# Botball_v7.net
KiCad netlist of a schematic drawn in EAGLE
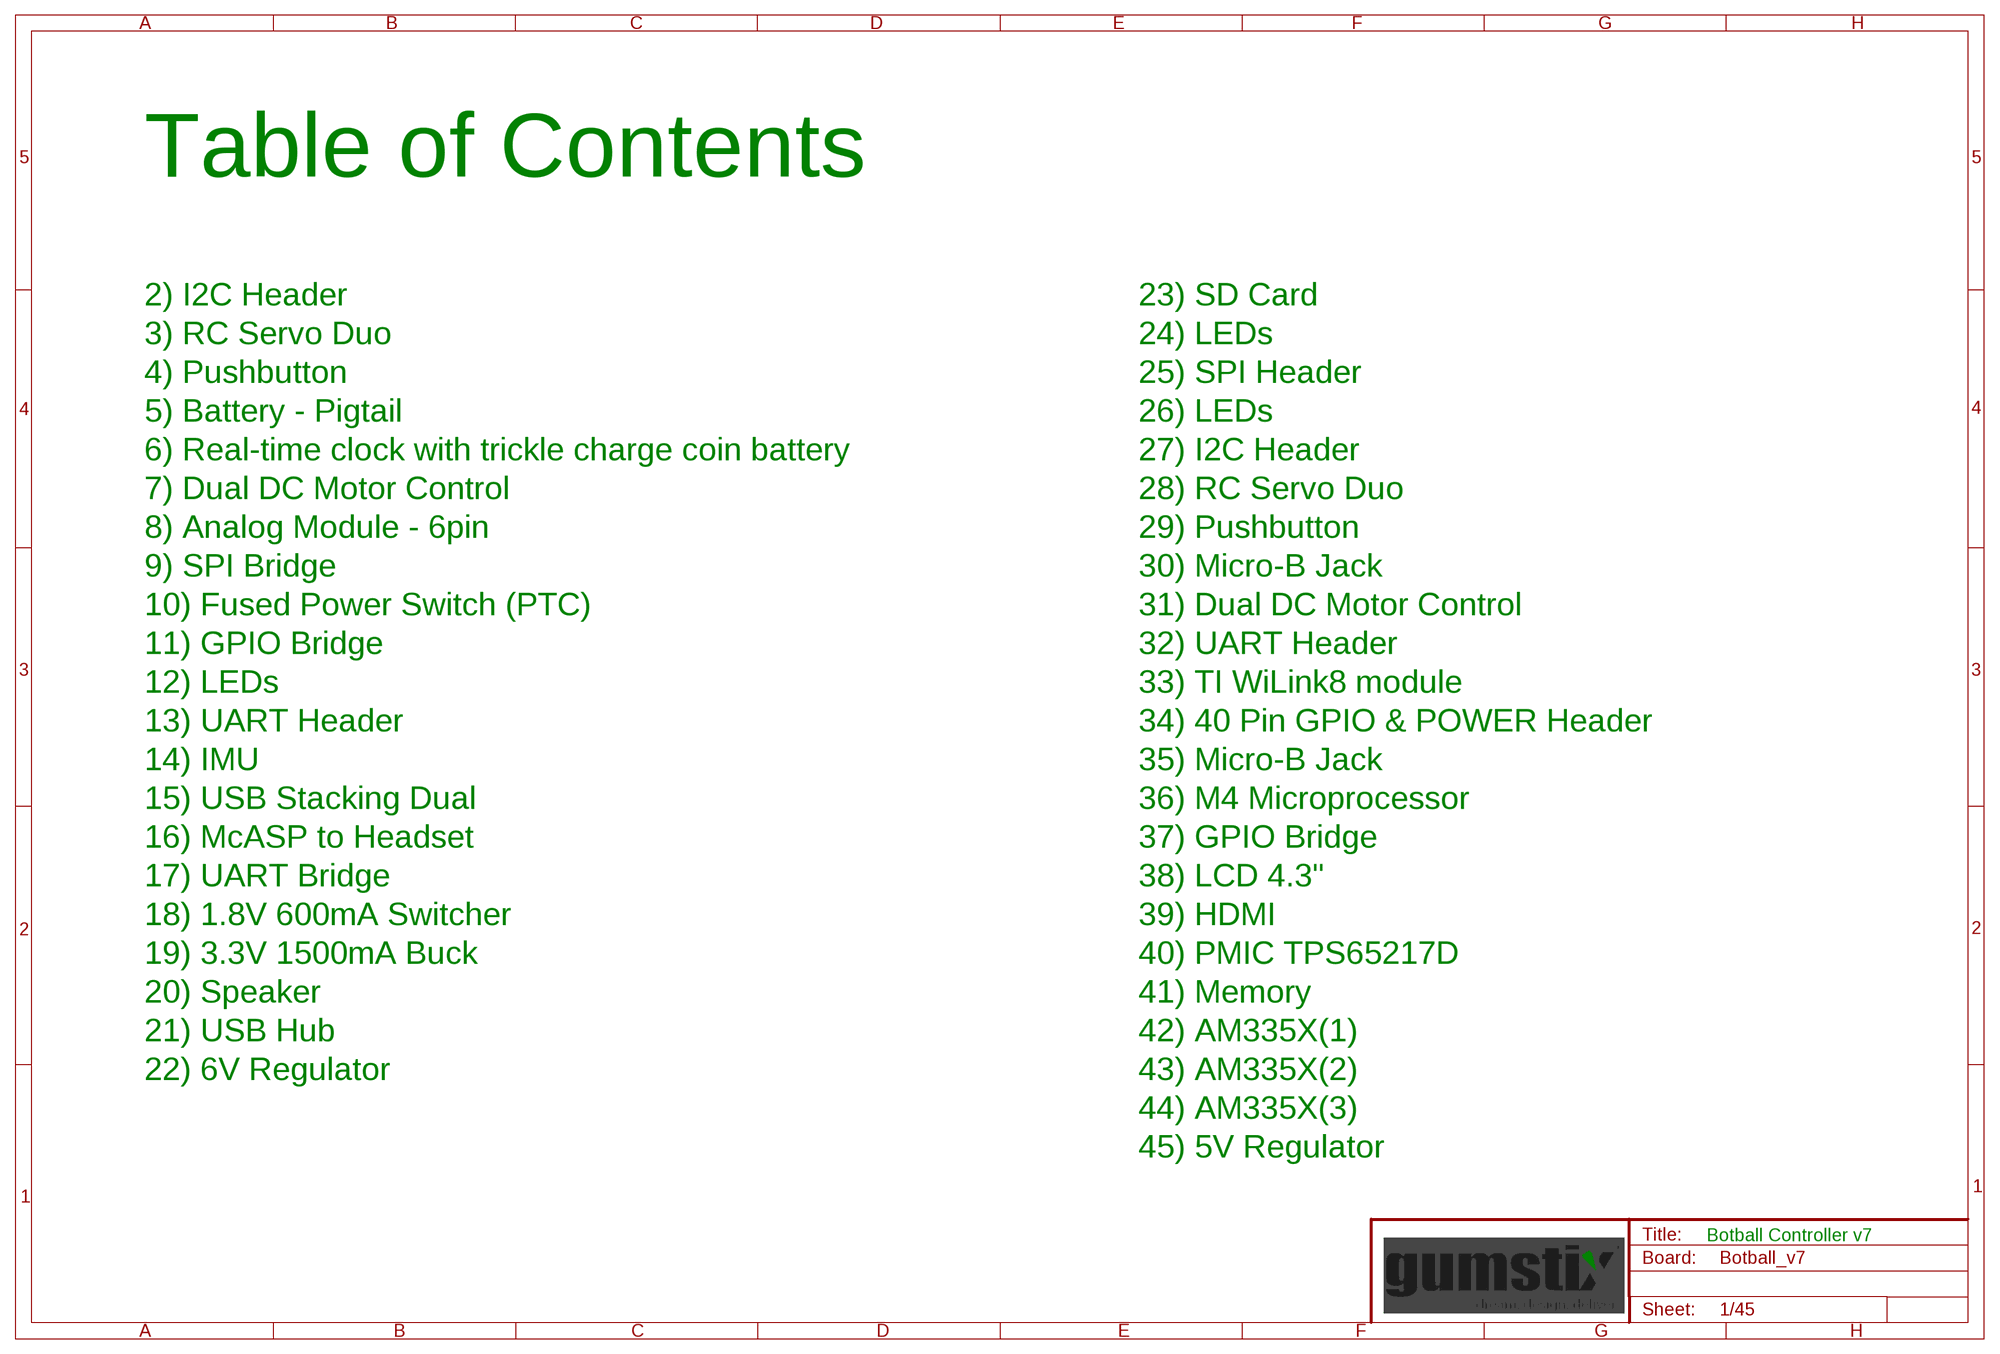
[diagram p0: schematic, sheet 1]
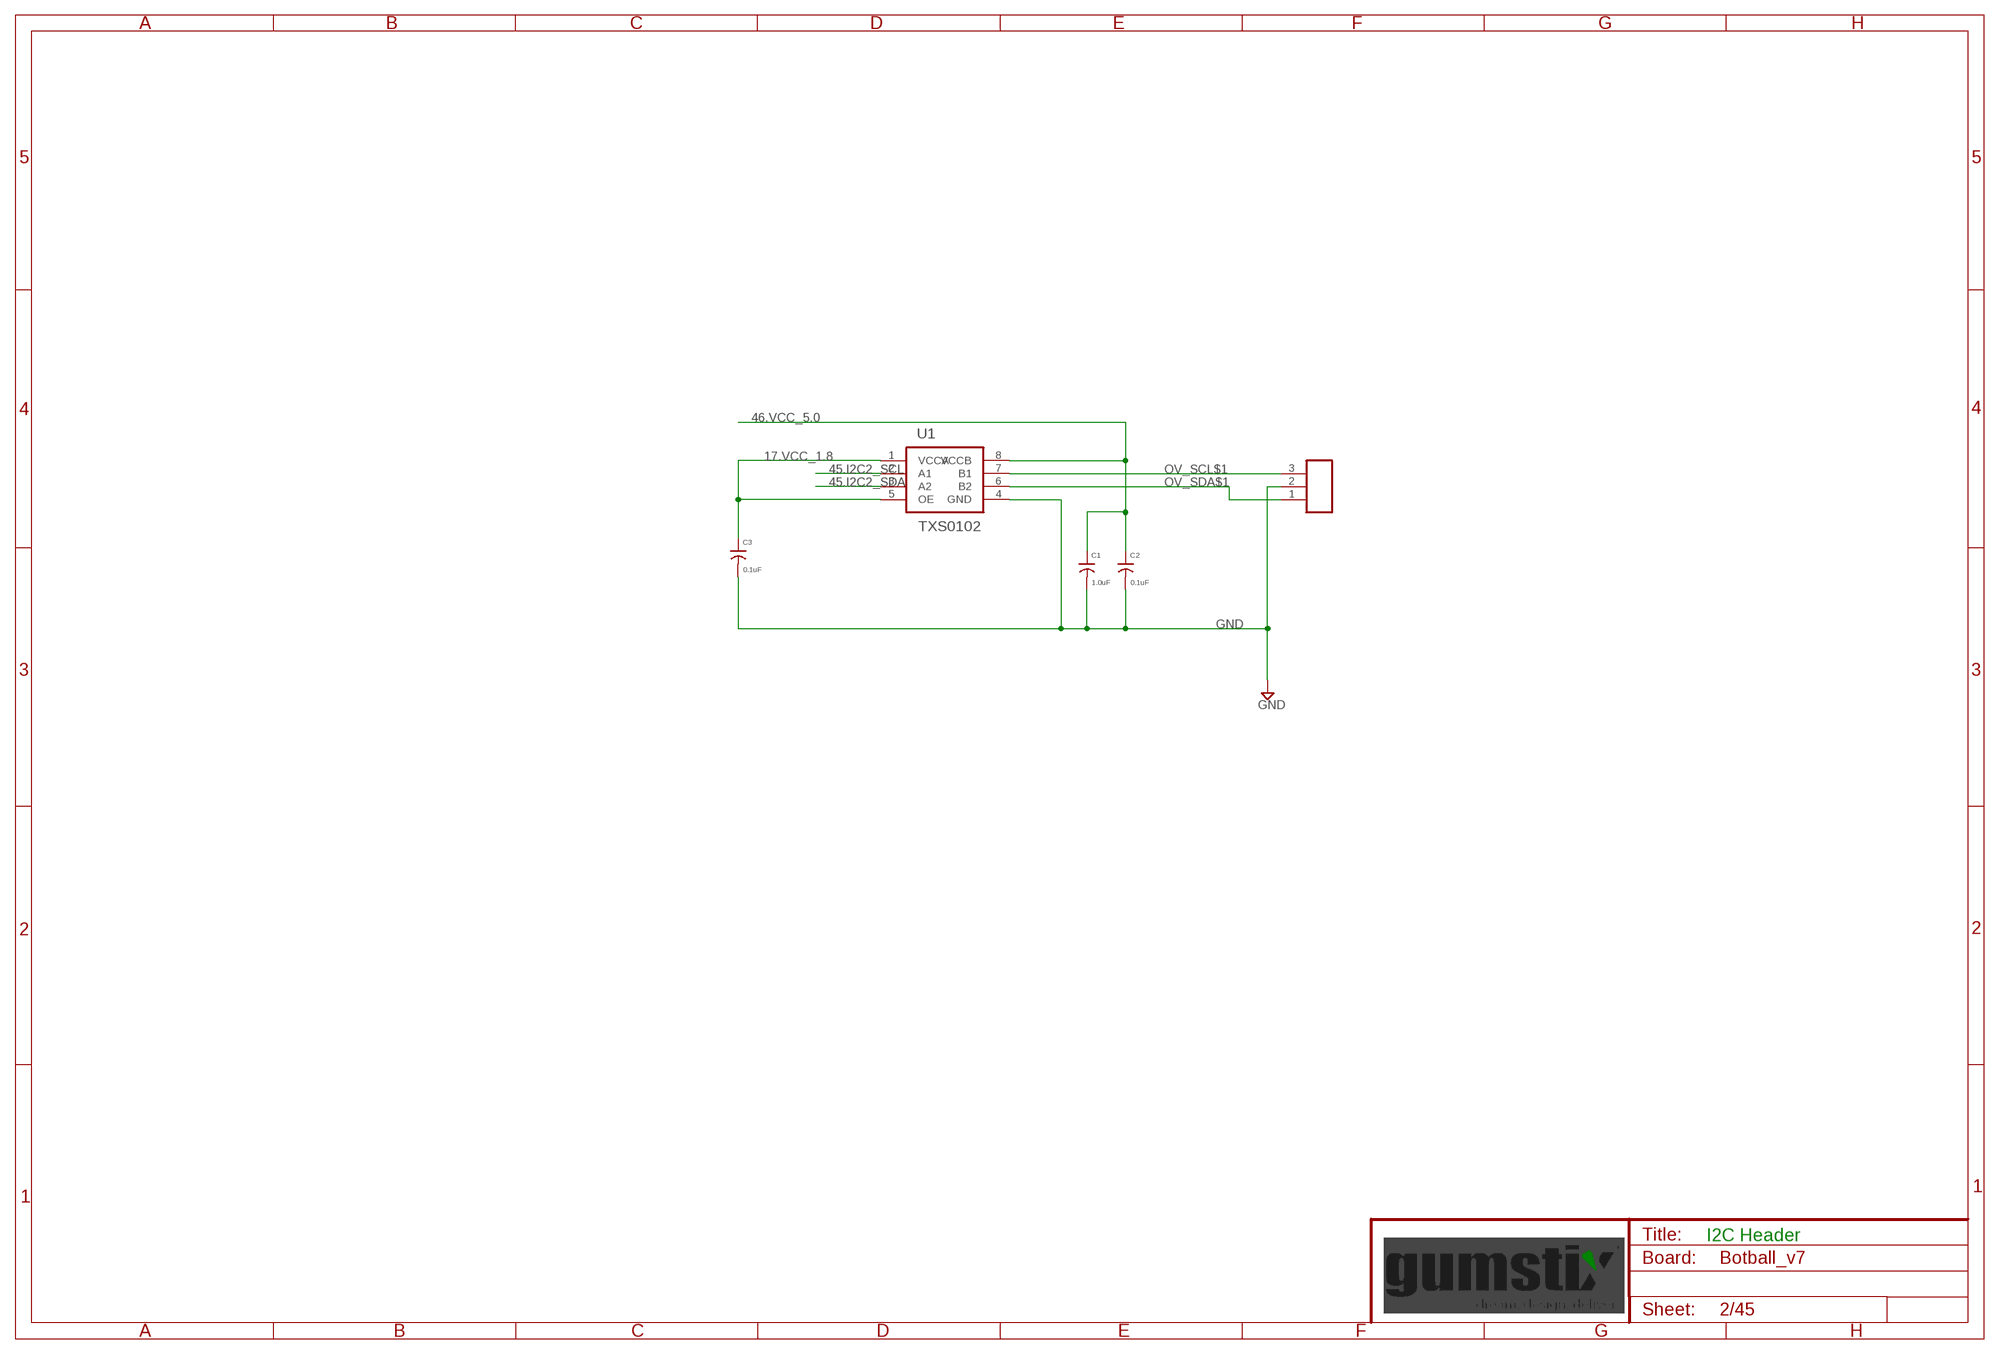
[diagram p1: schematic, sheet 2]
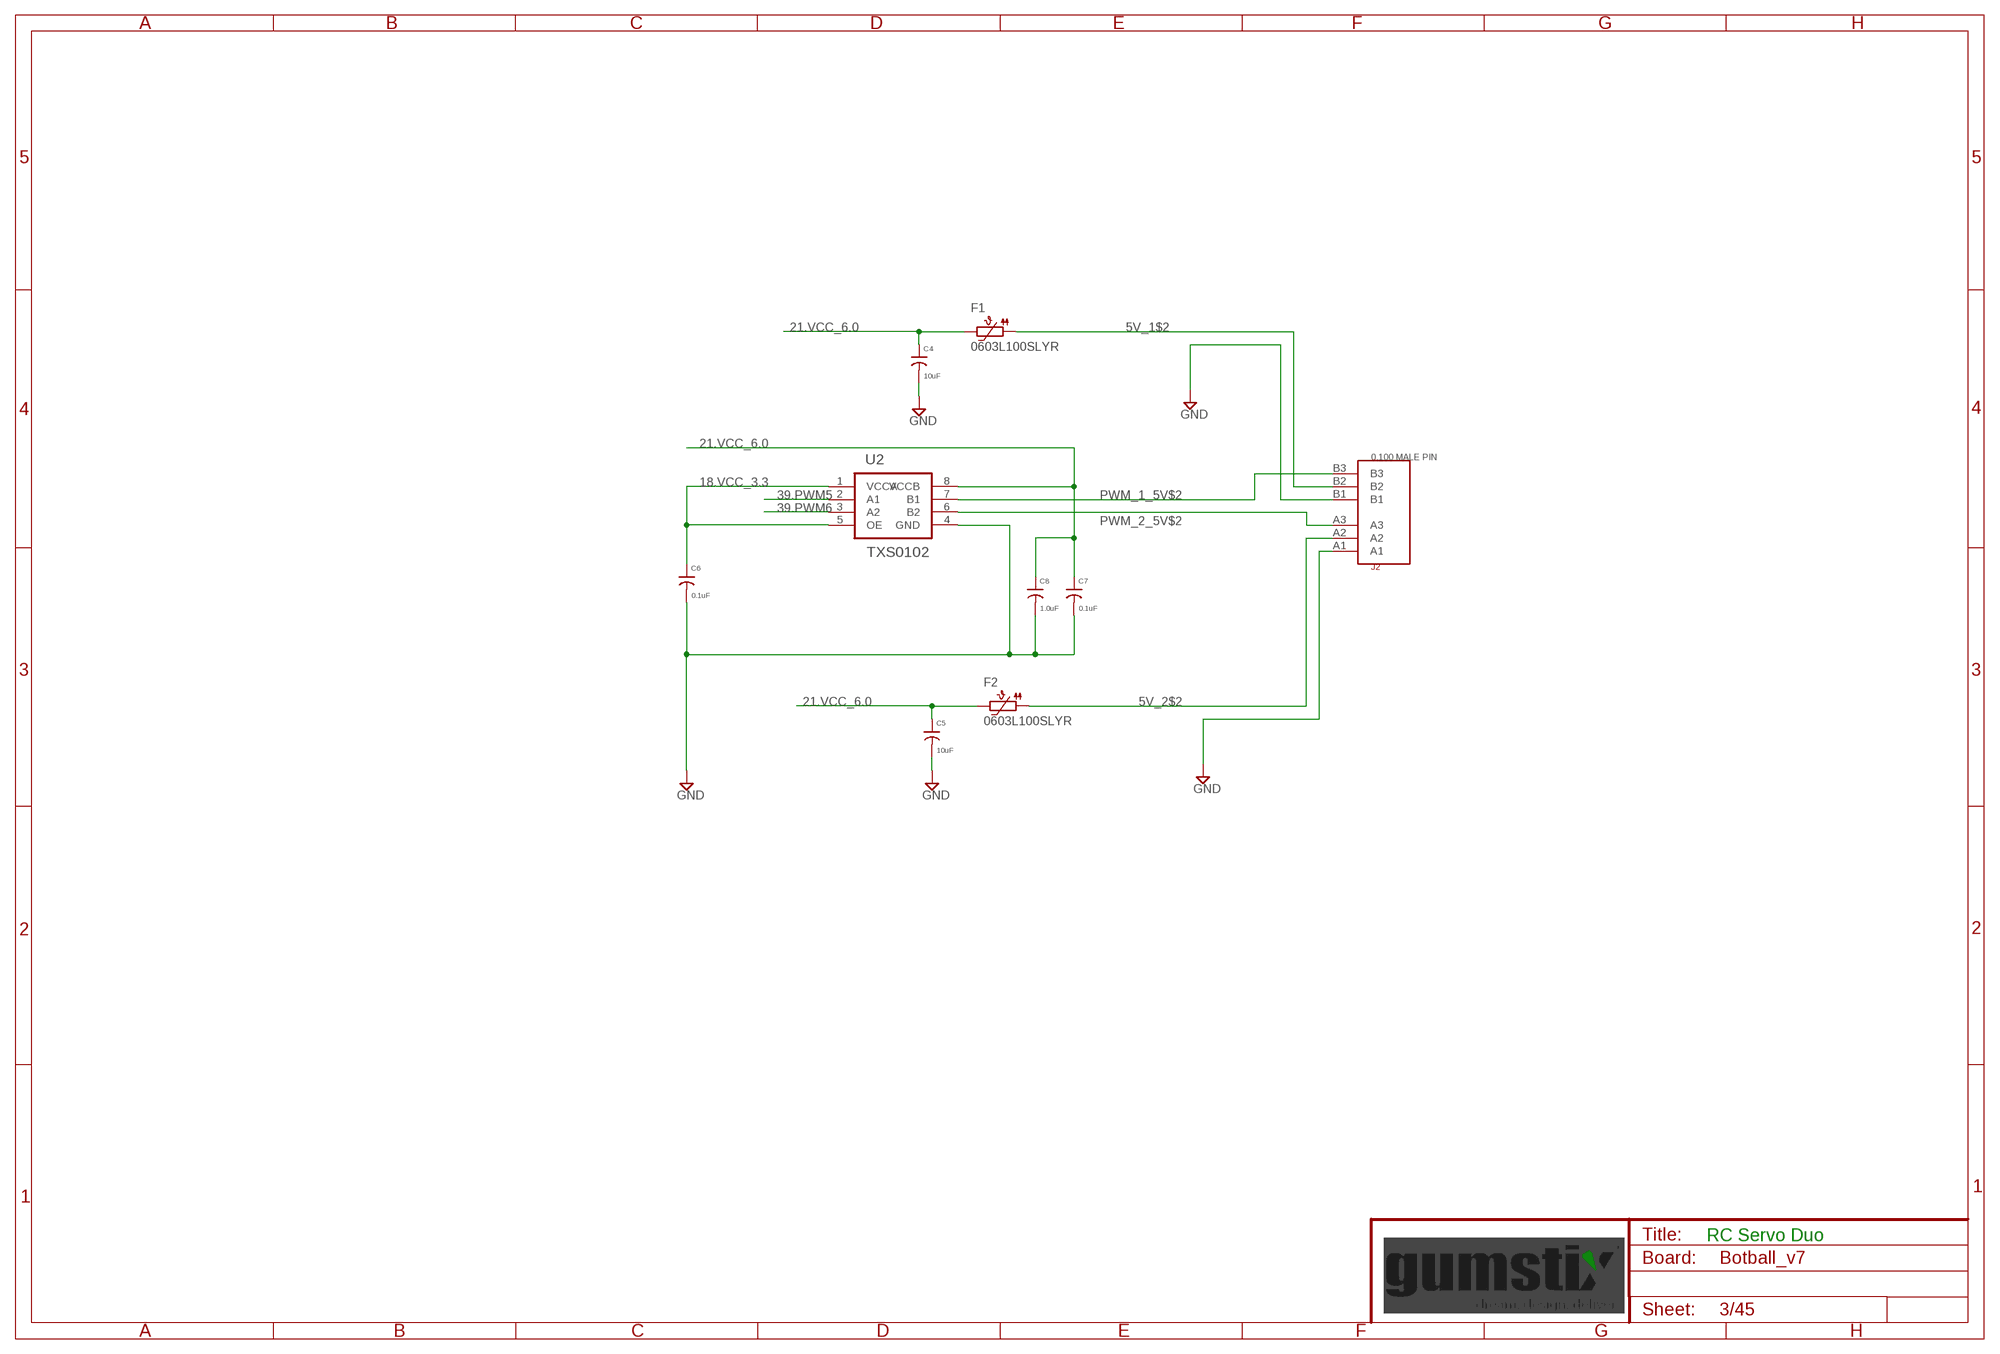
[diagram p2: schematic, sheet 3]
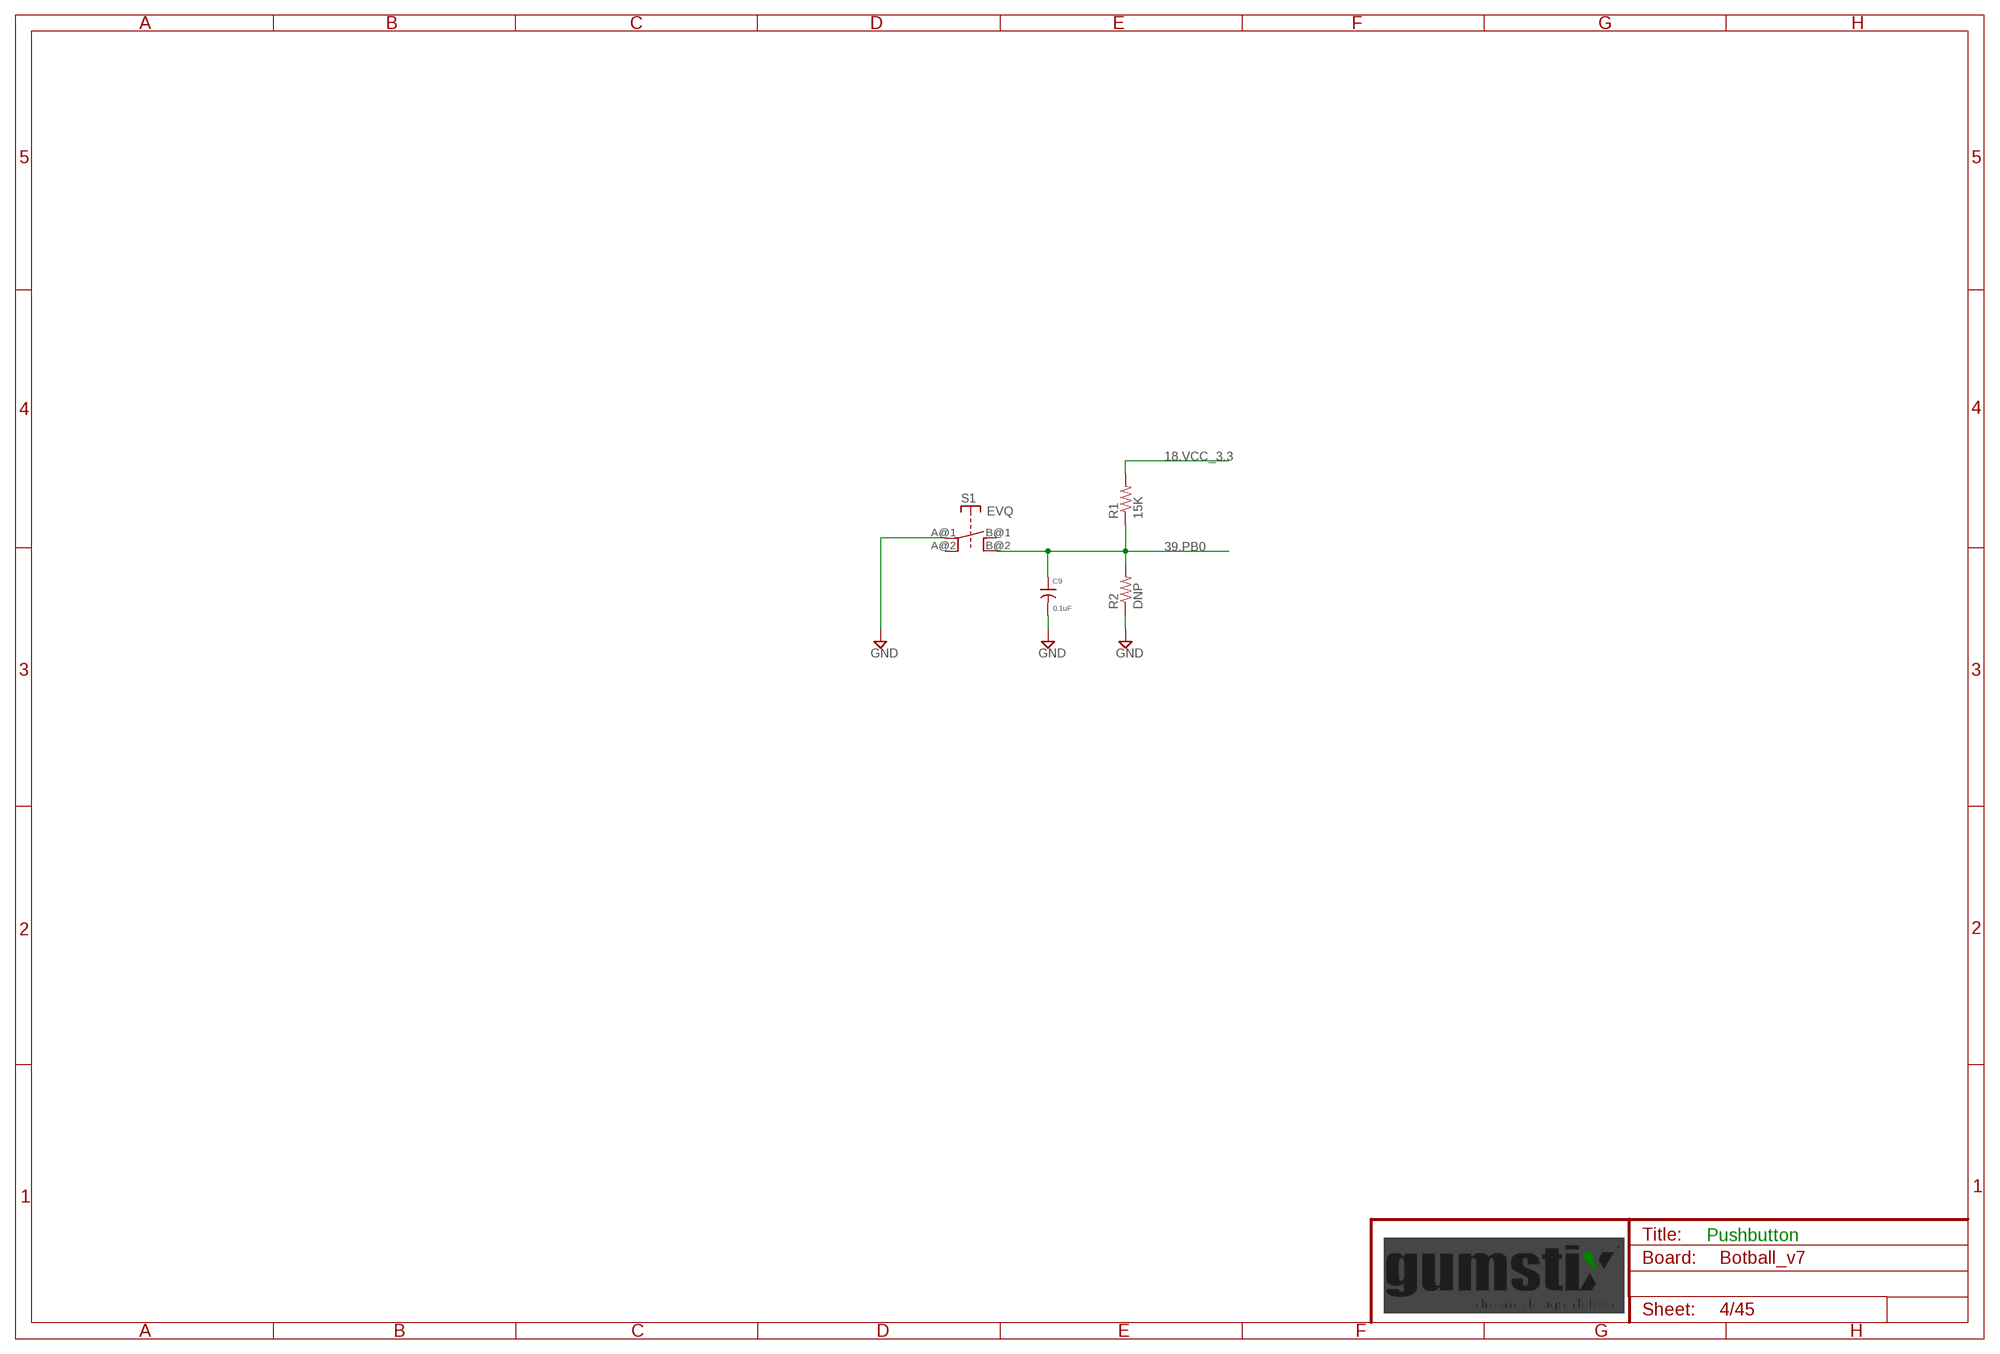
[diagram p3: schematic, sheet 4]
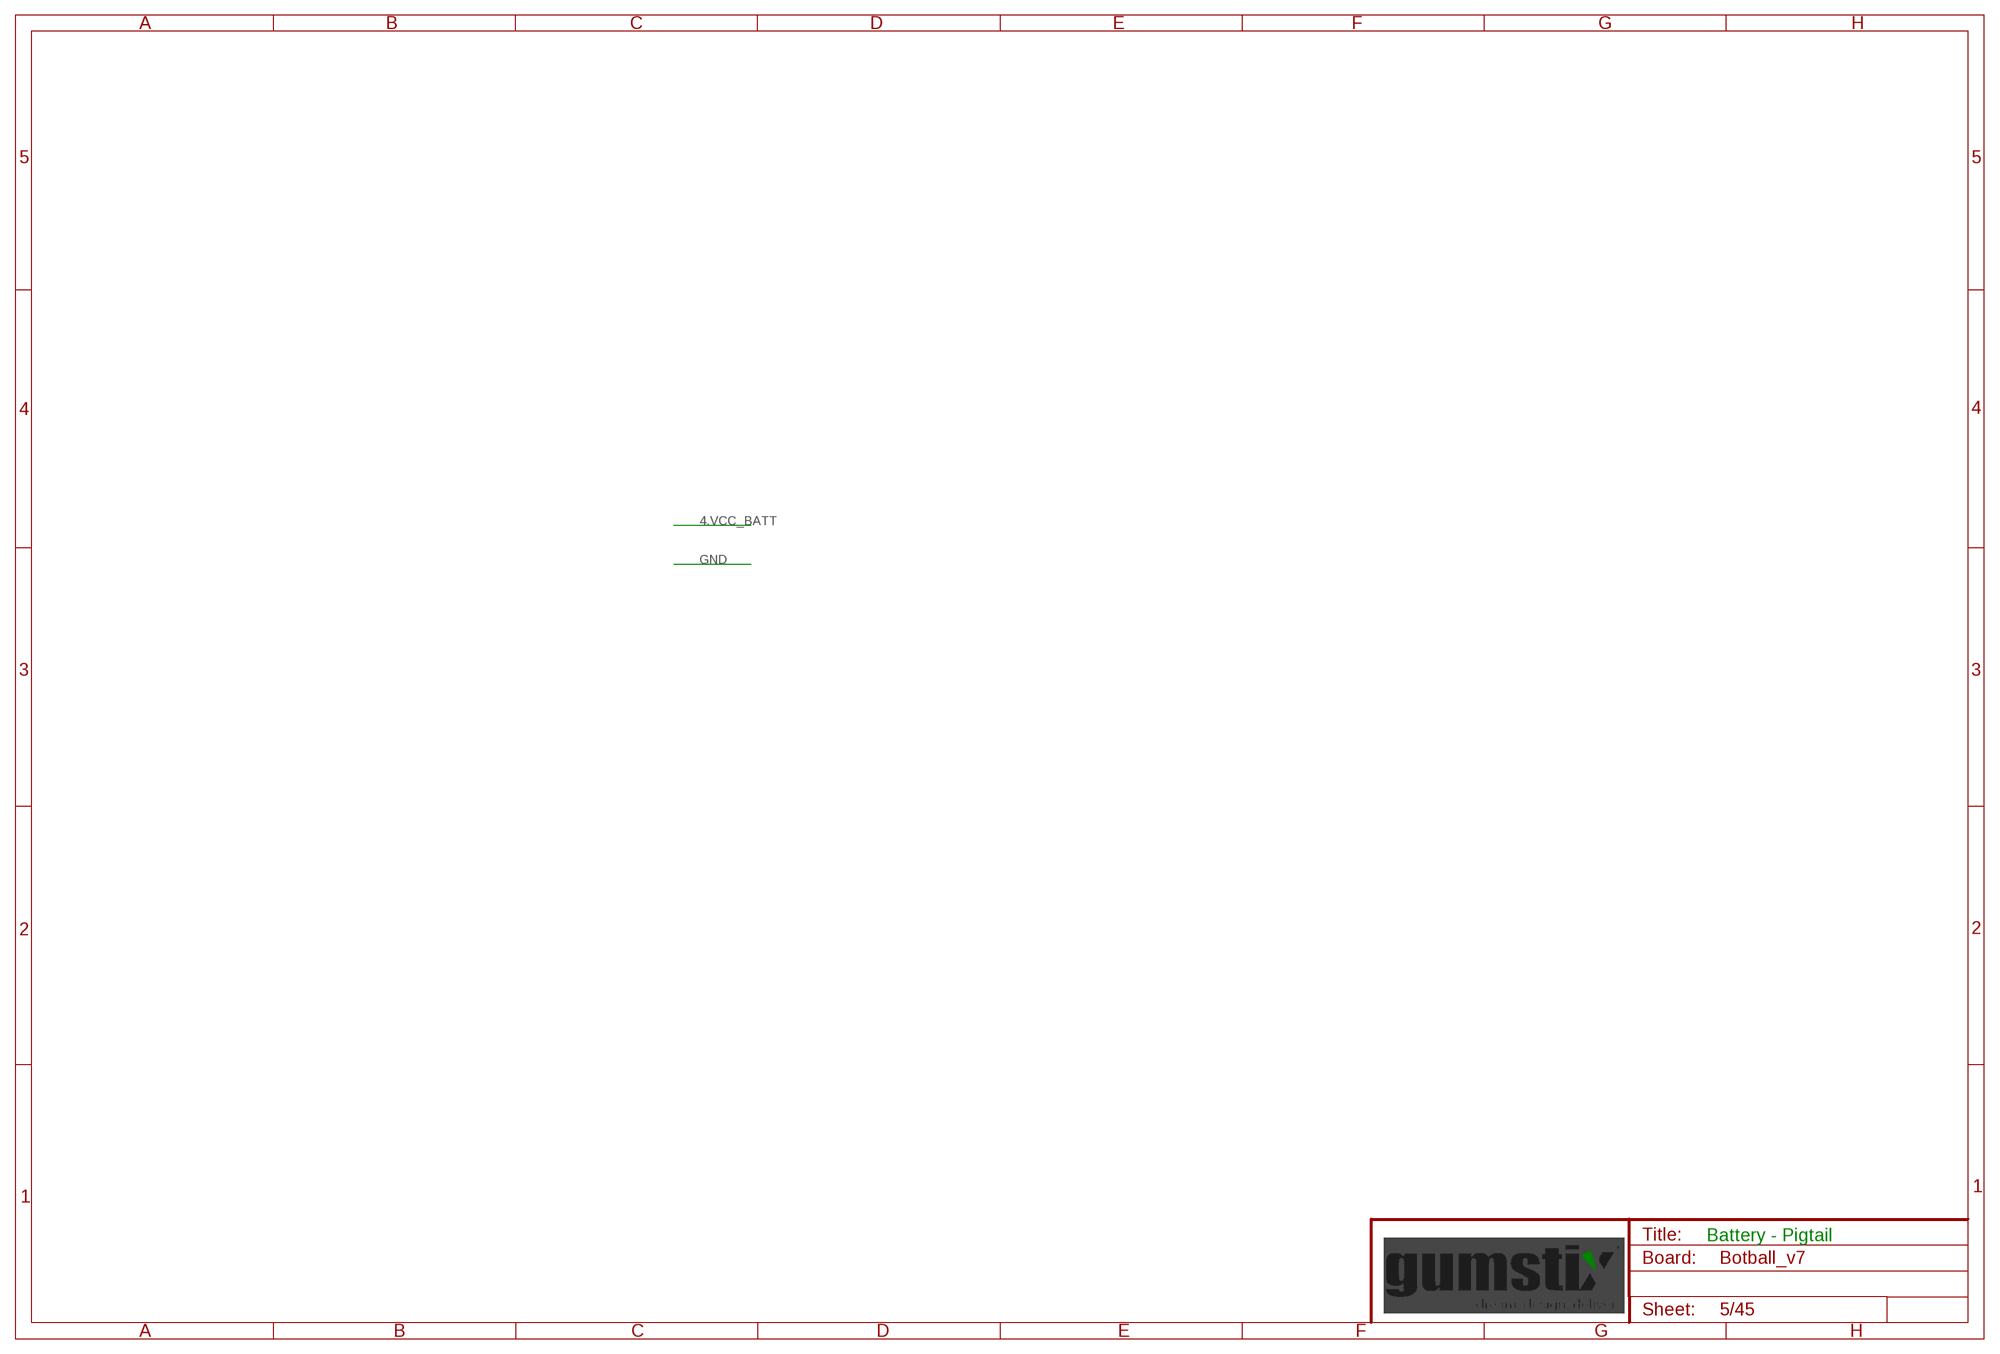
[diagram p4: schematic, sheet 5]
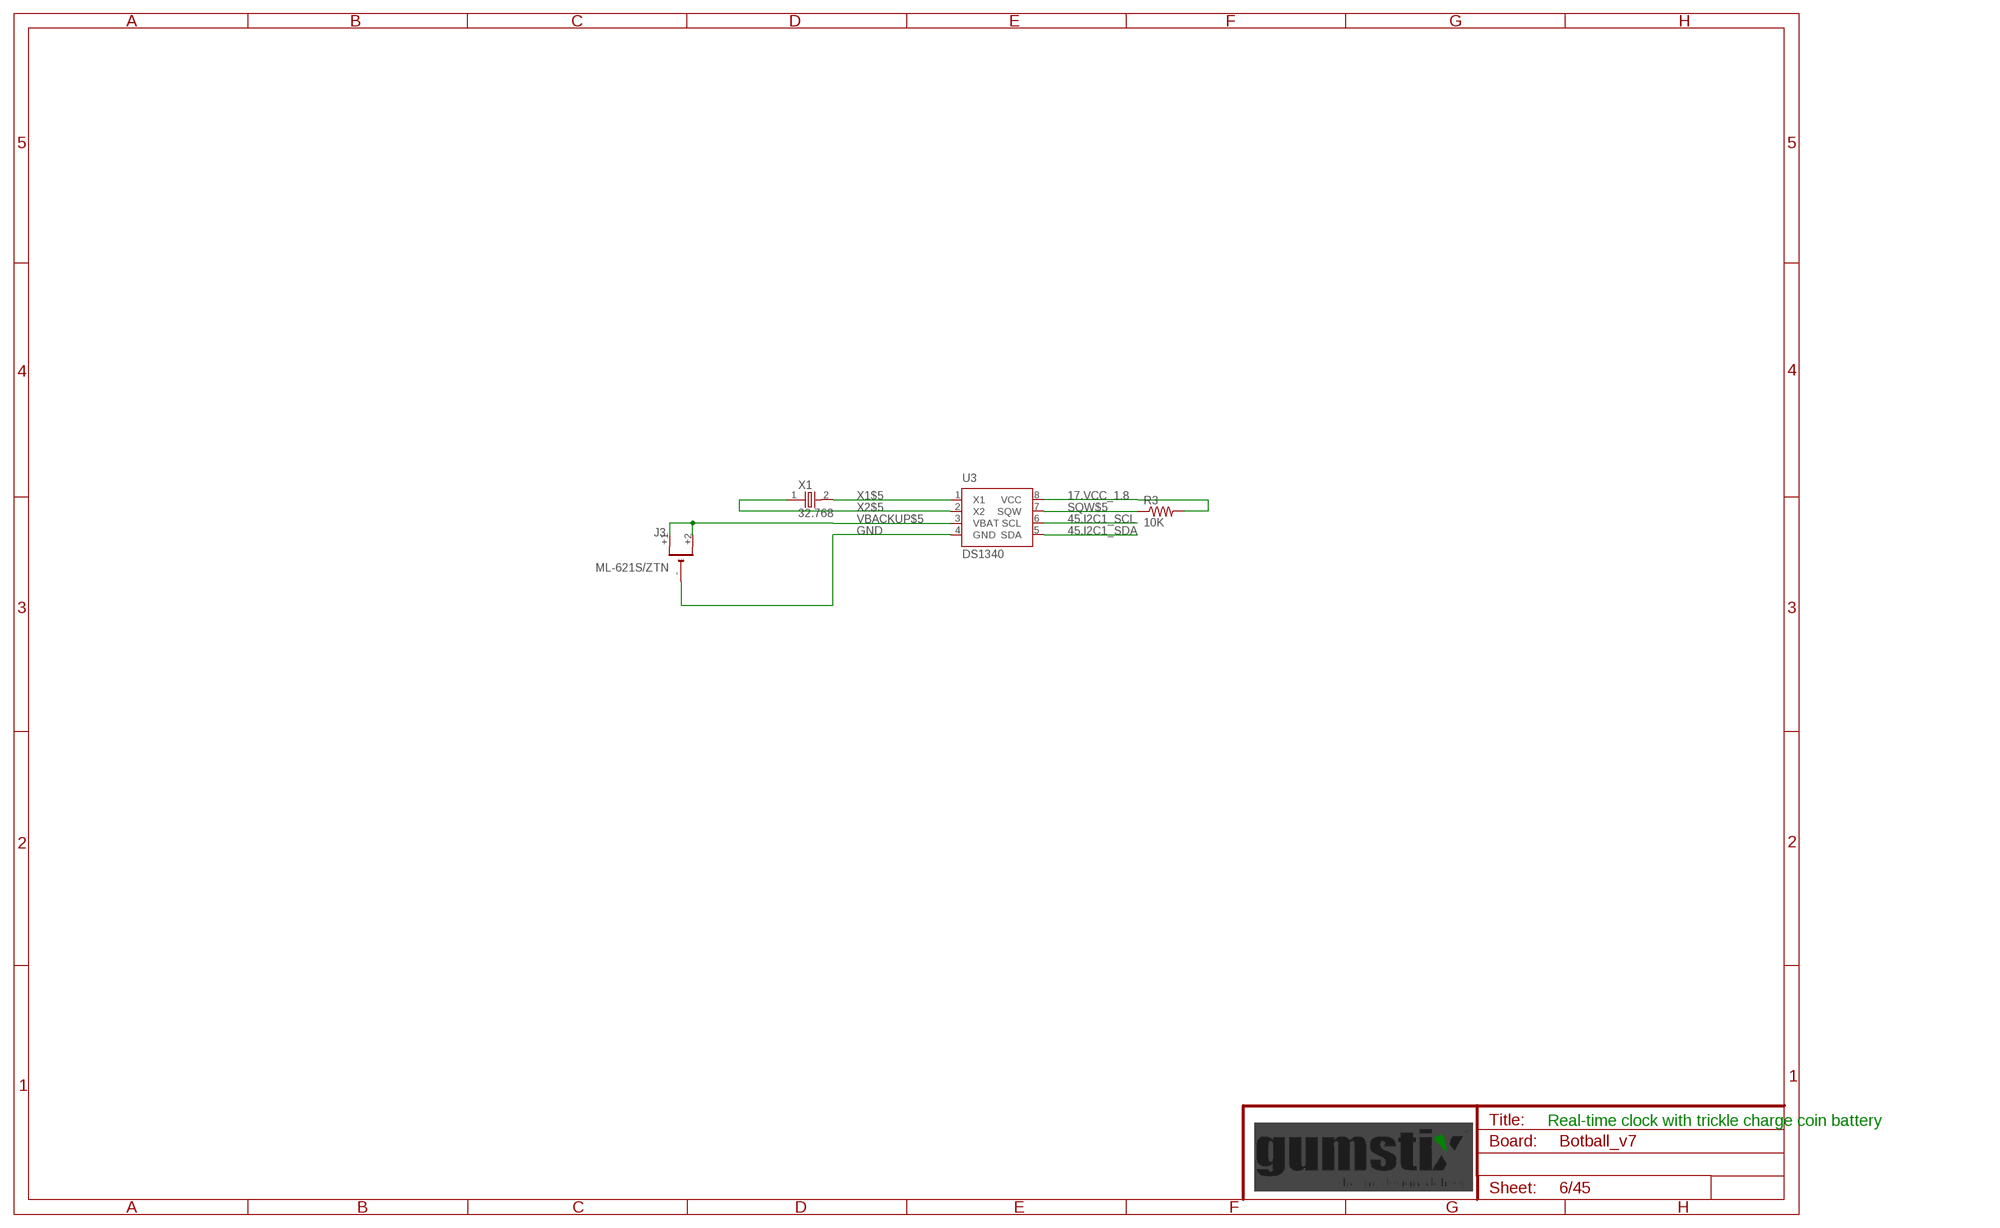
[diagram p5: schematic, sheet 6]
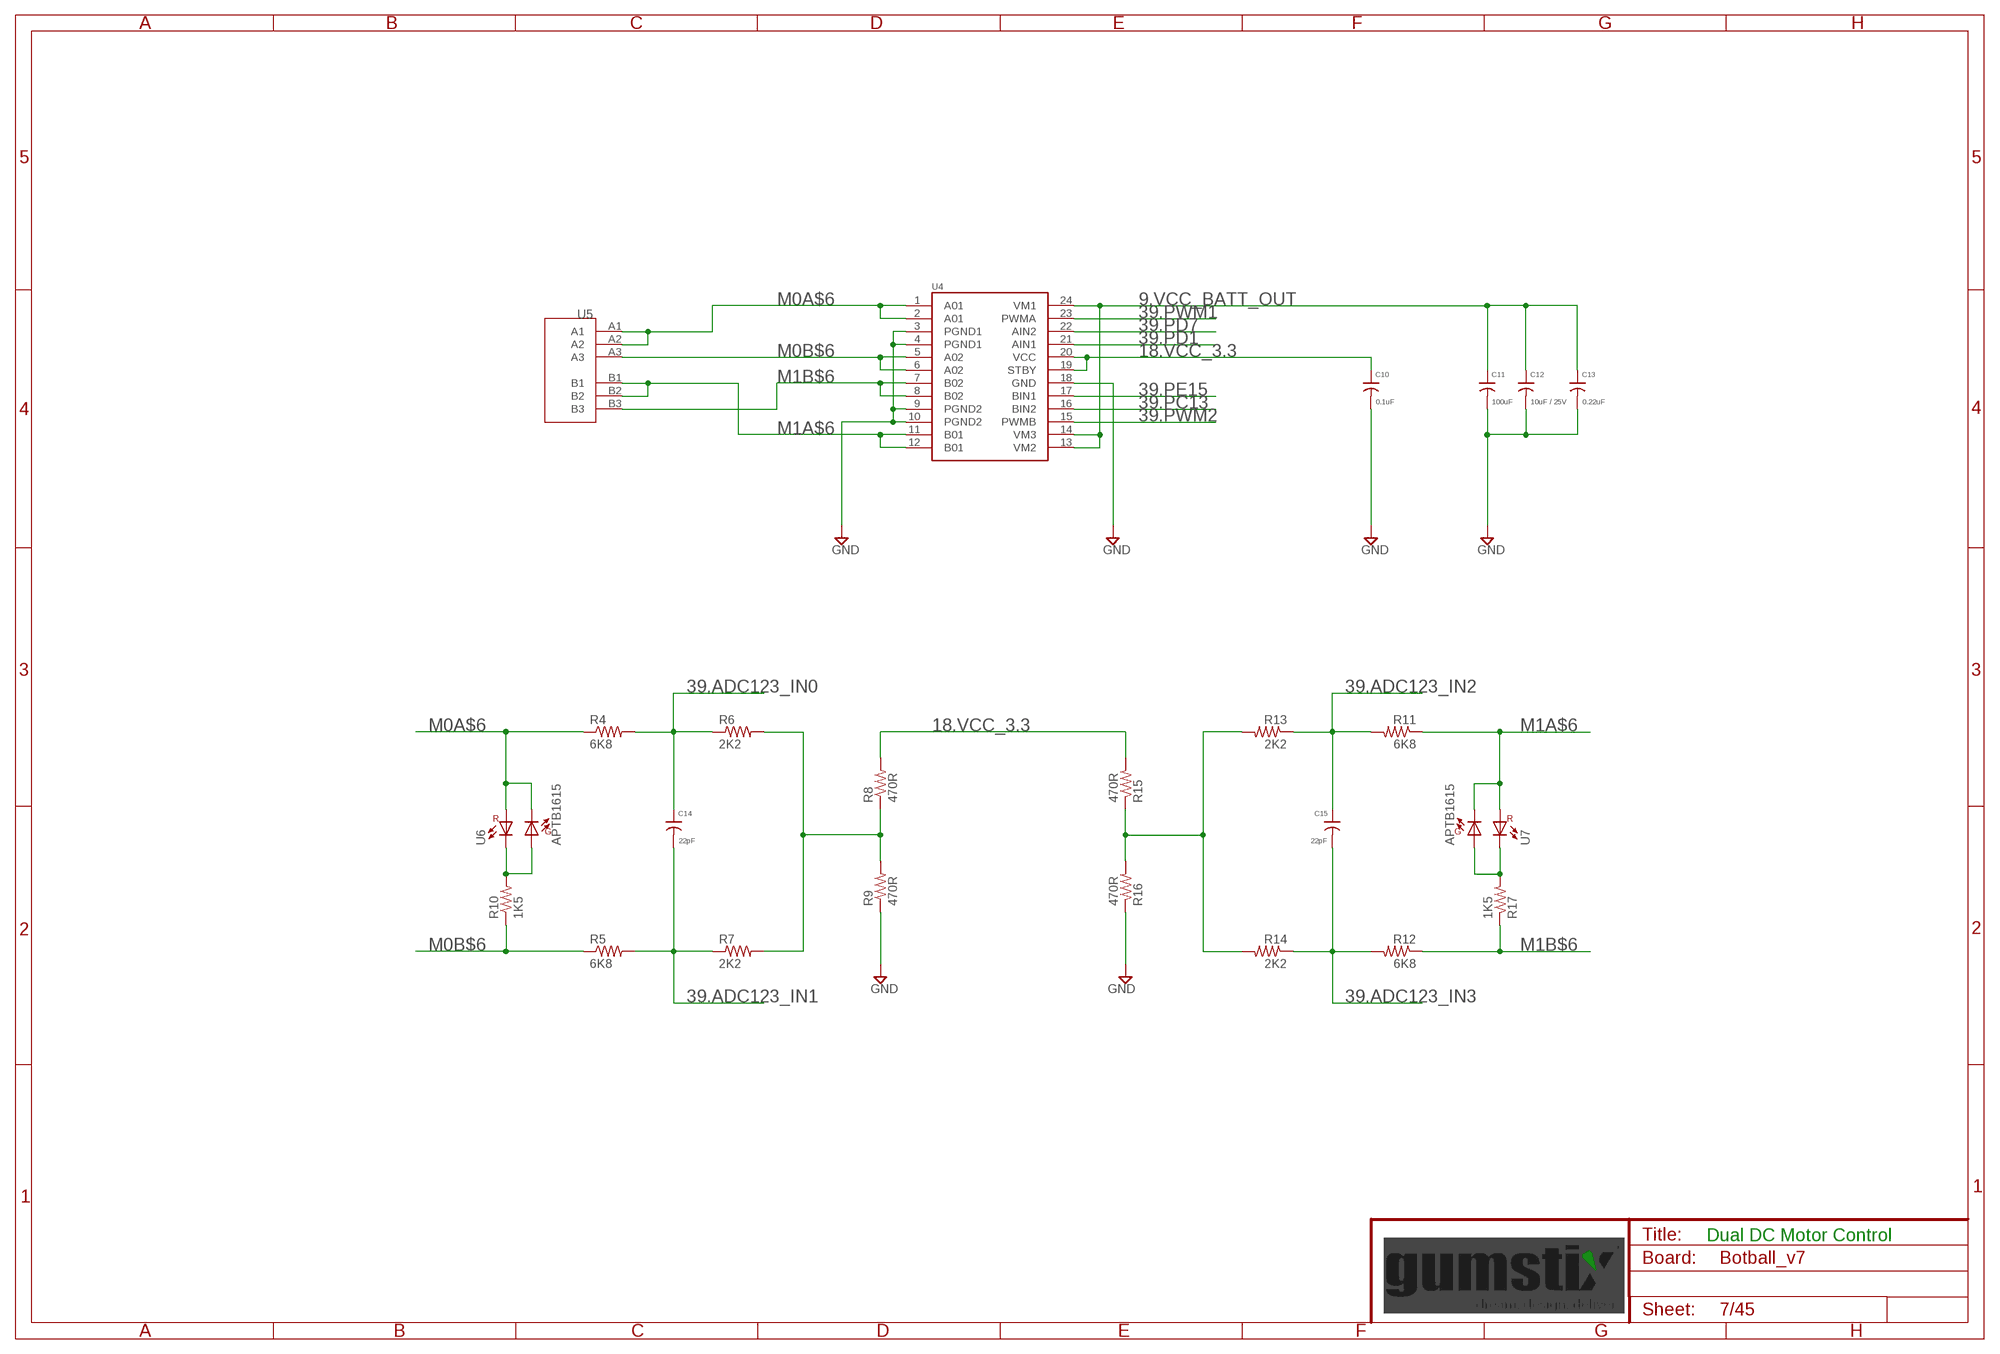
[diagram p6: schematic, sheet 7]
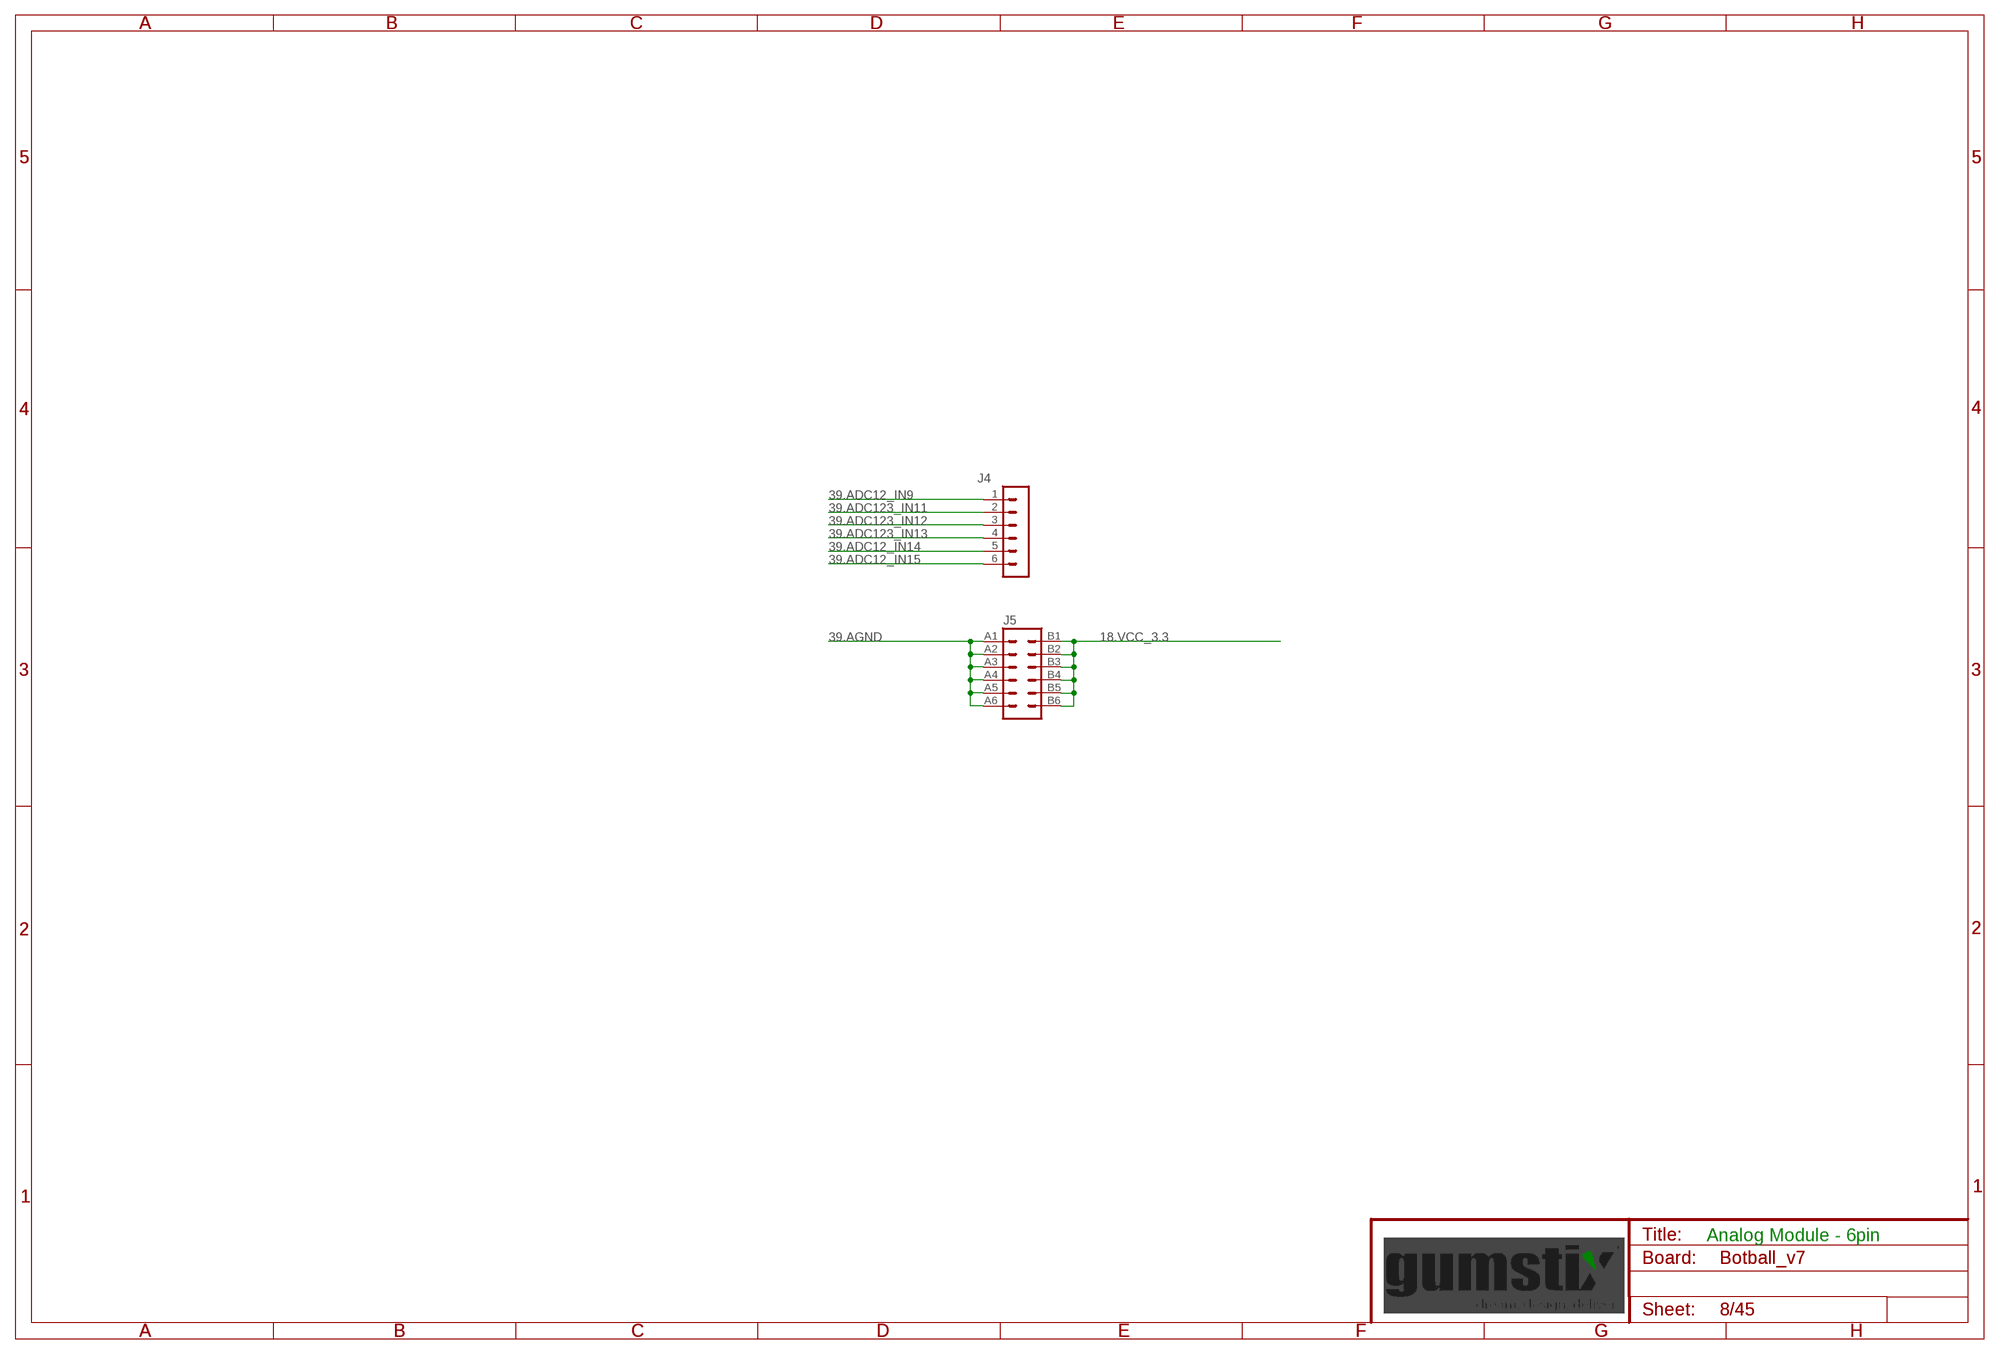
[diagram p7: schematic, sheet 8]
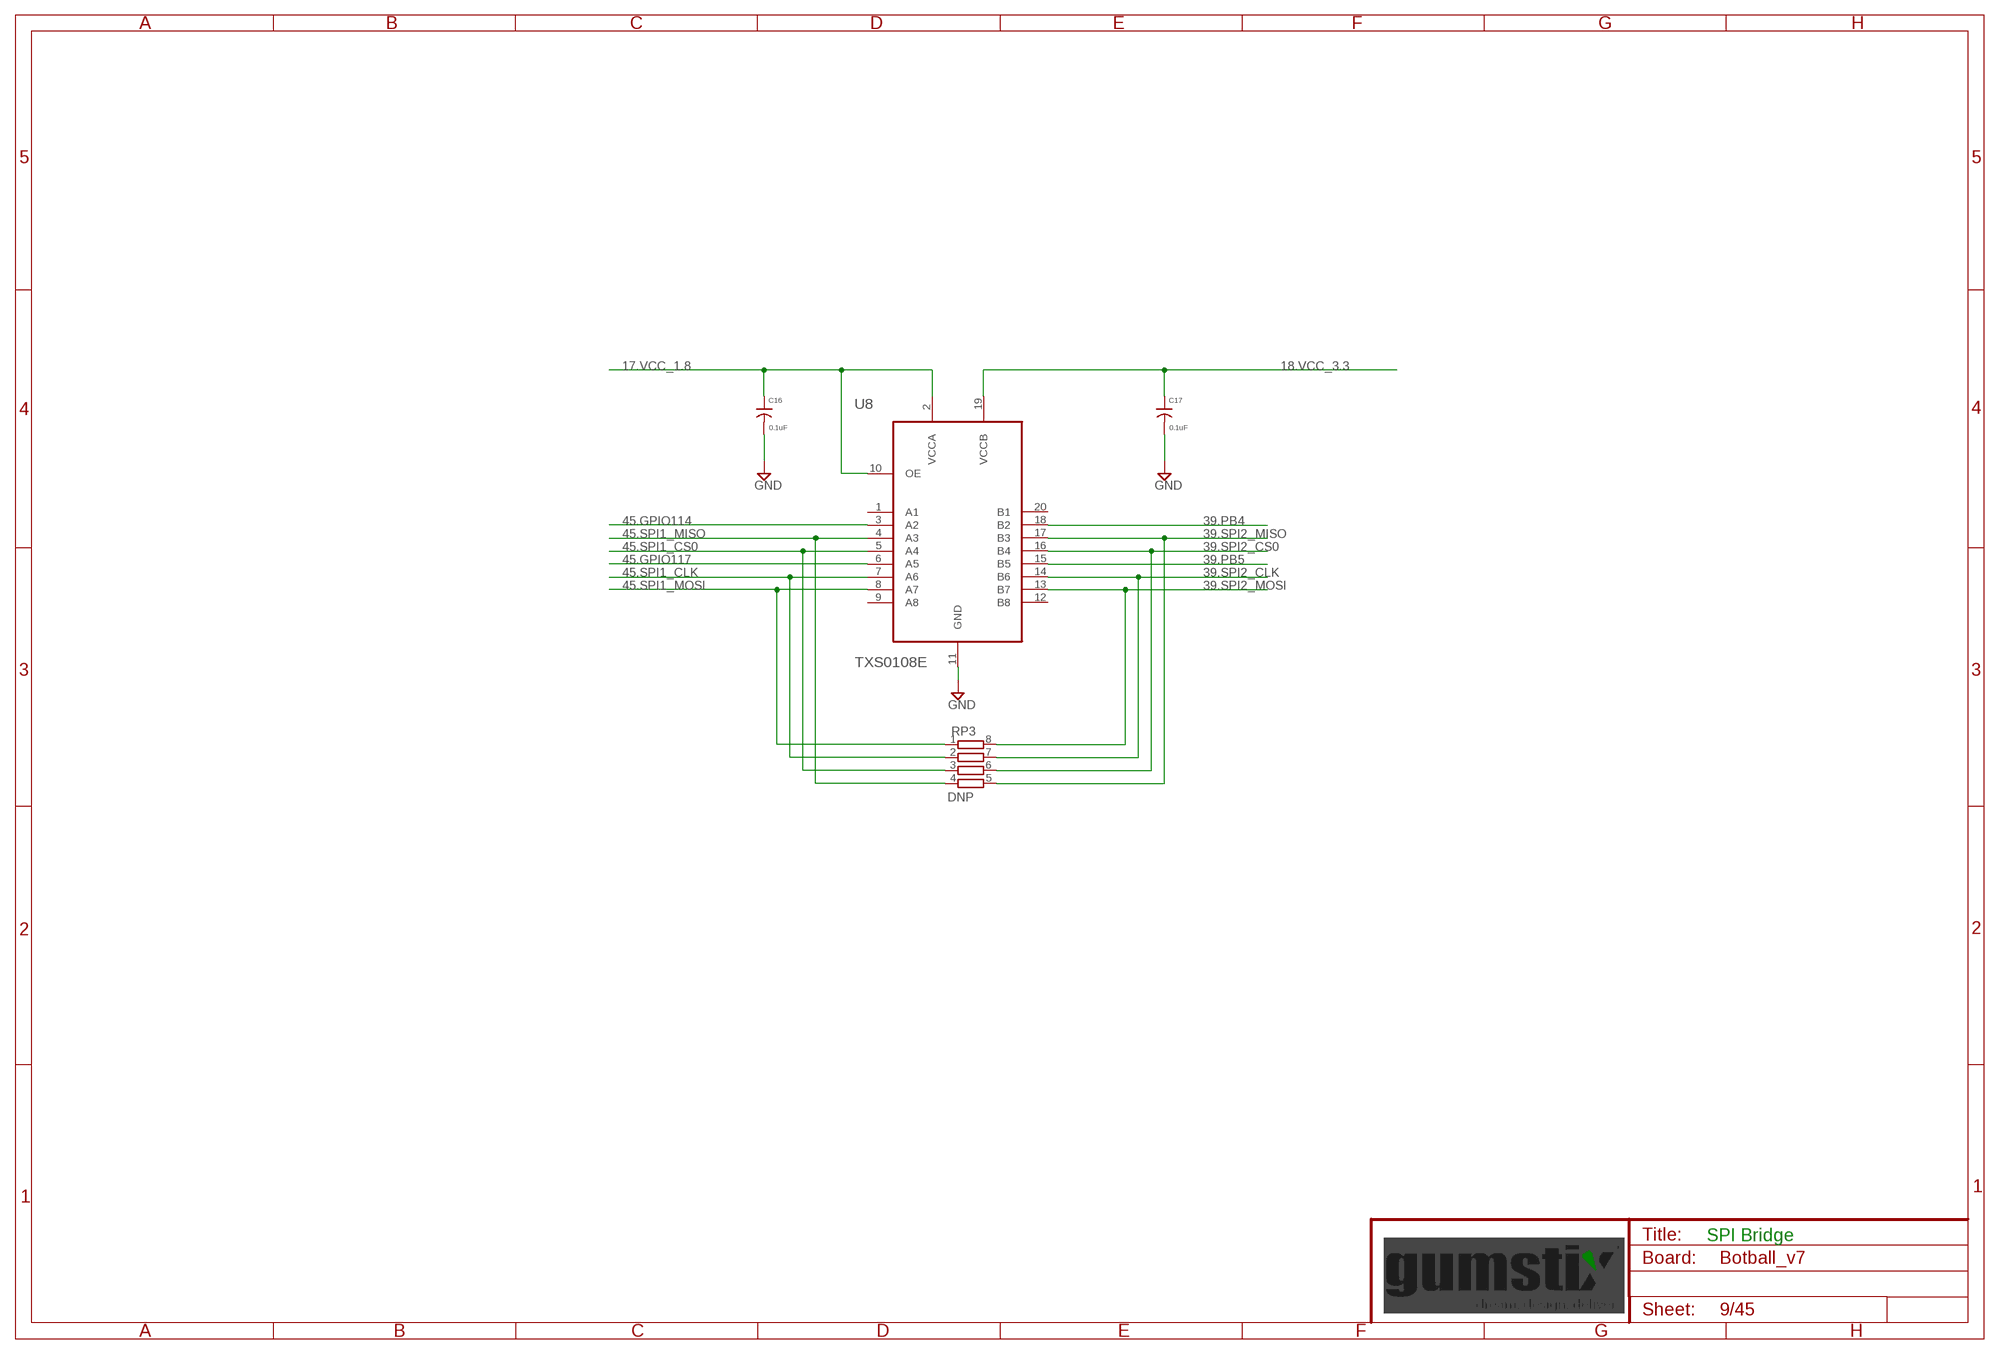
[diagram p8: schematic, sheet 9]
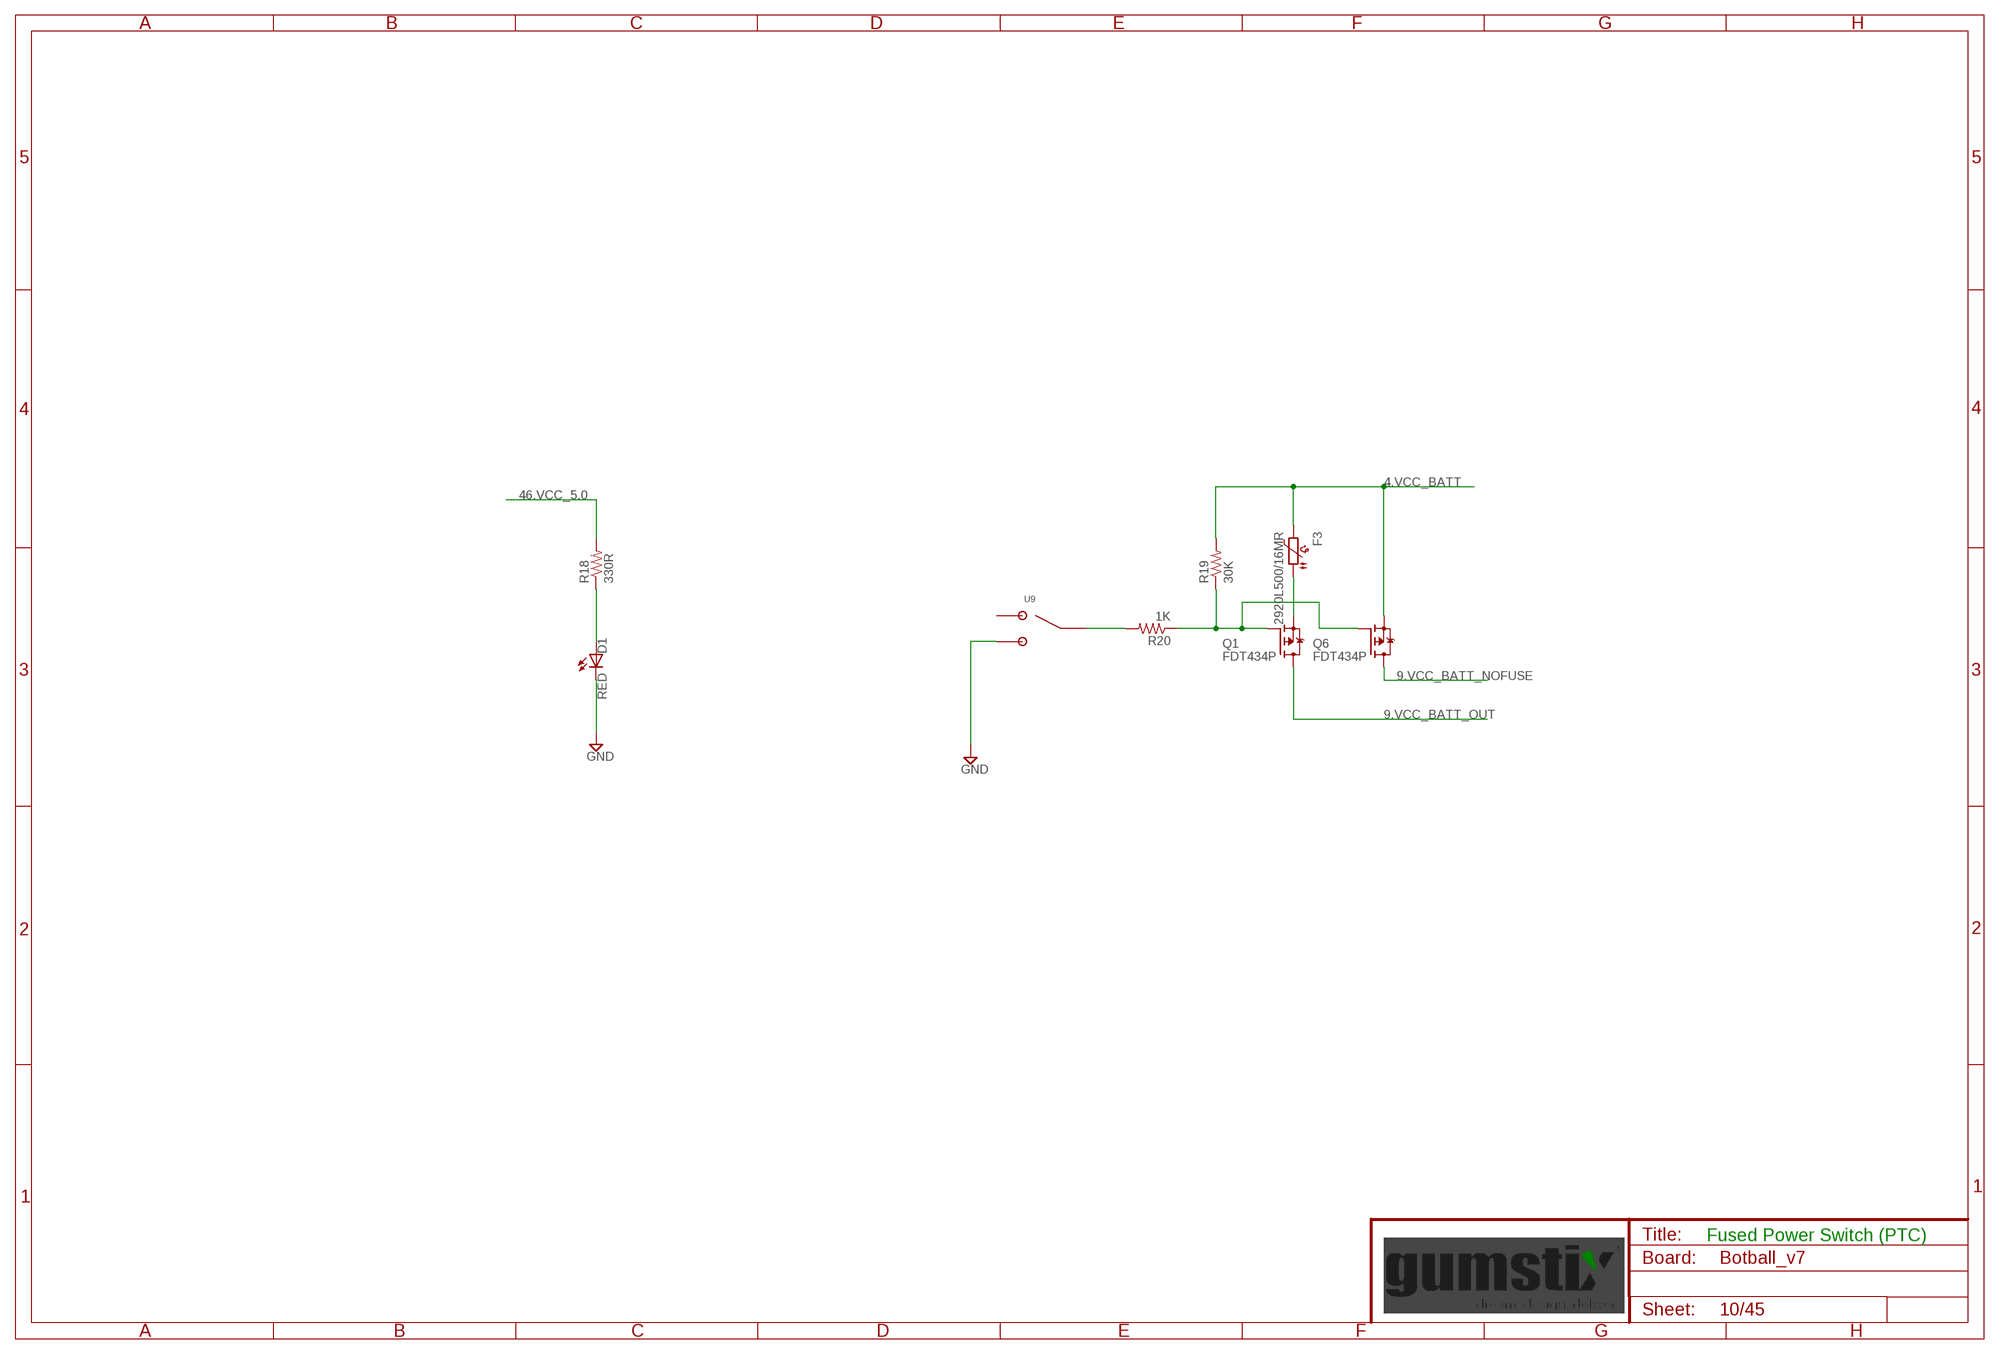
[diagram p9: schematic, sheet 10]
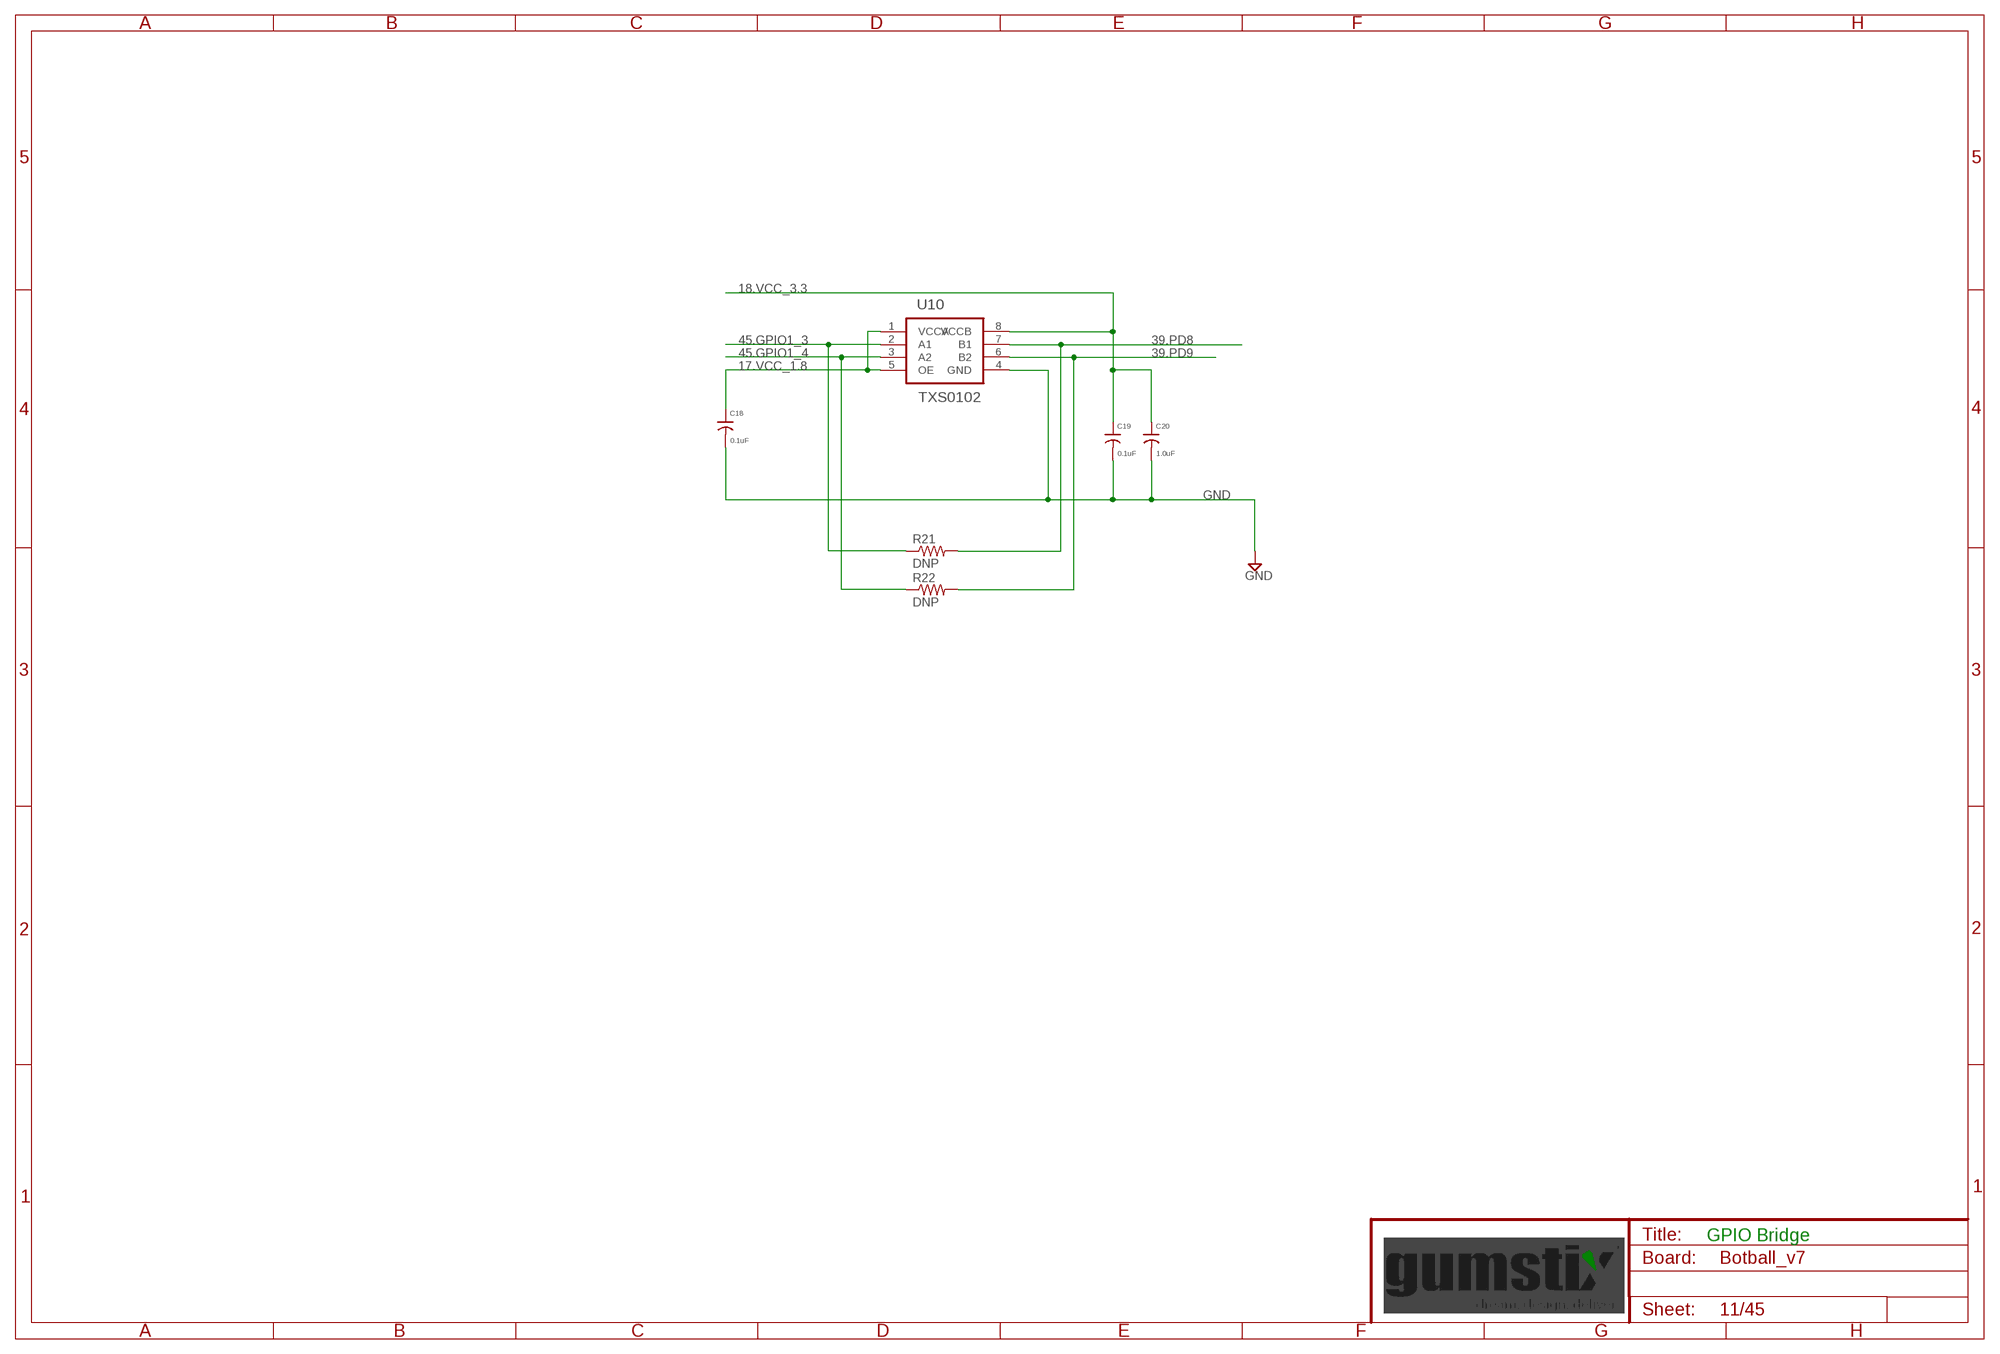
[diagram p10: schematic, sheet 11]
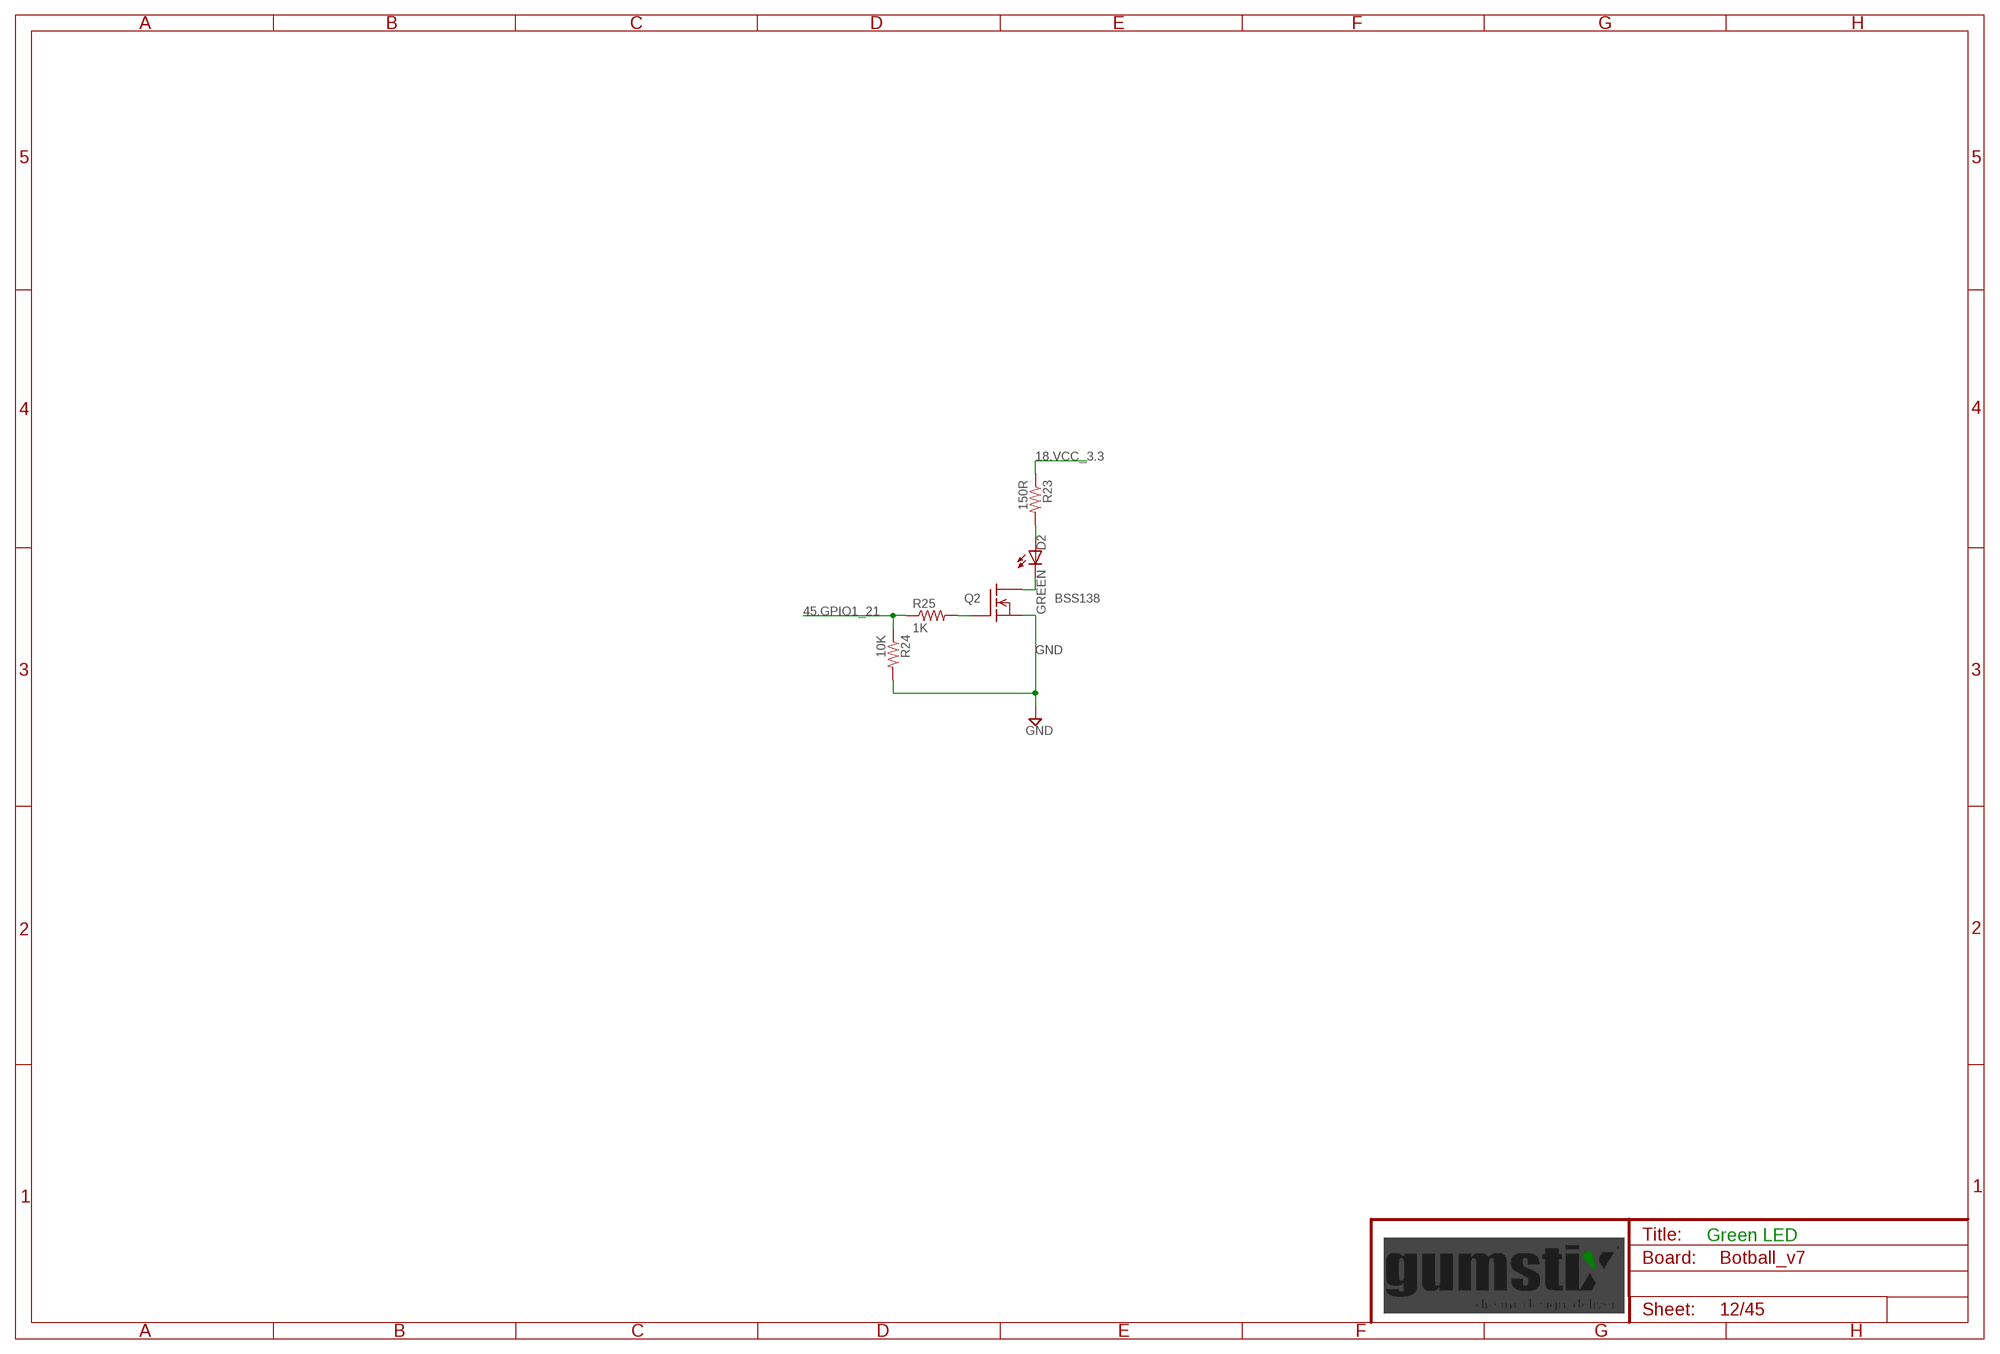
[diagram p11: schematic, sheet 12]
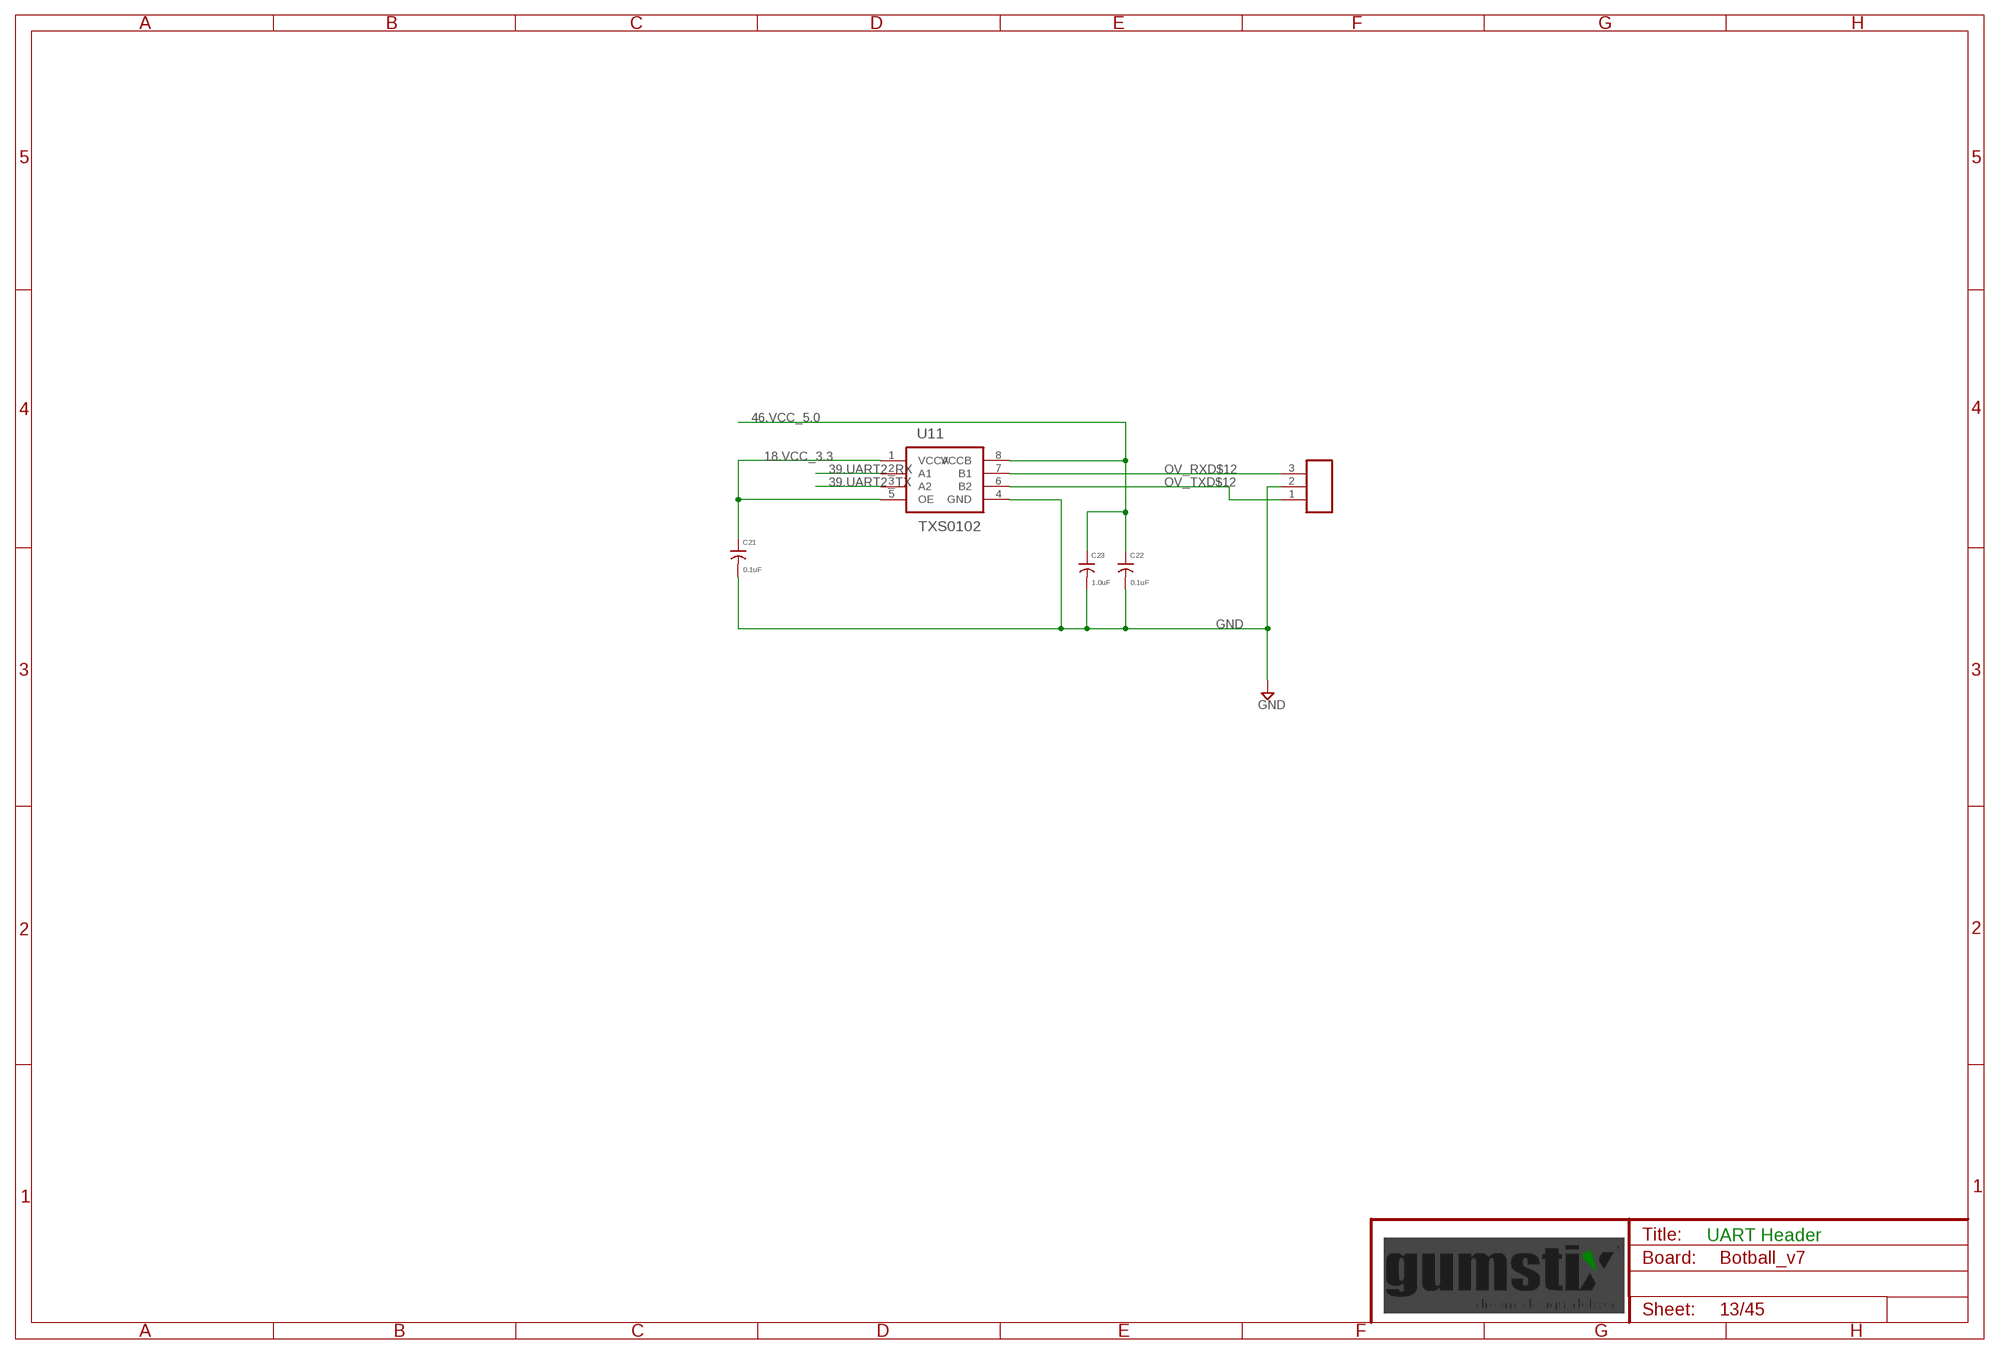
[diagram p12: schematic, sheet 13]
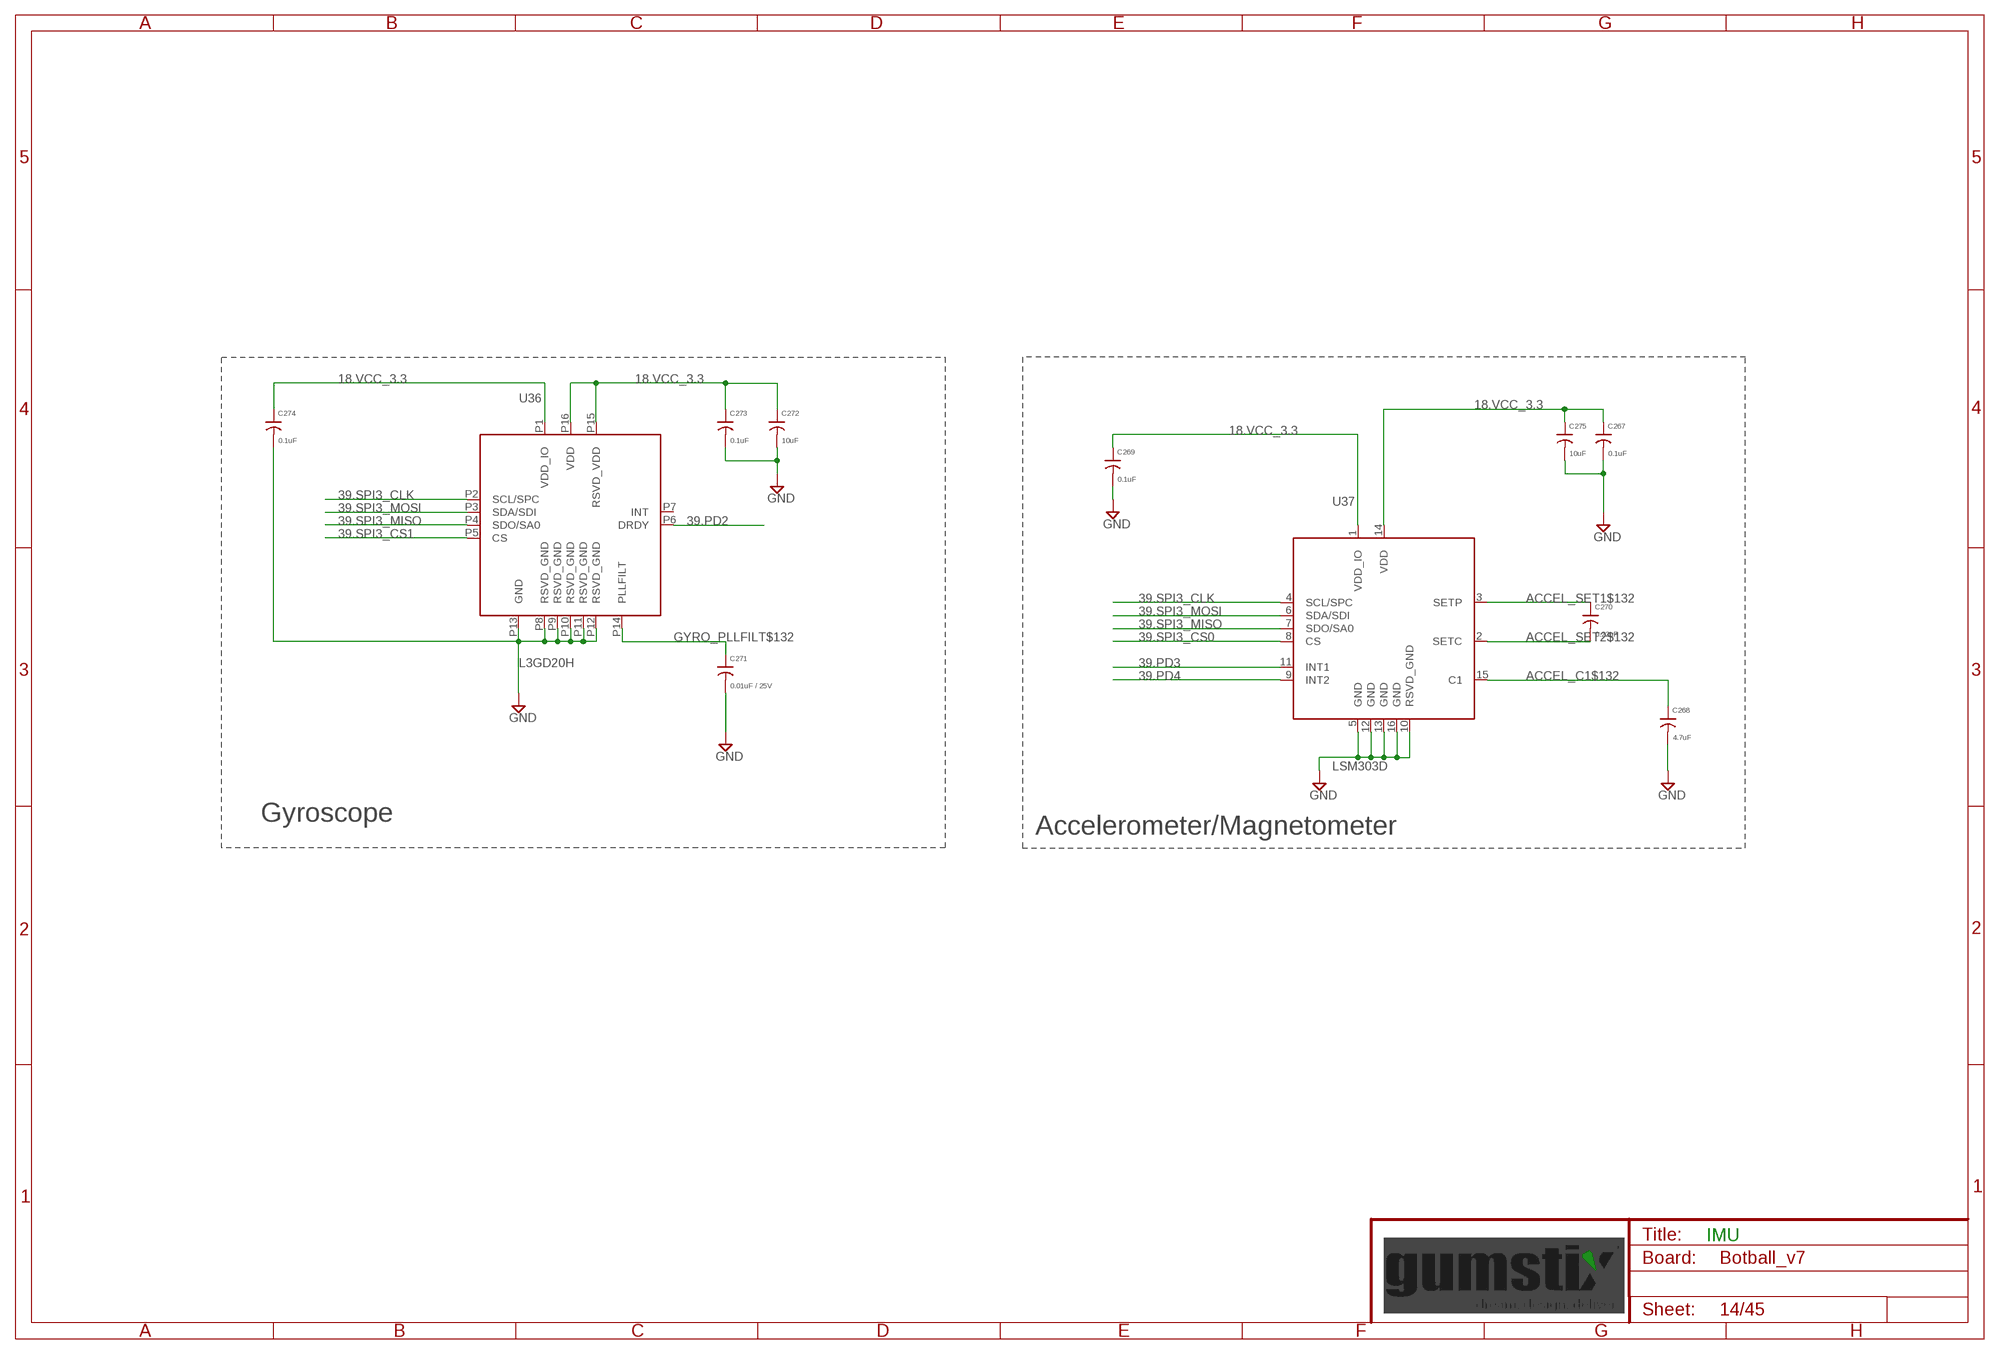
[diagram p13: schematic, sheet 14]
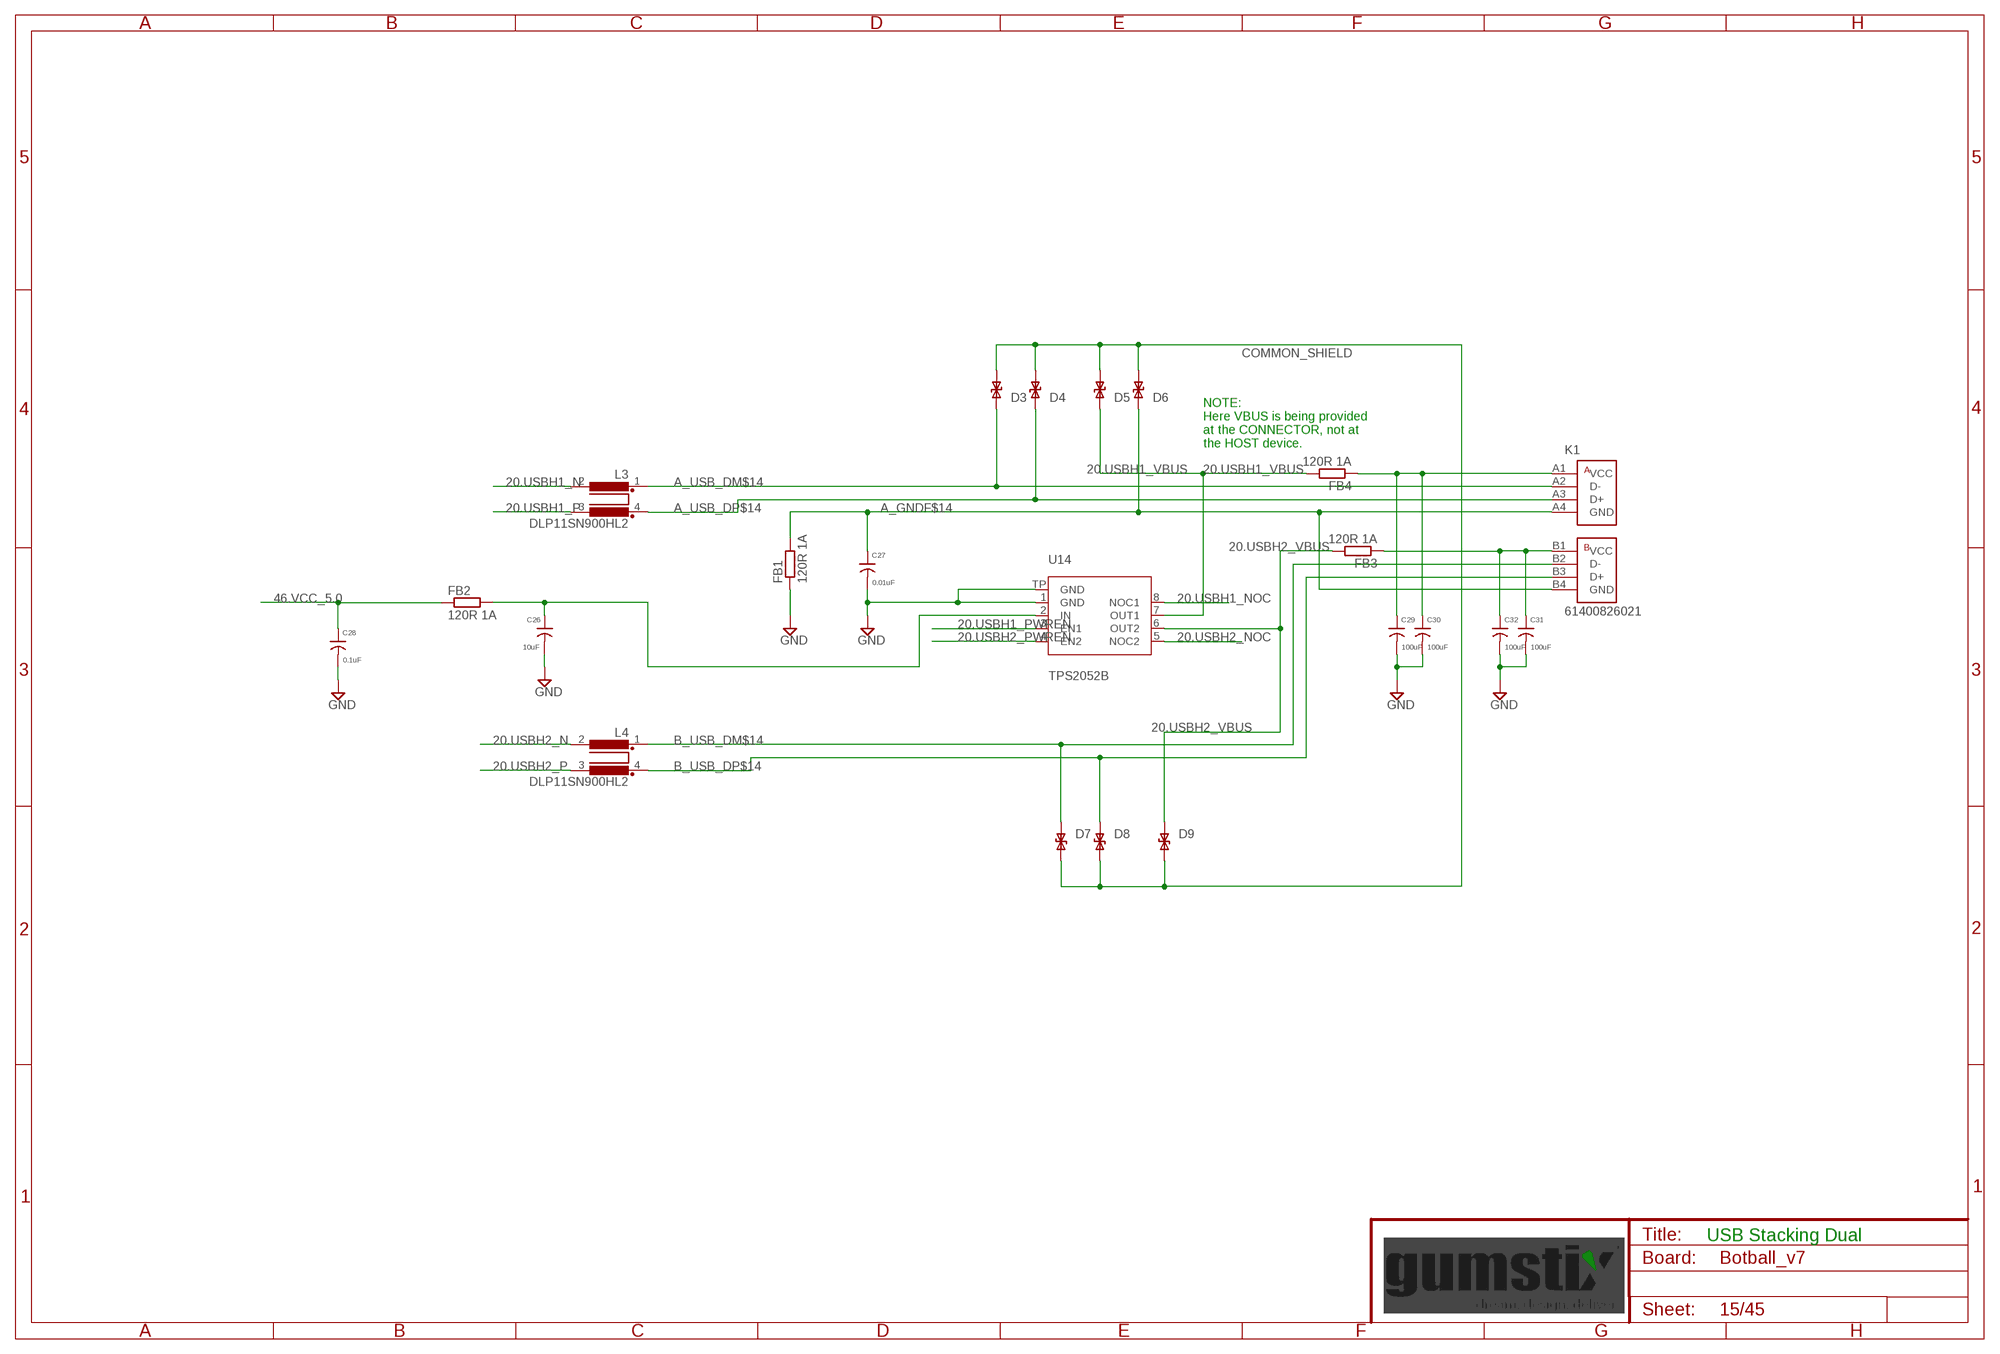
[diagram p14: schematic, sheet 15]
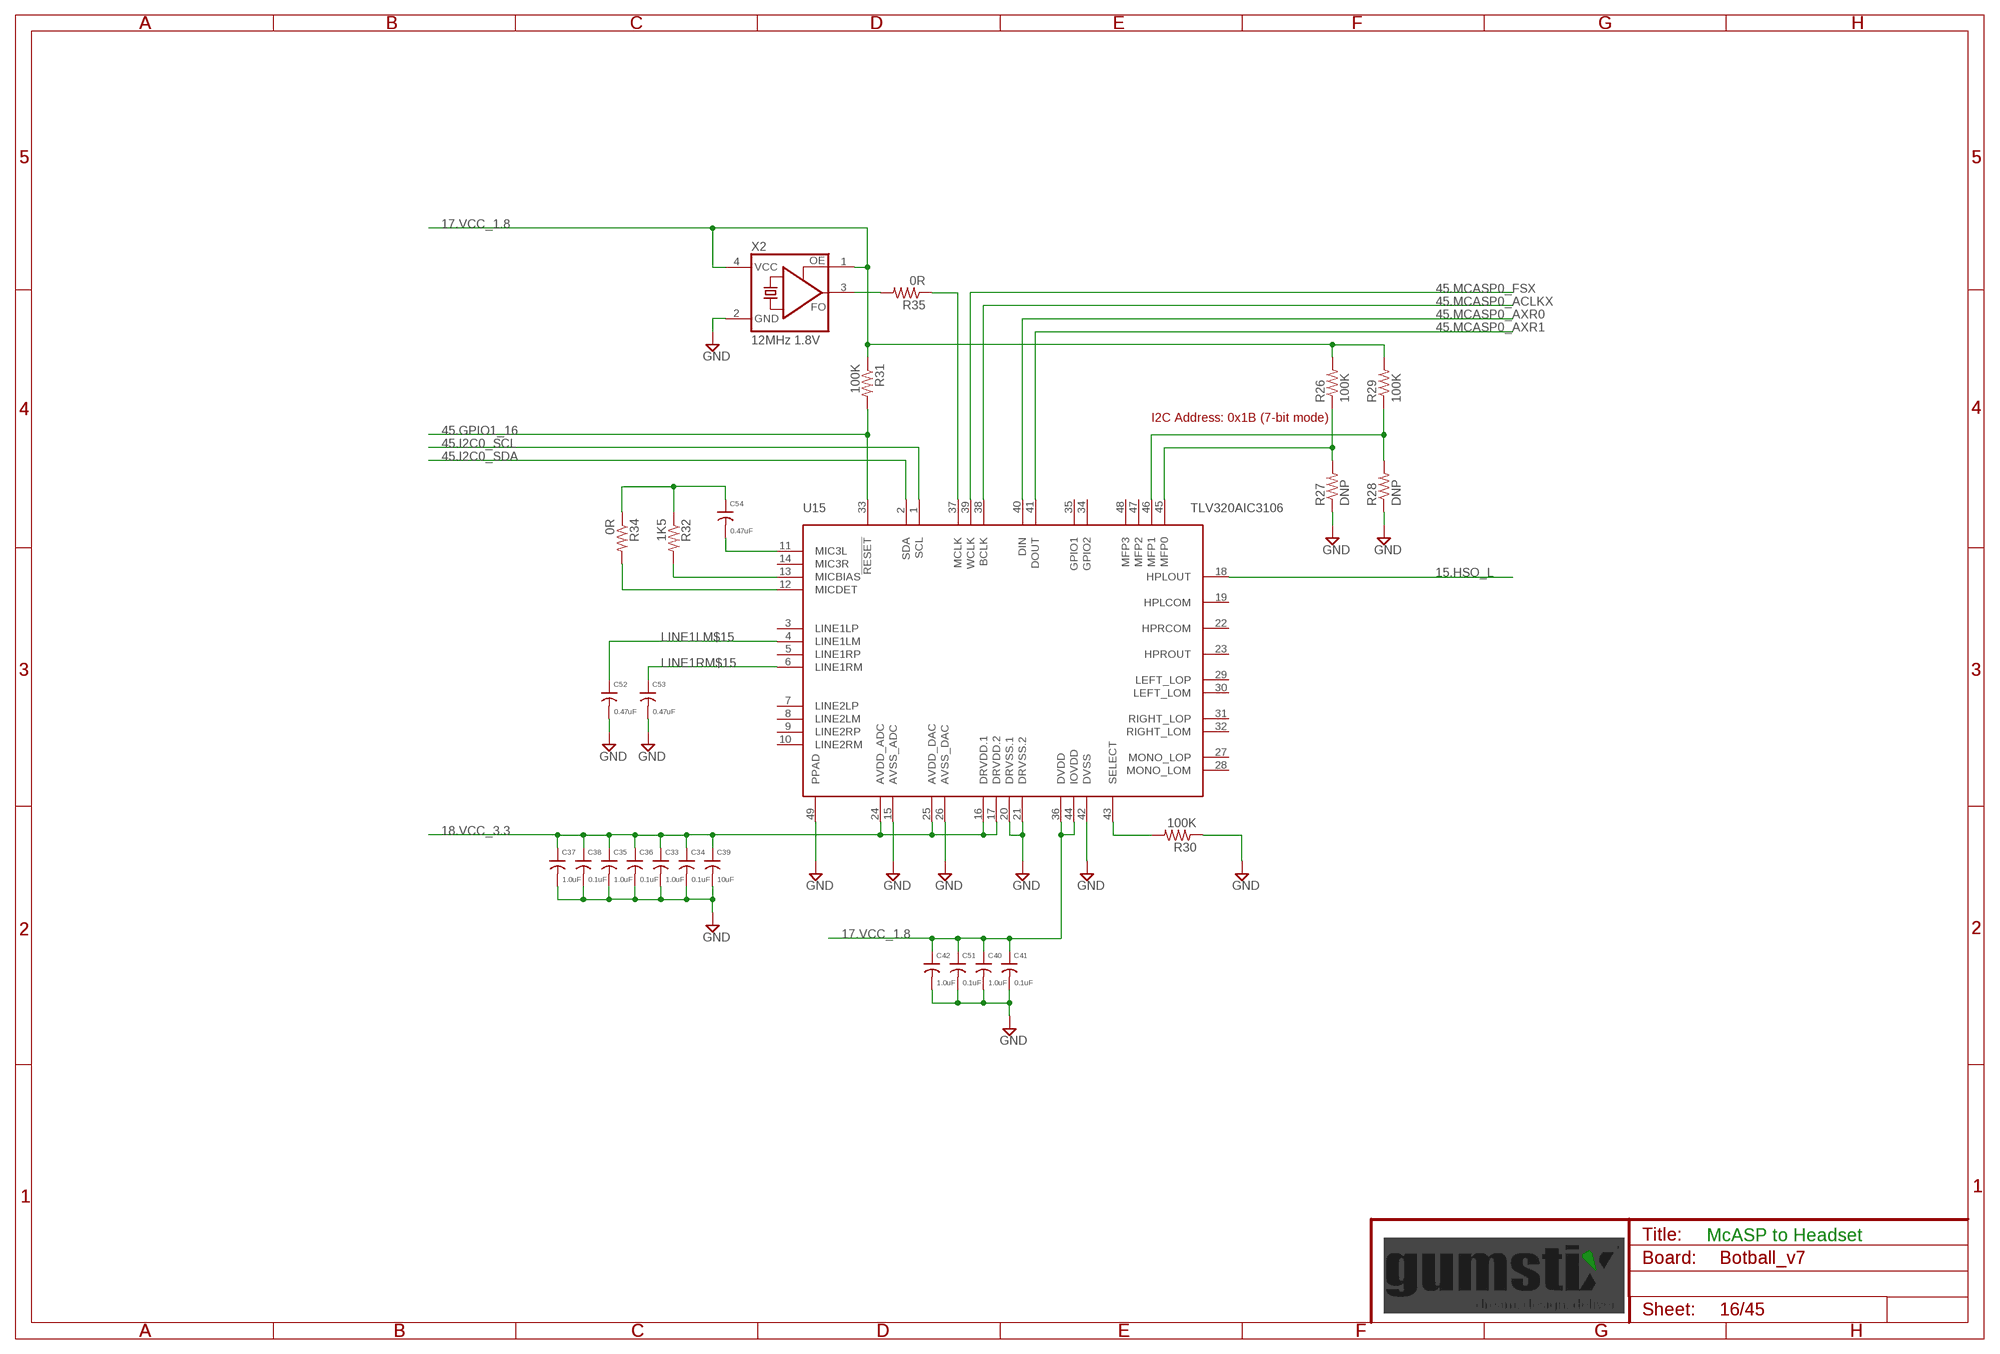
[diagram p15: schematic, sheet 16]
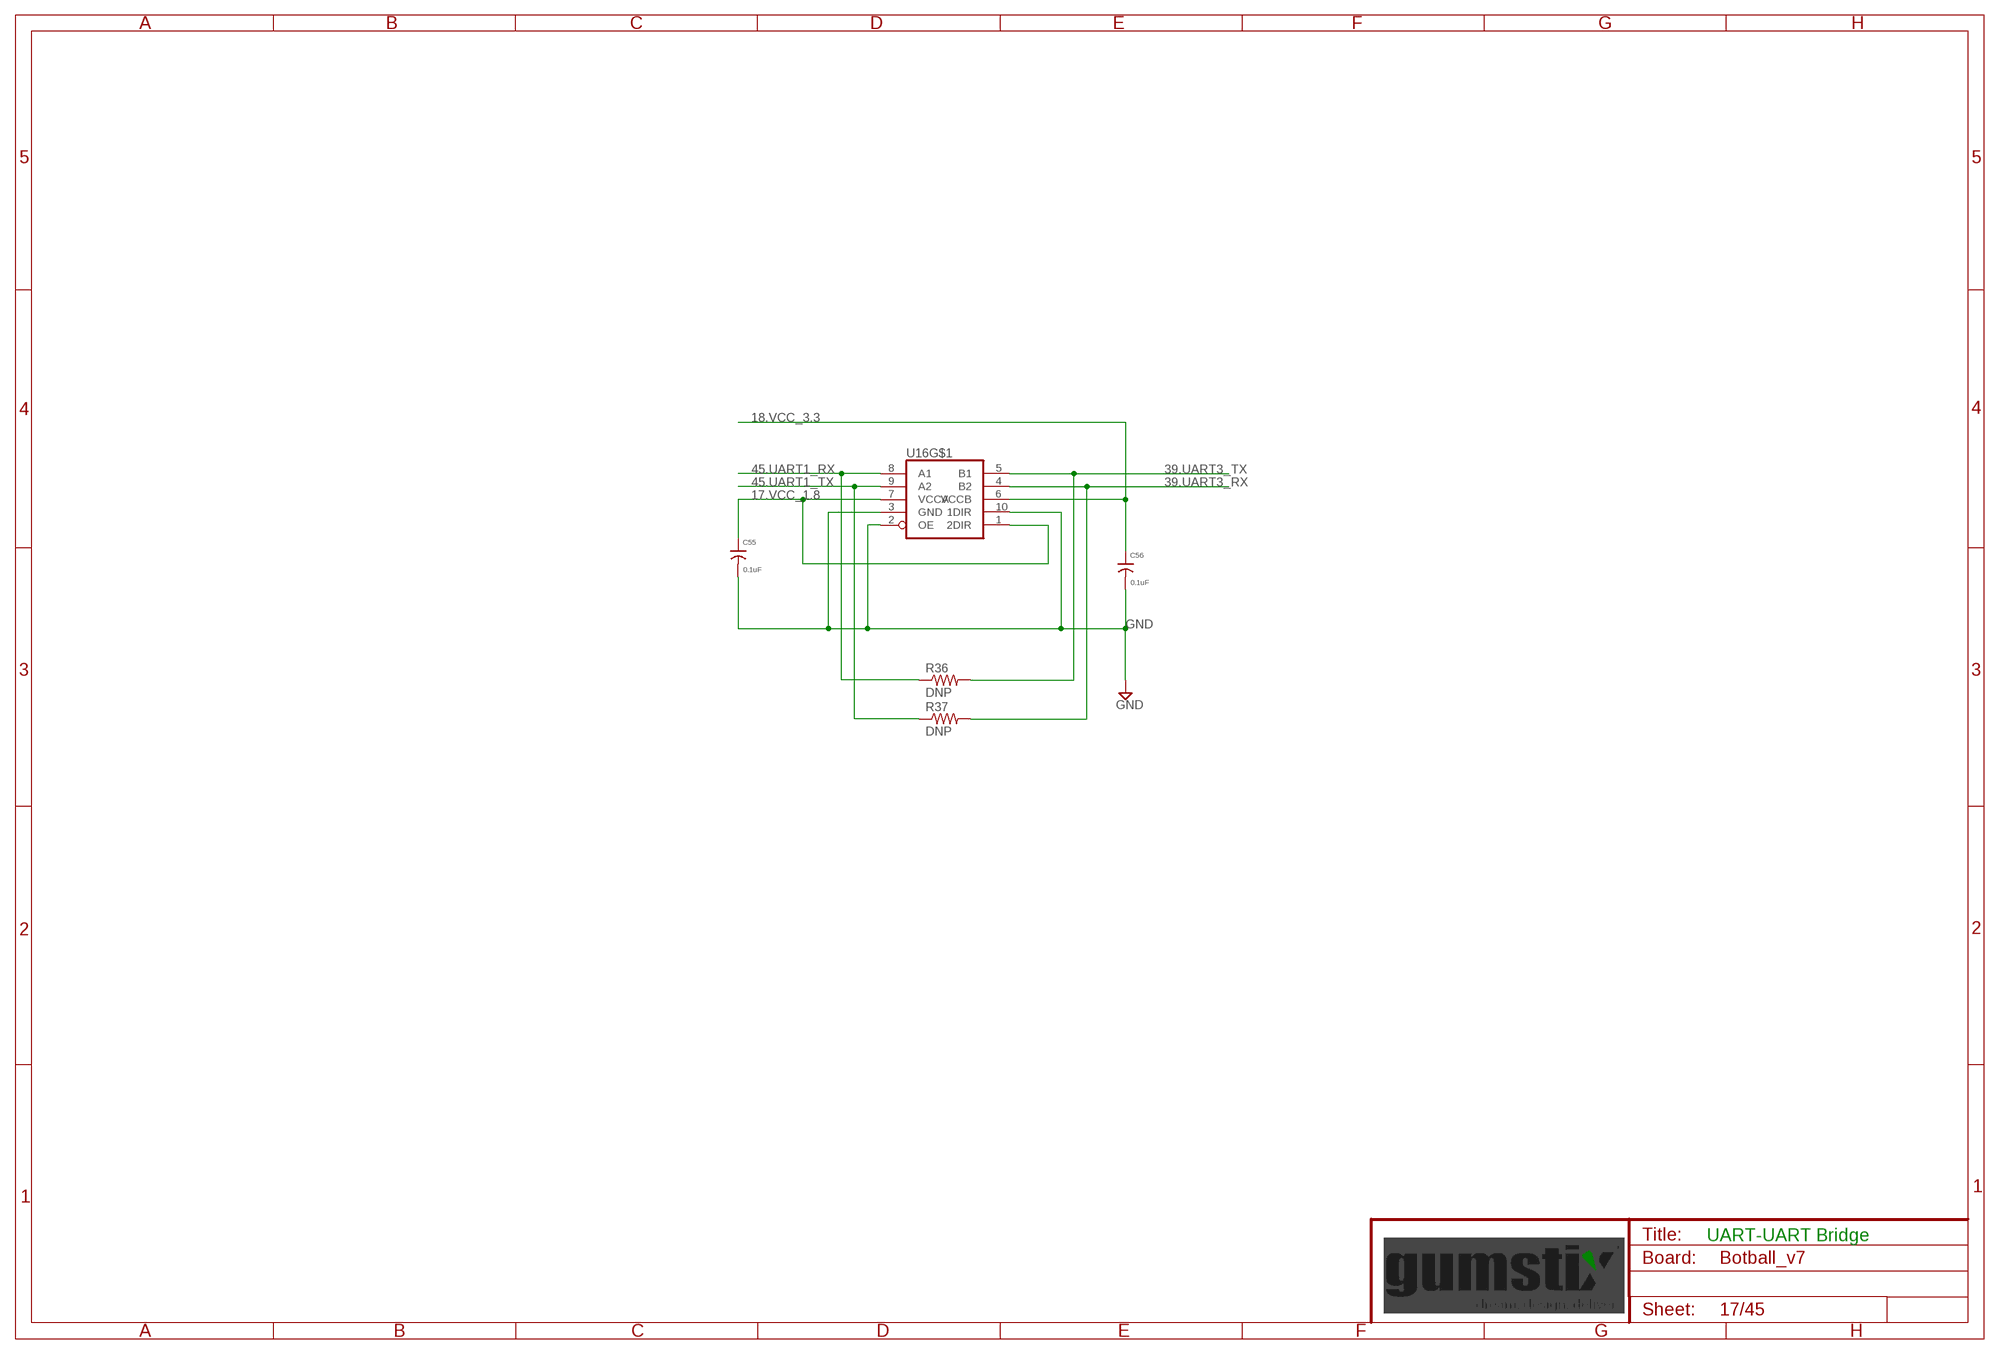
[diagram p16: schematic, sheet 17]
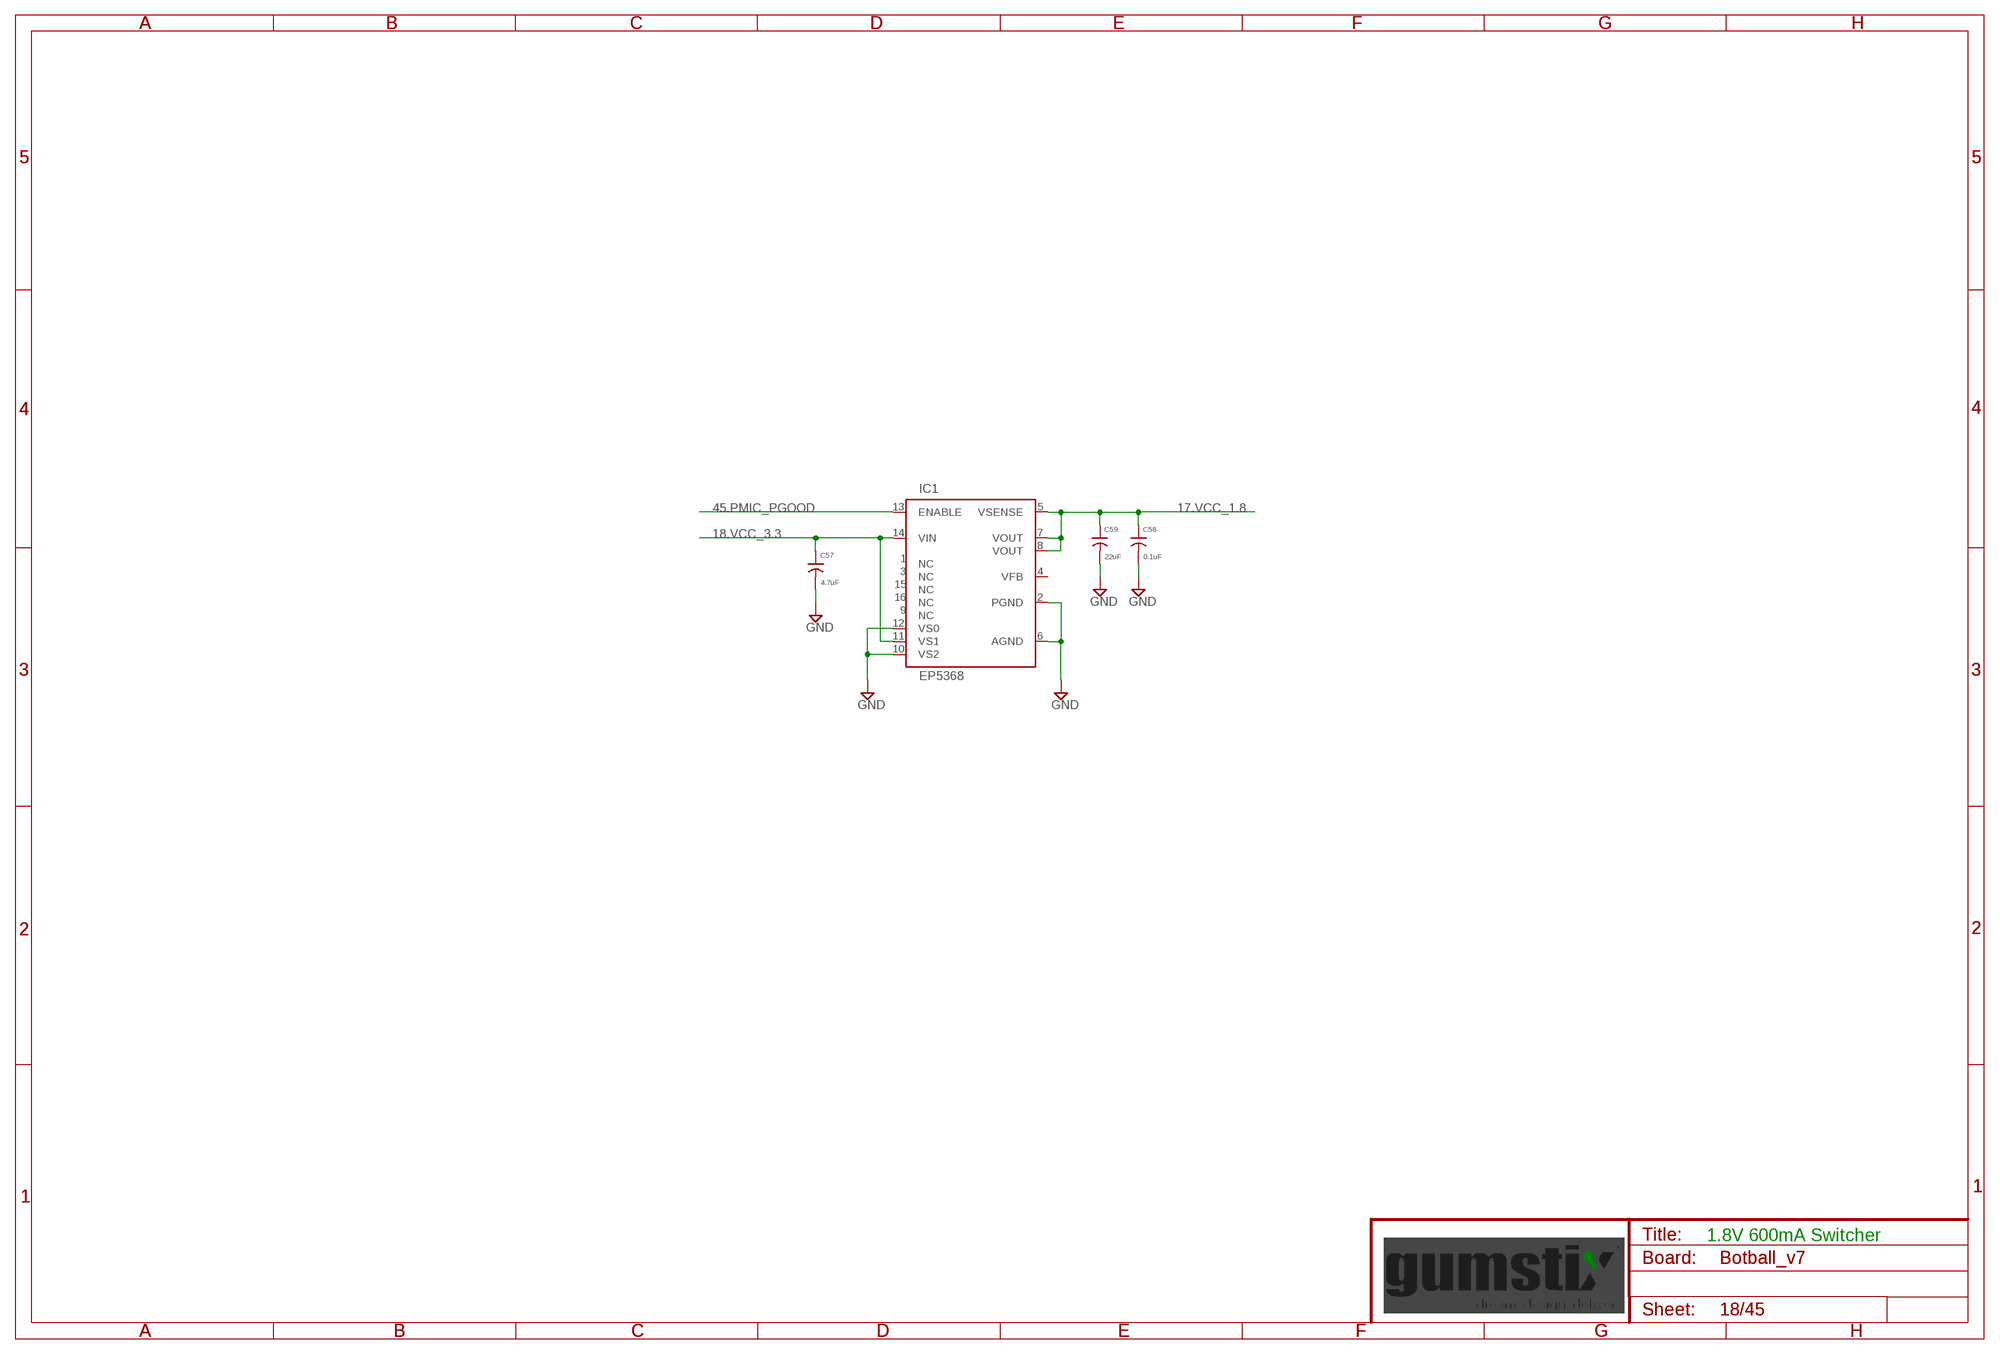
[diagram p17: schematic, sheet 18]
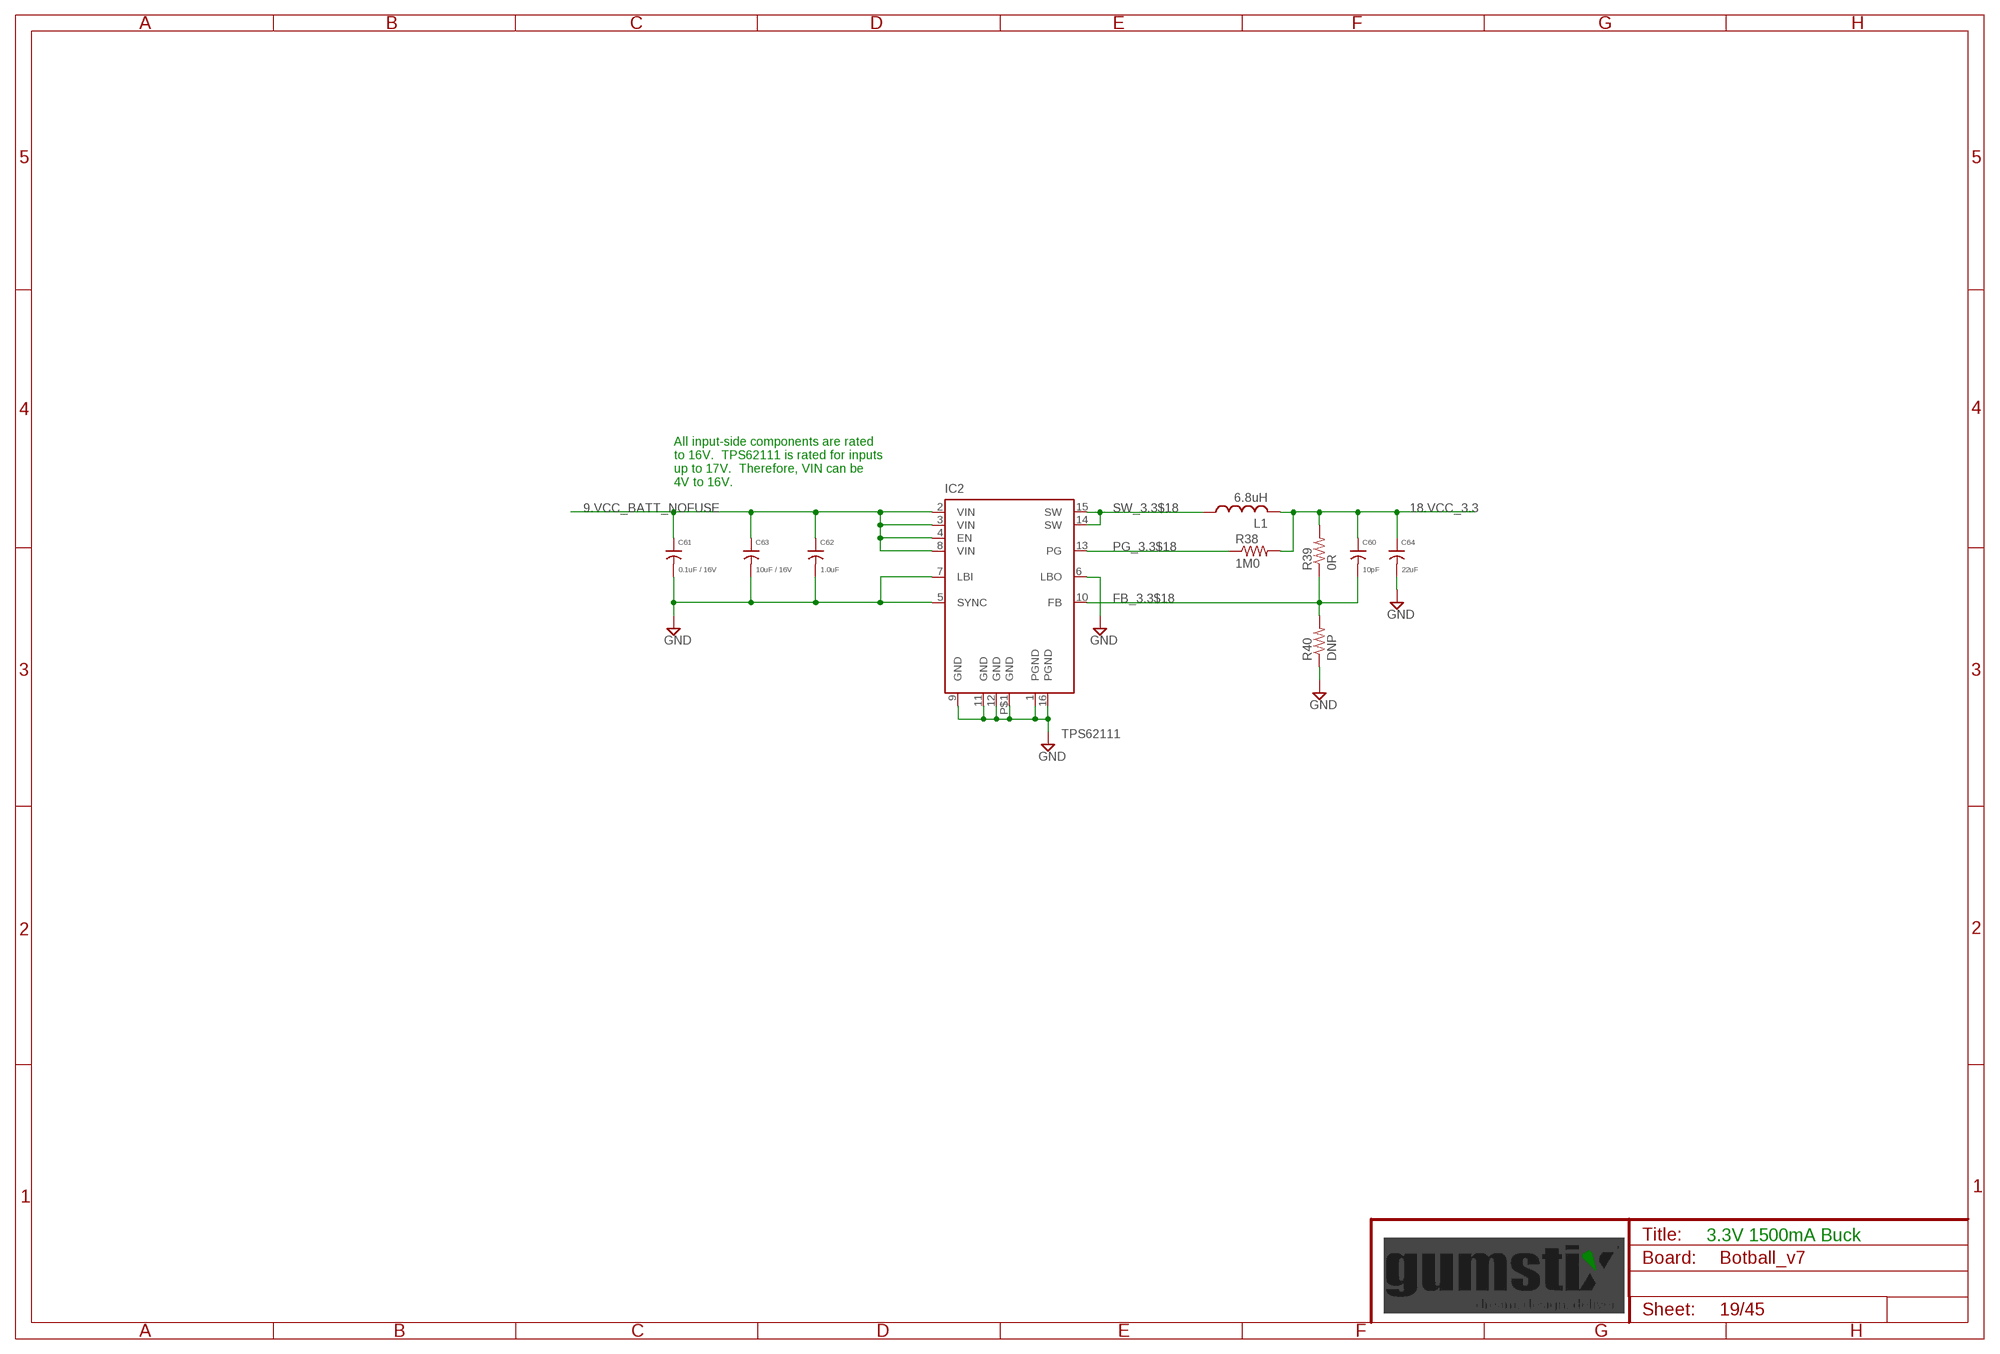
[diagram p18: schematic, sheet 19]
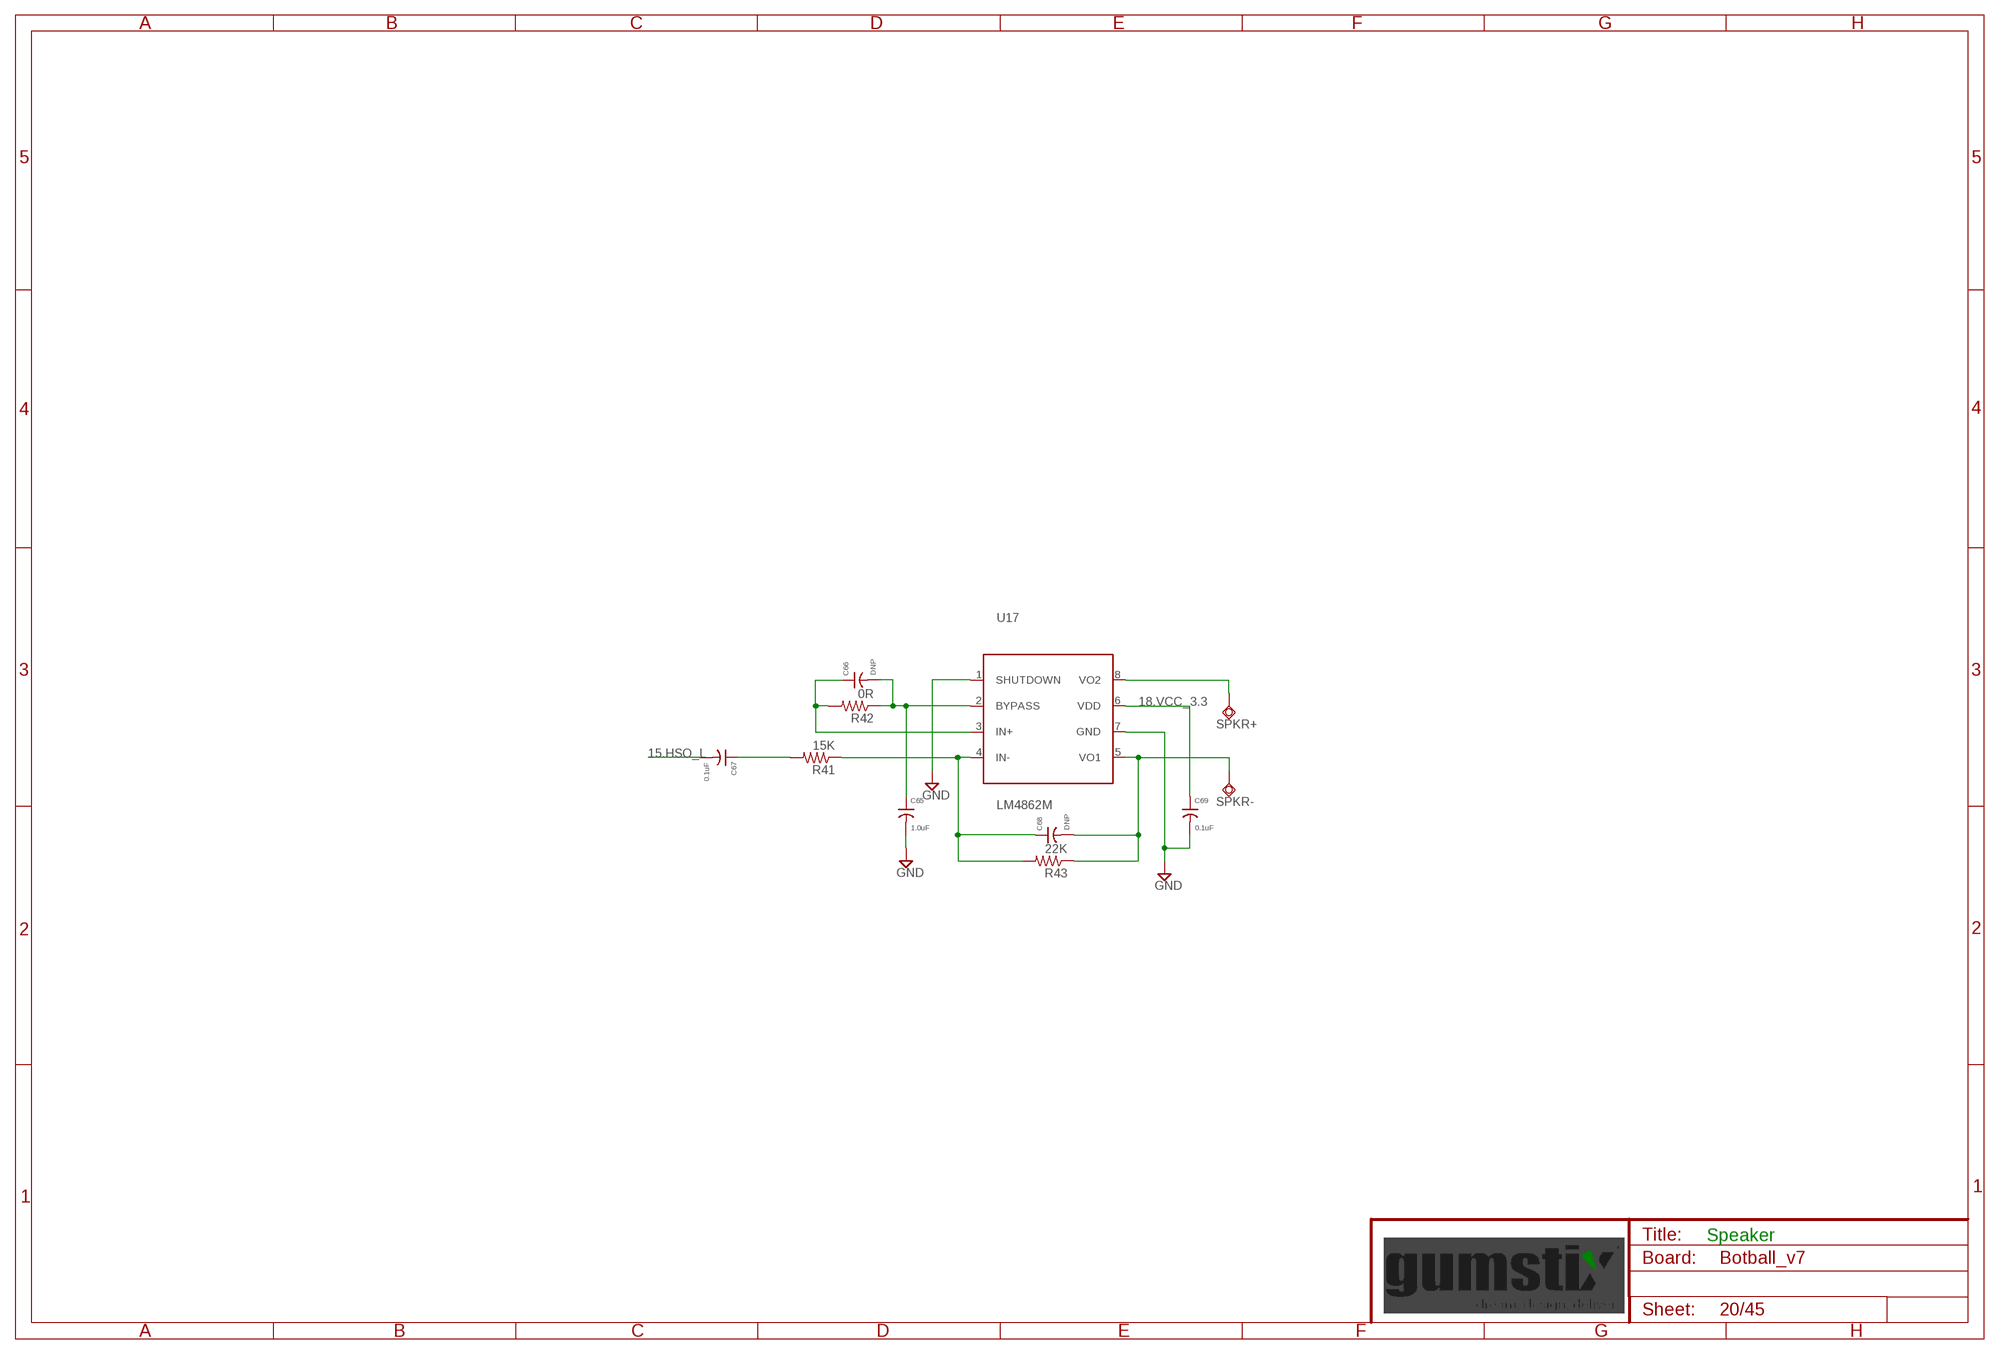
[diagram p19: schematic, sheet 20]
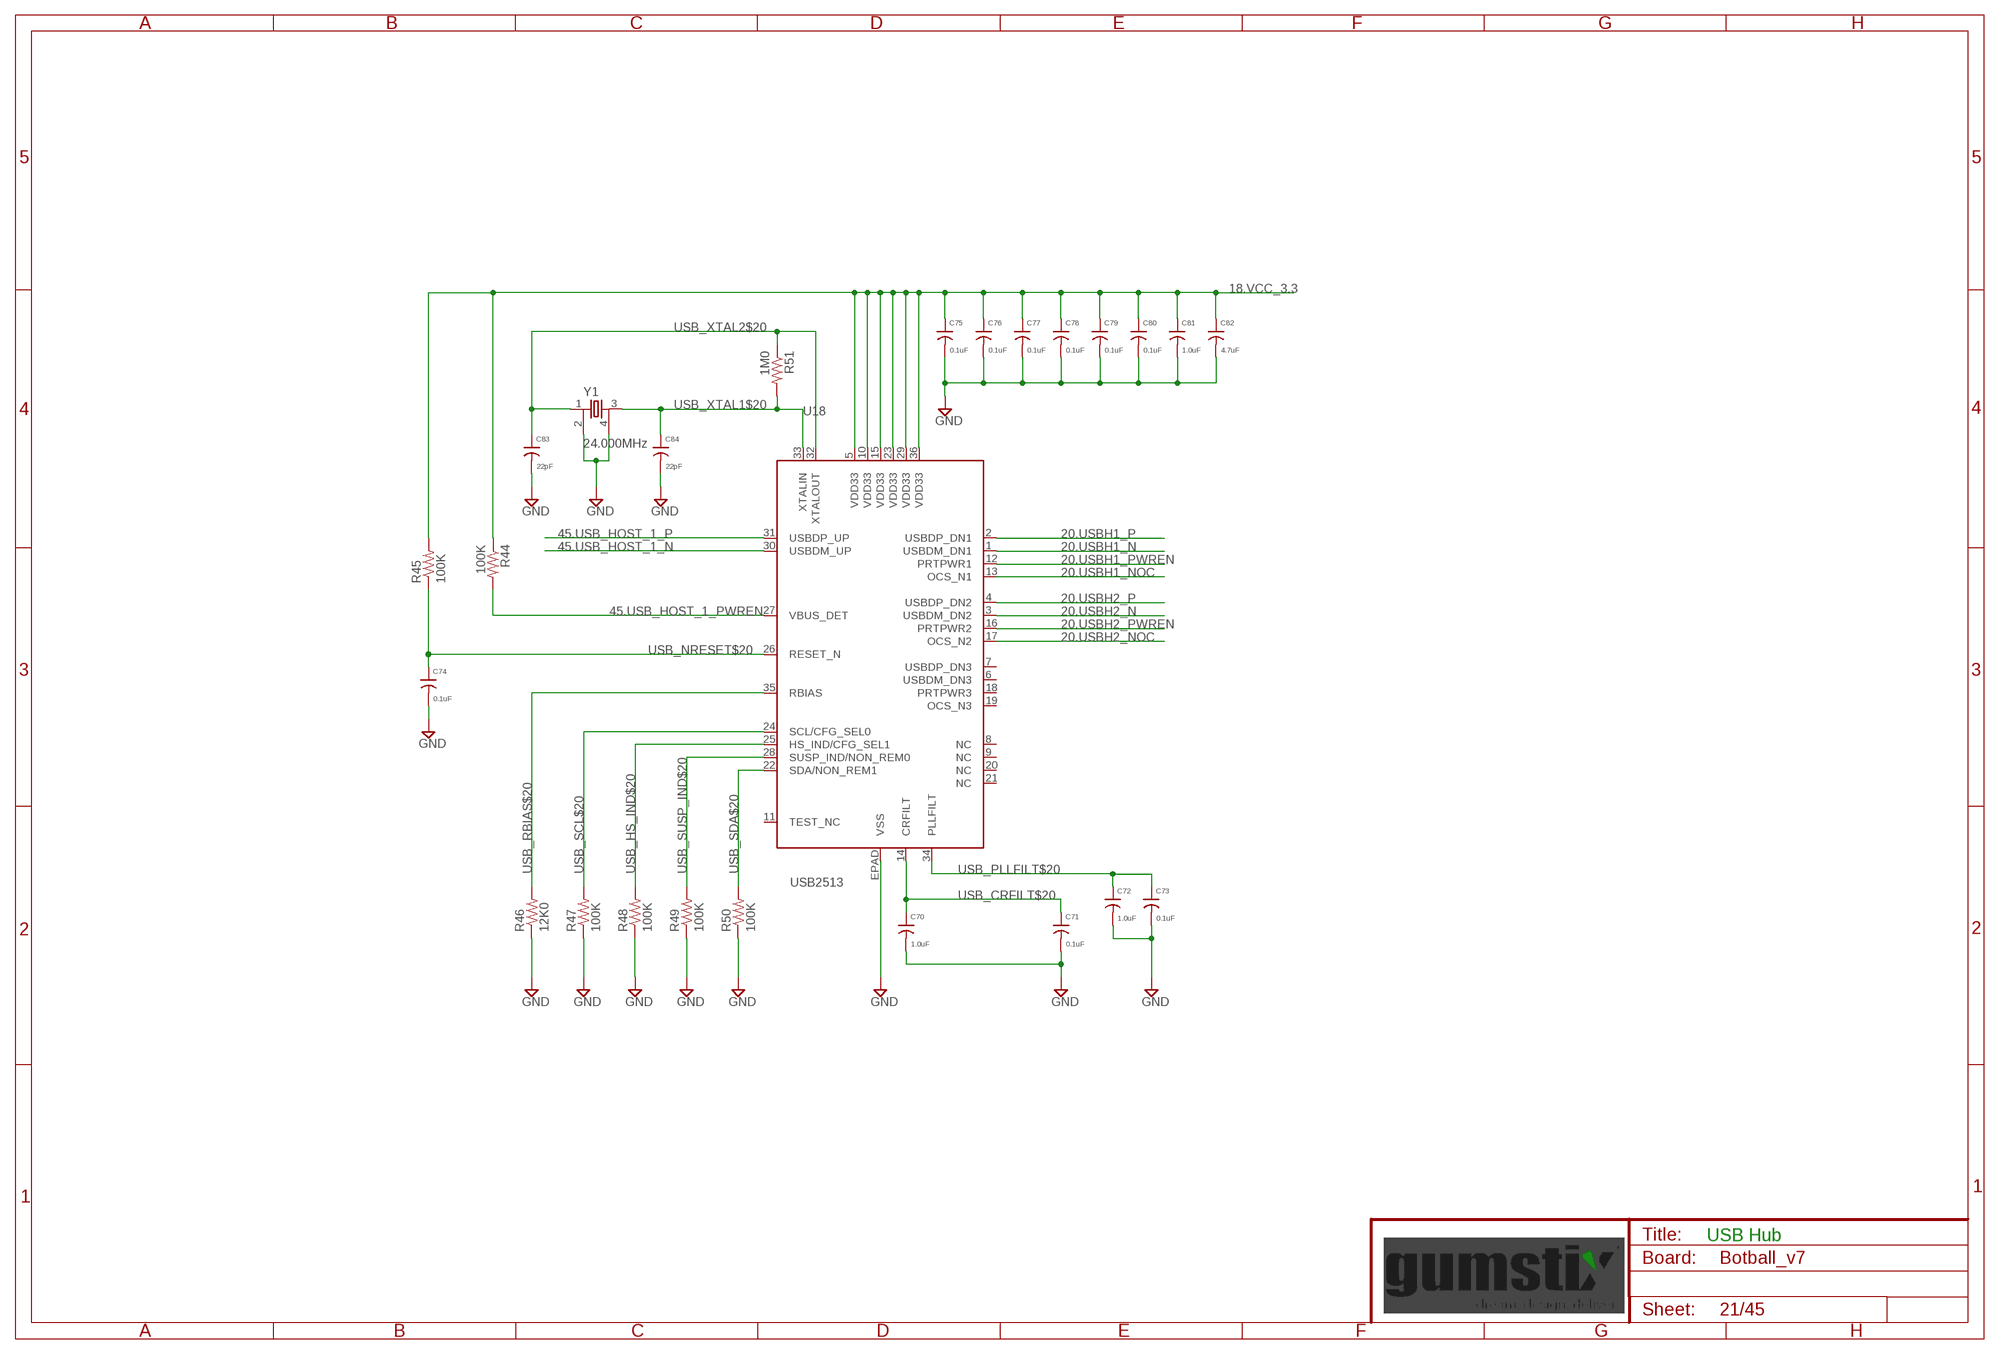
[diagram p20: schematic, sheet 21]
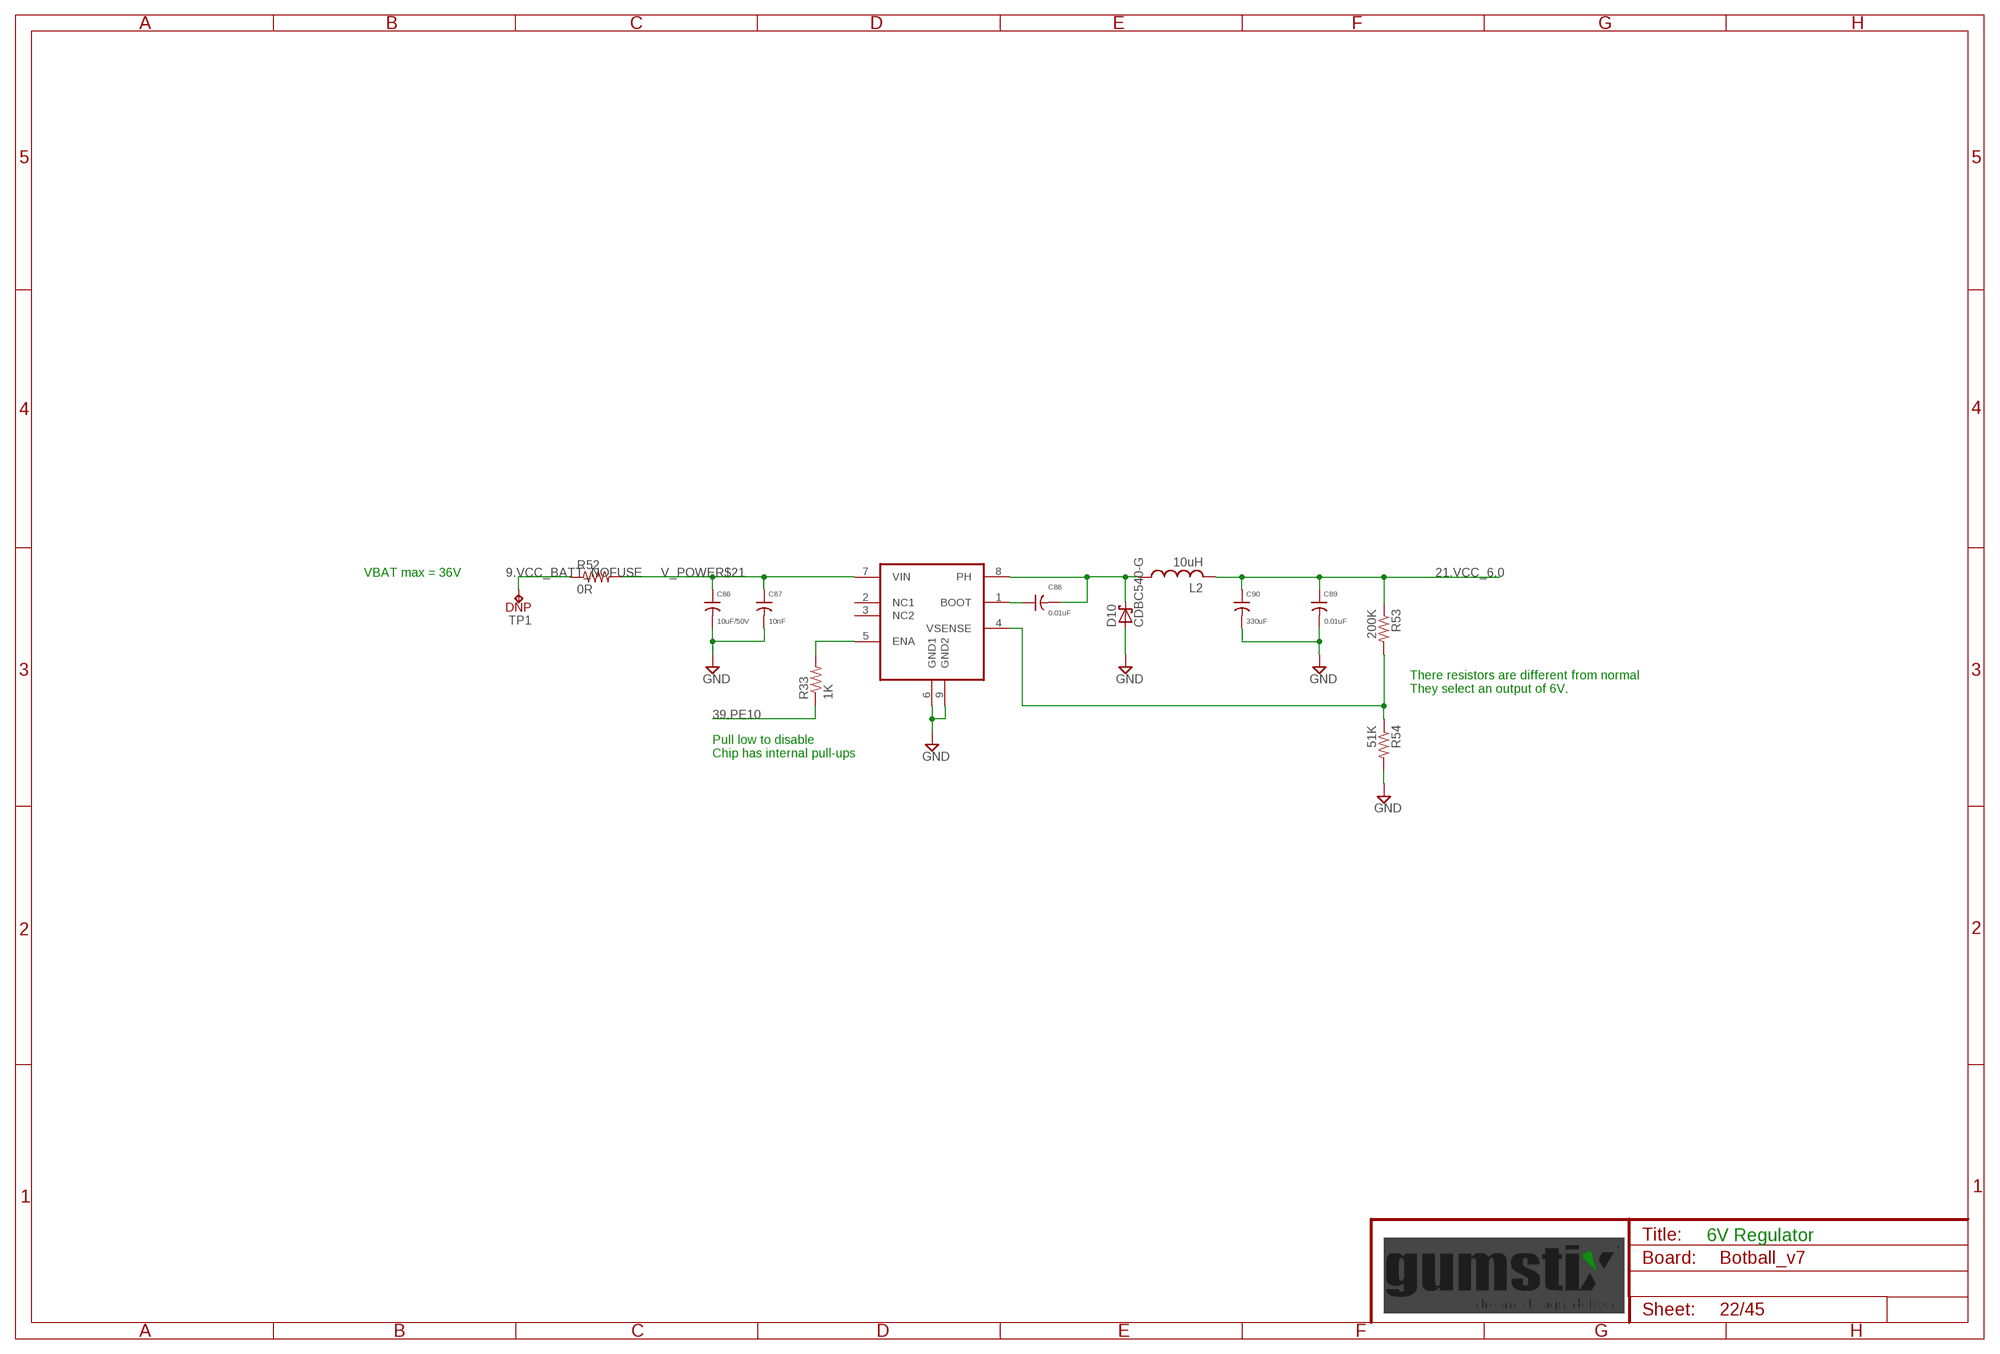
[diagram p21: schematic, sheet 22]
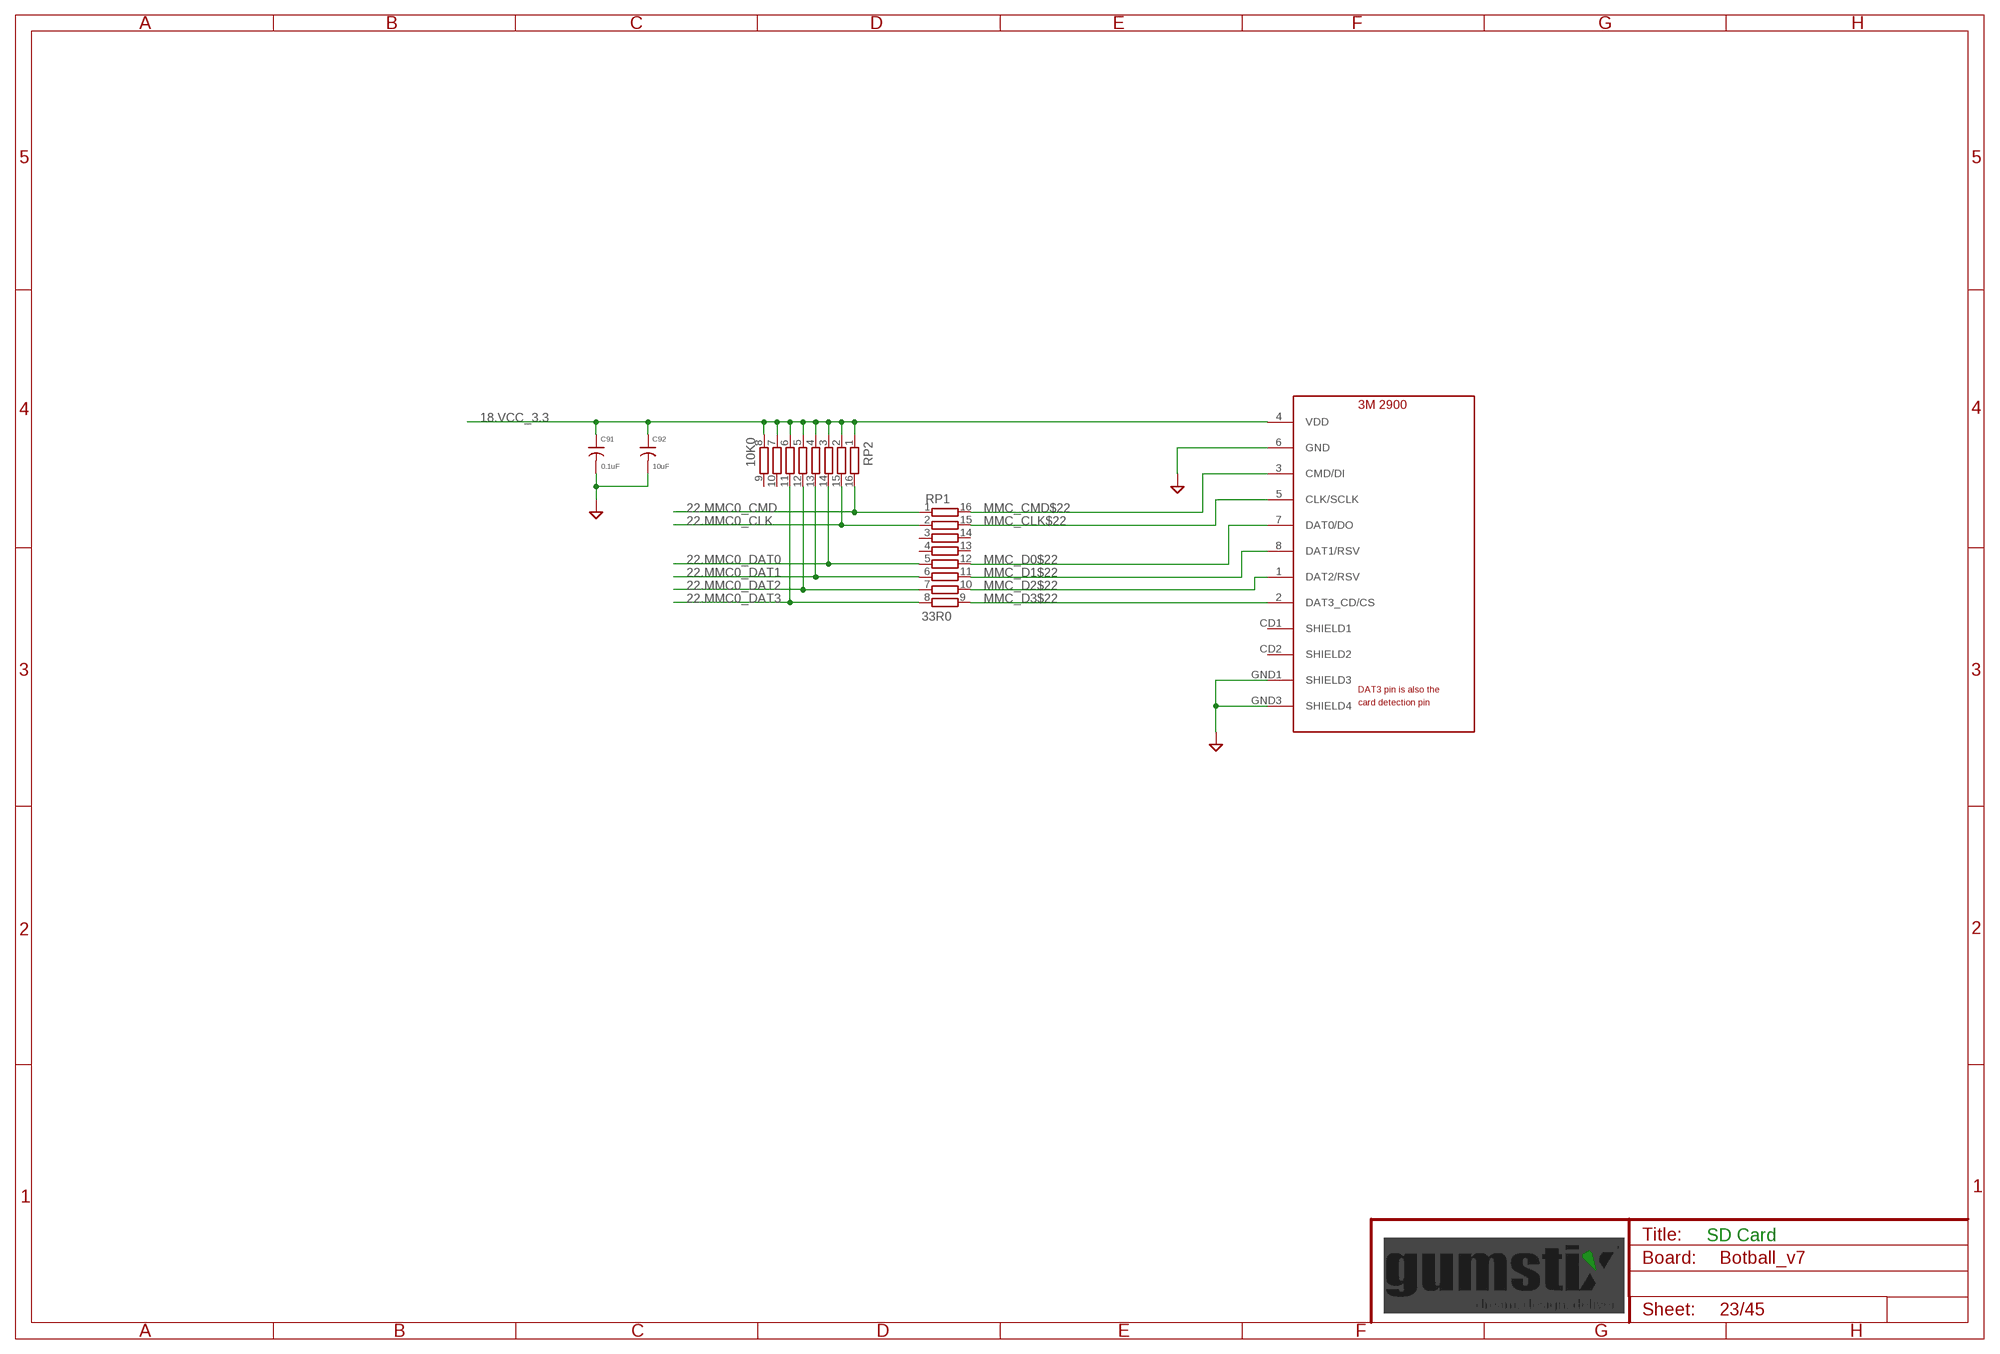
[diagram p22: schematic, sheet 23]
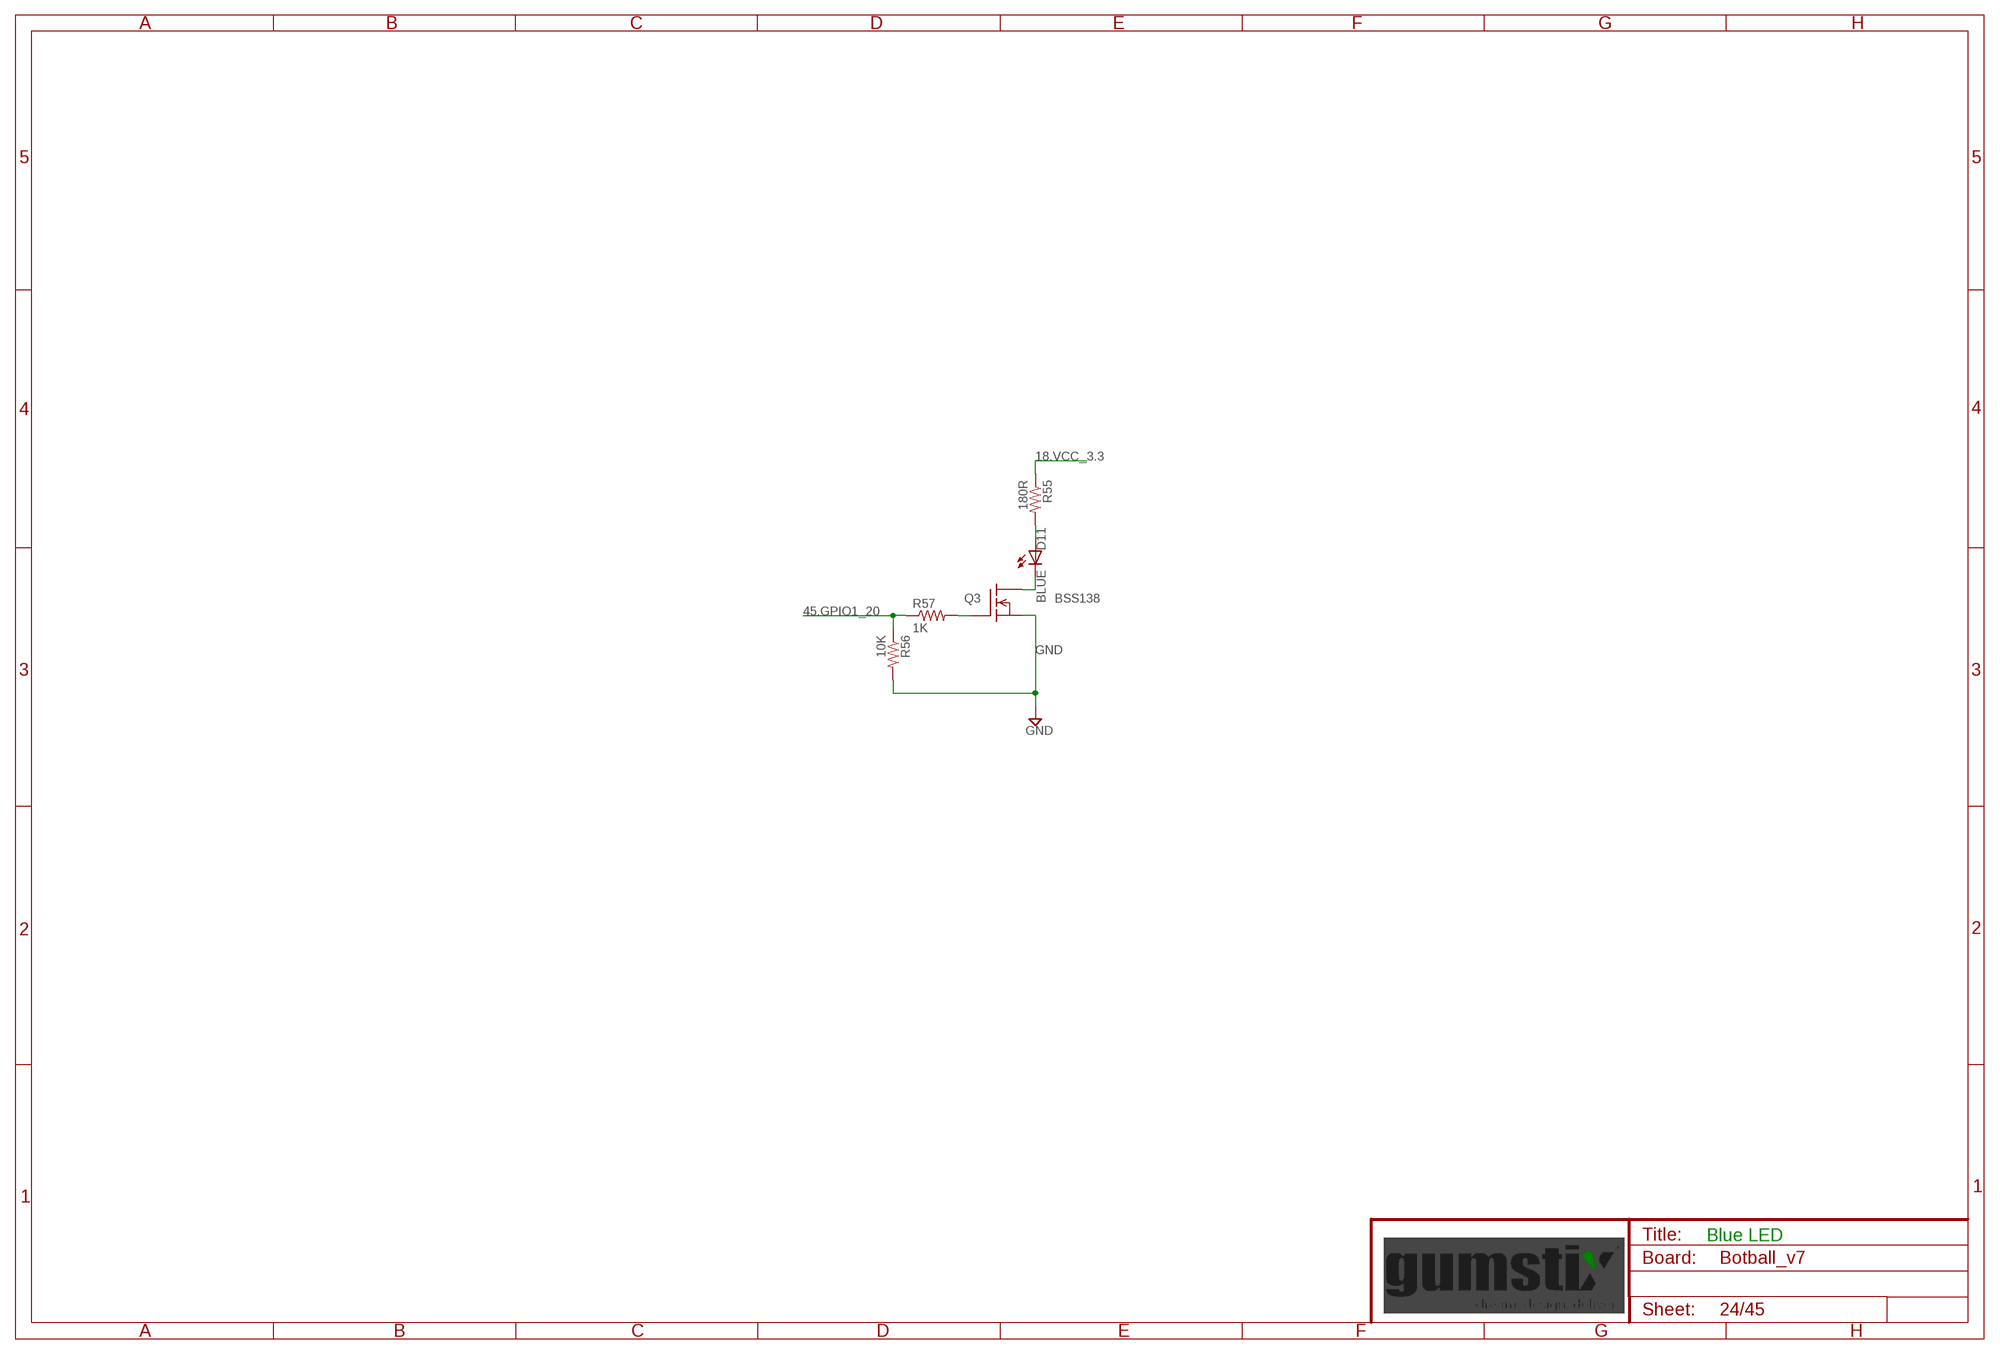
[diagram p23: schematic, sheet 24]
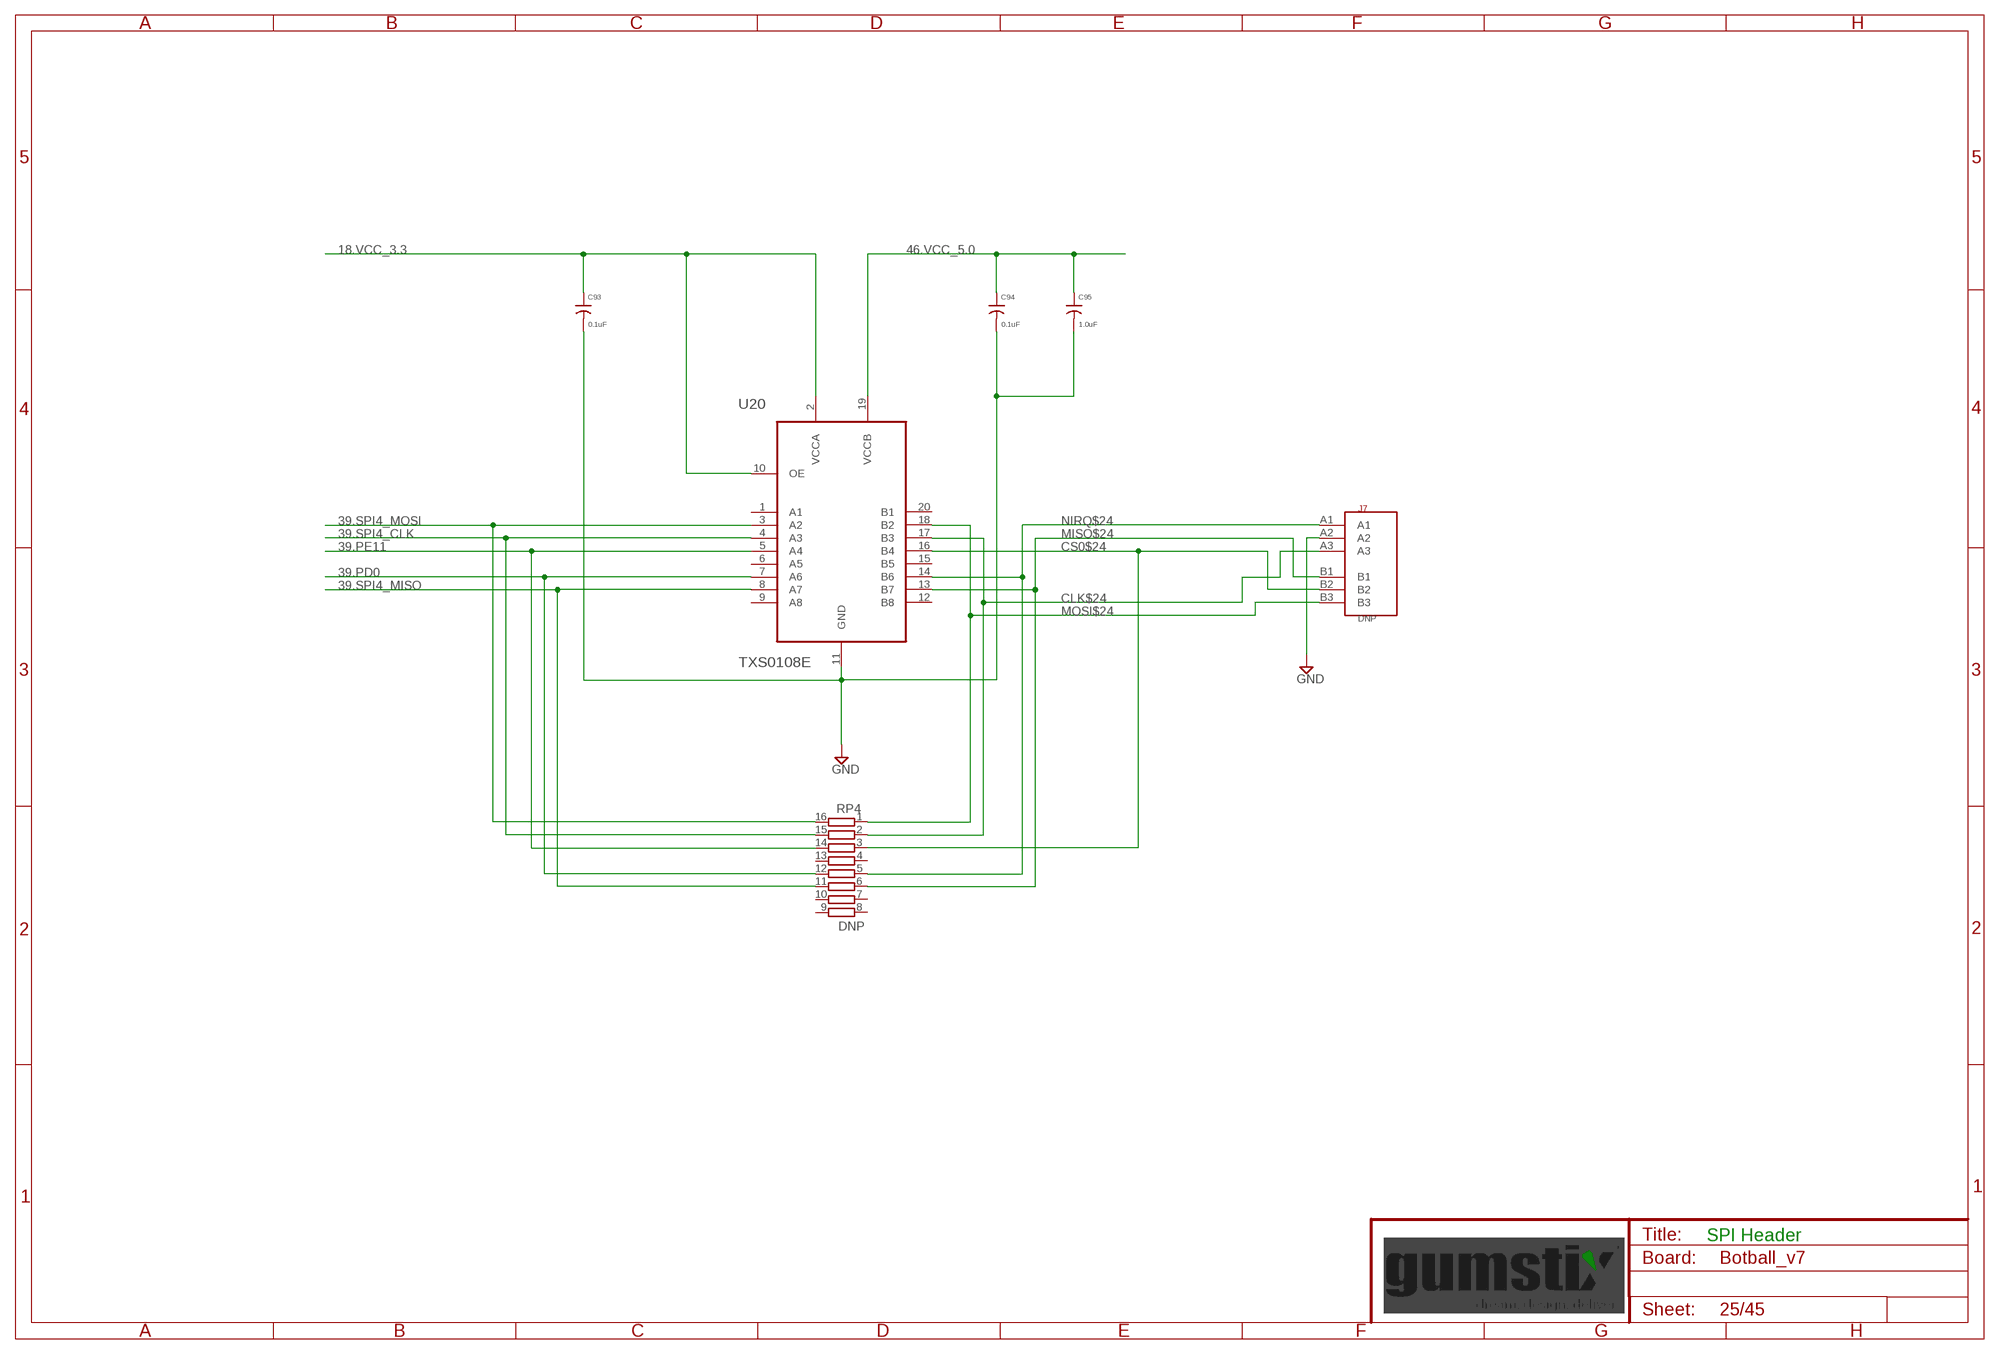
[diagram p24: schematic, sheet 25]
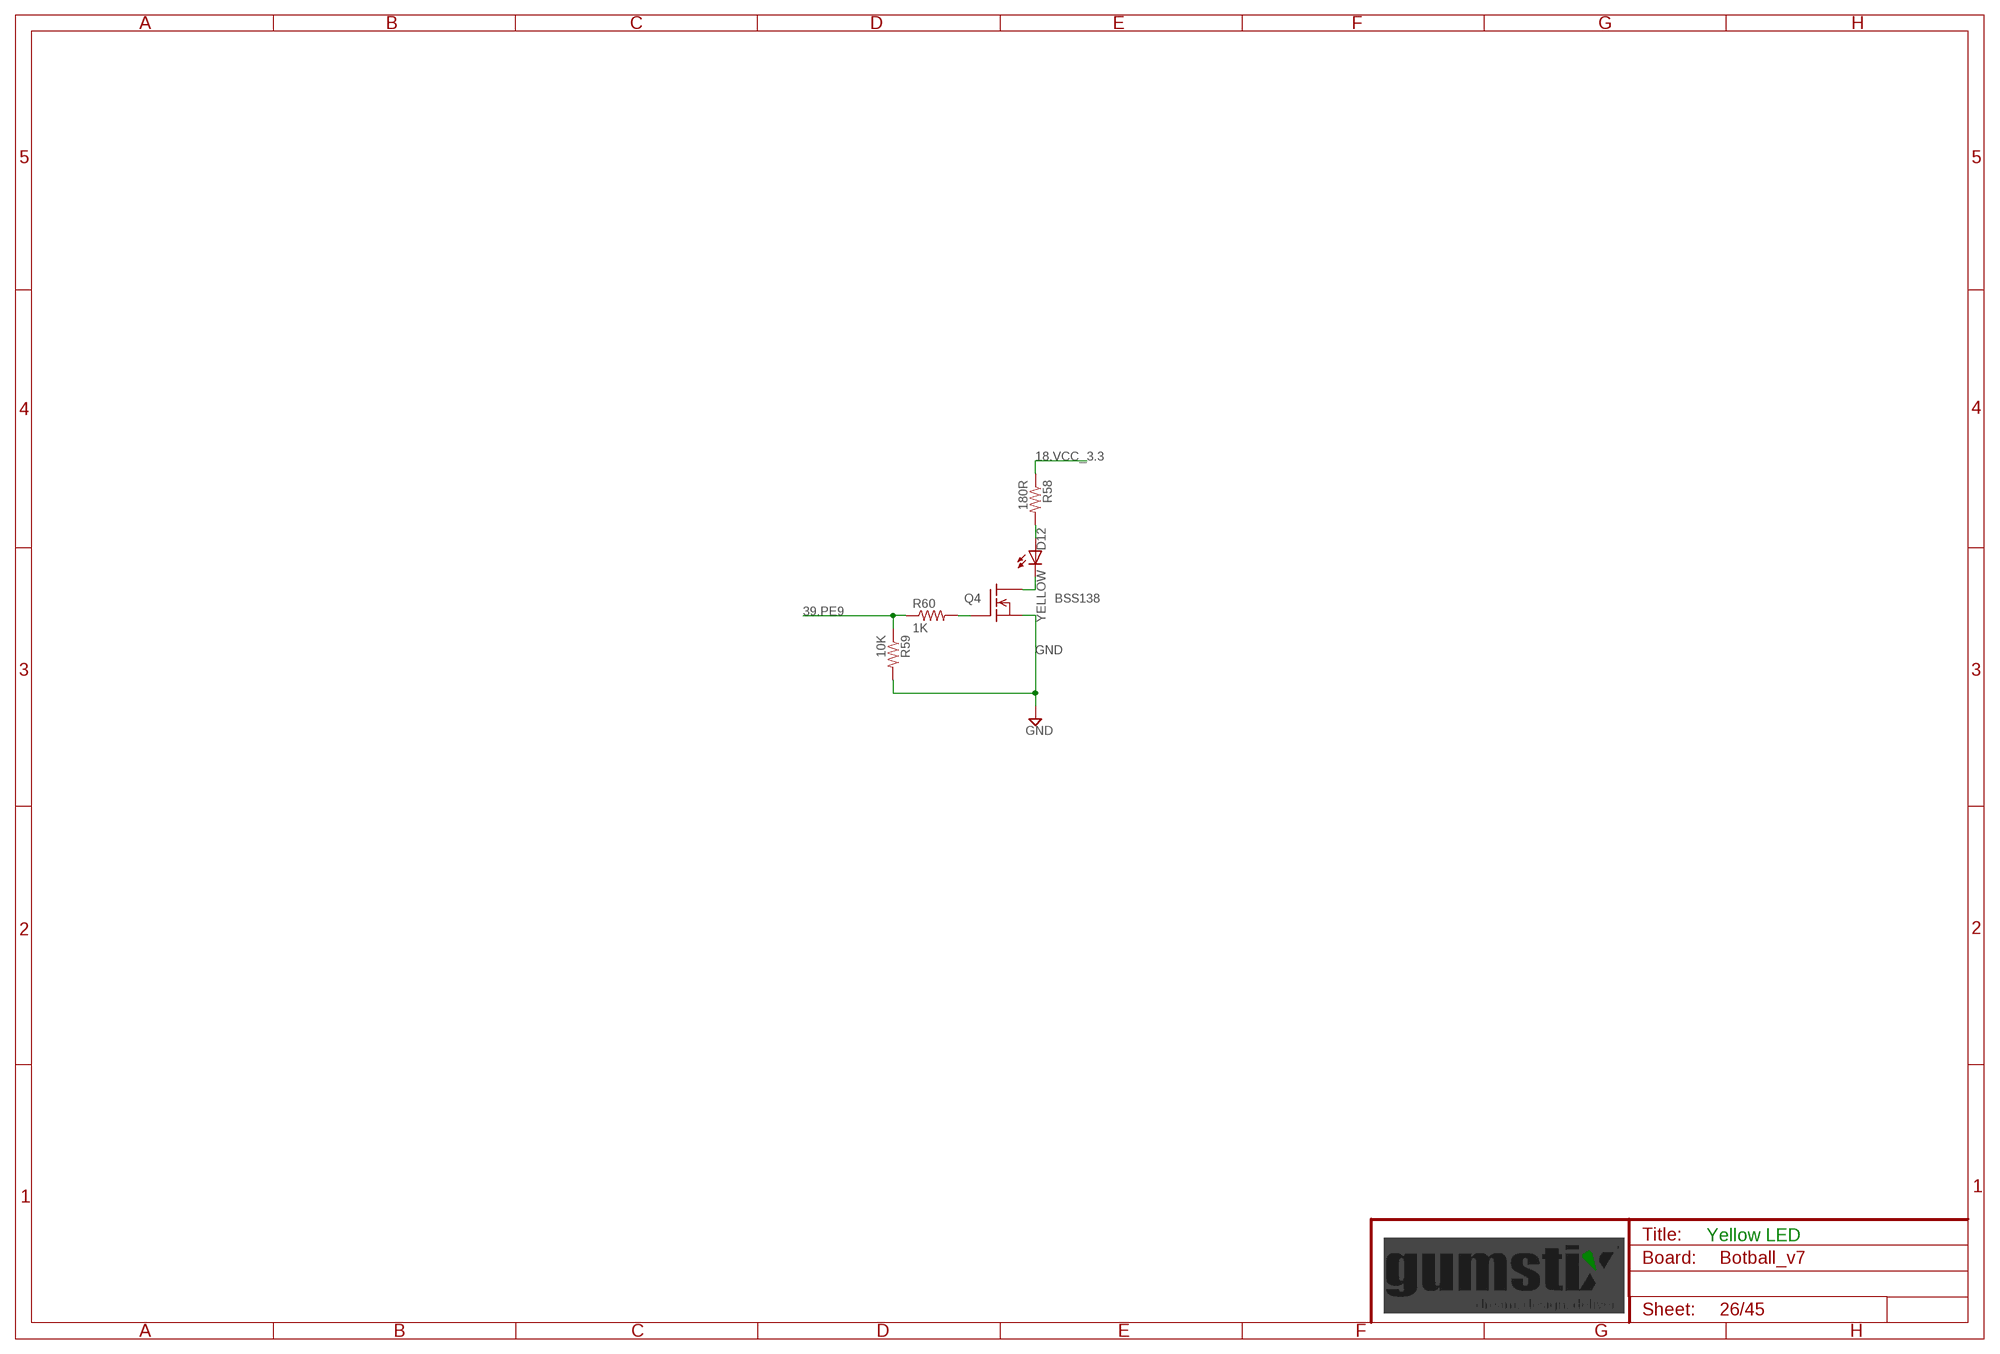
[diagram p25: schematic, sheet 26]
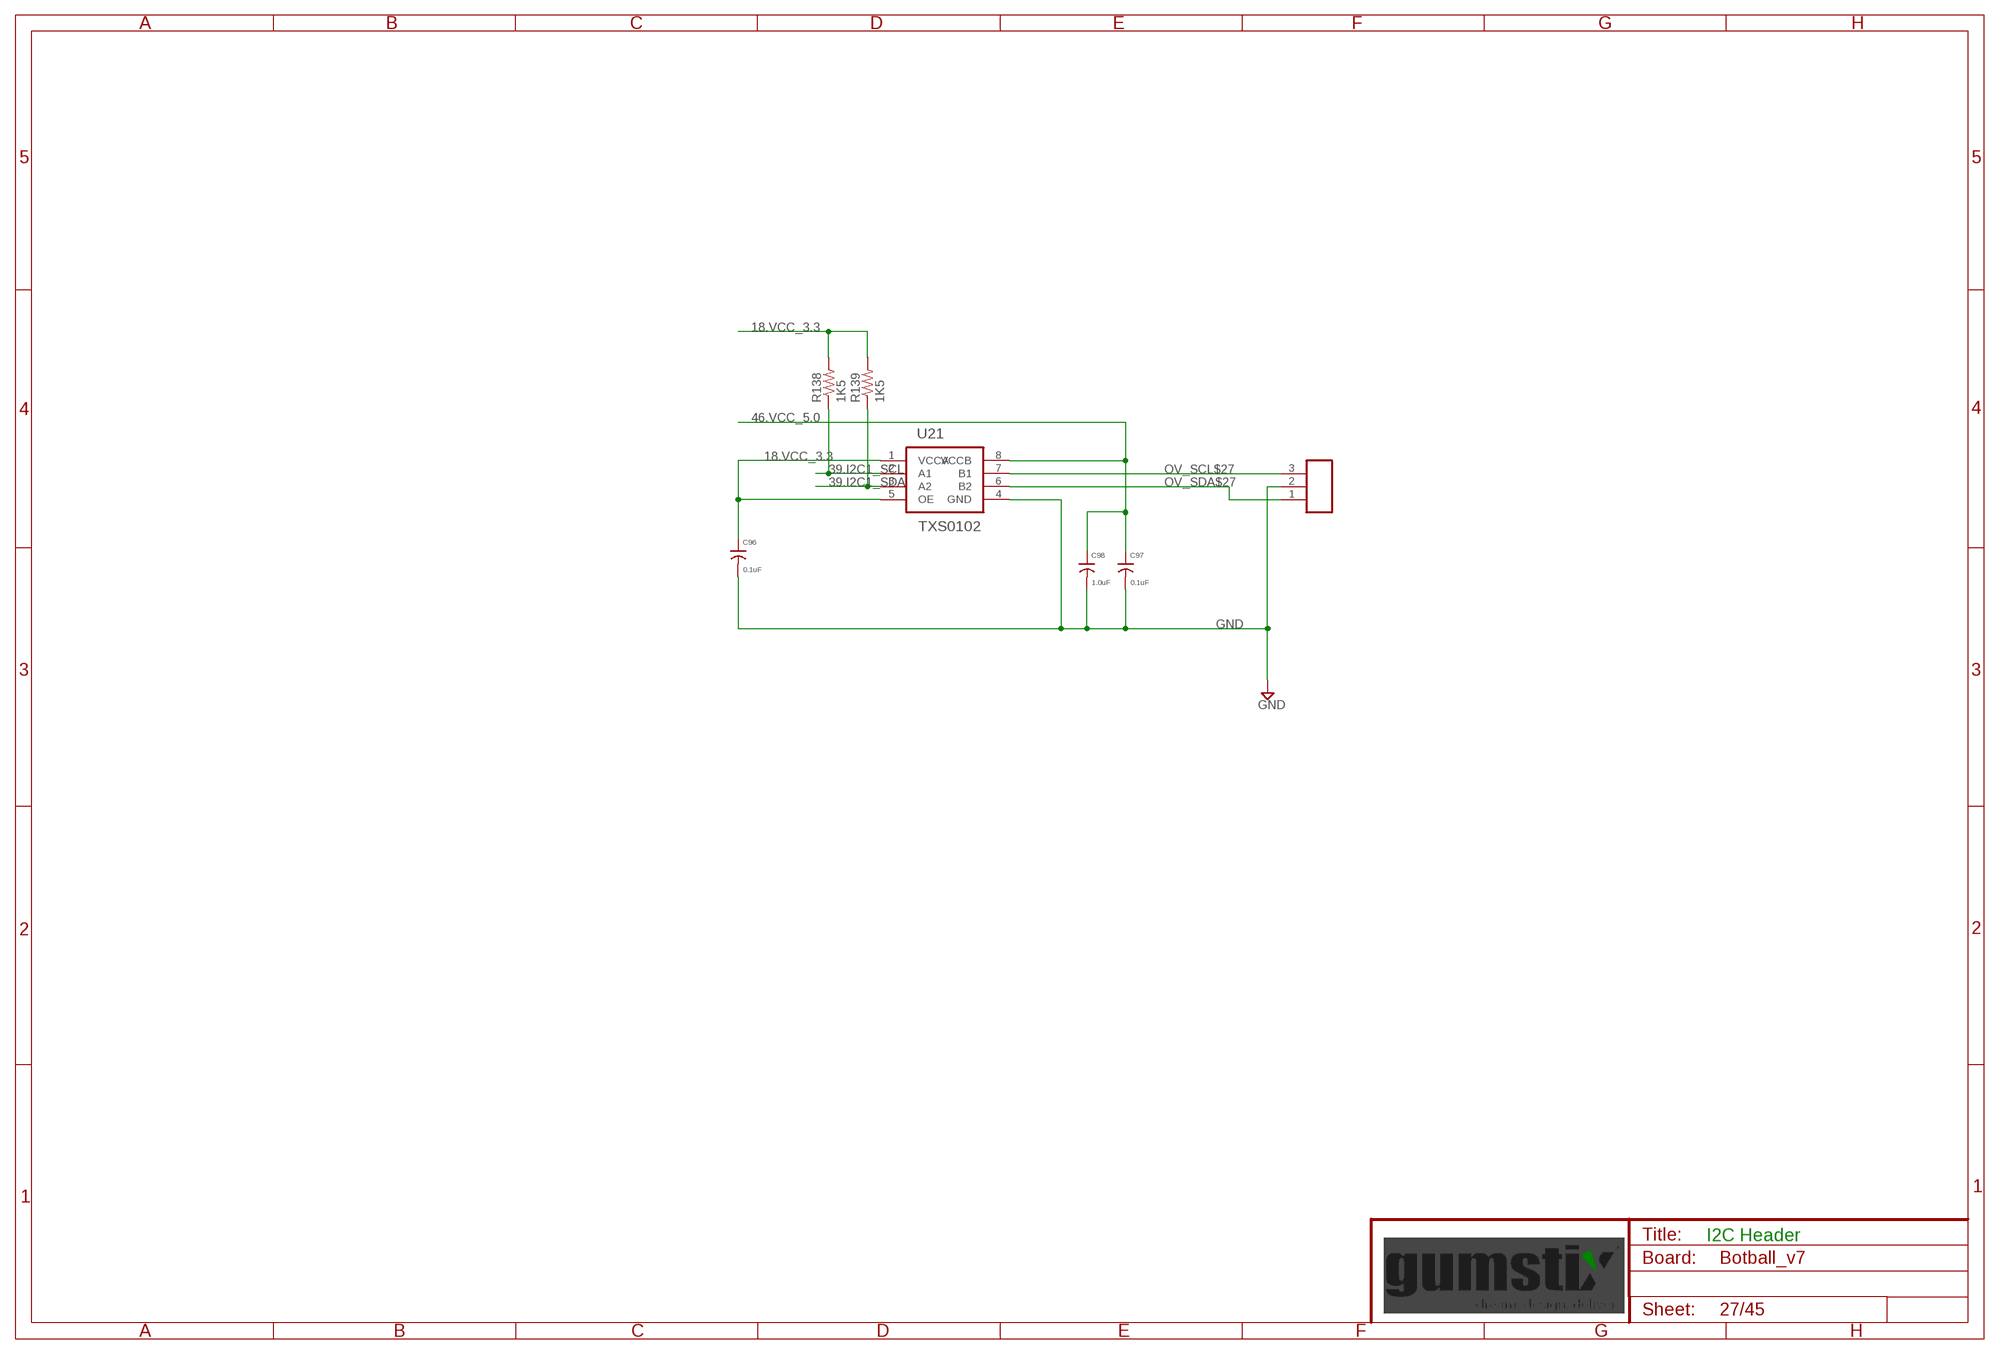
[diagram p26: schematic, sheet 27]
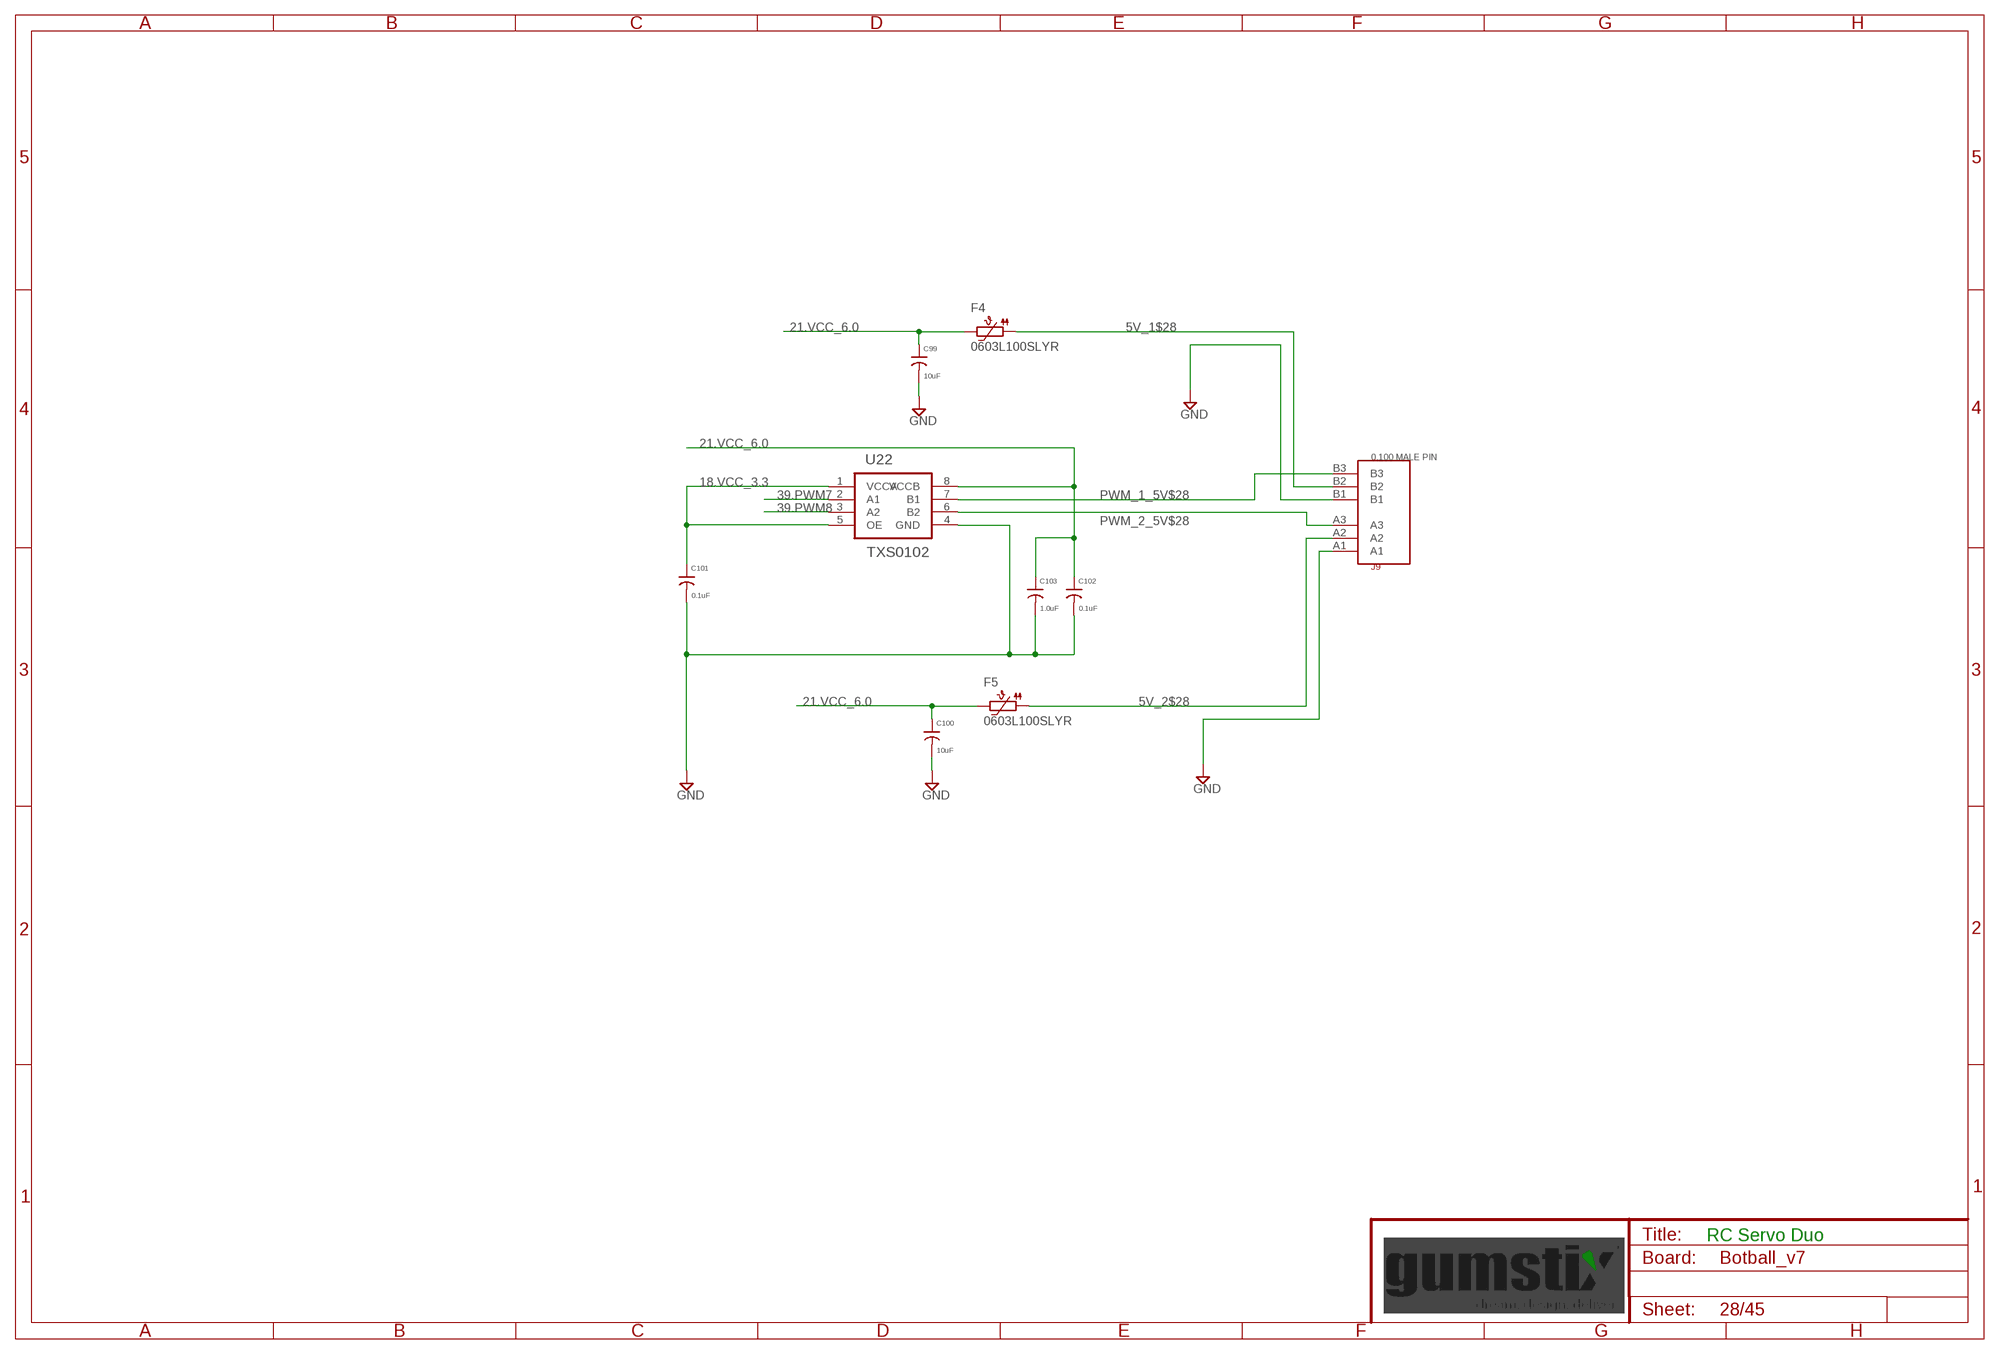
[diagram p27: schematic, sheet 28]
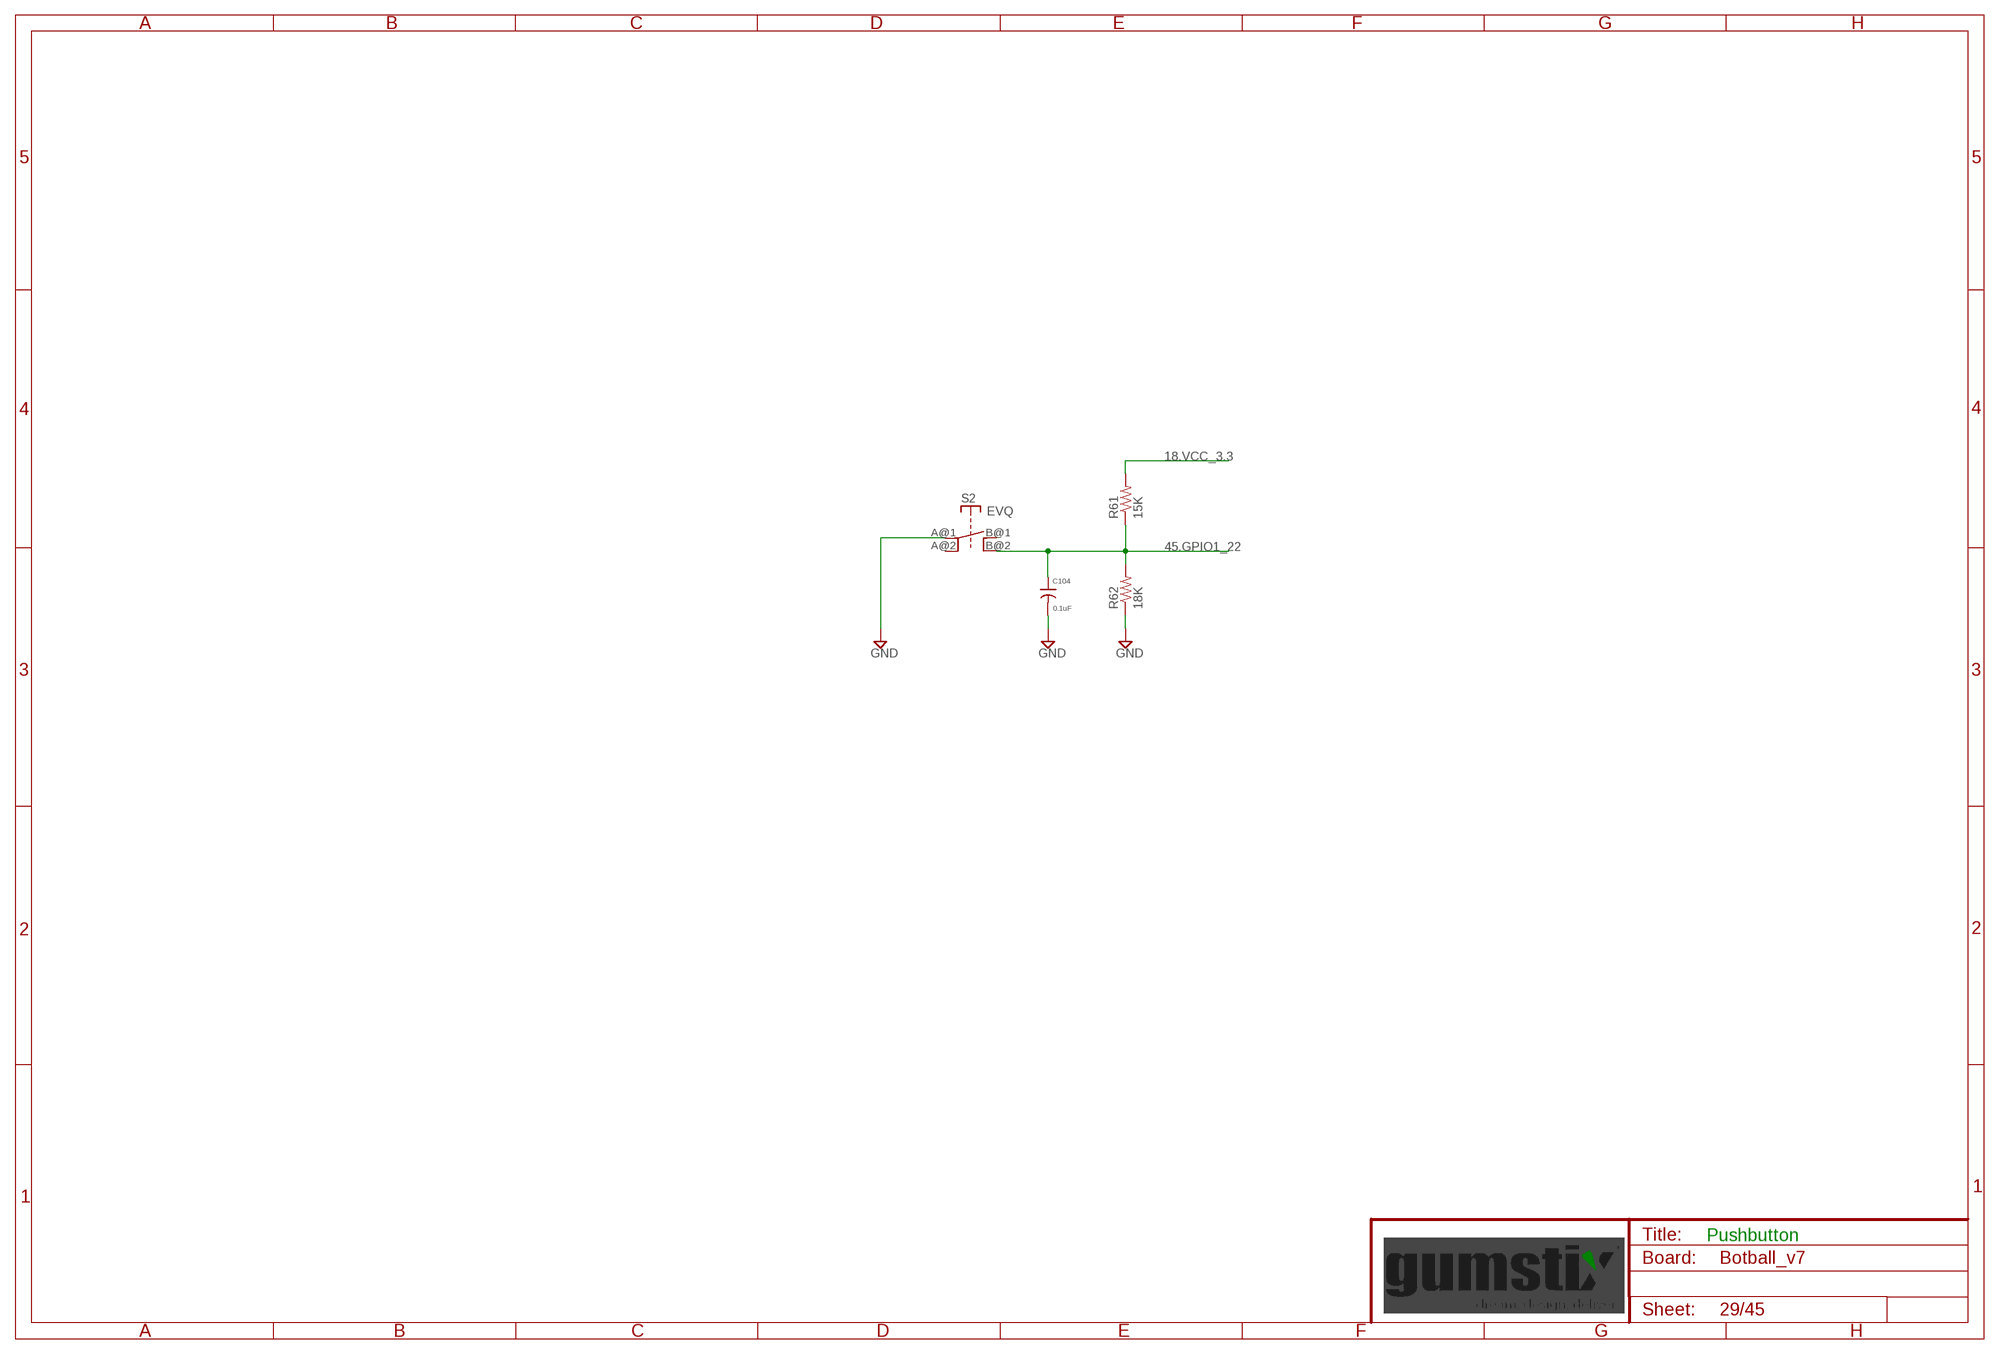
[diagram p28: schematic, sheet 29]
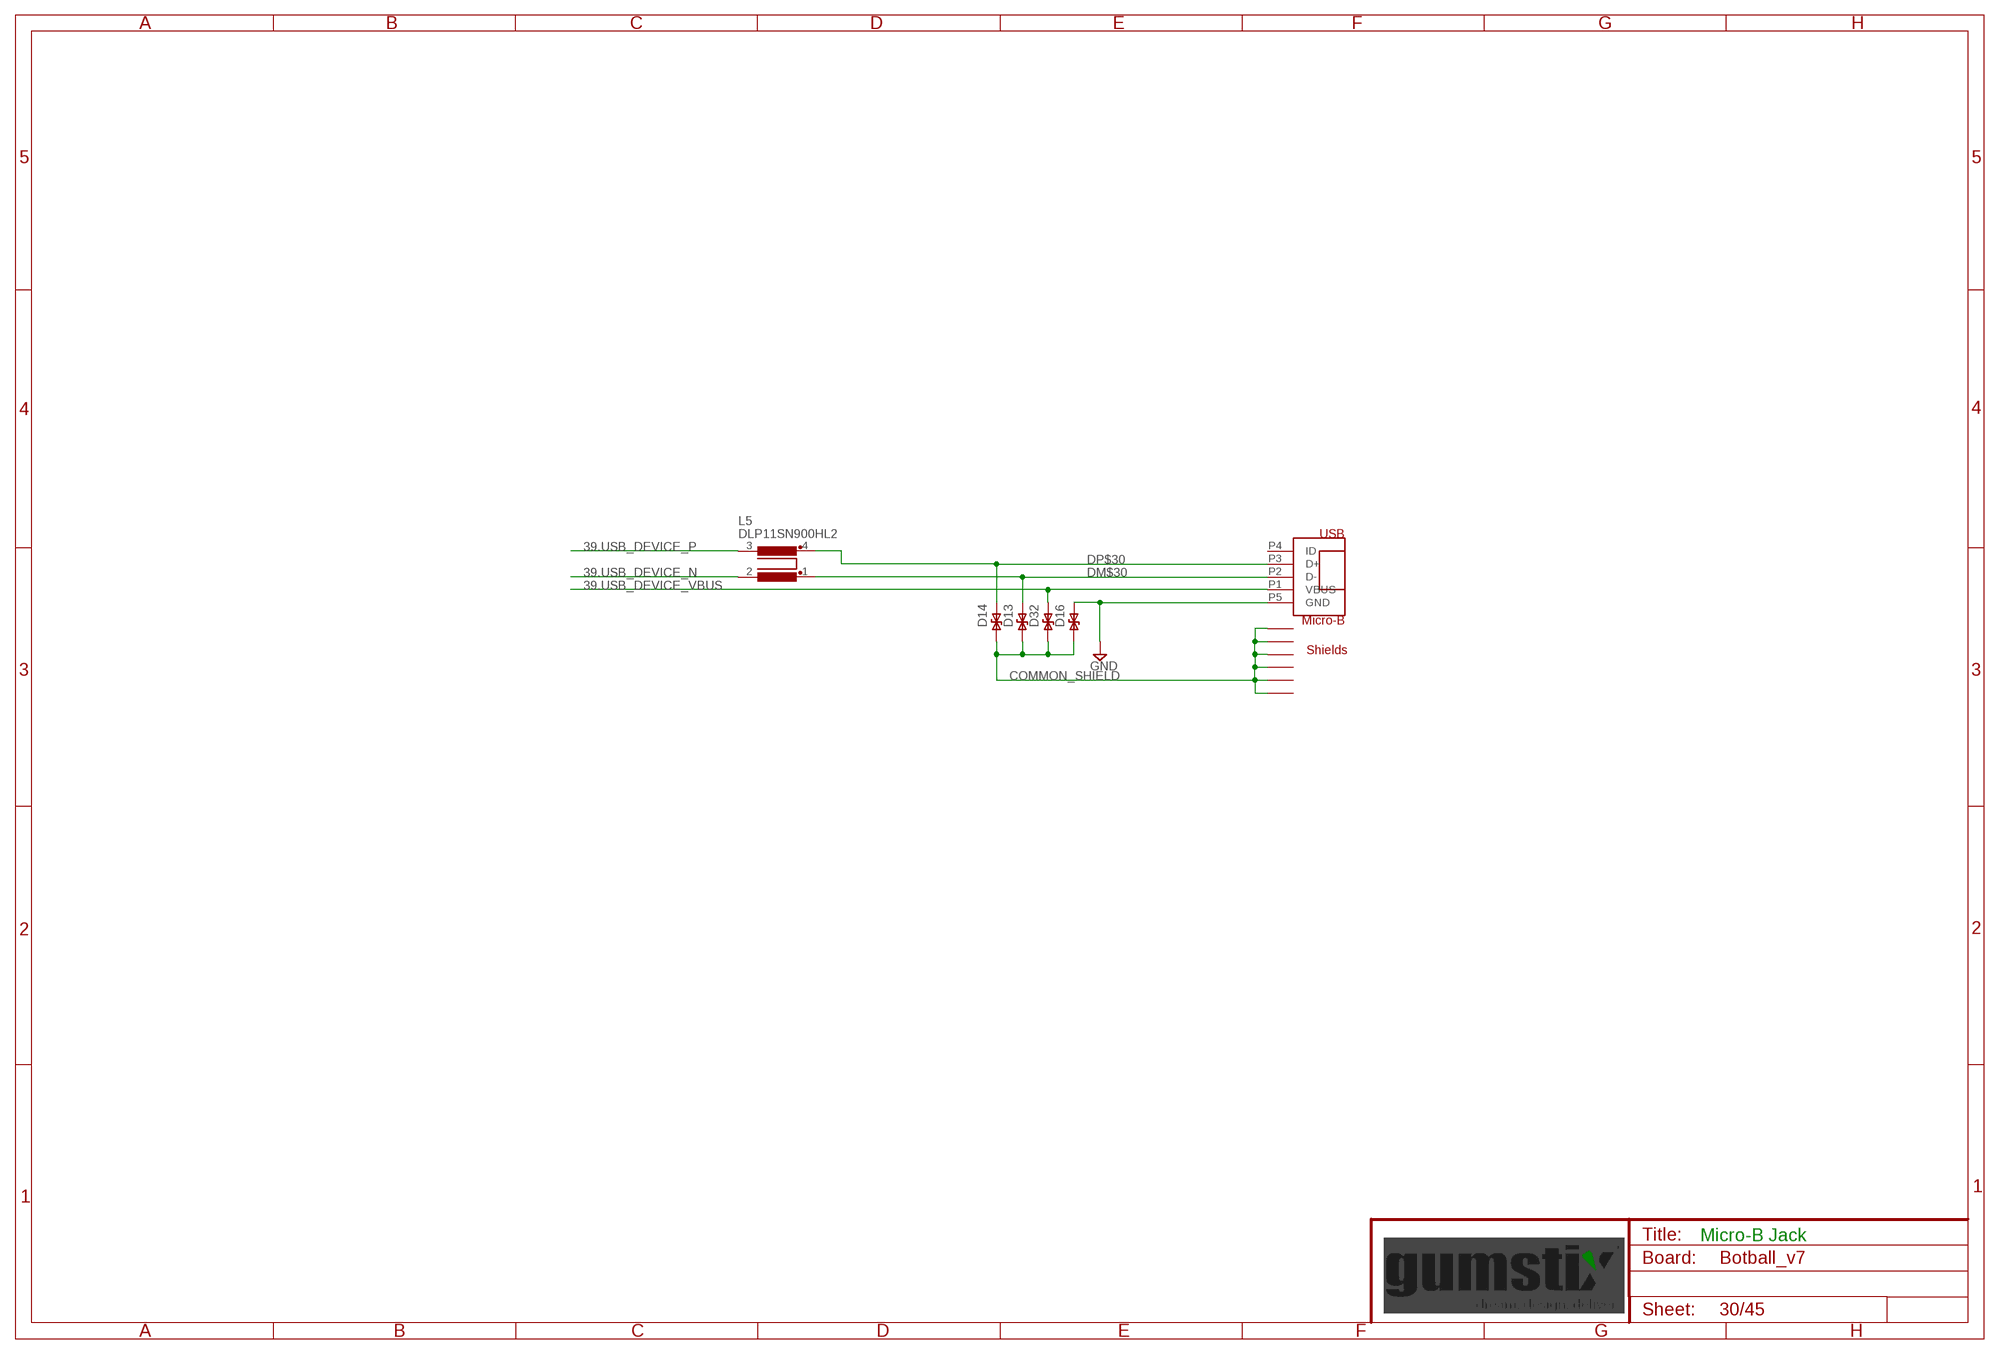
[diagram p29: schematic, sheet 30]
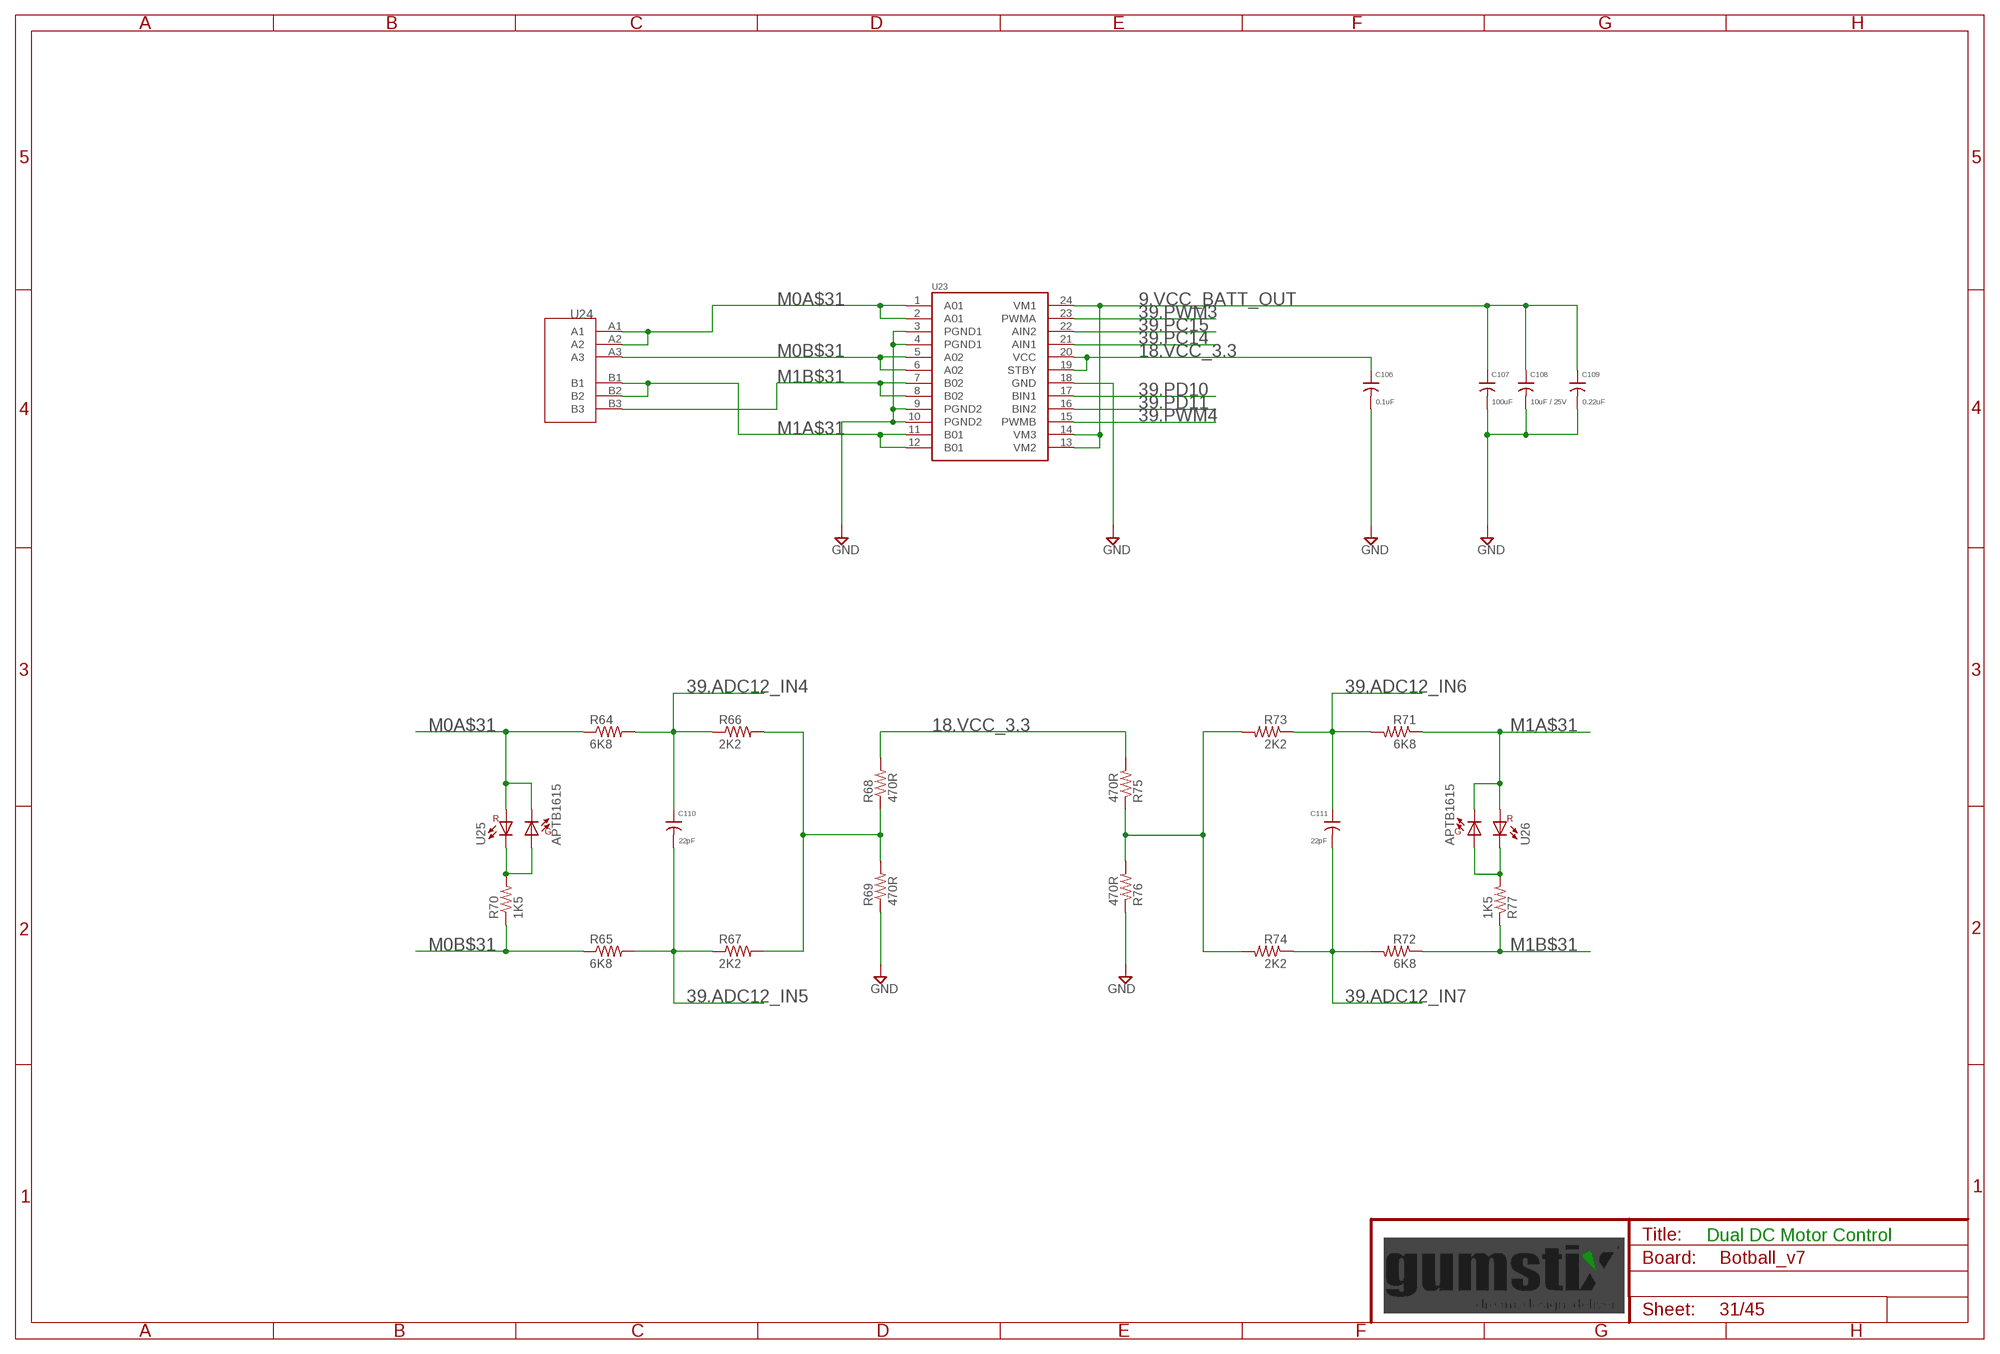
[diagram p30: schematic, sheet 31]
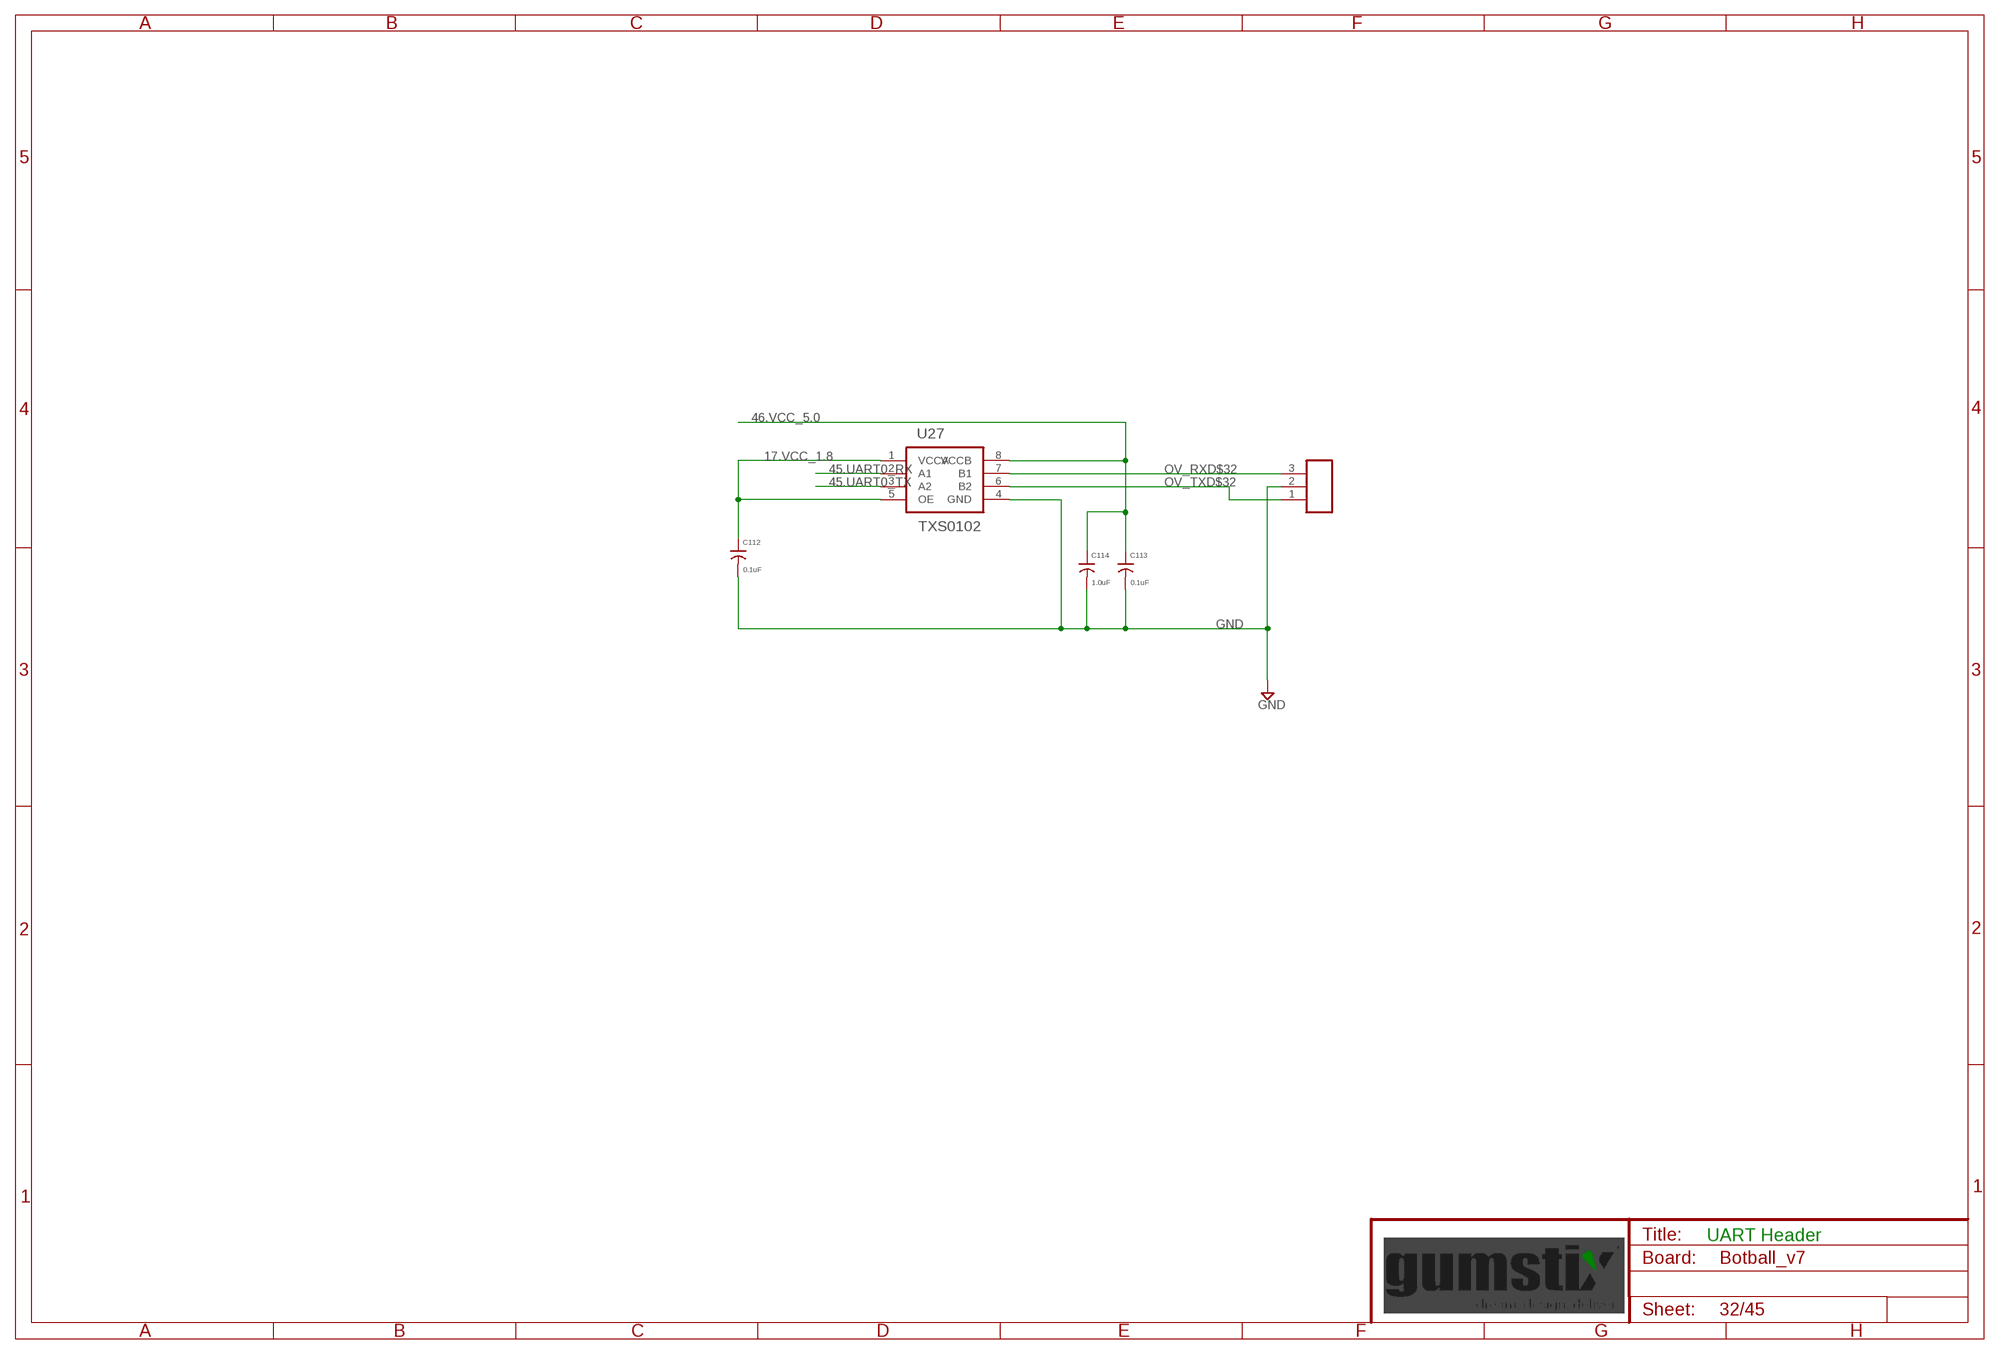
[diagram p31: schematic, sheet 32]
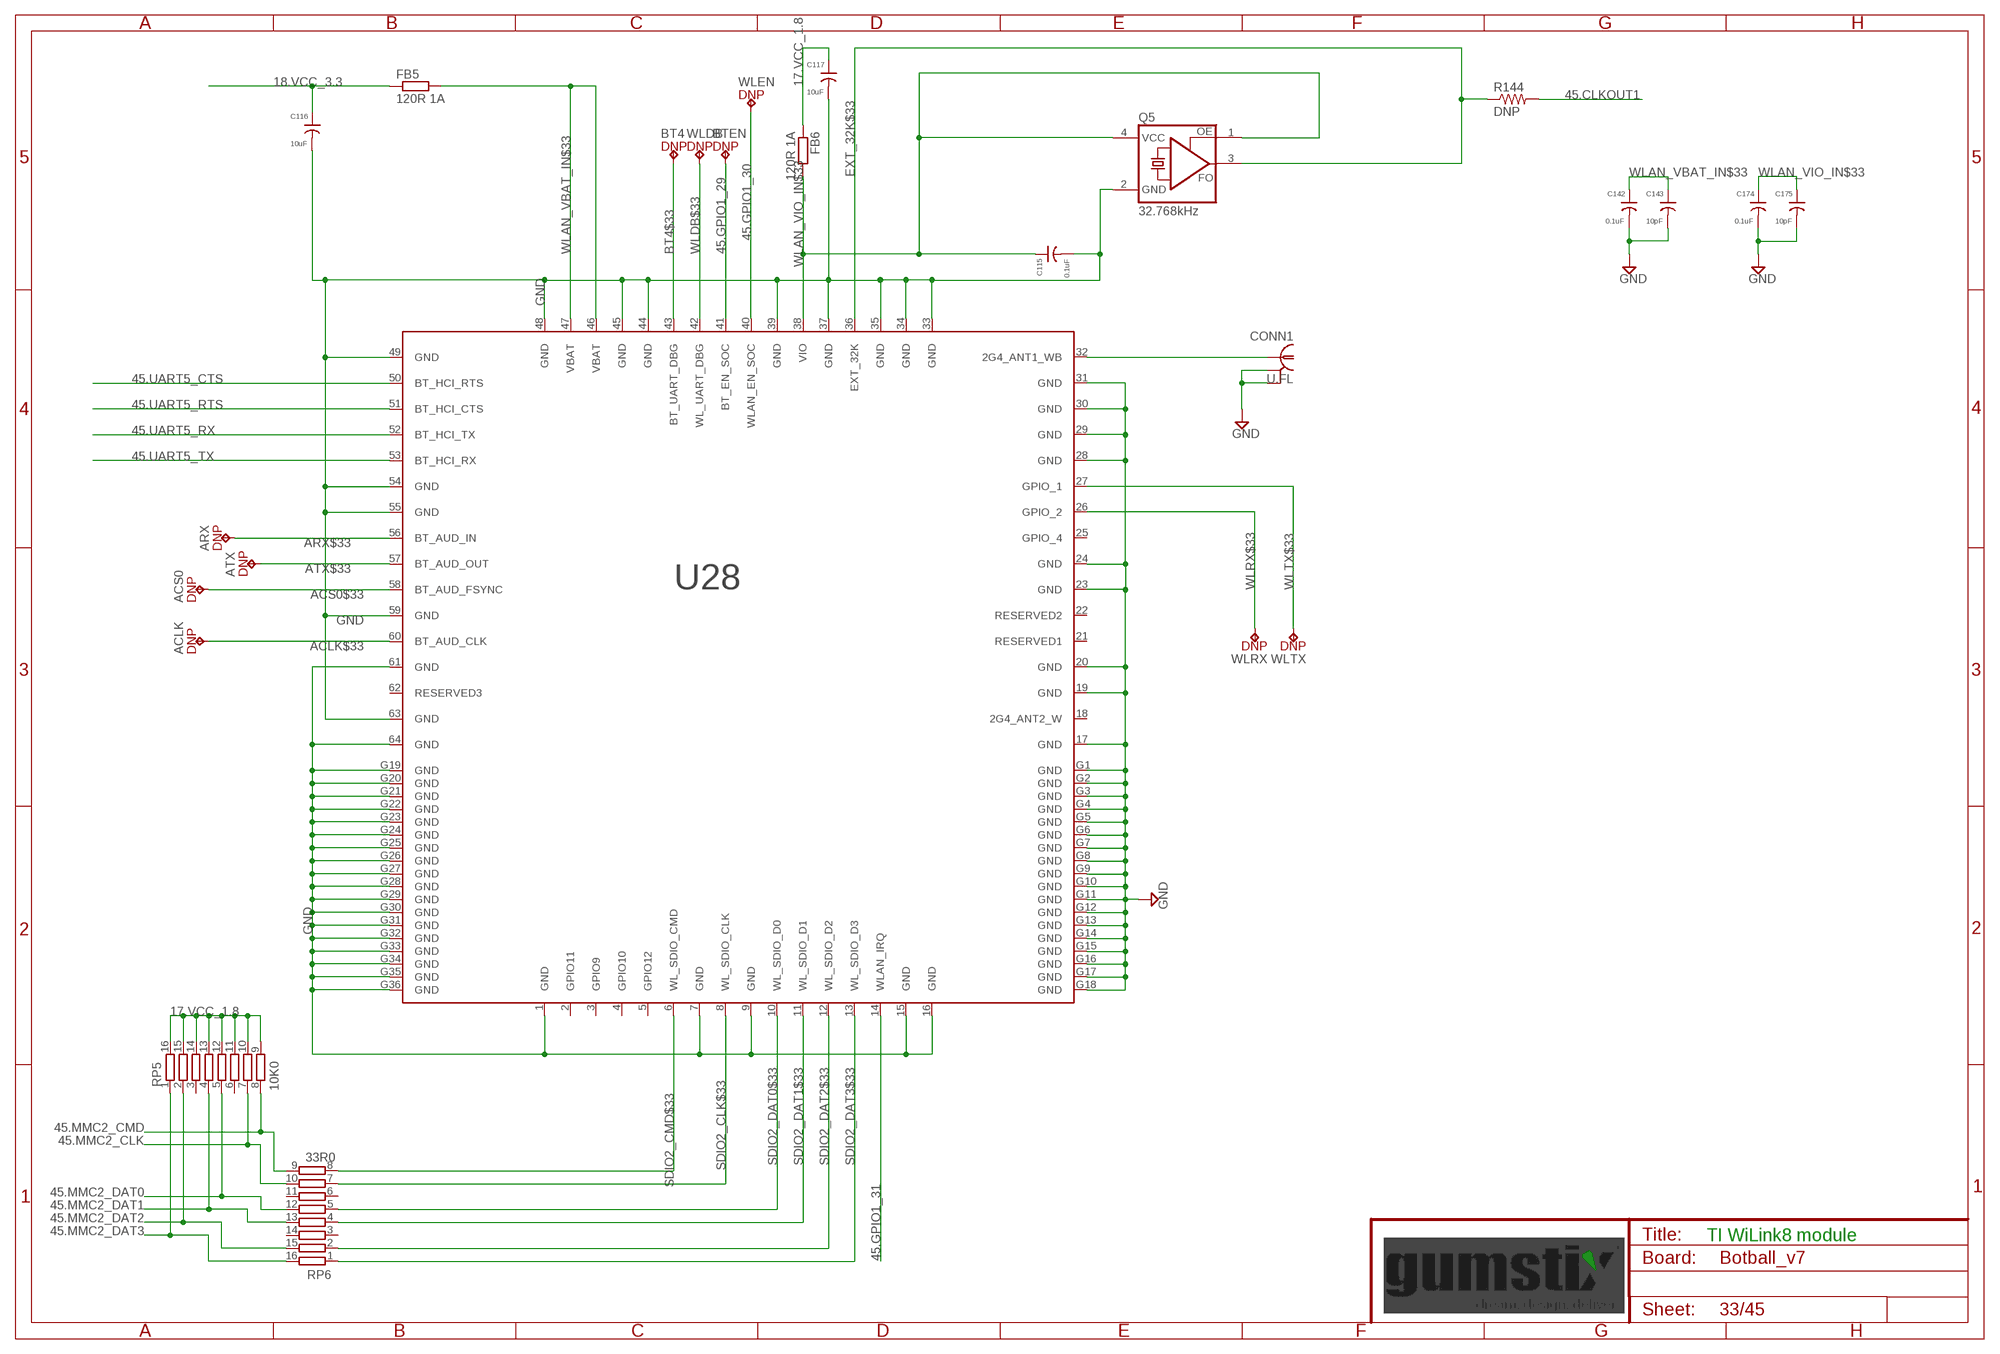
[diagram p32: schematic, sheet 33]
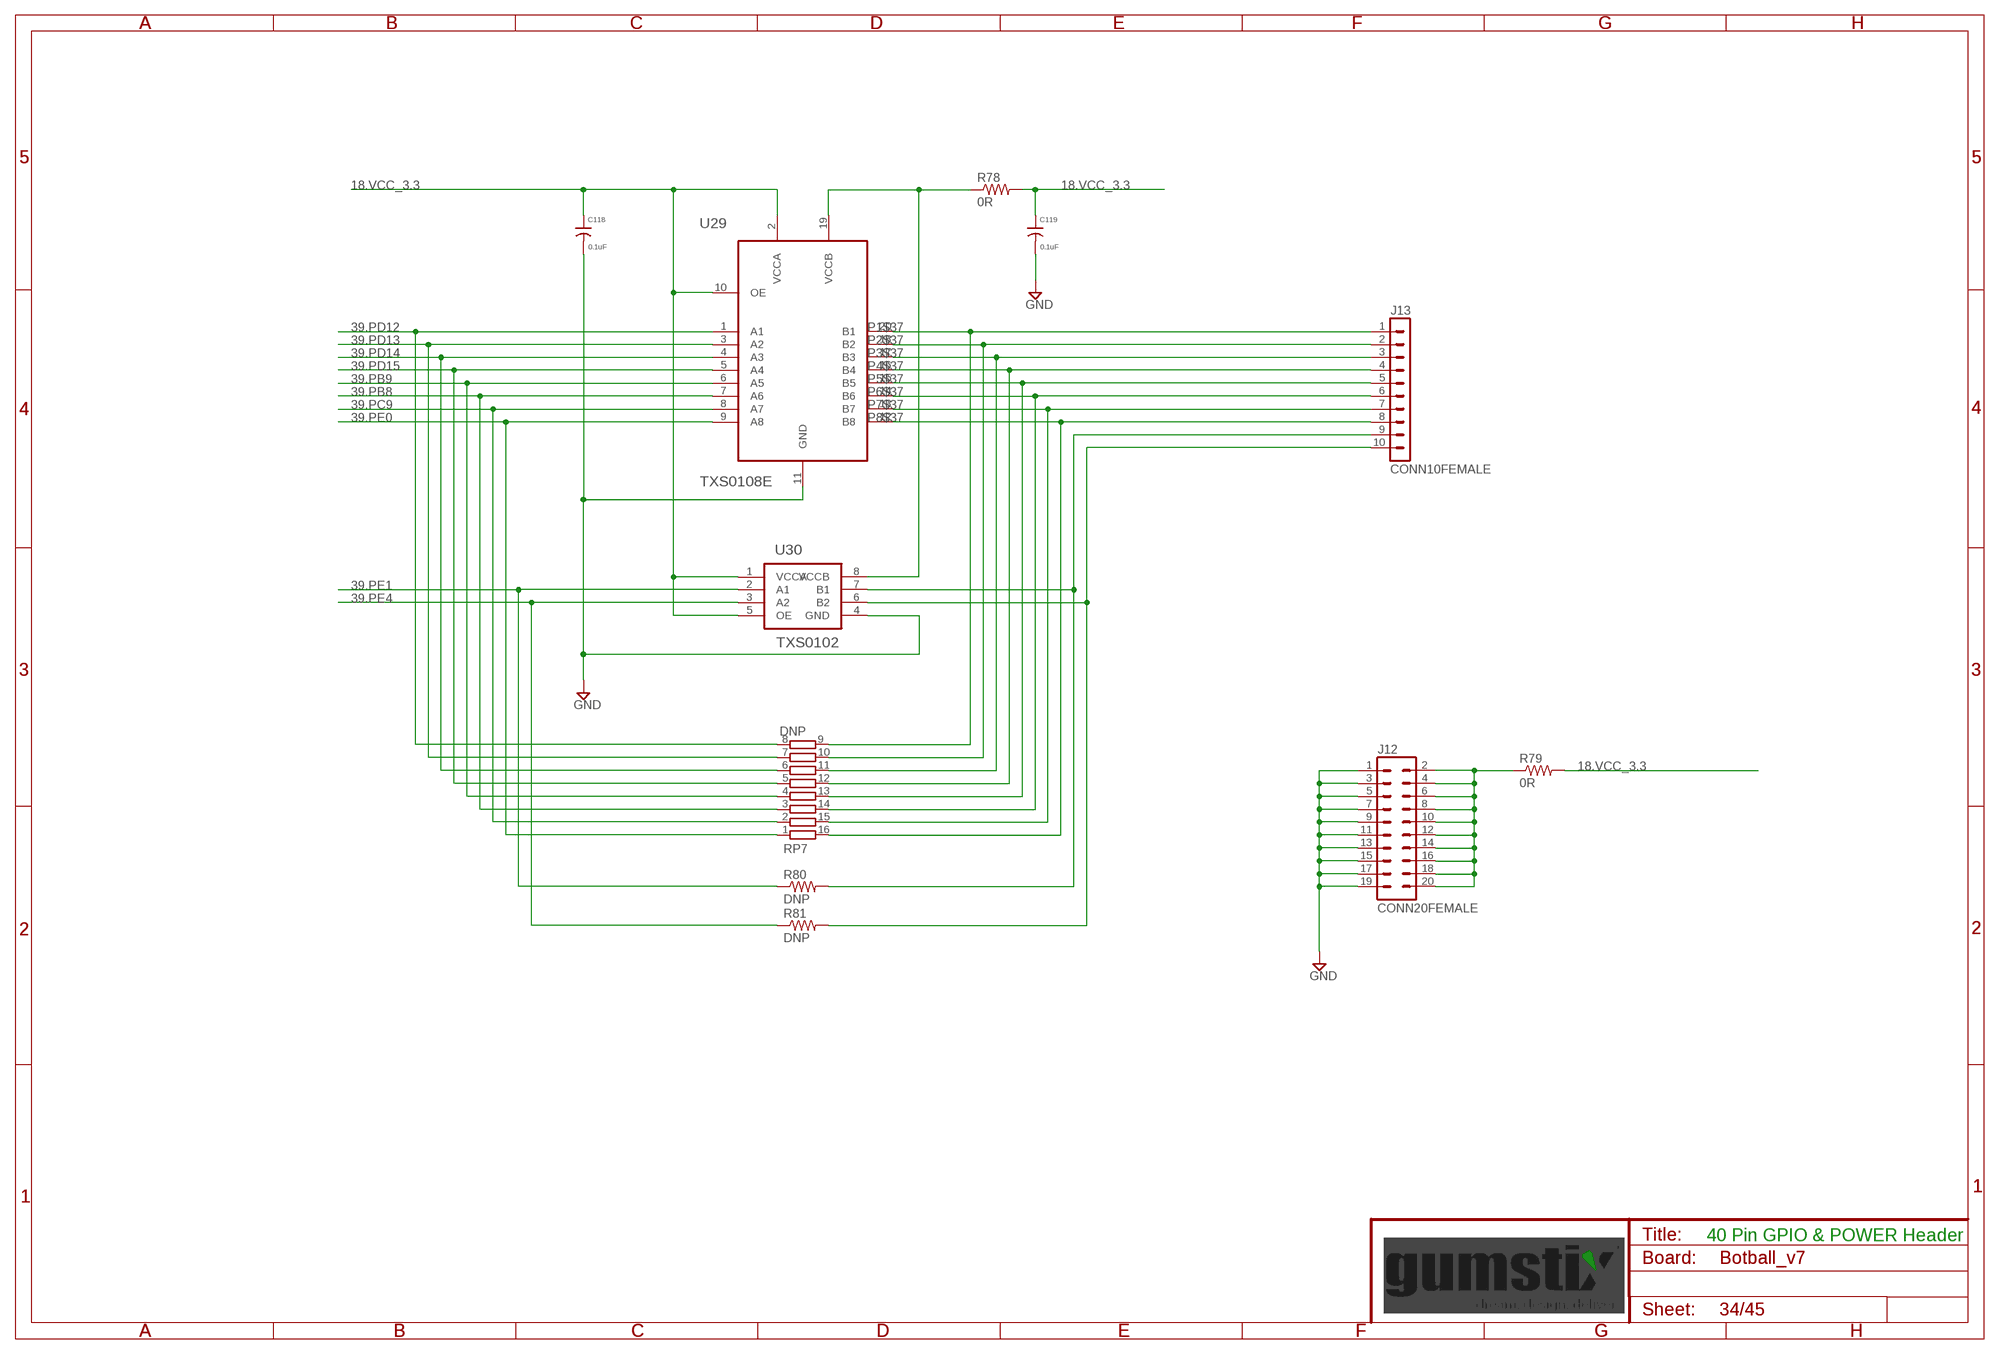
[diagram p33: schematic, sheet 34]
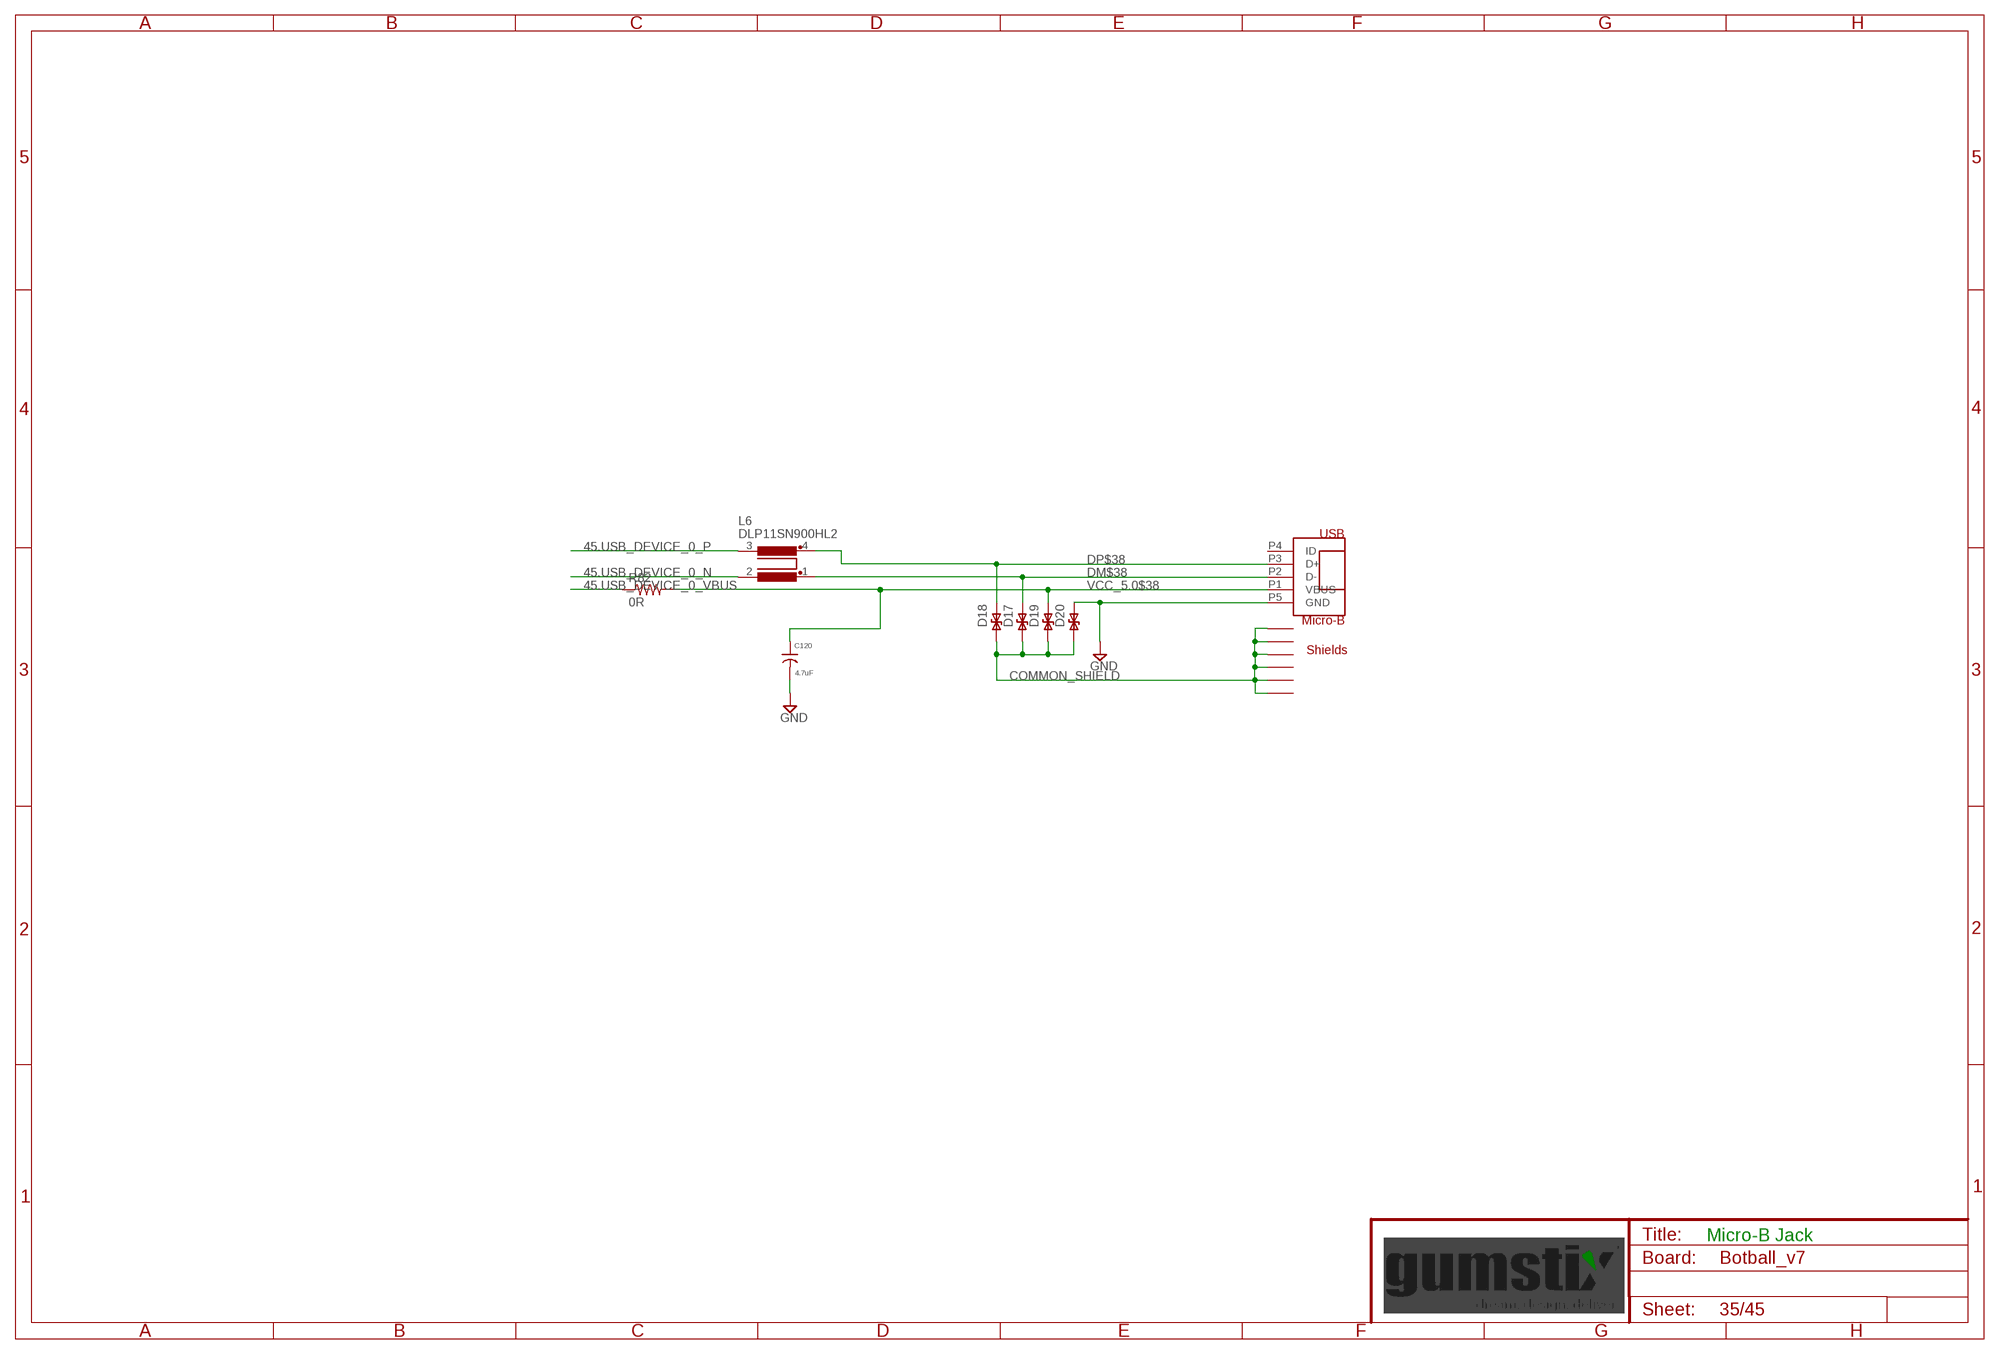
[diagram p34: schematic, sheet 35]
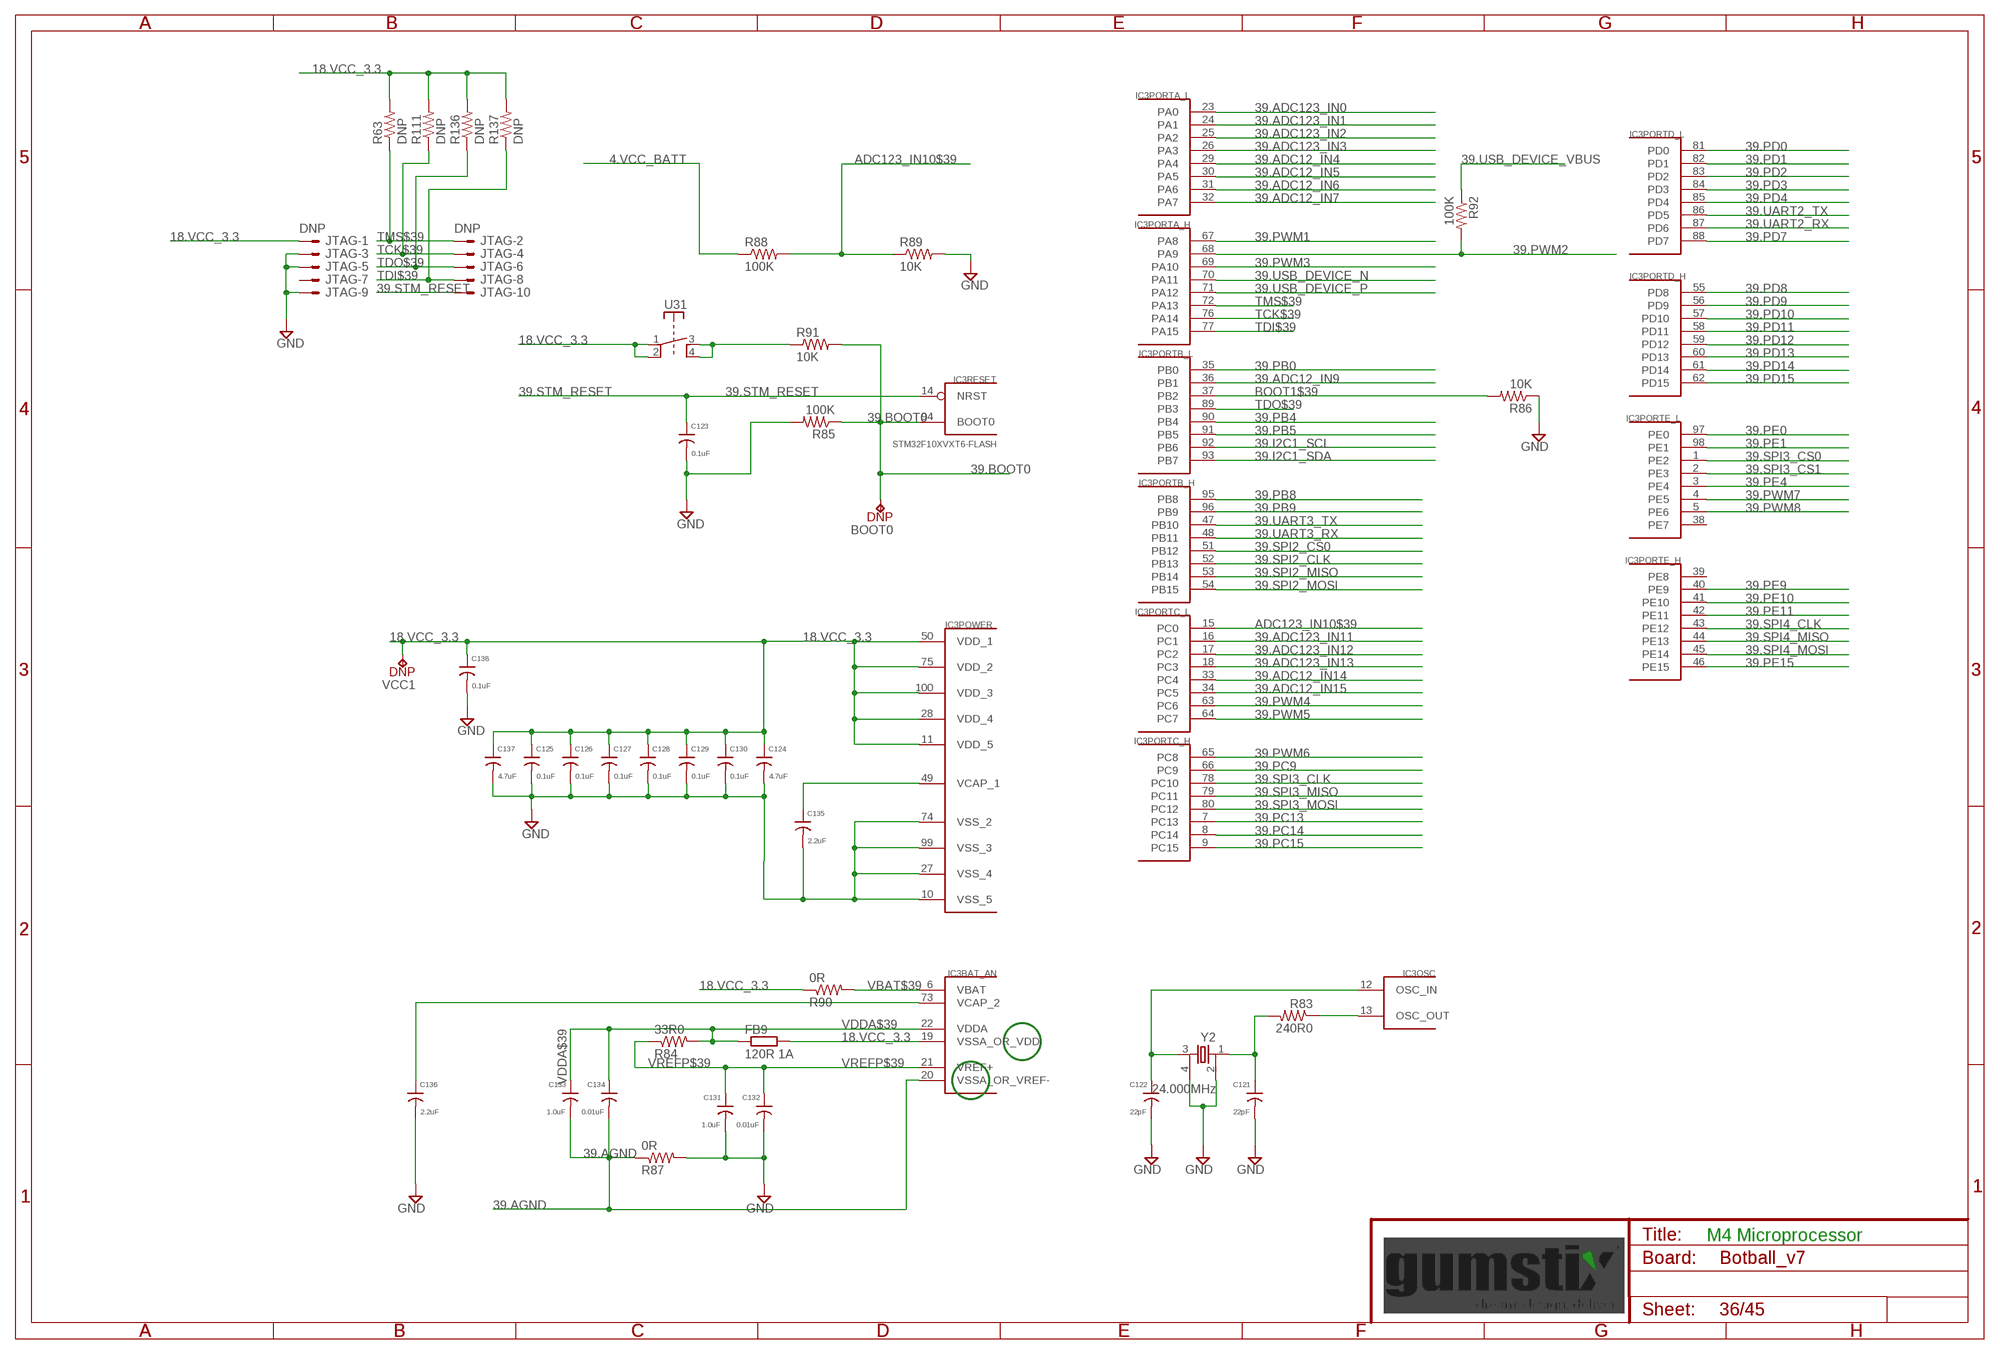
[diagram p35: schematic, sheet 36]
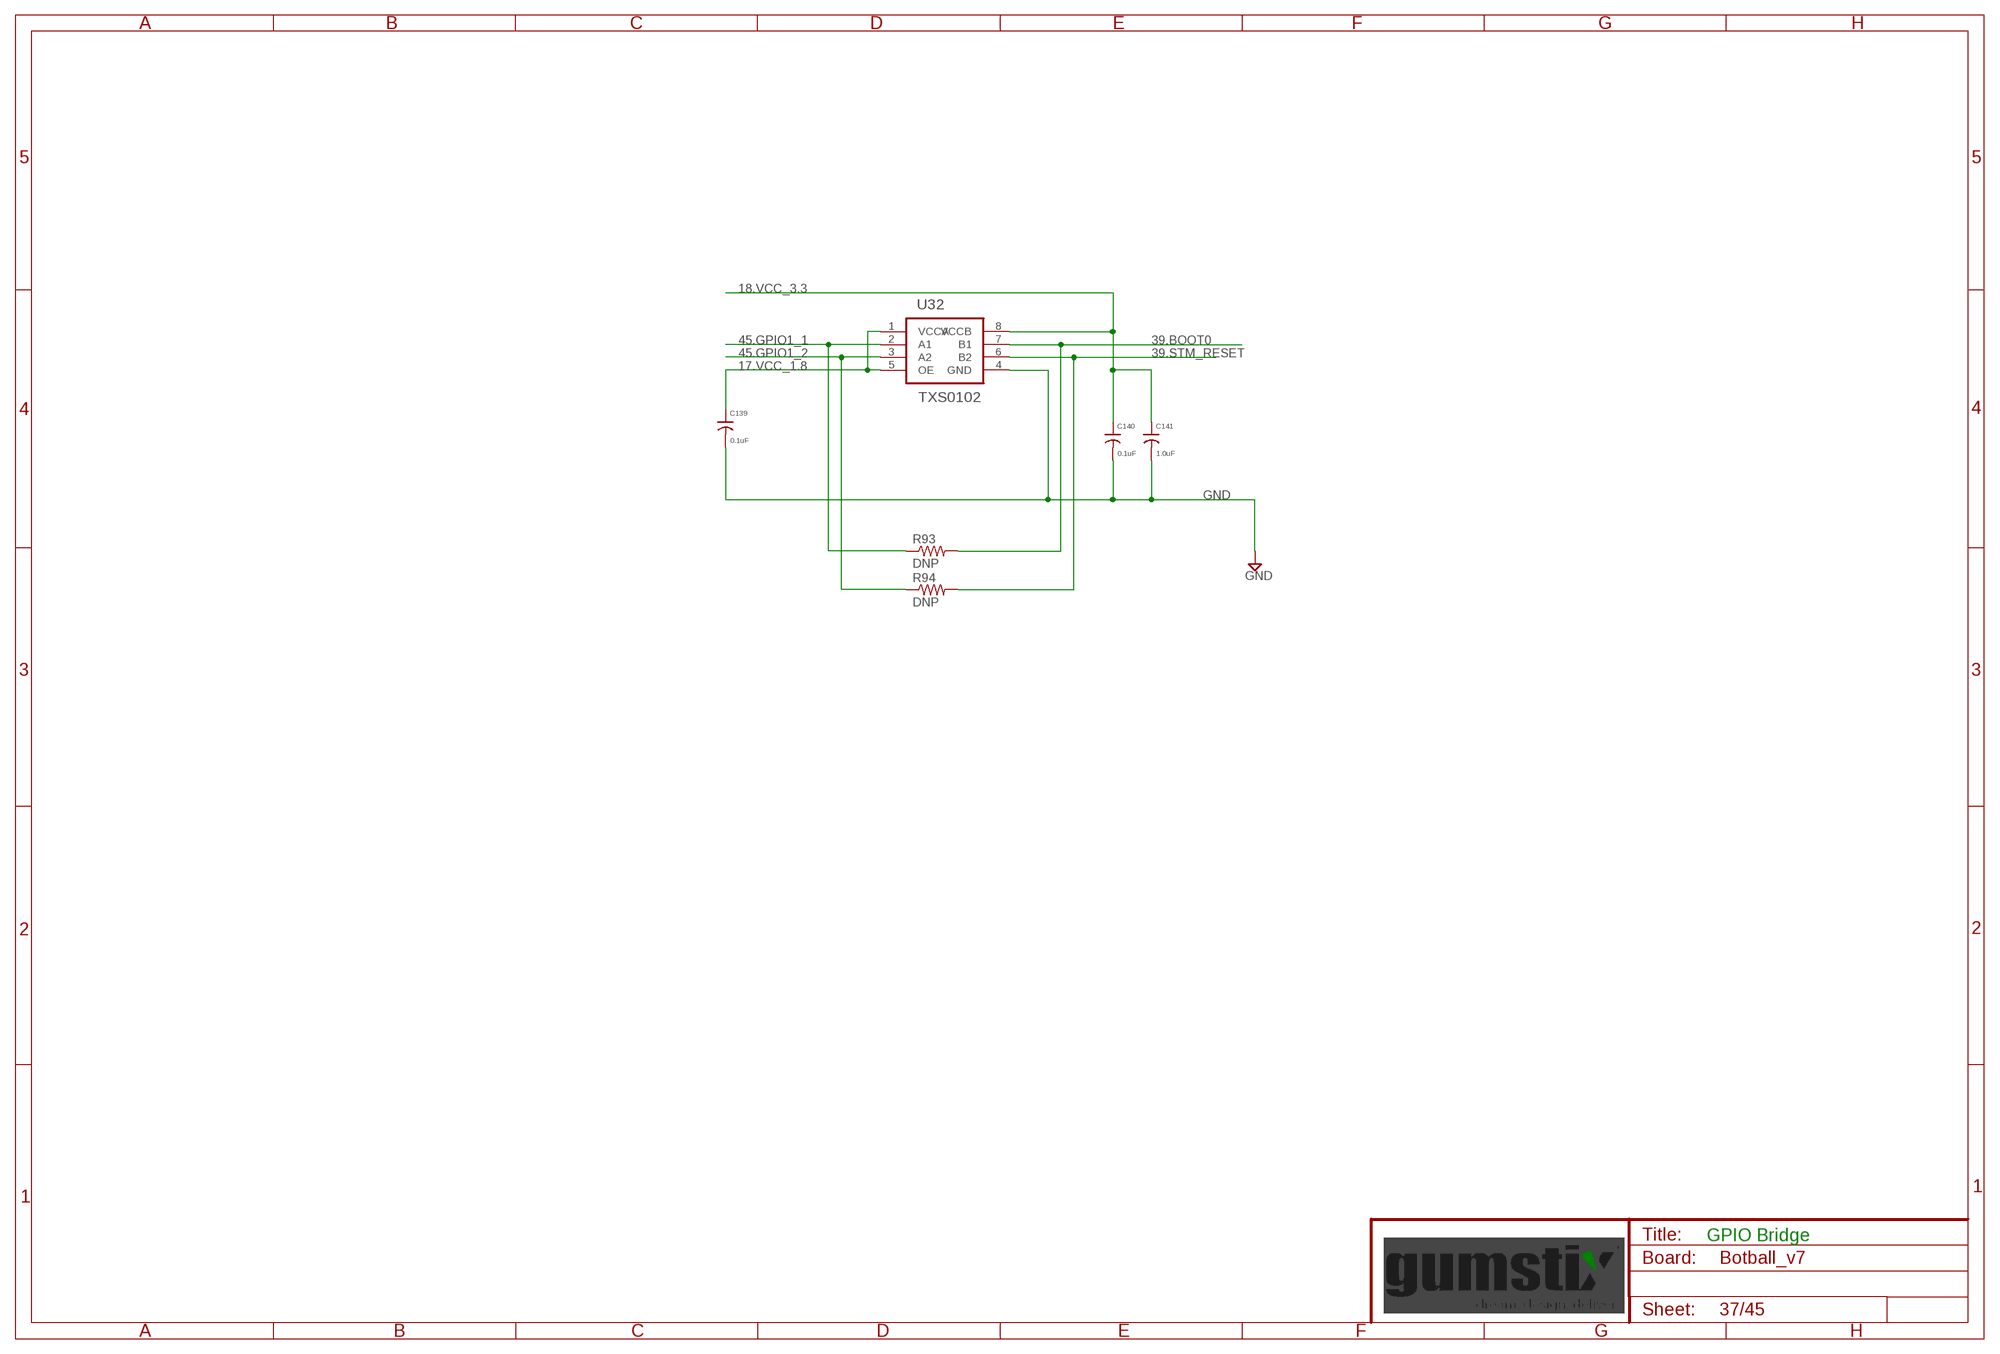
[diagram p36: schematic, sheet 37]
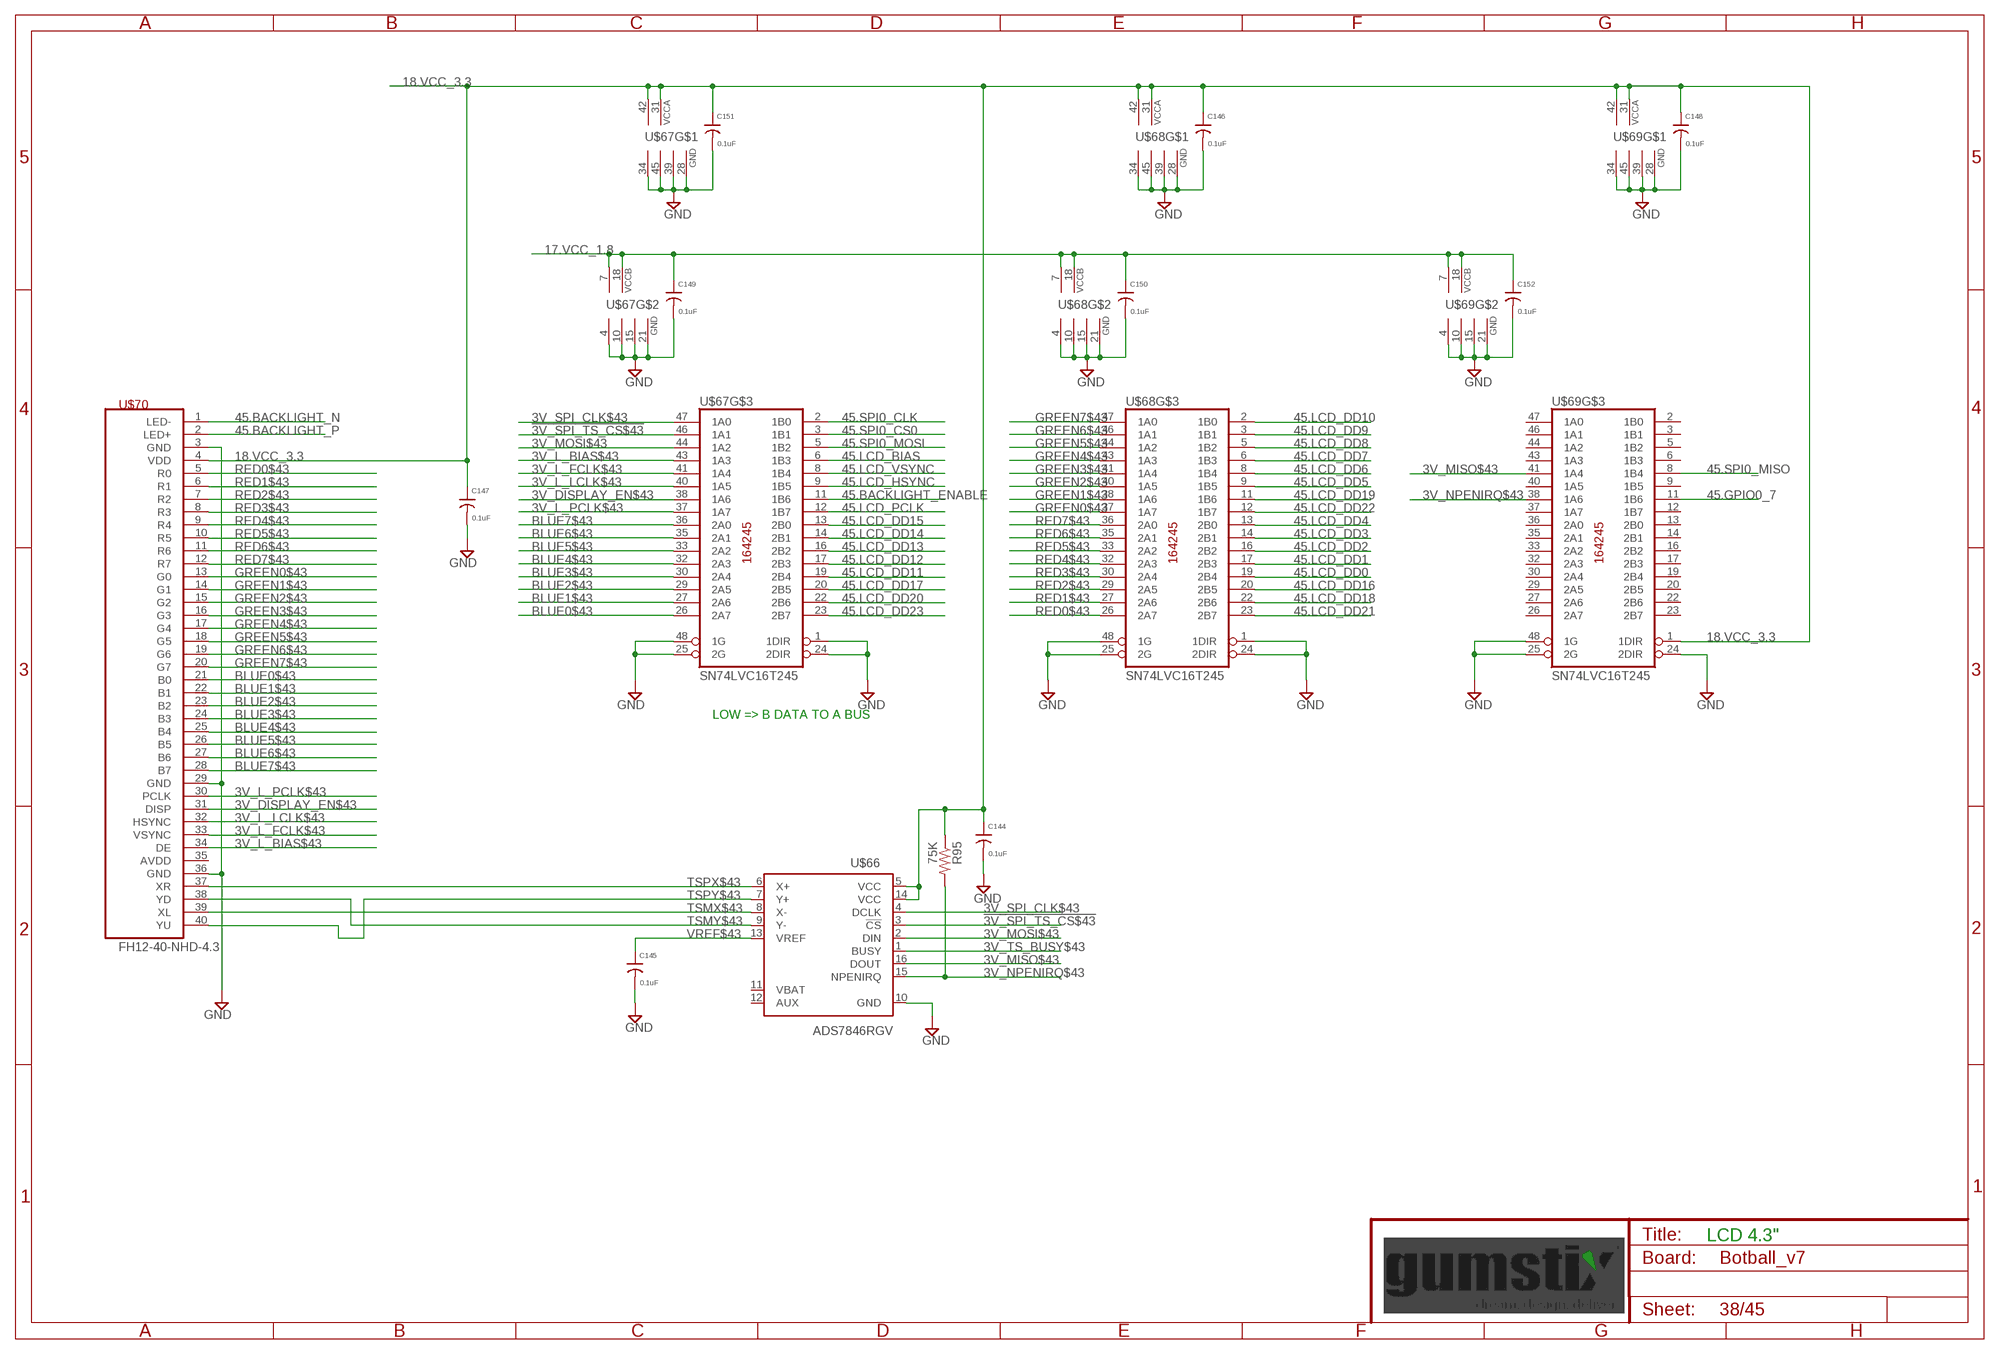
[diagram p37: schematic, sheet 38]
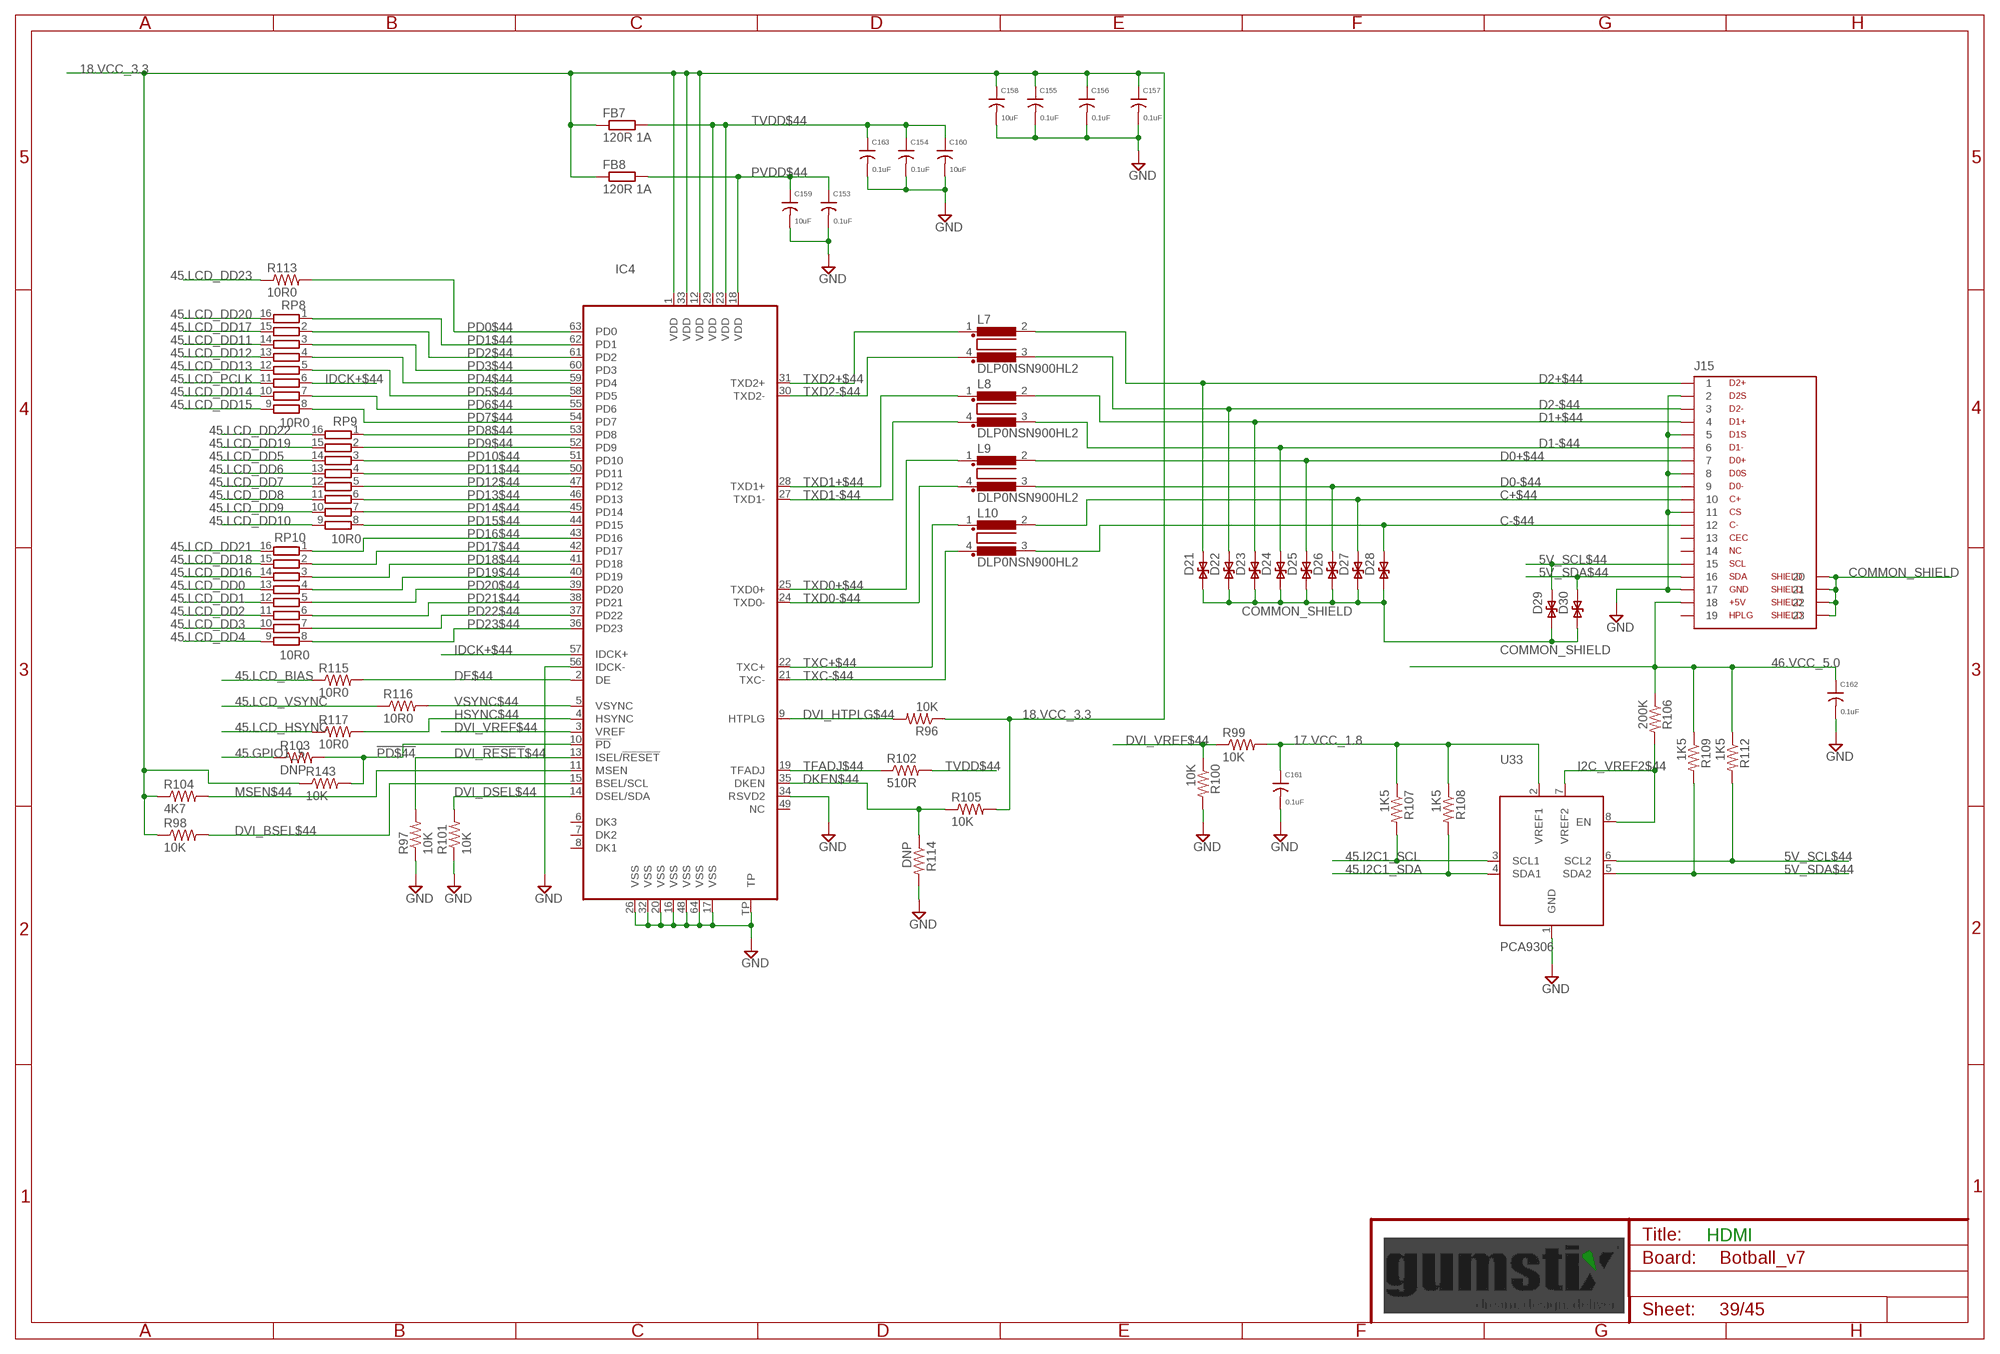
[diagram p38: schematic, sheet 39]
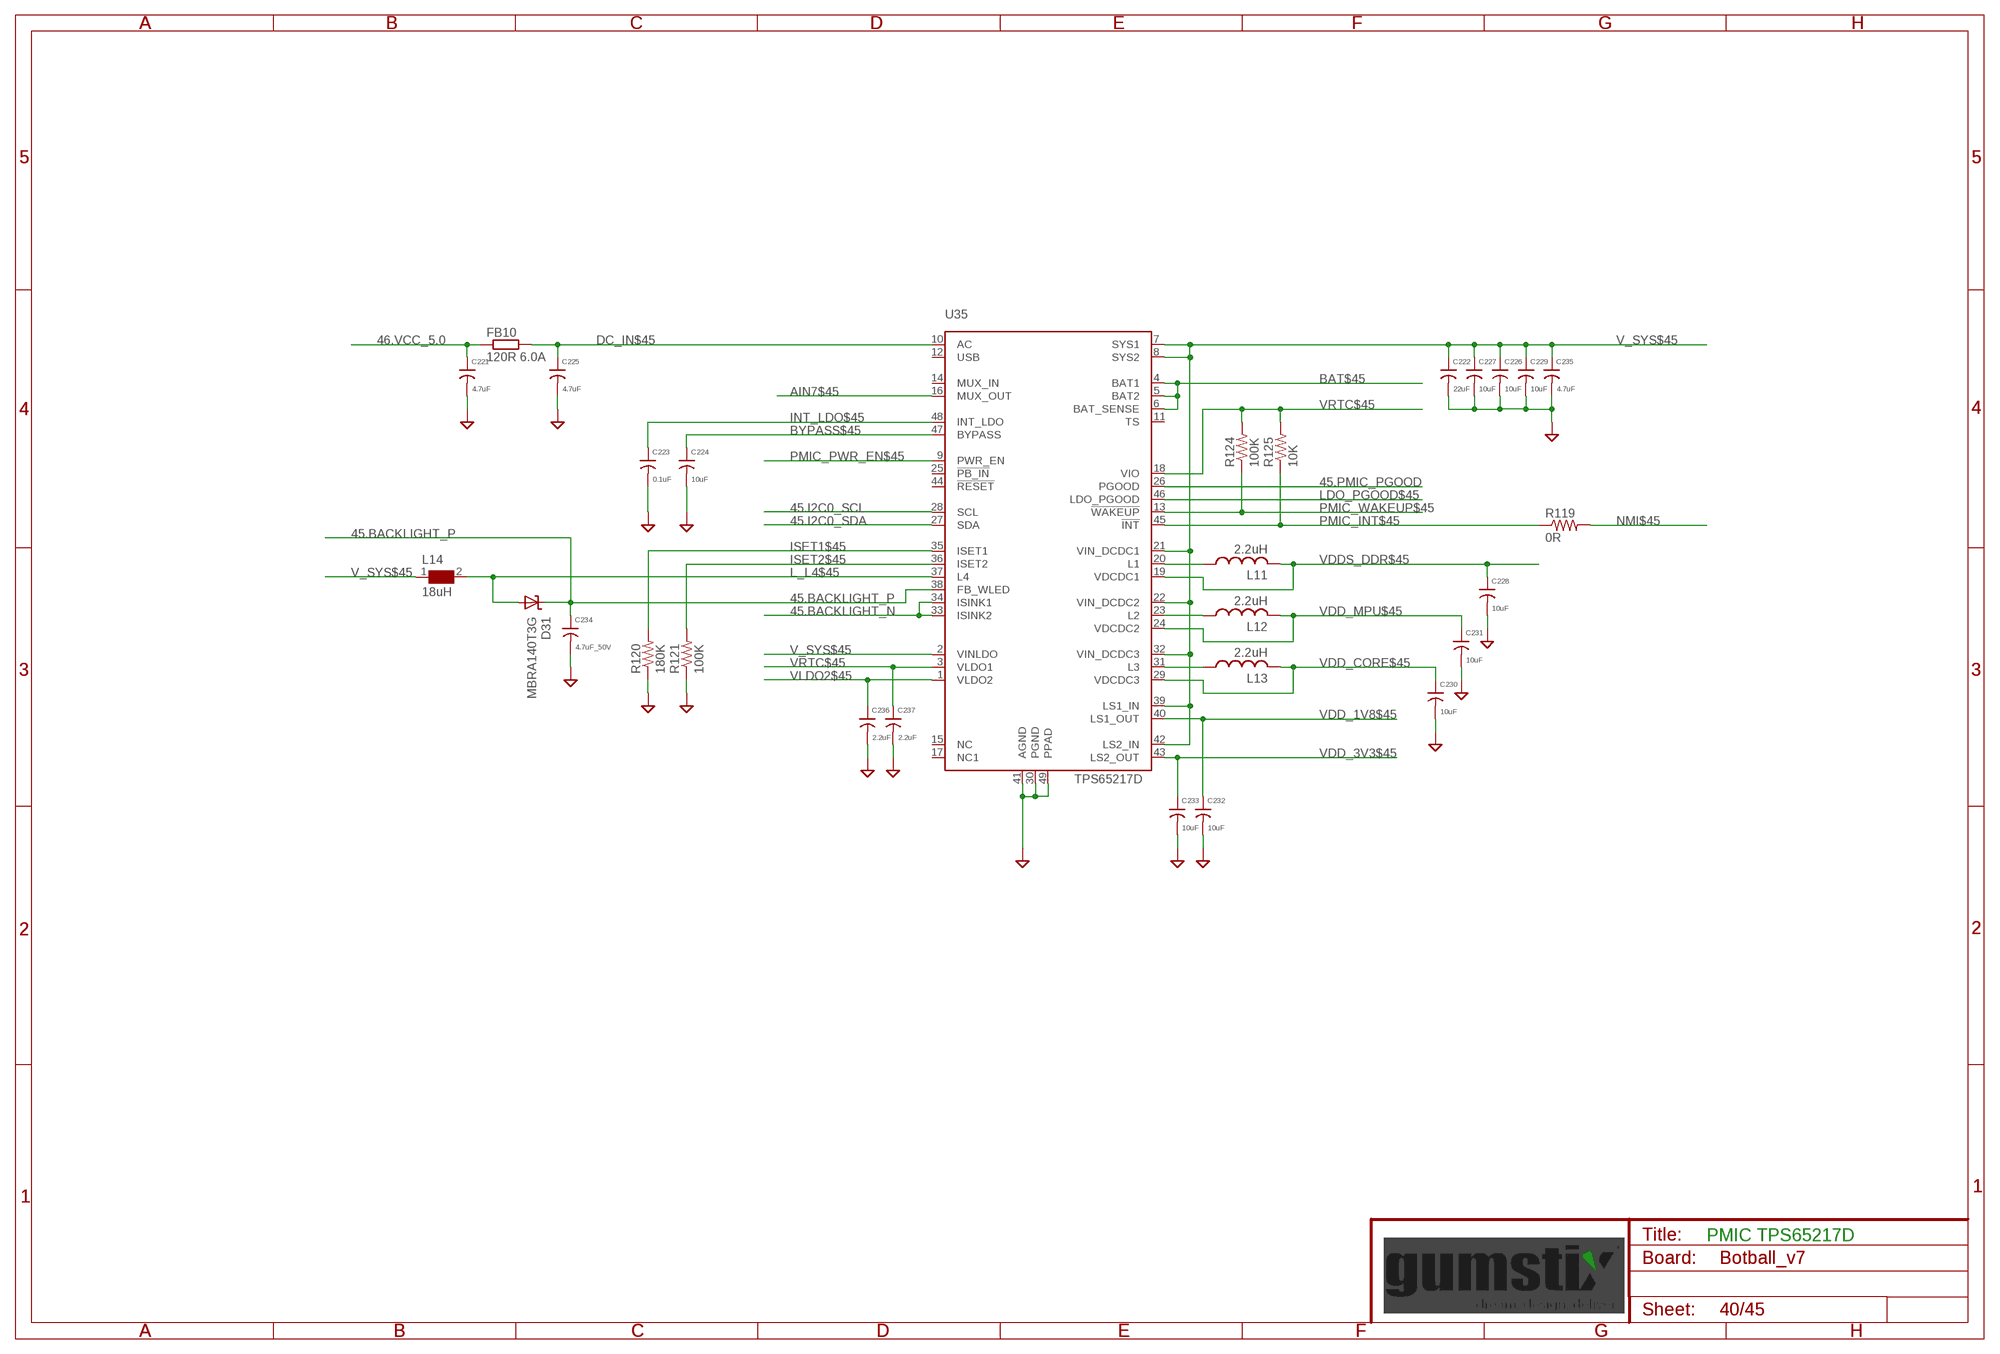
[diagram p39: schematic, sheet 40]
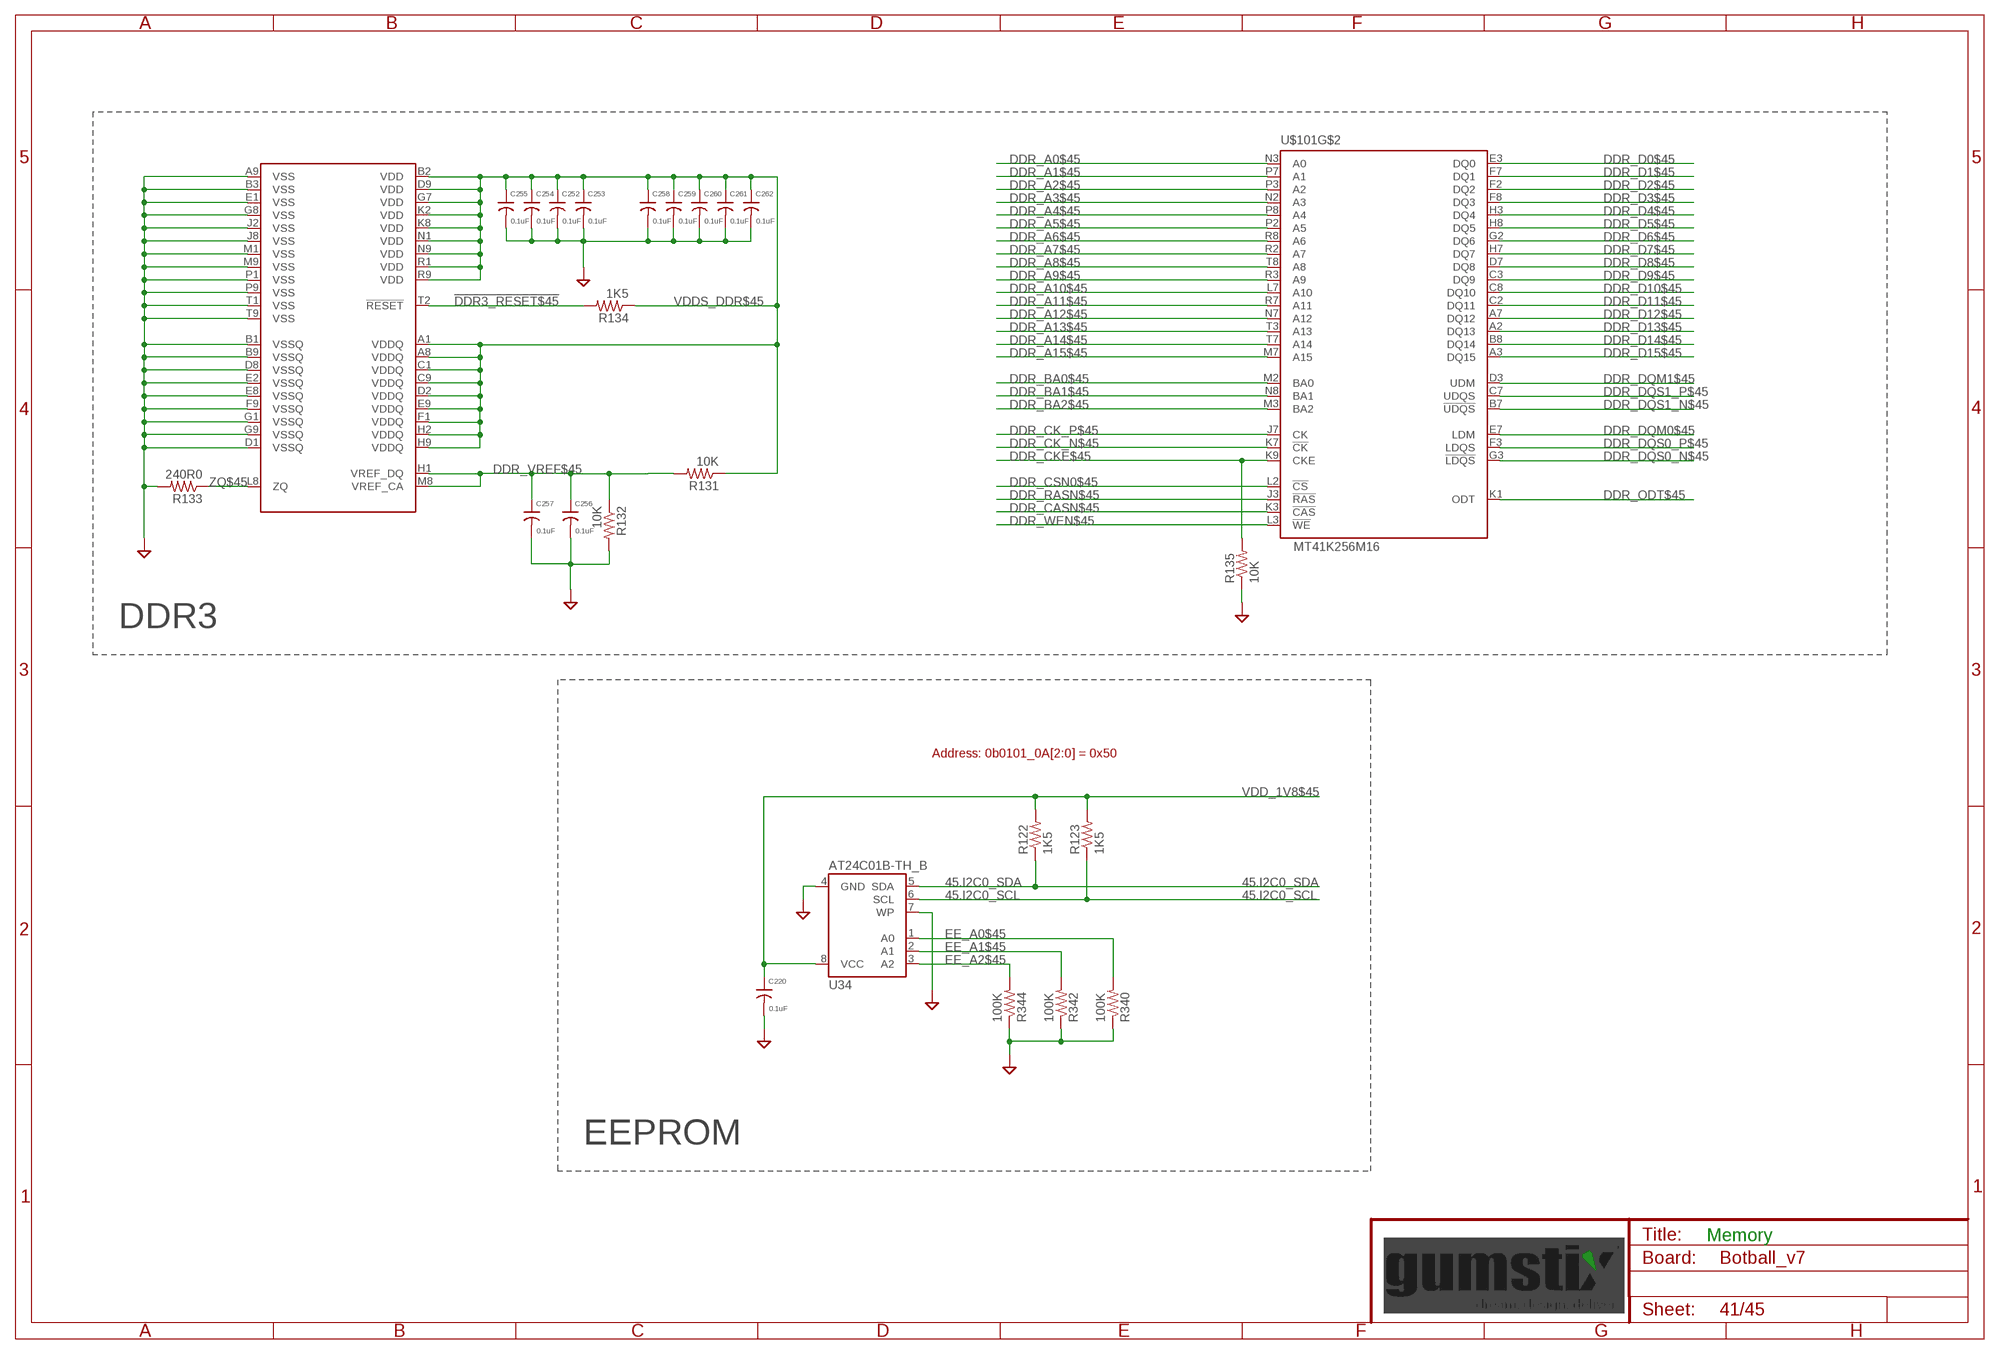
[diagram p40: schematic, sheet 41]
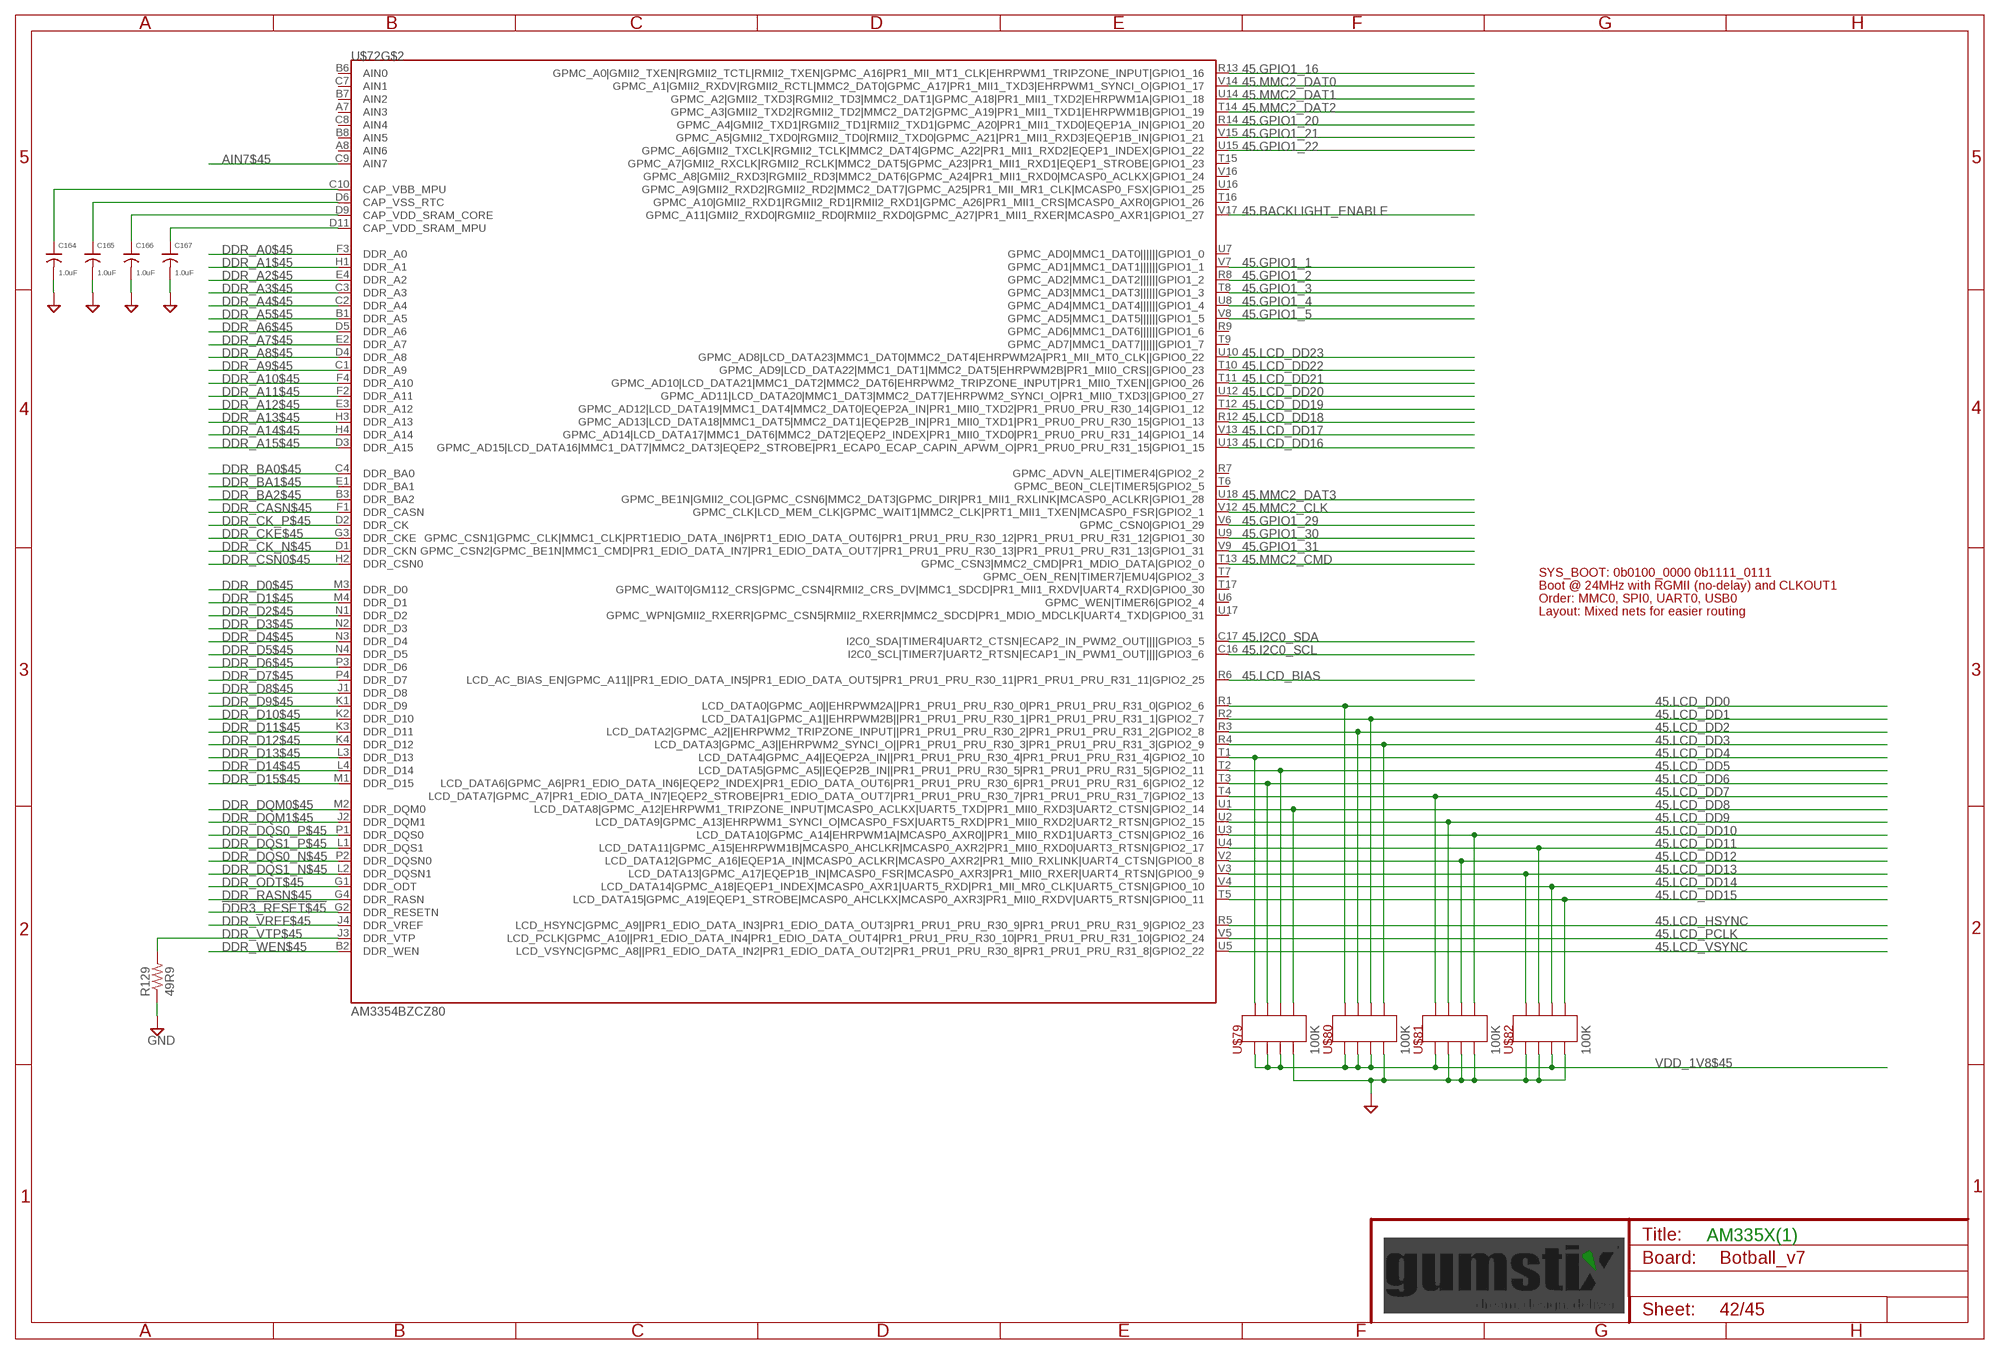
[diagram p41: schematic, sheet 42]
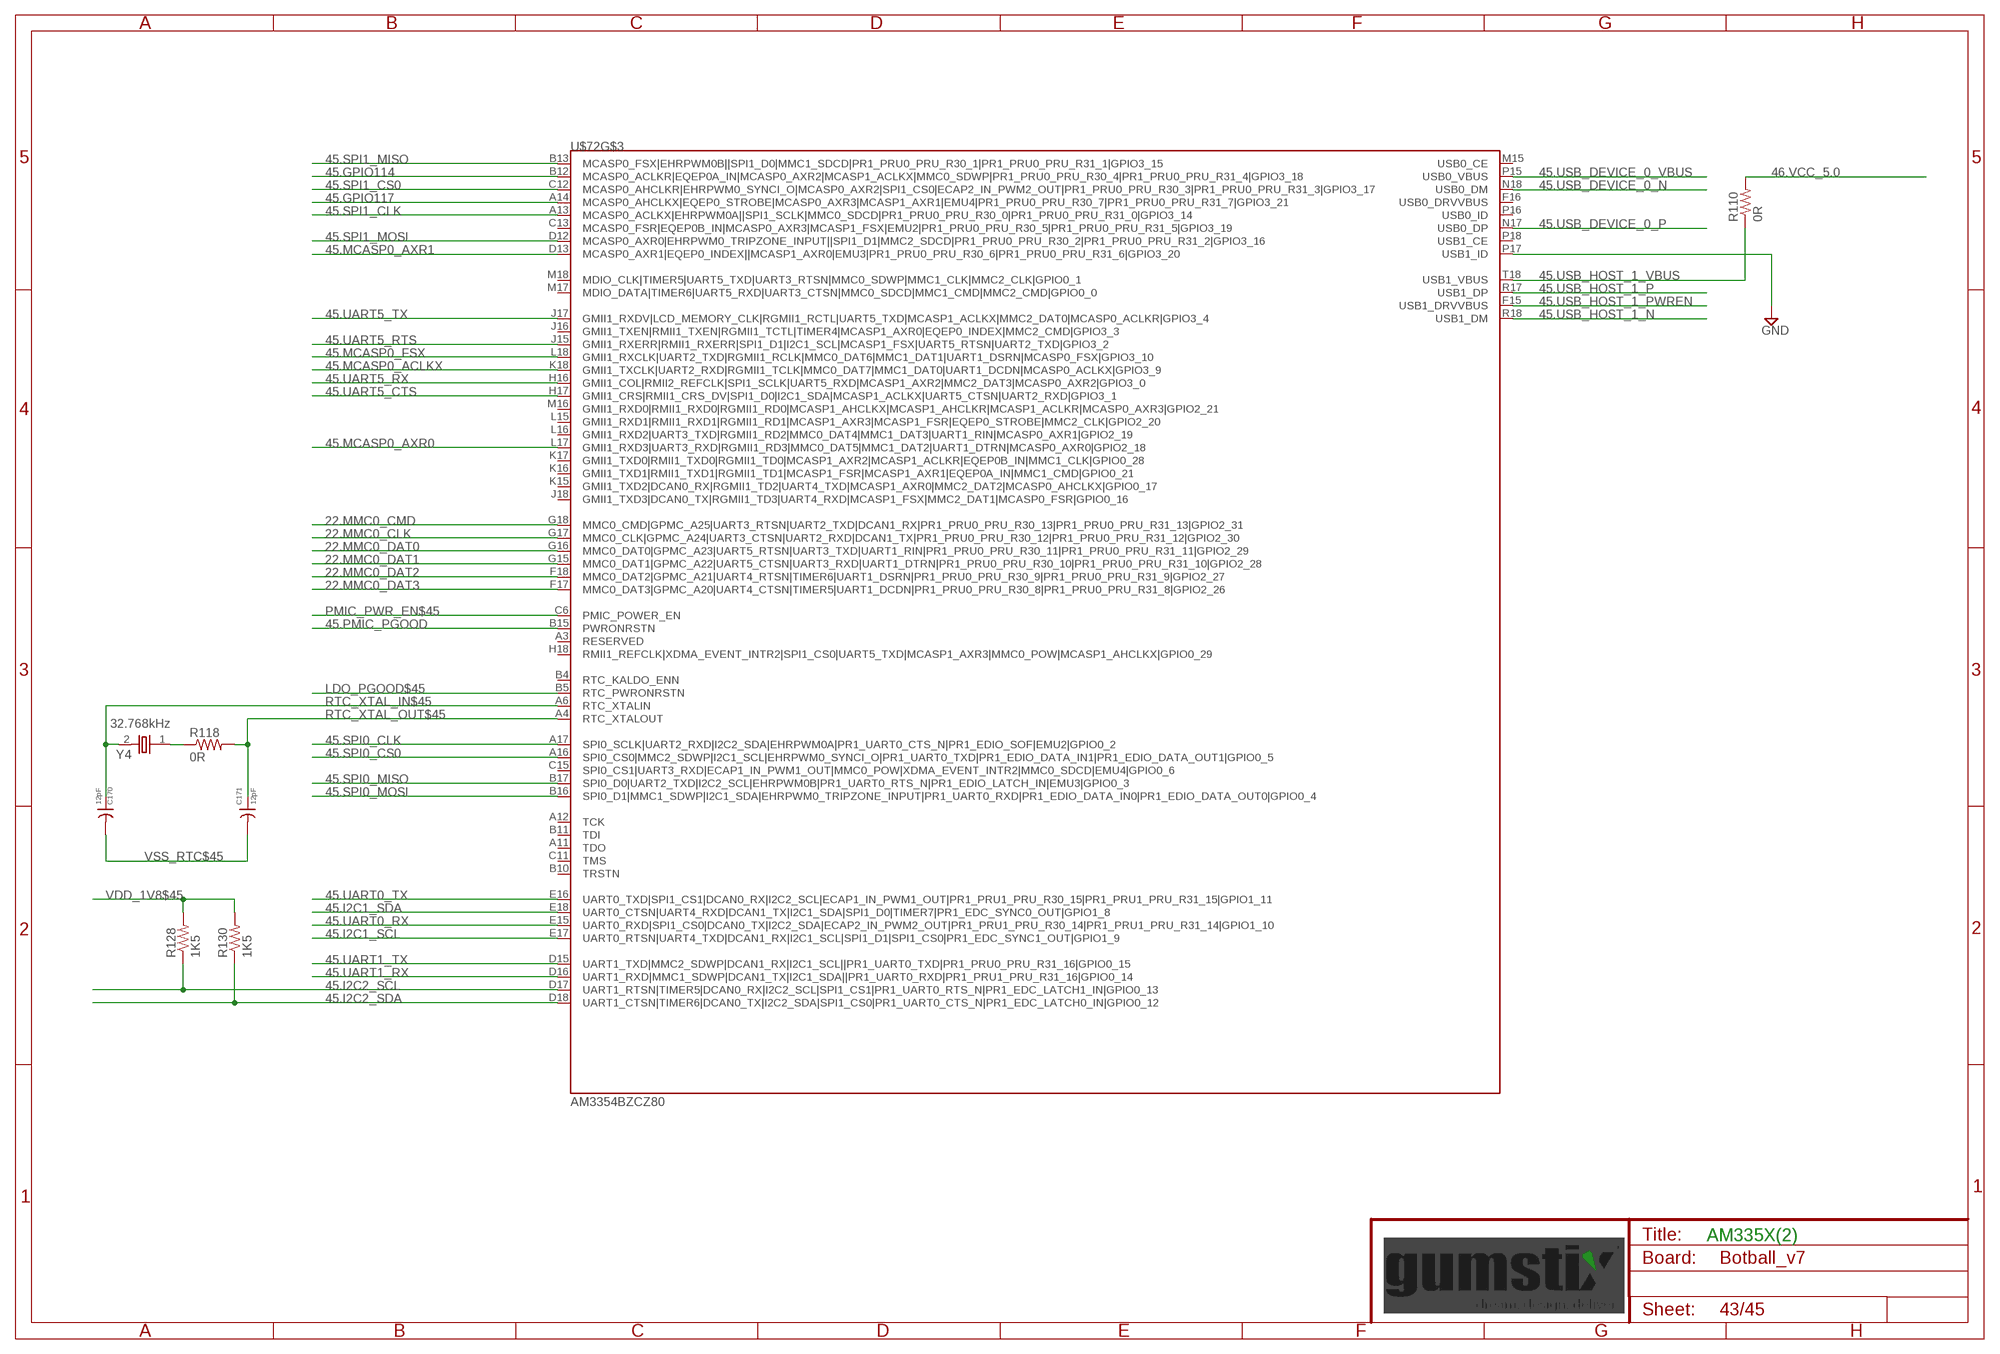
[diagram p42: schematic, sheet 43]
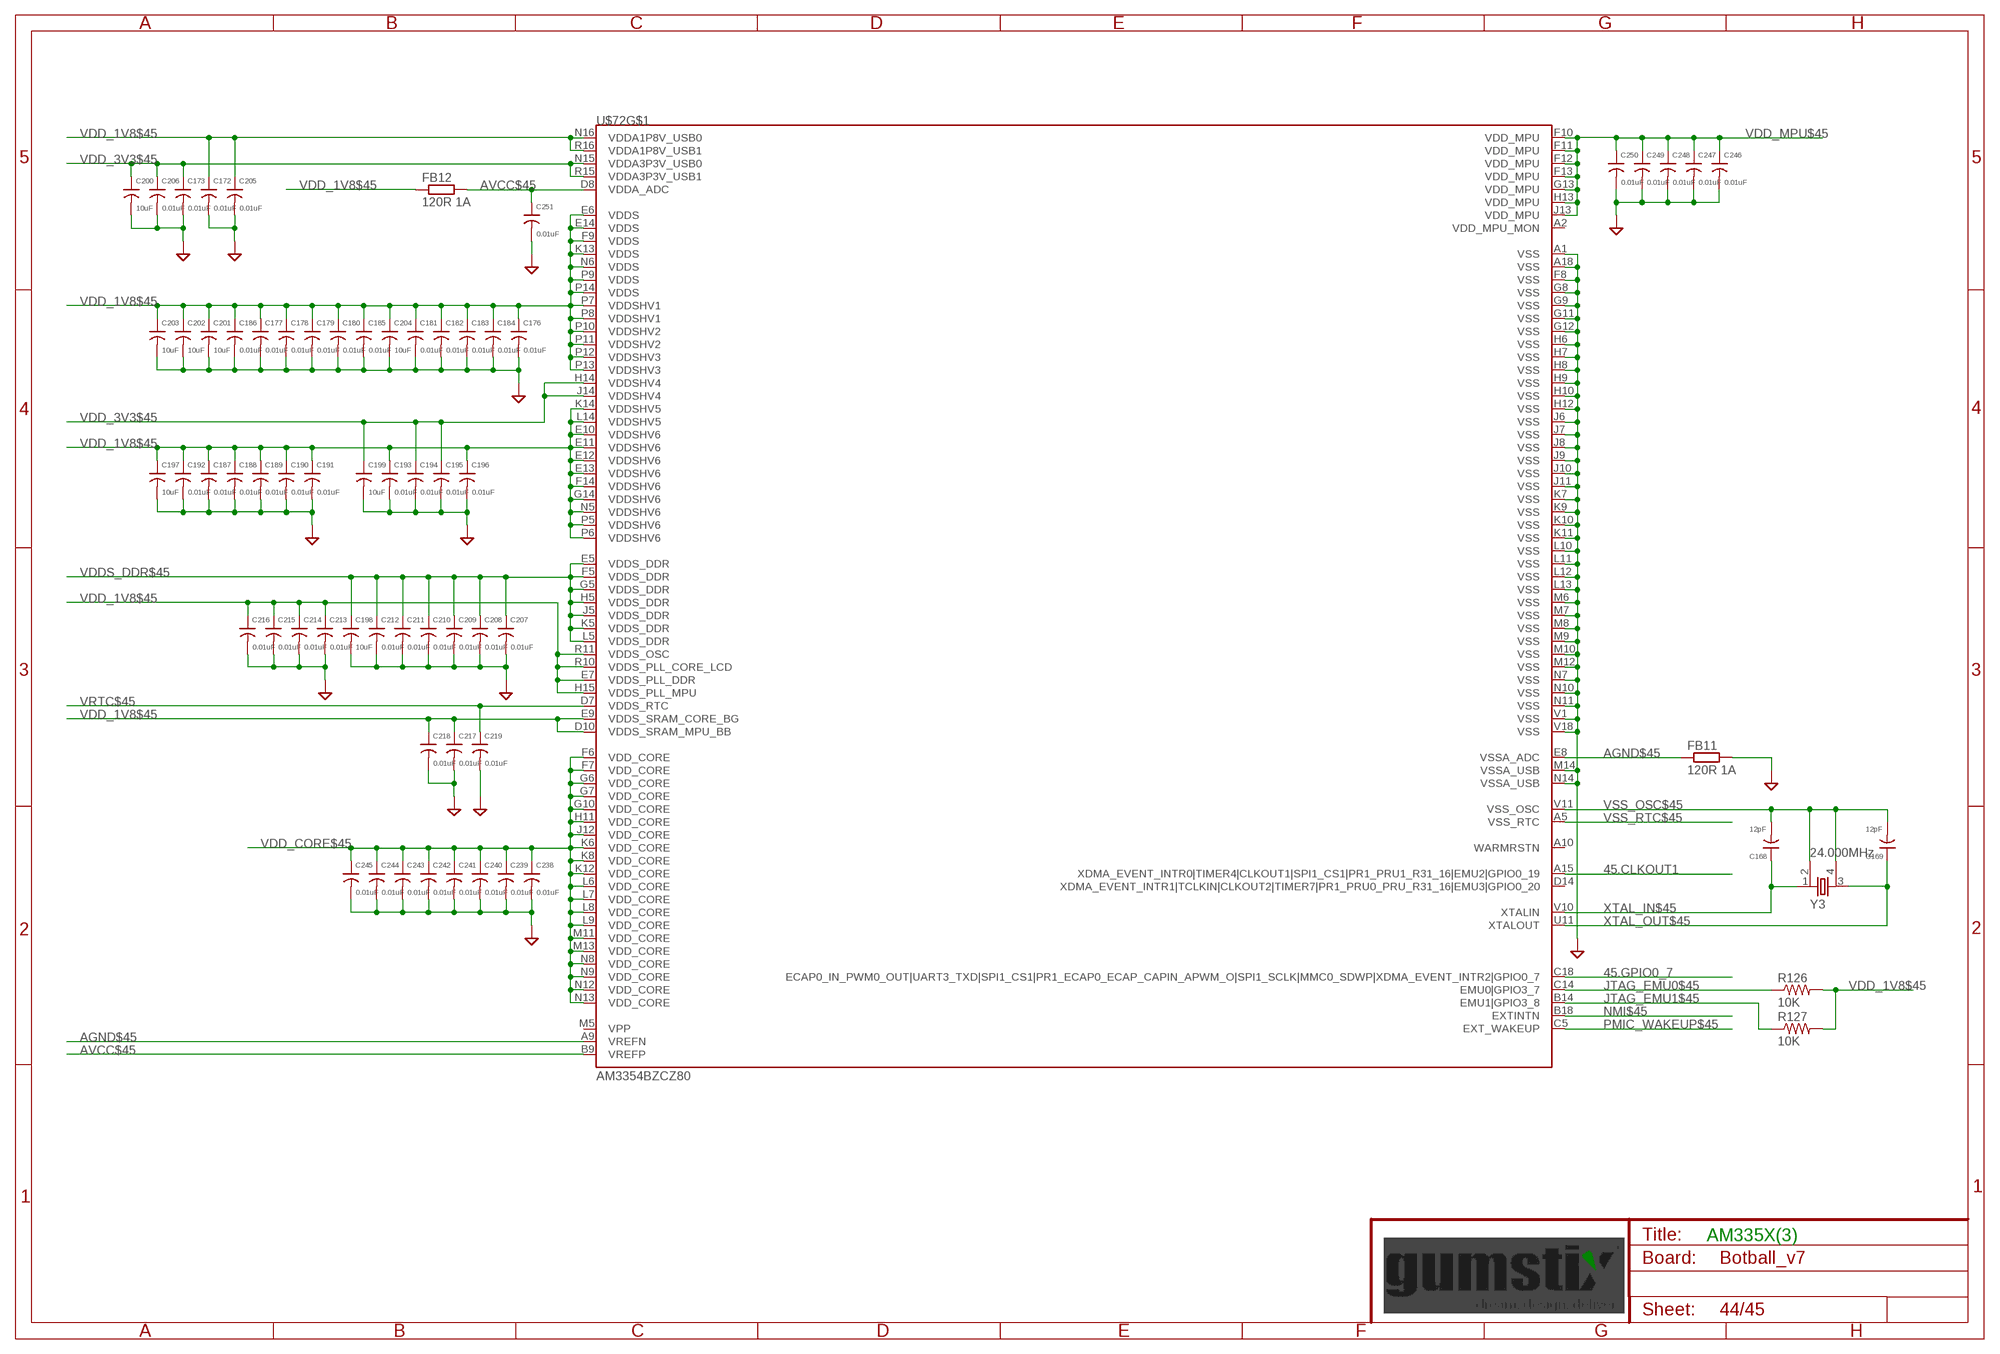
[diagram p43: schematic, sheet 44]
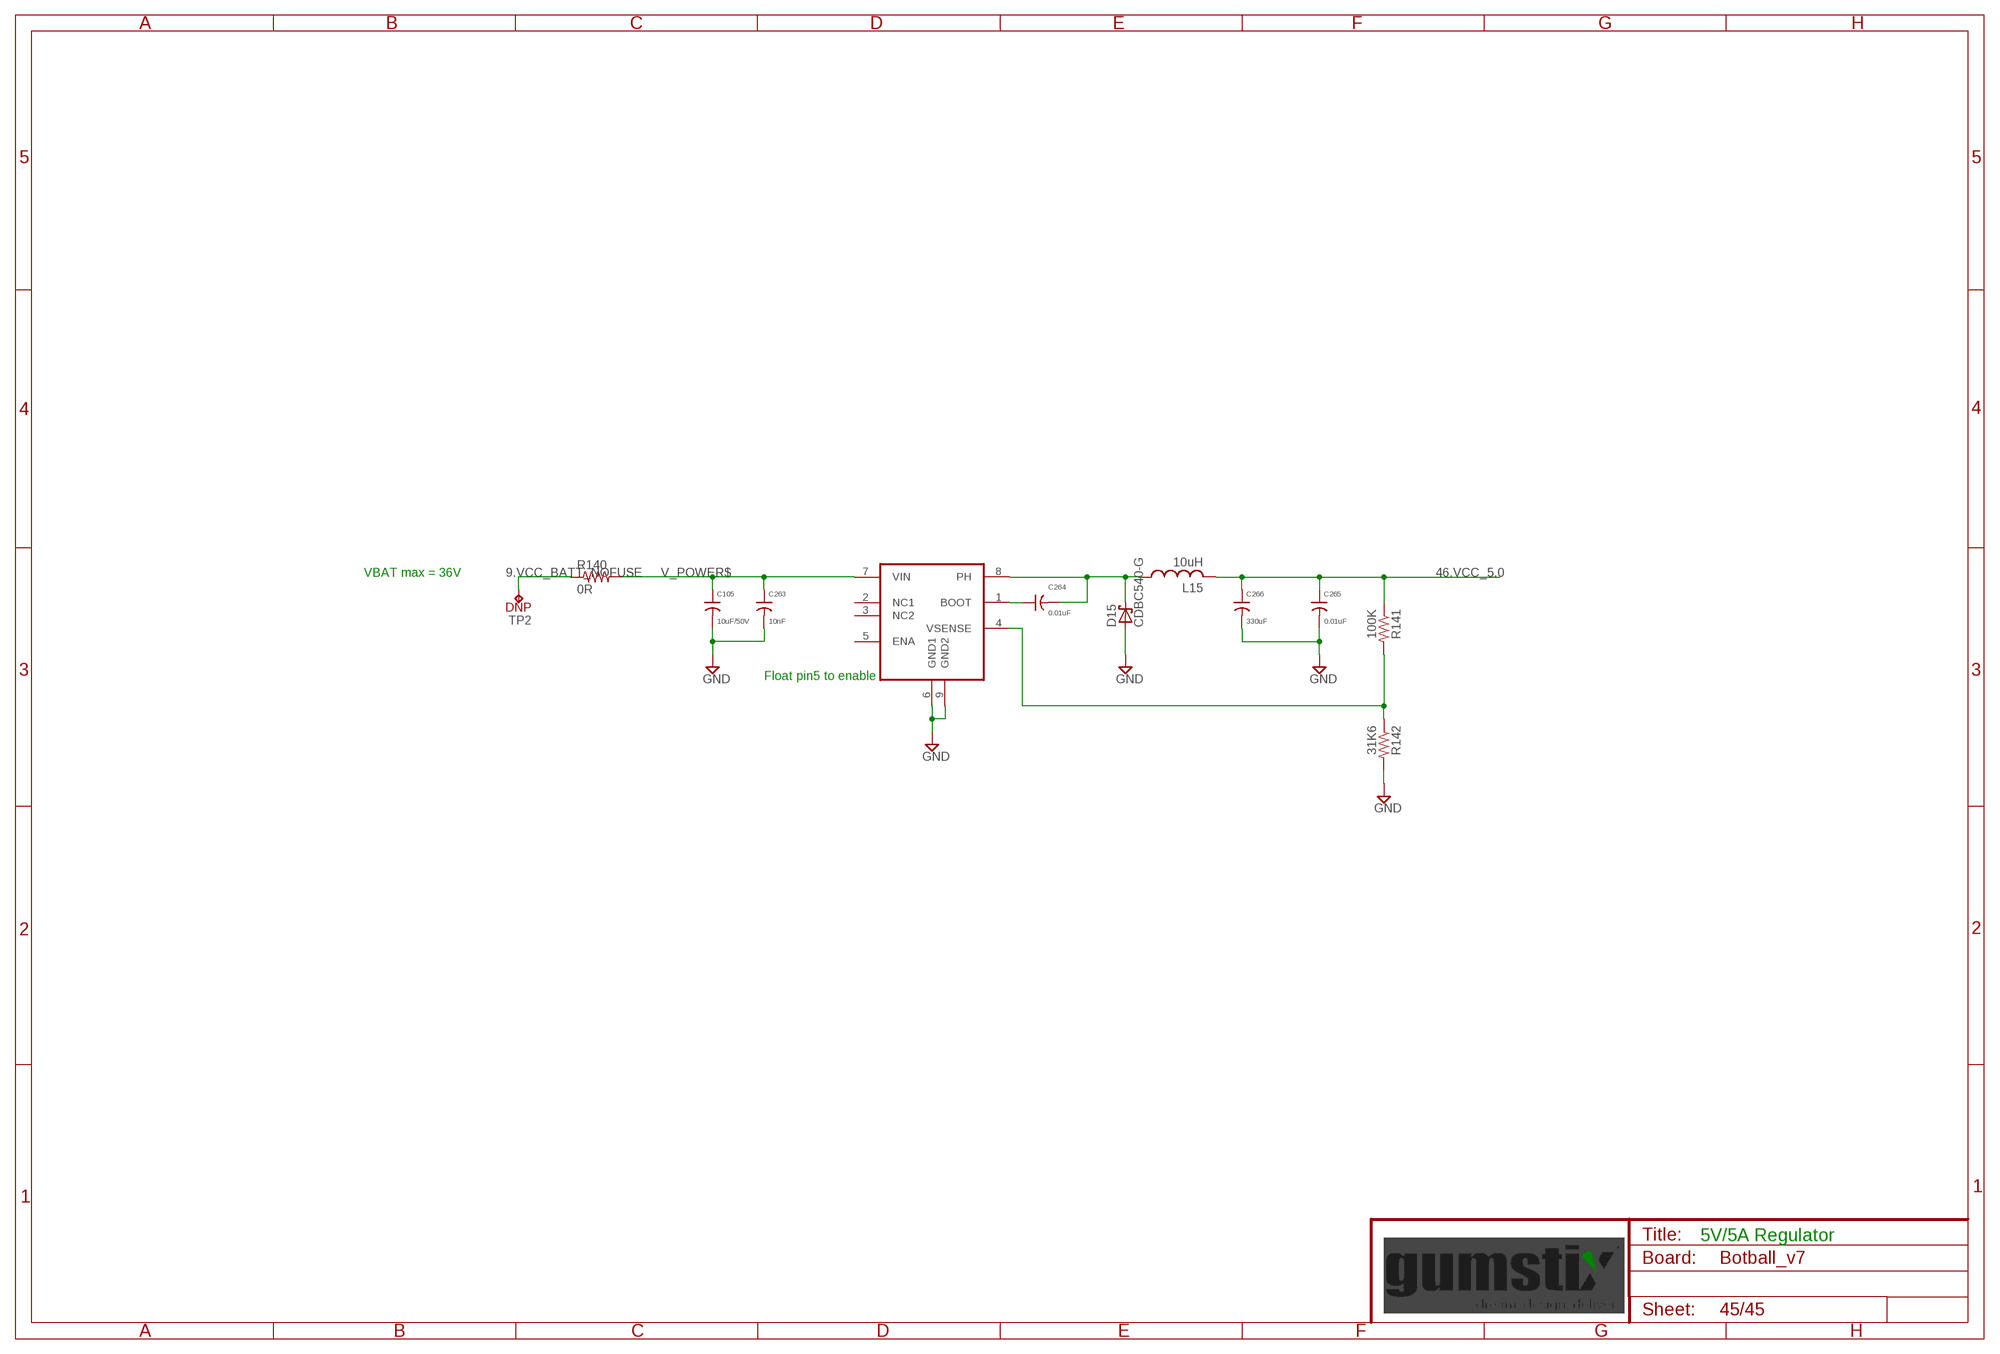
[diagram p44: schematic, sheet 45]

(export (version "E")
  (design (tool "Eeschema 10.0.6"))
  (components
    (comp (ref "BOOT0")
      (value "DNP")
      (footprint "eagle-import:TP0500")
      (libsource (lib "eagle-import") (part "TP05"))
    )
    (comp (ref "C121")
      (value "22pF")
      (footprint "eagle-import:0402")
      (libsource (lib "eagle-import") (part "C0402"))
    )
    (comp (ref "C122")
      (value "22pF")
      (footprint "eagle-import:0402")
      (libsource (lib "eagle-import") (part "C0402"))
    )
    (comp (ref "C123")
      (value "0.1uF")
      (footprint "eagle-import:0201")
      (libsource (lib "eagle-import") (part "C0201"))
    )
    (comp (ref "C124")
      (value "4.7uF")
      (footprint "eagle-import:0603")
      (libsource (lib "eagle-import") (part "C0603"))
    )
    (comp (ref "C125")
      (value "0.1uF")
      (footprint "eagle-import:0201")
      (libsource (lib "eagle-import") (part "C0201"))
    )
    (comp (ref "C126")
      (value "0.1uF")
      (footprint "eagle-import:0201")
      (libsource (lib "eagle-import") (part "C0201"))
    )
    (comp (ref "C127")
      (value "0.1uF")
      (footprint "eagle-import:0201")
      (libsource (lib "eagle-import") (part "C0201"))
    )
    (comp (ref "C128")
      (value "0.1uF")
      (footprint "eagle-import:0201")
      (libsource (lib "eagle-import") (part "C0201"))
    )
    (comp (ref "C129")
      (value "0.1uF")
      (footprint "eagle-import:0201")
      (libsource (lib "eagle-import") (part "C0201"))
    )
    (comp (ref "C130")
      (value "0.1uF")
      (footprint "eagle-import:0201")
      (libsource (lib "eagle-import") (part "C0201"))
    )
    (comp (ref "C131")
      (value "1.0uF")
      (footprint "eagle-import:0402")
      (libsource (lib "eagle-import") (part "C0402"))
    )
    (comp (ref "C132")
      (value "0.01uF")
      (footprint "eagle-import:0201")
      (libsource (lib "eagle-import") (part "C0201"))
    )
    (comp (ref "C133")
      (value "1.0uF")
      (footprint "eagle-import:0402")
      (libsource (lib "eagle-import") (part "C0402"))
    )
    (comp (ref "C134")
      (value "0.01uF")
      (footprint "eagle-import:0201")
      (libsource (lib "eagle-import") (part "C0201"))
    )
    (comp (ref "C135")
      (value "2.2uF")
      (footprint "eagle-import:0603")
      (libsource (lib "eagle-import") (part "C0603"))
    )
    (comp (ref "C136")
      (value "2.2uF")
      (footprint "eagle-import:0603")
      (libsource (lib "eagle-import") (part "C0603"))
    )
    (comp (ref "C137")
      (value "4.7uF")
      (footprint "eagle-import:0603")
      (libsource (lib "eagle-import") (part "C0603"))
    )
    (comp (ref "C138")
      (value "0.1uF")
      (footprint "eagle-import:0201")
      (libsource (lib "eagle-import") (part "C0201"))
    )
    (comp (ref "FB9")
      (value "120R 1A")
      (footprint "eagle-import:0402")
      (libsource (lib "eagle-import") (part "FB0402"))
    )
    (comp (ref "IC3")
      (value "STM32F10XVXT6-FLASH")
      (footprint "eagle-import:TQFP100")
      (libsource (lib "eagle-import") (part "STM32F10XVXT6"))
    )
    (comp (ref "JTAG")
      (value "DNP")
      (footprint "eagle-import:1365-10")
      (libsource (lib "eagle-import") (part "1365-10"))
    )
    (comp (ref "R63")
      (value "DNP")
      (footprint "eagle-import:0603")
      (libsource (lib "eagle-import") (part "R0603"))
    )
    (comp (ref "R83")
      (value "240R0")
      (footprint "eagle-import:0201")
      (libsource (lib "eagle-import") (part "R0201"))
    )
    (comp (ref "R84")
      (value "33R0")
      (footprint "eagle-import:0201")
      (libsource (lib "eagle-import") (part "R0201"))
    )
    (comp (ref "R85")
      (value "100K")
      (footprint "eagle-import:0402")
      (libsource (lib "eagle-import") (part "R0402"))
    )
    (comp (ref "R86")
      (value "10K")
      (footprint "eagle-import:0201")
      (libsource (lib "eagle-import") (part "R0201"))
    )
    (comp (ref "R87")
      (value "0R")
      (footprint "eagle-import:0201")
      (libsource (lib "eagle-import") (part "R0201"))
    )
    (comp (ref "R88")
      (value "100K")
      (footprint "eagle-import:0201")
      (libsource (lib "eagle-import") (part "R0201"))
    )
    (comp (ref "R89")
      (value "10K")
      (footprint "eagle-import:0201")
      (libsource (lib "eagle-import") (part "R0201"))
    )
    (comp (ref "R90")
      (value "0R")
      (footprint "eagle-import:0201")
      (libsource (lib "eagle-import") (part "R0201"))
    )
    (comp (ref "R91")
      (value "10K")
      (footprint "eagle-import:0201")
      (libsource (lib "eagle-import") (part "R0201"))
    )
    (comp (ref "R92")
      (value "100K")
      (footprint "eagle-import:0201")
      (libsource (lib "eagle-import") (part "R0201"))
    )
    (comp (ref "R111")
      (value "DNP")
      (footprint "eagle-import:0603")
      (libsource (lib "eagle-import") (part "R0603"))
    )
    (comp (ref "R136")
      (value "DNP")
      (footprint "eagle-import:0603")
      (libsource (lib "eagle-import") (part "R0603"))
    )
    (comp (ref "R137")
      (value "DNP")
      (footprint "eagle-import:0603")
      (libsource (lib "eagle-import") (part "R0603"))
    )
    (comp (ref "U31")
      (value "EVQKMT0")
      (footprint "eagle-import:KMT0")
      (libsource (lib "eagle-import") (part "EVQKMT0"))
    )
    (comp (ref "VCC1")
      (value "DNP")
      (footprint "eagle-import:TP0500")
      (libsource (lib "eagle-import") (part "TP05"))
    )
    (comp (ref "Y2")
      (value "24.000MHz")
      (footprint "eagle-import:CRYSTAL-3225")
      (libsource (lib "eagle-import") (part "Y4CRYSTAL-3225"))
    )
    (comp (ref "C1")
      (value "1.0uF")
      (footprint "eagle-import:0402")
      (libsource (lib "eagle-import") (part "C0402"))
    )
    (comp (ref "C2")
      (value "0.1uF")
      (footprint "eagle-import:0201")
      (libsource (lib "eagle-import") (part "C0201"))
    )
    (comp (ref "C3")
      (value "0.1uF")
      (footprint "eagle-import:0201")
      (libsource (lib "eagle-import") (part "C0201"))
    )
    (comp (ref "J1")
      (value "DNP")
      (footprint "eagle-import:MA03-100")
      (libsource (lib "eagle-import") (part "MA03X1100"))
    )
    (comp (ref "U1")
      (value "TXS0102")
      (footprint "eagle-import:DFN8-0.4P")
      (libsource (lib "eagle-import") (part "TXS0102"))
    )
    (comp (ref "C139")
      (value "0.1uF")
      (footprint "eagle-import:0201")
      (libsource (lib "eagle-import") (part "C0201"))
    )
    (comp (ref "C140")
      (value "0.1uF")
      (footprint "eagle-import:0201")
      (libsource (lib "eagle-import") (part "C0201"))
    )
    (comp (ref "C141")
      (value "1.0uF")
      (footprint "eagle-import:0201")
      (libsource (lib "eagle-import") (part "C0201"))
    )
    (comp (ref "R93")
      (value "DNP")
      (footprint "eagle-import:0201")
      (libsource (lib "eagle-import") (part "R0201"))
    )
    (comp (ref "R94")
      (value "DNP")
      (footprint "eagle-import:0201")
      (libsource (lib "eagle-import") (part "R0201"))
    )
    (comp (ref "U32")
      (value "TXS0102")
      (footprint "eagle-import:DFN8-0.4P")
      (libsource (lib "eagle-import") (part "TXS0102"))
    )
    (comp (ref "C168")
      (value "12pF")
      (footprint "eagle-import:0201")
      (libsource (lib "eagle-import") (part "C0201"))
    )
    (comp (ref "C169")
      (value "12pF")
      (footprint "eagle-import:0201")
      (libsource (lib "eagle-import") (part "C0201"))
    )
    (comp (ref "C172")
      (value "0.01uF")
      (footprint "eagle-import:0201")
      (libsource (lib "eagle-import") (part "C0201"))
    )
    (comp (ref "C173")
      (value "0.01uF")
      (footprint "eagle-import:0201")
      (libsource (lib "eagle-import") (part "C0201"))
    )
    (comp (ref "C176")
      (value "0.01uF")
      (footprint "eagle-import:0201")
      (libsource (lib "eagle-import") (part "C0201"))
    )
    (comp (ref "C177")
      (value "0.01uF")
      (footprint "eagle-import:0201")
      (libsource (lib "eagle-import") (part "C0201"))
    )
    (comp (ref "C178")
      (value "0.01uF")
      (footprint "eagle-import:0201")
      (libsource (lib "eagle-import") (part "C0201"))
    )
    (comp (ref "C179")
      (value "0.01uF")
      (footprint "eagle-import:0201")
      (libsource (lib "eagle-import") (part "C0201"))
    )
    (comp (ref "C180")
      (value "0.01uF")
      (footprint "eagle-import:0201")
      (libsource (lib "eagle-import") (part "C0201"))
    )
    (comp (ref "C181")
      (value "0.01uF")
      (footprint "eagle-import:0201")
      (libsource (lib "eagle-import") (part "C0201"))
    )
    (comp (ref "C182")
      (value "0.01uF")
      (footprint "eagle-import:0201")
      (libsource (lib "eagle-import") (part "C0201"))
    )
    (comp (ref "C183")
      (value "0.01uF")
      (footprint "eagle-import:0201")
      (libsource (lib "eagle-import") (part "C0201"))
    )
    (comp (ref "C184")
      (value "0.01uF")
      (footprint "eagle-import:0201")
      (libsource (lib "eagle-import") (part "C0201"))
    )
    (comp (ref "C185")
      (value "0.01uF")
      (footprint "eagle-import:0201")
      (libsource (lib "eagle-import") (part "C0201"))
    )
    (comp (ref "C186")
      (value "0.01uF")
      (footprint "eagle-import:0201")
      (libsource (lib "eagle-import") (part "C0201"))
    )
    (comp (ref "C187")
      (value "0.01uF")
      (footprint "eagle-import:0201")
      (libsource (lib "eagle-import") (part "C0201"))
    )
    (comp (ref "C188")
      (value "0.01uF")
      (footprint "eagle-import:0201")
      (libsource (lib "eagle-import") (part "C0201"))
    )
    (comp (ref "C189")
      (value "0.01uF")
      (footprint "eagle-import:0201")
      (libsource (lib "eagle-import") (part "C0201"))
    )
    (comp (ref "C190")
      (value "0.01uF")
      (footprint "eagle-import:0201")
      (libsource (lib "eagle-import") (part "C0201"))
    )
    (comp (ref "C191")
      (value "0.01uF")
      (footprint "eagle-import:0201")
      (libsource (lib "eagle-import") (part "C0201"))
    )
    (comp (ref "C192")
      (value "0.01uF")
      (footprint "eagle-import:0201")
      (libsource (lib "eagle-import") (part "C0201"))
    )
    (comp (ref "C193")
      (value "0.01uF")
      (footprint "eagle-import:0201")
      (libsource (lib "eagle-import") (part "C0201"))
    )
    (comp (ref "C194")
      (value "0.01uF")
      (footprint "eagle-import:0201")
      (libsource (lib "eagle-import") (part "C0201"))
    )
    (comp (ref "C195")
      (value "0.01uF")
      (footprint "eagle-import:0201")
      (libsource (lib "eagle-import") (part "C0201"))
    )
    (comp (ref "C196")
      (value "0.01uF")
      (footprint "eagle-import:0201")
      (libsource (lib "eagle-import") (part "C0201"))
    )
    (comp (ref "C197")
      (value "10uF")
      (footprint "eagle-import:0603")
      (libsource (lib "eagle-import") (part "C0603"))
    )
    (comp (ref "C198")
      (value "10uF")
      (footprint "eagle-import:0603")
      (libsource (lib "eagle-import") (part "C0603"))
    )
    (comp (ref "C199")
      (value "10uF")
      (footprint "eagle-import:0603")
      (libsource (lib "eagle-import") (part "C0603"))
    )
    (comp (ref "C200")
      (value "10uF")
      (footprint "eagle-import:0603")
      (libsource (lib "eagle-import") (part "C0603"))
    )
    (comp (ref "C201")
      (value "10uF")
      (footprint "eagle-import:0603")
      (libsource (lib "eagle-import") (part "C0603"))
    )
    (comp (ref "C202")
      (value "10uF")
      (footprint "eagle-import:0603")
      (libsource (lib "eagle-import") (part "C0603"))
    )
    (comp (ref "C203")
      (value "10uF")
      (footprint "eagle-import:0603")
      (libsource (lib "eagle-import") (part "C0603"))
    )
    (comp (ref "C204")
      (value "10uF")
      (footprint "eagle-import:0603")
      (libsource (lib "eagle-import") (part "C0603"))
    )
    (comp (ref "C205")
      (value "0.01uF")
      (footprint "eagle-import:0201")
      (libsource (lib "eagle-import") (part "C0201"))
    )
    (comp (ref "C206")
      (value "0.01uF")
      (footprint "eagle-import:0201")
      (libsource (lib "eagle-import") (part "C0201"))
    )
    (comp (ref "C207")
      (value "0.01uF")
      (footprint "eagle-import:0201")
      (libsource (lib "eagle-import") (part "C0201"))
    )
    (comp (ref "C208")
      (value "0.01uF")
      (footprint "eagle-import:0201")
      (libsource (lib "eagle-import") (part "C0201"))
    )
    (comp (ref "C209")
      (value "0.01uF")
      (footprint "eagle-import:0201")
      (libsource (lib "eagle-import") (part "C0201"))
    )
    (comp (ref "C210")
      (value "0.01uF")
      (footprint "eagle-import:0201")
      (libsource (lib "eagle-import") (part "C0201"))
    )
    (comp (ref "C211")
      (value "0.01uF")
      (footprint "eagle-import:0201")
      (libsource (lib "eagle-import") (part "C0201"))
    )
    (comp (ref "C212")
      (value "0.01uF")
      (footprint "eagle-import:0201")
      (libsource (lib "eagle-import") (part "C0201"))
    )
    (comp (ref "C213")
      (value "0.01uF")
      (footprint "eagle-import:0201")
      (libsource (lib "eagle-import") (part "C0201"))
    )
    (comp (ref "C214")
      (value "0.01uF")
      (footprint "eagle-import:0201")
      (libsource (lib "eagle-import") (part "C0201"))
    )
    (comp (ref "C215")
      (value "0.01uF")
      (footprint "eagle-import:0201")
      (libsource (lib "eagle-import") (part "C0201"))
    )
    (comp (ref "C216")
      (value "0.01uF")
      (footprint "eagle-import:0201")
      (libsource (lib "eagle-import") (part "C0201"))
    )
    (comp (ref "C217")
      (value "0.01uF")
      (footprint "eagle-import:0201")
      (libsource (lib "eagle-import") (part "C0201"))
    )
    (comp (ref "C218")
      (value "0.01uF")
      (footprint "eagle-import:0201")
      (libsource (lib "eagle-import") (part "C0201"))
    )
    (comp (ref "C219")
      (value "0.01uF")
      (footprint "eagle-import:0201")
      (libsource (lib "eagle-import") (part "C0201"))
    )
    (comp (ref "C238")
      (value "0.01uF")
      (footprint "eagle-import:0201")
      (libsource (lib "eagle-import") (part "C0201"))
    )
    (comp (ref "C239")
      (value "0.01uF")
      (footprint "eagle-import:0201")
      (libsource (lib "eagle-import") (part "C0201"))
    )
    (comp (ref "C240")
      (value "0.01uF")
      (footprint "eagle-import:0201")
      (libsource (lib "eagle-import") (part "C0201"))
    )
    (comp (ref "C241")
      (value "0.01uF")
      (footprint "eagle-import:0201")
      (libsource (lib "eagle-import") (part "C0201"))
    )
    (comp (ref "C242")
      (value "0.01uF")
      (footprint "eagle-import:0201")
      (libsource (lib "eagle-import") (part "C0201"))
    )
    (comp (ref "C243")
      (value "0.01uF")
      (footprint "eagle-import:0201")
      (libsource (lib "eagle-import") (part "C0201"))
    )
    (comp (ref "C244")
      (value "0.01uF")
      (footprint "eagle-import:0201")
      (libsource (lib "eagle-import") (part "C0201"))
    )
    (comp (ref "C245")
      (value "0.01uF")
      (footprint "eagle-import:0201")
      (libsource (lib "eagle-import") (part "C0201"))
    )
    (comp (ref "C246")
      (value "0.01uF")
      (footprint "eagle-import:0201")
      (libsource (lib "eagle-import") (part "C0201"))
    )
    (comp (ref "C247")
      (value "0.01uF")
      (footprint "eagle-import:0201")
      (libsource (lib "eagle-import") (part "C0201"))
    )
    (comp (ref "C248")
      (value "0.01uF")
      (footprint "eagle-import:0201")
      (libsource (lib "eagle-import") (part "C0201"))
    )
    (comp (ref "C249")
      (value "0.01uF")
      (footprint "eagle-import:0201")
      (libsource (lib "eagle-import") (part "C0201"))
    )
    (comp (ref "C250")
      (value "0.01uF")
      (footprint "eagle-import:0201")
      (libsource (lib "eagle-import") (part "C0201"))
    )
    (comp (ref "C251")
      (value "0.01uF")
      (footprint "eagle-import:0201")
      (libsource (lib "eagle-import") (part "C0201"))
    )
    (comp (ref "FB11")
      (value "120R 1A")
      (footprint "eagle-import:0402")
      (libsource (lib "eagle-import") (part "FB0402"))
    )
    (comp (ref "FB12")
      (value "120R 1A")
      (footprint "eagle-import:0402")
      (libsource (lib "eagle-import") (part "FB0402"))
    )
    (comp (ref "R126")
      (value "10K")
      (footprint "eagle-import:0201")
      (libsource (lib "eagle-import") (part "R0201"))
    )
    (comp (ref "R127")
      (value "10K")
      (footprint "eagle-import:0201")
      (libsource (lib "eagle-import") (part "R0201"))
    )
    (comp (ref "U$72")
      (value "AM3354BZCZ80")
      (footprint "eagle-import:BGA324C80P18X18")
      (libsource (lib "eagle-import") (part "AM335_ZCZ"))
    )
    (comp (ref "Y3")
      (value "24.000MHz")
      (footprint "eagle-import:CRYSTAL-3225")
      (libsource (lib "eagle-import") (part "Y4CRYSTAL-3225"))
    )
    (comp (ref "J3")
      (value "ML-621S/ZTN")
      (footprint "eagle-import:BATTERY_6.8MM-2998")
      (libsource (lib "eagle-import") (part "COIN_CELL_6.8MM"))
    )
    (comp (ref "R3")
      (value "10K")
      (footprint "eagle-import:0201")
      (libsource (lib "eagle-import") (part "R0201"))
    )
    (comp (ref "U3")
      (value "DS1340")
      (footprint "eagle-import:SO-8")
      (libsource (lib "eagle-import") (part "DS1339"))
    )
    (comp (ref "X1")
      (value "32.768")
      (footprint "eagle-import:CM415")
      (libsource (lib "eagle-import") (part "X2CM415"))
    )
    (comp (ref "C33")
      (value "1.0uF")
      (footprint "eagle-import:0402")
      (libsource (lib "eagle-import") (part "C0402"))
    )
    (comp (ref "C34")
      (value "0.1uF")
      (footprint "eagle-import:0201")
      (libsource (lib "eagle-import") (part "C0201"))
    )
    (comp (ref "C35")
      (value "1.0uF")
      (footprint "eagle-import:0402")
      (libsource (lib "eagle-import") (part "C0402"))
    )
    (comp (ref "C36")
      (value "0.1uF")
      (footprint "eagle-import:0201")
      (libsource (lib "eagle-import") (part "C0201"))
    )
    (comp (ref "C37")
      (value "1.0uF")
      (footprint "eagle-import:0402")
      (libsource (lib "eagle-import") (part "C0402"))
    )
    (comp (ref "C38")
      (value "0.1uF")
      (footprint "eagle-import:0201")
      (libsource (lib "eagle-import") (part "C0201"))
    )
    (comp (ref "C39")
      (value "10uF")
      (footprint "eagle-import:0603")
      (libsource (lib "eagle-import") (part "C0603"))
    )
    (comp (ref "C40")
      (value "1.0uF")
      (footprint "eagle-import:0402")
      (libsource (lib "eagle-import") (part "C0402"))
    )
    (comp (ref "C41")
      (value "0.1uF")
      (footprint "eagle-import:0201")
      (libsource (lib "eagle-import") (part "C0201"))
    )
    (comp (ref "C42")
      (value "1.0uF")
      (footprint "eagle-import:0402")
      (libsource (lib "eagle-import") (part "C0402"))
    )
    (comp (ref "C51")
      (value "0.1uF")
      (footprint "eagle-import:0201")
      (libsource (lib "eagle-import") (part "C0201"))
    )
    (comp (ref "C52")
      (value "0.47uF")
      (footprint "eagle-import:0402")
      (libsource (lib "eagle-import") (part "C0402"))
    )
    (comp (ref "C53")
      (value "0.47uF")
      (footprint "eagle-import:0402")
      (libsource (lib "eagle-import") (part "C0402"))
    )
    (comp (ref "C54")
      (value "0.47uF")
      (footprint "eagle-import:0402")
      (libsource (lib "eagle-import") (part "C0402"))
    )
    (comp (ref "R26")
      (value "100K")
      (footprint "eagle-import:0201")
      (libsource (lib "eagle-import") (part "R0201"))
    )
    (comp (ref "R27")
      (value "DNP")
      (footprint "eagle-import:0201")
      (libsource (lib "eagle-import") (part "R0201"))
    )
    (comp (ref "R28")
      (value "DNP")
      (footprint "eagle-import:0201")
      (libsource (lib "eagle-import") (part "R0201"))
    )
    (comp (ref "R29")
      (value "100K")
      (footprint "eagle-import:0201")
      (libsource (lib "eagle-import") (part "R0201"))
    )
    (comp (ref "R30")
      (value "100K")
      (footprint "eagle-import:0201")
      (libsource (lib "eagle-import") (part "R0201"))
    )
    (comp (ref "R31")
      (value "100K")
      (footprint "eagle-import:0201")
      (libsource (lib "eagle-import") (part "R0201"))
    )
    (comp (ref "R32")
      (value "1K5")
      (footprint "eagle-import:0201")
      (libsource (lib "eagle-import") (part "R0201"))
    )
    (comp (ref "R34")
      (value "0R")
      (footprint "eagle-import:0201")
      (libsource (lib "eagle-import") (part "R0201"))
    )
    (comp (ref "R35")
      (value "0R")
      (footprint "eagle-import:0201")
      (libsource (lib "eagle-import") (part "R0201"))
    )
    (comp (ref "U15")
      (value "TLV320AIC3106")
      (footprint "eagle-import:QFN48")
      (libsource (lib "eagle-import") (part "TLV320AIC3106"))
    )
    (comp (ref "X2")
      (value "12MHz 1.8V")
      (footprint "eagle-import:ASF")
      (libsource (lib "eagle-import") (part "ASF1"))
    )
    (comp (ref "C170")
      (value "12pF")
      (footprint "eagle-import:0201")
      (libsource (lib "eagle-import") (part "C0201"))
    )
    (comp (ref "C171")
      (value "12pF")
      (footprint "eagle-import:0201")
      (libsource (lib "eagle-import") (part "C0201"))
    )
    (comp (ref "R110")
      (value "0R")
      (footprint "eagle-import:0603")
      (libsource (lib "eagle-import") (part "R0603"))
    )
    (comp (ref "R118")
      (value "0R")
      (footprint "eagle-import:0201")
      (libsource (lib "eagle-import") (part "R0201"))
    )
    (comp (ref "R128")
      (value "1K5")
      (footprint "eagle-import:0201")
      (libsource (lib "eagle-import") (part "R0201"))
    )
    (comp (ref "R130")
      (value "1K5")
      (footprint "eagle-import:0201")
      (libsource (lib "eagle-import") (part "R0201"))
    )
    (comp (ref "Y4")
      (value "32.768kHz")
      (footprint "eagle-import:1206")
      (libsource (lib "eagle-import") (part "X21206"))
    )
    (comp (ref "C118")
      (value "0.1uF")
      (footprint "eagle-import:0201")
      (libsource (lib "eagle-import") (part "C0201"))
    )
    (comp (ref "C119")
      (value "0.1uF")
      (footprint "eagle-import:0201")
      (libsource (lib "eagle-import") (part "C0201"))
    )
    (comp (ref "J12")
      (value "CONN20FEMALE")
      (footprint "eagle-import:057-020-1")
      (libsource (lib "eagle-import") (part "CONN20HEADER"))
    )
    (comp (ref "J13")
      (value "CONN10FEMALE")
      (footprint "eagle-import:057-010-1")
      (libsource (lib "eagle-import") (part "CONN10HEADER"))
    )
    (comp (ref "R78")
      (value "0R")
      (footprint "eagle-import:0201")
      (libsource (lib "eagle-import") (part "R0201"))
    )
    (comp (ref "R79")
      (value "0R")
      (footprint "eagle-import:0603")
      (libsource (lib "eagle-import") (part "R0603"))
    )
    (comp (ref "R80")
      (value "DNP")
      (footprint "eagle-import:0201")
      (libsource (lib "eagle-import") (part "R0201"))
    )
    (comp (ref "R81")
      (value "DNP")
      (footprint "eagle-import:0201")
      (libsource (lib "eagle-import") (part "R0201"))
    )
    (comp (ref "RP7")
      (value "DNP")
      (footprint "eagle-import:741X16")
      (libsource (lib "eagle-import") (part "RP741X163"))
    )
    (comp (ref "U29")
      (value "TXS0108E")
      (footprint "eagle-import:QFN20")
      (libsource (lib "eagle-import") (part "TXS0108E"))
    )
    (comp (ref "U30")
      (value "TXS0102")
      (footprint "eagle-import:DFN8-0.4P")
      (libsource (lib "eagle-import") (part "TXS0102"))
    )
    (comp (ref "C221")
      (value "4.7uF")
      (footprint "eagle-import:0603")
      (libsource (lib "eagle-import") (part "C0603"))
    )
    (comp (ref "C222")
      (value "22uF")
      (footprint "eagle-import:0805")
      (libsource (lib "eagle-import") (part "C0805"))
    )
    (comp (ref "C223")
      (value "0.1uF")
      (footprint "eagle-import:0201")
      (libsource (lib "eagle-import") (part "C0201"))
    )
    (comp (ref "C224")
      (value "10uF")
      (footprint "eagle-import:0603")
      (libsource (lib "eagle-import") (part "C0603"))
    )
    (comp (ref "C225")
      (value "4.7uF")
      (footprint "eagle-import:0603")
      (libsource (lib "eagle-import") (part "C0603"))
    )
    (comp (ref "C226")
      (value "10uF")
      (footprint "eagle-import:0603")
      (libsource (lib "eagle-import") (part "C0603"))
    )
    (comp (ref "C227")
      (value "10uF")
      (footprint "eagle-import:0603")
      (libsource (lib "eagle-import") (part "C0603"))
    )
    (comp (ref "C228")
      (value "10uF")
      (footprint "eagle-import:0603")
      (libsource (lib "eagle-import") (part "C0603"))
    )
    (comp (ref "C229")
      (value "10uF")
      (footprint "eagle-import:0603")
      (libsource (lib "eagle-import") (part "C0603"))
    )
    (comp (ref "C230")
      (value "10uF")
      (footprint "eagle-import:0603")
      (libsource (lib "eagle-import") (part "C0603"))
    )
    (comp (ref "C231")
      (value "10uF")
      (footprint "eagle-import:0603")
      (libsource (lib "eagle-import") (part "C0603"))
    )
    (comp (ref "C232")
      (value "10uF")
      (footprint "eagle-import:0603")
      (libsource (lib "eagle-import") (part "C0603"))
    )
    (comp (ref "C233")
      (value "10uF")
      (footprint "eagle-import:0603")
      (libsource (lib "eagle-import") (part "C0603"))
    )
    (comp (ref "C234")
      (value "4.7uF_50V")
      (footprint "eagle-import:1210")
      (libsource (lib "eagle-import") (part "C1210"))
    )
    (comp (ref "C235")
      (value "4.7uF")
      (footprint "eagle-import:0603")
      (libsource (lib "eagle-import") (part "C0603"))
    )
    (comp (ref "C236")
      (value "2.2uF")
      (footprint "eagle-import:0402")
      (libsource (lib "eagle-import") (part "C0402"))
    )
    (comp (ref "C237")
      (value "2.2uF")
      (footprint "eagle-import:0402")
      (libsource (lib "eagle-import") (part "C0402"))
    )
    (comp (ref "D31")
      (value "MBRA140T3G")
      (footprint "eagle-import:SMAJ")
      (libsource (lib "eagle-import") (part "DSMA"))
    )
    (comp (ref "FB10")
      (value "120R 6.0A")
      (footprint "eagle-import:0805")
      (libsource (lib "eagle-import") (part "FB0805"))
    )
    (comp (ref "L11")
      (value "2.2uH")
      (footprint "eagle-import:1515")
      (libsource (lib "eagle-import") (part "L1515"))
    )
    (comp (ref "L12")
      (value "2.2uH")
      (footprint "eagle-import:1515")
      (libsource (lib "eagle-import") (part "L1515"))
    )
    (comp (ref "L13")
      (value "2.2uH")
      (footprint "eagle-import:1515")
      (libsource (lib "eagle-import") (part "L1515"))
    )
    (comp (ref "L14")
      (value "18uH")
      (footprint "eagle-import:WE-PD2_4532")
      (libsource (lib "eagle-import") (part "WE-PD2_4532"))
    )
    (comp (ref "R119")
      (value "0R")
      (footprint "eagle-import:0201")
      (libsource (lib "eagle-import") (part "R0201"))
    )
    (comp (ref "R120")
      (value "180K")
      (footprint "eagle-import:0201")
      (libsource (lib "eagle-import") (part "R0201"))
    )
    (comp (ref "R121")
      (value "100K")
      (footprint "eagle-import:0201")
      (libsource (lib "eagle-import") (part "R0201"))
    )
    (comp (ref "R124")
      (value "100K")
      (footprint "eagle-import:0201")
      (libsource (lib "eagle-import") (part "R0201"))
    )
    (comp (ref "R125")
      (value "10K")
      (footprint "eagle-import:0201")
      (libsource (lib "eagle-import") (part "R0201"))
    )
    (comp (ref "U35")
      (value "TPS65217D")
      (footprint "eagle-import:QFN40P600X600X100-49")
      (libsource (lib "eagle-import") (part "TPS65217"))
    )
    (comp (ref "C106")
      (value "0.1uF")
      (footprint "eagle-import:0201")
      (libsource (lib "eagle-import") (part "C0201"))
    )
    (comp (ref "C107")
      (value "100uF")
      (footprint "eagle-import:PANASONIC_D")
      (libsource (lib "eagle-import") (part "CPANASONIC_D"))
    )
    (comp (ref "C108")
      (value "10uF / 25V")
      (footprint "eagle-import:1206")
      (libsource (lib "eagle-import") (part "C1206"))
    )
    (comp (ref "C109")
      (value "0.22uF")
      (footprint "eagle-import:0603")
      (libsource (lib "eagle-import") (part "C0603"))
    )
    (comp (ref "C110")
      (value "22pF")
      (footprint "eagle-import:0402")
      (libsource (lib "eagle-import") (part "C0402"))
    )
    (comp (ref "C111")
      (value "22pF")
      (footprint "eagle-import:0402")
      (libsource (lib "eagle-import") (part "C0402"))
    )
    (comp (ref "R64")
      (value "6K8")
      (footprint "eagle-import:0402")
      (libsource (lib "eagle-import") (part "R0402"))
    )
    (comp (ref "R65")
      (value "6K8")
      (footprint "eagle-import:0402")
      (libsource (lib "eagle-import") (part "R0402"))
    )
    (comp (ref "R66")
      (value "2K2")
      (footprint "eagle-import:0402")
      (libsource (lib "eagle-import") (part "R0402"))
    )
    (comp (ref "R67")
      (value "2K2")
      (footprint "eagle-import:0402")
      (libsource (lib "eagle-import") (part "R0402"))
    )
    (comp (ref "R68")
      (value "470R")
      (footprint "eagle-import:0402")
      (libsource (lib "eagle-import") (part "R0402"))
    )
    (comp (ref "R69")
      (value "470R")
      (footprint "eagle-import:0402")
      (libsource (lib "eagle-import") (part "R0402"))
    )
    (comp (ref "R70")
      (value "1K5")
      (footprint "eagle-import:0402")
      (libsource (lib "eagle-import") (part "R0402"))
    )
    (comp (ref "R71")
      (value "6K8")
      (footprint "eagle-import:0402")
      (libsource (lib "eagle-import") (part "R0402"))
    )
    (comp (ref "R72")
      (value "6K8")
      (footprint "eagle-import:0402")
      (libsource (lib "eagle-import") (part "R0402"))
    )
    (comp (ref "R73")
      (value "2K2")
      (footprint "eagle-import:0402")
      (libsource (lib "eagle-import") (part "R0402"))
    )
    (comp (ref "R74")
      (value "2K2")
      (footprint "eagle-import:0402")
      (libsource (lib "eagle-import") (part "R0402"))
    )
    (comp (ref "R75")
      (value "470R")
      (footprint "eagle-import:0402")
      (libsource (lib "eagle-import") (part "R0402"))
    )
    (comp (ref "R76")
      (value "470R")
      (footprint "eagle-import:0402")
      (libsource (lib "eagle-import") (part "R0402"))
    )
    (comp (ref "R77")
      (value "1K5")
      (footprint "eagle-import:0402")
      (libsource (lib "eagle-import") (part "R0402"))
    )
    (comp (ref "U23")
      (value "TB6612FNG")
      (footprint "eagle-import:SSOP24")
      (libsource (lib "eagle-import") (part "TB6612FNG"))
    )
    (comp (ref "U24")
      (value "MA03X2 FEMALE")
      (footprint "eagle-import:MA03-2")
      (libsource (lib "eagle-import") (part "MA03X2"))
    )
    (comp (ref "U25")
      (value "APTB1615")
      (footprint "eagle-import:APTB1615")
      (libsource (lib "eagle-import") (part "APTB1615"))
    )
    (comp (ref "U26")
      (value "APTB1615")
      (footprint "eagle-import:APTB1615")
      (libsource (lib "eagle-import") (part "APTB1615"))
    )
    (comp (ref "C99")
      (value "10uF")
      (footprint "eagle-import:0402")
      (libsource (lib "eagle-import") (part "C0402"))
    )
    (comp (ref "C100")
      (value "10uF")
      (footprint "eagle-import:0402")
      (libsource (lib "eagle-import") (part "C0402"))
    )
    (comp (ref "C101")
      (value "0.1uF")
      (footprint "eagle-import:0201")
      (libsource (lib "eagle-import") (part "C0201"))
    )
    (comp (ref "C102")
      (value "0.1uF")
      (footprint "eagle-import:0201")
      (libsource (lib "eagle-import") (part "C0201"))
    )
    (comp (ref "C103")
      (value "1.0uF")
      (footprint "eagle-import:0402")
      (libsource (lib "eagle-import") (part "C0402"))
    )
    (comp (ref "F4")
      (value "0603L100SLYR")
      (footprint "eagle-import:0603")
      (libsource (lib "eagle-import") (part "PTC0603"))
    )
    (comp (ref "F5")
      (value "0603L100SLYR")
      (footprint "eagle-import:0603")
      (libsource (lib "eagle-import") (part "PTC0603"))
    )
    (comp (ref "J9")
      (value "0.100 MALE PIN")
      (footprint "eagle-import:2X03_SHROUD")
      (libsource (lib "eagle-import") (part "2X03SHROUD"))
    )
    (comp (ref "U22")
      (value "TXS0102")
      (footprint "eagle-import:DFN8-0.4P")
      (libsource (lib "eagle-import") (part "TXS0102"))
    )
    (comp (ref "C120")
      (value "4.7uF")
      (footprint "eagle-import:0603")
      (libsource (lib "eagle-import") (part "C0603"))
    )
    (comp (ref "D17")
      (value "PS04LTVA1")
      (footprint "eagle-import:D0402")
      (libsource (lib "eagle-import") (part "ESD-DIODE"))
    )
    (comp (ref "D18")
      (value "PS04LTVA1")
      (footprint "eagle-import:D0402")
      (libsource (lib "eagle-import") (part "ESD-DIODE"))
    )
    (comp (ref "D19")
      (value "B72590D50A060")
      (footprint "eagle-import:D0402")
      (libsource (lib "eagle-import") (part "ESD-DIODE"))
    )
    (comp (ref "D20")
      (value "B72590D50A060")
      (footprint "eagle-import:D0402")
      (libsource (lib "eagle-import") (part "ESD-DIODE"))
    )
    (comp (ref "J14")
      (value "USB_MICRO_B")
      (footprint "eagle-import:USB_MICRO_B")
      (libsource (lib "eagle-import") (part "USB_MICRO_B"))
    )
    (comp (ref "L6")
      (value "DLP11SN900HL2")
      (footprint "eagle-import:0504-DLP11S")
      (libsource (lib "eagle-import") (part "COM_MODE_CHOKE"))
    )
    (comp (ref "R82")
      (value "0R")
      (footprint "eagle-import:0402")
      (libsource (lib "eagle-import") (part "R0402"))
    )
    (comp (ref "D2")
      (value "GREEN")
      (footprint "eagle-import:D0603")
      (libsource (lib "eagle-import") (part "LED0603"))
    )
    (comp (ref "Q2")
      (value "BSS138")
      (footprint "eagle-import:SOT23")
      (libsource (lib "eagle-import") (part "BSS138"))
    )
    (comp (ref "R23")
      (value "150R")
      (footprint "eagle-import:0402")
      (libsource (lib "eagle-import") (part "R0402"))
    )
    (comp (ref "R24")
      (value "10K")
      (footprint "eagle-import:0402")
      (libsource (lib "eagle-import") (part "R0402"))
    )
    (comp (ref "R25")
      (value "1K")
      (footprint "eagle-import:0402")
      (libsource (lib "eagle-import") (part "R0402"))
    )
    (comp (ref "C10")
      (value "0.1uF")
      (footprint "eagle-import:0201")
      (libsource (lib "eagle-import") (part "C0201"))
    )
    (comp (ref "C11")
      (value "100uF")
      (footprint "eagle-import:PANASONIC_D")
      (libsource (lib "eagle-import") (part "CPANASONIC_D"))
    )
    (comp (ref "C12")
      (value "10uF / 25V")
      (footprint "eagle-import:1206")
      (libsource (lib "eagle-import") (part "C1206"))
    )
    (comp (ref "C13")
      (value "0.22uF")
      (footprint "eagle-import:0603")
      (libsource (lib "eagle-import") (part "C0603"))
    )
    (comp (ref "C14")
      (value "22pF")
      (footprint "eagle-import:0402")
      (libsource (lib "eagle-import") (part "C0402"))
    )
    (comp (ref "C15")
      (value "22pF")
      (footprint "eagle-import:0402")
      (libsource (lib "eagle-import") (part "C0402"))
    )
    (comp (ref "R4")
      (value "6K8")
      (footprint "eagle-import:0402")
      (libsource (lib "eagle-import") (part "R0402"))
    )
    (comp (ref "R5")
      (value "6K8")
      (footprint "eagle-import:0402")
      (libsource (lib "eagle-import") (part "R0402"))
    )
    (comp (ref "R6")
      (value "2K2")
      (footprint "eagle-import:0402")
      (libsource (lib "eagle-import") (part "R0402"))
    )
    (comp (ref "R7")
      (value "2K2")
      (footprint "eagle-import:0402")
      (libsource (lib "eagle-import") (part "R0402"))
    )
    (comp (ref "R8")
      (value "470R")
      (footprint "eagle-import:0402")
      (libsource (lib "eagle-import") (part "R0402"))
    )
    (comp (ref "R9")
      (value "470R")
      (footprint "eagle-import:0402")
      (libsource (lib "eagle-import") (part "R0402"))
    )
    (comp (ref "R10")
      (value "1K5")
      (footprint "eagle-import:0402")
      (libsource (lib "eagle-import") (part "R0402"))
    )
    (comp (ref "R11")
      (value "6K8")
      (footprint "eagle-import:0402")
      (libsource (lib "eagle-import") (part "R0402"))
    )
    (comp (ref "R12")
      (value "6K8")
      (footprint "eagle-import:0402")
      (libsource (lib "eagle-import") (part "R0402"))
    )
    (comp (ref "R13")
      (value "2K2")
      (footprint "eagle-import:0402")
      (libsource (lib "eagle-import") (part "R0402"))
    )
    (comp (ref "R14")
      (value "2K2")
      (footprint "eagle-import:0402")
      (libsource (lib "eagle-import") (part "R0402"))
    )
    (comp (ref "R15")
      (value "470R")
      (footprint "eagle-import:0402")
      (libsource (lib "eagle-import") (part "R0402"))
    )
    (comp (ref "R16")
      (value "470R")
      (footprint "eagle-import:0402")
      (libsource (lib "eagle-import") (part "R0402"))
    )
    (comp (ref "R17")
      (value "1K5")
      (footprint "eagle-import:0402")
      (libsource (lib "eagle-import") (part "R0402"))
    )
    (comp (ref "U4")
      (value "TB6612FNG")
      (footprint "eagle-import:SSOP24")
      (libsource (lib "eagle-import") (part "TB6612FNG"))
    )
    (comp (ref "U5")
      (value "MA03X2 FEMALE")
      (footprint "eagle-import:MA03-2")
      (libsource (lib "eagle-import") (part "MA03X2"))
    )
    (comp (ref "U6")
      (value "APTB1615")
      (footprint "eagle-import:APTB1615")
      (libsource (lib "eagle-import") (part "APTB1615"))
    )
    (comp (ref "U7")
      (value "APTB1615")
      (footprint "eagle-import:APTB1615")
      (libsource (lib "eagle-import") (part "APTB1615"))
    )
    (comp (ref "C104")
      (value "0.1uF")
      (footprint "eagle-import:0402")
      (libsource (lib "eagle-import") (part "C0402"))
    )
    (comp (ref "R61")
      (value "15K")
      (footprint "eagle-import:0402")
      (libsource (lib "eagle-import") (part "R0402"))
    )
    (comp (ref "R62")
      (value "18K")
      (footprint "eagle-import:0402")
      (libsource (lib "eagle-import") (part "R0402"))
    )
    (comp (ref "S2")
      (value "EVQ")
      (footprint "eagle-import:EVQ")
      (libsource (lib "eagle-import") (part "EVQ"))
    )
    (comp (ref "C21")
      (value "0.1uF")
      (footprint "eagle-import:0201")
      (libsource (lib "eagle-import") (part "C0201"))
    )
    (comp (ref "C22")
      (value "0.1uF")
      (footprint "eagle-import:0201")
      (libsource (lib "eagle-import") (part "C0201"))
    )
    (comp (ref "C23")
      (value "1.0uF")
      (footprint "eagle-import:0402")
      (libsource (lib "eagle-import") (part "C0402"))
    )
    (comp (ref "J6")
      (value "MA03X1 MALE")
      (footprint "eagle-import:MA03-100")
      (libsource (lib "eagle-import") (part "MA03X1100"))
    )
    (comp (ref "U11")
      (value "TXS0102")
      (footprint "eagle-import:DFN8-0.4P")
      (libsource (lib "eagle-import") (part "TXS0102"))
    )
    (comp (ref "C267")
      (value "0.1uF")
      (footprint "eagle-import:0201")
      (libsource (lib "eagle-import") (part "C0201"))
    )
    (comp (ref "C268")
      (value "4.7uF")
      (footprint "eagle-import:0603")
      (libsource (lib "eagle-import") (part "C0603"))
    )
    (comp (ref "C269")
      (value "0.1uF")
      (footprint "eagle-import:0201")
      (libsource (lib "eagle-import") (part "C0201"))
    )
    (comp (ref "C270")
      (value "0.22uF")
      (footprint "eagle-import:0402")
      (libsource (lib "eagle-import") (part "C0402"))
    )
    (comp (ref "C271")
      (value "0.01uF / 25V")
      (footprint "eagle-import:0402")
      (libsource (lib "eagle-import") (part "C0402"))
    )
    (comp (ref "C272")
      (value "10uF")
      (footprint "eagle-import:0402")
      (libsource (lib "eagle-import") (part "C0402"))
    )
    (comp (ref "C273")
      (value "0.1uF")
      (footprint "eagle-import:0201")
      (libsource (lib "eagle-import") (part "C0201"))
    )
    (comp (ref "C274")
      (value "0.1uF")
      (footprint "eagle-import:0201")
      (libsource (lib "eagle-import") (part "C0201"))
    )
    (comp (ref "C275")
      (value "10uF")
      (footprint "eagle-import:0402")
      (libsource (lib "eagle-import") (part "C0402"))
    )
    (comp (ref "U36")
      (value "L3GD20H")
      (footprint "eagle-import:LGA16L")
      (libsource (lib "eagle-import") (part "L3G4200D3X3"))
    )
    (comp (ref "U37")
      (value "LSM303D")
      (footprint "eagle-import:LGA16-3X3MM")
      (libsource (lib "eagle-import") (part "LSM303DLGA"))
    )
    (comp (ref "C91")
      (value "0.1uF")
      (footprint "eagle-import:0402")
      (libsource (lib "eagle-import") (part "C0402"))
    )
    (comp (ref "C92")
      (value "10uF")
      (footprint "eagle-import:0603")
      (libsource (lib "eagle-import") (part "C0603"))
    )
    (comp (ref "RP1")
      (value "33R0")
      (footprint "eagle-import:741X16")
      (libsource (lib "eagle-import") (part "RP741X163"))
    )
    (comp (ref "RP2")
      (value "10K0")
      (footprint "eagle-import:741X16")
      (libsource (lib "eagle-import") (part "RP741X163"))
    )
    (comp (ref "U$30")
      (value "USD_3M2900")
      (footprint "eagle-import:USD")
      (libsource (lib "eagle-import") (part "USD_3M2900"))
    )
    (comp (ref "C60")
      (value "10pF")
      (footprint "eagle-import:0402")
      (libsource (lib "eagle-import") (part "C0402"))
    )
    (comp (ref "C61")
      (value "0.1uF / 16V")
      (footprint "eagle-import:0402")
      (libsource (lib "eagle-import") (part "C0402"))
    )
    (comp (ref "C62")
      (value "1.0uF")
      (footprint "eagle-import:0603")
      (libsource (lib "eagle-import") (part "C0603"))
    )
    (comp (ref "C63")
      (value "10uF / 16V")
      (footprint "eagle-import:0805")
      (libsource (lib "eagle-import") (part "C0805"))
    )
    (comp (ref "C64")
      (value "22uF")
      (footprint "eagle-import:0805")
      (libsource (lib "eagle-import") (part "C0805"))
    )
    (comp (ref "IC2")
      (value "TPS62111")
      (footprint "eagle-import:PQFP16")
      (libsource (lib "eagle-import") (part "TPS62111"))
    )
    (comp (ref "L1")
      (value "6.8uH")
      (footprint "eagle-import:1515")
      (libsource (lib "eagle-import") (part "L1515"))
    )
    (comp (ref "R38")
      (value "1M0")
      (footprint "eagle-import:0402")
      (libsource (lib "eagle-import") (part "R0402"))
    )
    (comp (ref "R39")
      (value "0R")
      (footprint "eagle-import:0402")
      (libsource (lib "eagle-import") (part "R0402"))
    )
    (comp (ref "R40")
      (value "DNP")
      (footprint "eagle-import:0402")
      (libsource (lib "eagle-import") (part "R0402"))
    )
    (comp (ref "J4")
      (value "0.1 FEMALE")
      (footprint "eagle-import:1X06")
      (libsource (lib "eagle-import") (part "1X06"))
    )
    (comp (ref "J5")
      (value "0.1 FEMALE")
      (footprint "eagle-import:2X06")
      (libsource (lib "eagle-import") (part "2X06"))
    )
    (comp (ref "C86")
      (value "10uF/50V")
      (footprint "eagle-import:1206")
      (libsource (lib "eagle-import") (part "C1206"))
    )
    (comp (ref "C87")
      (value "10nF")
      (footprint "eagle-import:0603")
      (libsource (lib "eagle-import") (part "C0603"))
    )
    (comp (ref "C88")
      (value "0.01uF")
      (footprint "eagle-import:0402")
      (libsource (lib "eagle-import") (part "C0402"))
    )
    (comp (ref "C89")
      (value "0.01uF")
      (footprint "eagle-import:0402")
      (libsource (lib "eagle-import") (part "C0402"))
    )
    (comp (ref "C90")
      (value "330uF")
      (footprint "eagle-import:PANASONIC_F")
      (libsource (lib "eagle-import") (part "CPANASONIC_F"))
    )
    (comp (ref "D10")
      (value "CDBC540-G")
      (footprint "eagle-import:DO-214AB")
      (libsource (lib "eagle-import") (part "SCHOTTKY-DIODE"))
    )
    (comp (ref "L2")
      (value "10uH")
      (footprint "eagle-import:3232DZ")
      (libsource (lib "eagle-import") (part "L3232DZ"))
    )
    (comp (ref "R33")
      (value "1K")
      (footprint "eagle-import:0201")
      (libsource (lib "eagle-import") (part "R0201"))
    )
    (comp (ref "R52")
      (value "0R")
      (footprint "eagle-import:0805")
      (libsource (lib "eagle-import") (part "R0805"))
    )
    (comp (ref "R53")
      (value "200K")
      (footprint "eagle-import:0402")
      (libsource (lib "eagle-import") (part "R0402"))
    )
    (comp (ref "R54")
      (value "51K")
      (footprint "eagle-import:0402")
      (libsource (lib "eagle-import") (part "R0402"))
    )
    (comp (ref "TP1")
      (value "DNP")
      (footprint "eagle-import:TP0500")
      (libsource (lib "eagle-import") (part "TP05"))
    )
    (comp (ref "U$27")
      (value "TPS5450")
      (footprint "eagle-import:8SO_POWERPAD")
      (libsource (lib "eagle-import") (part "TPS5450"))
    )
    (comp (ref "C105")
      (value "10uF/50V")
      (footprint "eagle-import:1206")
      (libsource (lib "eagle-import") (part "C1206"))
    )
    (comp (ref "C263")
      (value "10nF")
      (footprint "eagle-import:0603")
      (libsource (lib "eagle-import") (part "C0603"))
    )
    (comp (ref "C264")
      (value "0.01uF")
      (footprint "eagle-import:0402")
      (libsource (lib "eagle-import") (part "C0402"))
    )
    (comp (ref "C265")
      (value "0.01uF")
      (footprint "eagle-import:0402")
      (libsource (lib "eagle-import") (part "C0402"))
    )
    (comp (ref "C266")
      (value "330uF")
      (footprint "eagle-import:PANASONIC_F")
      (libsource (lib "eagle-import") (part "CPANASONIC_F"))
    )
    (comp (ref "D15")
      (value "CDBC540-G")
      (footprint "eagle-import:DO-214AB")
      (libsource (lib "eagle-import") (part "SCHOTTKY-DIODE"))
    )
    (comp (ref "L15")
      (value "10uH")
      (footprint "eagle-import:3232DZ")
      (libsource (lib "eagle-import") (part "L3232DZ"))
    )
    (comp (ref "R140")
      (value "0R")
      (footprint "eagle-import:0805")
      (libsource (lib "eagle-import") (part "R0805"))
    )
    (comp (ref "R141")
      (value "100K")
      (footprint "eagle-import:0402")
      (libsource (lib "eagle-import") (part "R0402"))
    )
    (comp (ref "R142")
      (value "31K6")
      (footprint "eagle-import:0402")
      (libsource (lib "eagle-import") (part "R0402"))
    )
    (comp (ref "TP2")
      (value "DNP")
      (footprint "eagle-import:TP0500")
      (libsource (lib "eagle-import") (part "TP05"))
    )
    (comp (ref "U$19")
      (value "TPS5450")
      (footprint "eagle-import:8SO_POWERPAD")
      (libsource (lib "eagle-import") (part "TPS5450"))
    )
    (comp (ref "C144")
      (value "0.1uF")
      (footprint "eagle-import:0201")
      (libsource (lib "eagle-import") (part "C0201"))
    )
    (comp (ref "C145")
      (value "0.1uF")
      (footprint "eagle-import:0201")
      (libsource (lib "eagle-import") (part "C0201"))
    )
    (comp (ref "C146")
      (value "0.1uF")
      (footprint "eagle-import:0201")
      (libsource (lib "eagle-import") (part "C0201"))
    )
    (comp (ref "C147")
      (value "0.1uF")
      (footprint "eagle-import:0201")
      (libsource (lib "eagle-import") (part "C0201"))
    )
    (comp (ref "C148")
      (value "0.1uF")
      (footprint "eagle-import:0201")
      (libsource (lib "eagle-import") (part "C0201"))
    )
    (comp (ref "C149")
      (value "0.1uF")
      (footprint "eagle-import:0201")
      (libsource (lib "eagle-import") (part "C0201"))
    )
    (comp (ref "C150")
      (value "0.1uF")
      (footprint "eagle-import:0201")
      (libsource (lib "eagle-import") (part "C0201"))
    )
    (comp (ref "C151")
      (value "0.1uF")
      (footprint "eagle-import:0201")
      (libsource (lib "eagle-import") (part "C0201"))
    )
    (comp (ref "C152")
      (value "0.1uF")
      (footprint "eagle-import:0201")
      (libsource (lib "eagle-import") (part "C0201"))
    )
    (comp (ref "R95")
      (value "75K")
      (footprint "eagle-import:0402")
      (libsource (lib "eagle-import") (part "R0402"))
    )
    (comp (ref "U$66")
      (value "ADS7846RGV")
      (footprint "eagle-import:QFN16")
      (libsource (lib "eagle-import") (part "ADS7846RGV"))
    )
    (comp (ref "U$67")
      (value "SN74LVC16T245")
      (footprint "eagle-import:TVSOP48")
      (libsource (lib "eagle-import") (part "74AC164245TVSOP"))
    )
    (comp (ref "U$68")
      (value "SN74LVC16T245")
      (footprint "eagle-import:TVSOP48")
      (libsource (lib "eagle-import") (part "74AC164245TVSOP"))
    )
    (comp (ref "U$69")
      (value "SN74LVC16T245")
      (footprint "eagle-import:TVSOP48")
      (libsource (lib "eagle-import") (part "74AC164245TVSOP"))
    )
    (comp (ref "U$70")
      (value "FH12-40-NHD-4.3")
      (footprint "eagle-import:FH12-40S-0.5SH")
      (libsource (lib "eagle-import") (part "FH12-40-NHD-4.3{dblquote}"))
    )
    (comp (ref "C70")
      (value "1.0uF")
      (footprint "eagle-import:0402")
      (libsource (lib "eagle-import") (part "C0402"))
    )
    (comp (ref "C71")
      (value "0.1uF")
      (footprint "eagle-import:0402")
      (libsource (lib "eagle-import") (part "C0402"))
    )
    (comp (ref "C72")
      (value "1.0uF")
      (footprint "eagle-import:0402")
      (libsource (lib "eagle-import") (part "C0402"))
    )
    (comp (ref "C73")
      (value "0.1uF")
      (footprint "eagle-import:0402")
      (libsource (lib "eagle-import") (part "C0402"))
    )
    (comp (ref "C74")
      (value "0.1uF")
      (footprint "eagle-import:0402")
      (libsource (lib "eagle-import") (part "C0402"))
    )
    (comp (ref "C75")
      (value "0.1uF")
      (footprint "eagle-import:0402")
      (libsource (lib "eagle-import") (part "C0402"))
    )
    (comp (ref "C76")
      (value "0.1uF")
      (footprint "eagle-import:0402")
      (libsource (lib "eagle-import") (part "C0402"))
    )
    (comp (ref "C77")
      (value "0.1uF")
      (footprint "eagle-import:0402")
      (libsource (lib "eagle-import") (part "C0402"))
    )
    (comp (ref "C78")
      (value "0.1uF")
      (footprint "eagle-import:0402")
      (libsource (lib "eagle-import") (part "C0402"))
    )
    (comp (ref "C79")
      (value "0.1uF")
      (footprint "eagle-import:0402")
      (libsource (lib "eagle-import") (part "C0402"))
    )
    (comp (ref "C80")
      (value "0.1uF")
      (footprint "eagle-import:0402")
      (libsource (lib "eagle-import") (part "C0402"))
    )
    (comp (ref "C81")
      (value "1.0uF")
      (footprint "eagle-import:0402")
      (libsource (lib "eagle-import") (part "C0402"))
    )
    (comp (ref "C82")
      (value "4.7uF")
      (footprint "eagle-import:0603")
      (libsource (lib "eagle-import") (part "C0603"))
    )
    (comp (ref "C83")
      (value "22pF")
      (footprint "eagle-import:0402")
      (libsource (lib "eagle-import") (part "C0402"))
    )
    (comp (ref "C84")
      (value "22pF")
      (footprint "eagle-import:0402")
      (libsource (lib "eagle-import") (part "C0402"))
    )
    (comp (ref "R44")
      (value "100K")
      (footprint "eagle-import:0402")
      (libsource (lib "eagle-import") (part "R0402"))
    )
    (comp (ref "R45")
      (value "100K")
      (footprint "eagle-import:0402")
      (libsource (lib "eagle-import") (part "R0402"))
    )
    (comp (ref "R46")
      (value "12K0")
      (footprint "eagle-import:0402")
      (libsource (lib "eagle-import") (part "R0402"))
    )
    (comp (ref "R47")
      (value "100K")
      (footprint "eagle-import:0402")
      (libsource (lib "eagle-import") (part "R0402"))
    )
    (comp (ref "R48")
      (value "100K")
      (footprint "eagle-import:0402")
      (libsource (lib "eagle-import") (part "R0402"))
    )
    (comp (ref "R49")
      (value "100K")
      (footprint "eagle-import:0402")
      (libsource (lib "eagle-import") (part "R0402"))
    )
    (comp (ref "R50")
      (value "100K")
      (footprint "eagle-import:0402")
      (libsource (lib "eagle-import") (part "R0402"))
    )
    (comp (ref "R51")
      (value "1M0")
      (footprint "eagle-import:0402")
      (libsource (lib "eagle-import") (part "R0402"))
    )
    (comp (ref "U18")
      (value "USB2513")
      (footprint "eagle-import:QFN36-6X6MM")
      (libsource (lib "eagle-import") (part "USB2513"))
    )
    (comp (ref "Y1")
      (value "24.000MHz")
      (footprint "eagle-import:CRYSTAL-3225")
      (libsource (lib "eagle-import") (part "Y4CRYSTAL-3225"))
    )
    (comp (ref "D11")
      (value "BLUE")
      (footprint "eagle-import:D0603")
      (libsource (lib "eagle-import") (part "LED0603"))
    )
    (comp (ref "Q3")
      (value "BSS138")
      (footprint "eagle-import:SOT23")
      (libsource (lib "eagle-import") (part "BSS138"))
    )
    (comp (ref "R55")
      (value "180R")
      (footprint "eagle-import:0402")
      (libsource (lib "eagle-import") (part "R0402"))
    )
    (comp (ref "R56")
      (value "10K")
      (footprint "eagle-import:0402")
      (libsource (lib "eagle-import") (part "R0402"))
    )
    (comp (ref "R57")
      (value "1K")
      (footprint "eagle-import:0402")
      (libsource (lib "eagle-import") (part "R0402"))
    )
    (comp (ref "C16")
      (value "0.1uF")
      (footprint "eagle-import:0201")
      (libsource (lib "eagle-import") (part "C0201"))
    )
    (comp (ref "C17")
      (value "0.1uF")
      (footprint "eagle-import:0201")
      (libsource (lib "eagle-import") (part "C0201"))
    )
    (comp (ref "RP3")
      (value "DNP")
      (footprint "eagle-import:741X08")
      (libsource (lib "eagle-import") (part "RP741X083"))
    )
    (comp (ref "U8")
      (value "TXS0108E")
      (footprint "eagle-import:QFN20")
      (libsource (lib "eagle-import") (part "TXS0108E"))
    )
    (comp (ref "C96")
      (value "0.1uF")
      (footprint "eagle-import:0201")
      (libsource (lib "eagle-import") (part "C0201"))
    )
    (comp (ref "C97")
      (value "0.1uF")
      (footprint "eagle-import:0201")
      (libsource (lib "eagle-import") (part "C0201"))
    )
    (comp (ref "C98")
      (value "1.0uF")
      (footprint "eagle-import:0402")
      (libsource (lib "eagle-import") (part "C0402"))
    )
    (comp (ref "J8")
      (value "DNP")
      (footprint "eagle-import:MA03-100")
      (libsource (lib "eagle-import") (part "MA03X1100"))
    )
    (comp (ref "R138")
      (value "1K5")
      (footprint "eagle-import:0201")
      (libsource (lib "eagle-import") (part "R0201"))
    )
    (comp (ref "R139")
      (value "1K5")
      (footprint "eagle-import:0201")
      (libsource (lib "eagle-import") (part "R0201"))
    )
    (comp (ref "U21")
      (value "TXS0102")
      (footprint "eagle-import:DFN8-0.4P")
      (libsource (lib "eagle-import") (part "TXS0102"))
    )
    (comp (ref "C164")
      (value "1.0uF")
      (footprint "eagle-import:0201")
      (libsource (lib "eagle-import") (part "C0201"))
    )
    (comp (ref "C165")
      (value "1.0uF")
      (footprint "eagle-import:0201")
      (libsource (lib "eagle-import") (part "C0201"))
    )
    (comp (ref "C166")
      (value "1.0uF")
      (footprint "eagle-import:0201")
      (libsource (lib "eagle-import") (part "C0201"))
    )
    (comp (ref "C167")
      (value "1.0uF")
      (footprint "eagle-import:0201")
      (libsource (lib "eagle-import") (part "C0201"))
    )
    (comp (ref "R129")
      (value "49R9")
      (footprint "eagle-import:0201")
      (libsource (lib "eagle-import") (part "R0201"))
    )
    (comp (ref "U$79")
      (value "100K")
      (footprint "eagle-import:741C083")
      (libsource (lib "eagle-import") (part "741C083"))
    )
    (comp (ref "U$80")
      (value "100K")
      (footprint "eagle-import:741C083")
      (libsource (lib "eagle-import") (part "741C083"))
    )
    (comp (ref "U$81")
      (value "100K")
      (footprint "eagle-import:741C083")
      (libsource (lib "eagle-import") (part "741C083"))
    )
    (comp (ref "U$82")
      (value "100K")
      (footprint "eagle-import:741C083")
      (libsource (lib "eagle-import") (part "741C083"))
    )
    (comp (ref "D13")
      (value "PS04LTVA1")
      (footprint "eagle-import:D0402")
      (libsource (lib "eagle-import") (part "ESD-DIODE"))
    )
    (comp (ref "D14")
      (value "PS04LTVA1")
      (footprint "eagle-import:D0402")
      (libsource (lib "eagle-import") (part "ESD-DIODE"))
    )
    (comp (ref "D16")
      (value "B72590D50A060")
      (footprint "eagle-import:D0402")
      (libsource (lib "eagle-import") (part "ESD-DIODE"))
    )
    (comp (ref "D32")
      (value "PS04LTVA1")
      (footprint "eagle-import:D0402")
      (libsource (lib "eagle-import") (part "ESD-DIODE"))
    )
    (comp (ref "J10")
      (value "USB_MICRO_B")
      (footprint "eagle-import:USB_MICRO_B")
      (libsource (lib "eagle-import") (part "USB_MICRO_B"))
    )
    (comp (ref "L5")
      (value "DLP11SN900HL2")
      (footprint "eagle-import:0504-DLP11S")
      (libsource (lib "eagle-import") (part "COM_MODE_CHOKE"))
    )
    (comp (ref "C65")
      (value "1.0uF")
      (footprint "eagle-import:0402")
      (libsource (lib "eagle-import") (part "C0402"))
    )
    (comp (ref "C66")
      (value "DNP")
      (footprint "eagle-import:0402")
      (libsource (lib "eagle-import") (part "C0402"))
    )
    (comp (ref "C67")
      (value "0.1uF")
      (footprint "eagle-import:0402")
      (libsource (lib "eagle-import") (part "C0402"))
    )
    (comp (ref "C68")
      (value "DNP")
      (footprint "eagle-import:0402")
      (libsource (lib "eagle-import") (part "C0402"))
    )
    (comp (ref "C69")
      (value "0.1uF")
      (footprint "eagle-import:0402")
      (libsource (lib "eagle-import") (part "C0402"))
    )
    (comp (ref "R41")
      (value "15K")
      (footprint "eagle-import:0201")
      (libsource (lib "eagle-import") (part "R0201"))
    )
    (comp (ref "R42")
      (value "0R")
      (footprint "eagle-import:0201")
      (libsource (lib "eagle-import") (part "R0201"))
    )
    (comp (ref "R43")
      (value "22K")
      (footprint "eagle-import:0402")
      (libsource (lib "eagle-import") (part "R0402"))
    )
    (comp (ref "SPKR+")
      (value "DNP")
      (footprint "eagle-import:P1-13")
      (libsource (lib "eagle-import") (part "TPSQPAD1-13"))
    )
    (comp (ref "SPKR-")
      (value "DNP")
      (footprint "eagle-import:P1-13")
      (libsource (lib "eagle-import") (part "TPSQPAD1-13"))
    )
    (comp (ref "U17")
      (value "LM4862M")
      (footprint "eagle-import:SO-8")
      (libsource (lib "eagle-import") (part "LM4862"))
    )
    (comp (ref "C18")
      (value "0.1uF")
      (footprint "eagle-import:0201")
      (libsource (lib "eagle-import") (part "C0201"))
    )
    (comp (ref "C19")
      (value "0.1uF")
      (footprint "eagle-import:0201")
      (libsource (lib "eagle-import") (part "C0201"))
    )
    (comp (ref "C20")
      (value "1.0uF")
      (footprint "eagle-import:0201")
      (libsource (lib "eagle-import") (part "C0201"))
    )
    (comp (ref "R21")
      (value "DNP")
      (footprint "eagle-import:0201")
      (libsource (lib "eagle-import") (part "R0201"))
    )
    (comp (ref "R22")
      (value "DNP")
      (footprint "eagle-import:0201")
      (libsource (lib "eagle-import") (part "R0201"))
    )
    (comp (ref "U10")
      (value "TXS0102")
      (footprint "eagle-import:DFN8-0.4P")
      (libsource (lib "eagle-import") (part "TXS0102"))
    )
    (comp (ref "ACLK")
      (value "DNP")
      (footprint "eagle-import:TP0500")
      (libsource (lib "eagle-import") (part "TP05"))
    )
    (comp (ref "ACS0")
      (value "DNP")
      (footprint "eagle-import:TP0500")
      (libsource (lib "eagle-import") (part "TP05"))
    )
    (comp (ref "ARX")
      (value "DNP")
      (footprint "eagle-import:TP0500")
      (libsource (lib "eagle-import") (part "TP05"))
    )
    (comp (ref "ATX")
      (value "DNP")
      (footprint "eagle-import:TP0500")
      (libsource (lib "eagle-import") (part "TP05"))
    )
    (comp (ref "BT4")
      (value "DNP")
      (footprint "eagle-import:TP0500")
      (libsource (lib "eagle-import") (part "TP05"))
    )
    (comp (ref "BTEN")
      (value "DNP")
      (footprint "eagle-import:TP0500")
      (libsource (lib "eagle-import") (part "TP05"))
    )
    (comp (ref "C115")
      (value "0.1uF")
      (footprint "eagle-import:0402")
      (libsource (lib "eagle-import") (part "C0402"))
    )
    (comp (ref "C116")
      (value "10uF")
      (footprint "eagle-import:0603")
      (libsource (lib "eagle-import") (part "C0603"))
    )
    (comp (ref "C117")
      (value "10uF")
      (footprint "eagle-import:0603")
      (libsource (lib "eagle-import") (part "C0603"))
    )
    (comp (ref "C142")
      (value "0.1uF")
      (footprint "eagle-import:0402")
      (libsource (lib "eagle-import") (part "C0402"))
    )
    (comp (ref "C143")
      (value "10pF")
      (footprint "eagle-import:0402")
      (libsource (lib "eagle-import") (part "C0402"))
    )
    (comp (ref "C174")
      (value "0.1uF")
      (footprint "eagle-import:0402")
      (libsource (lib "eagle-import") (part "C0402"))
    )
    (comp (ref "C175")
      (value "10pF")
      (footprint "eagle-import:0402")
      (libsource (lib "eagle-import") (part "C0402"))
    )
    (comp (ref "CONN1")
      (value "U.FL")
      (footprint "eagle-import:U.FL")
      (libsource (lib "eagle-import") (part "U.FL"))
    )
    (comp (ref "FB5")
      (value "120R 1A")
      (footprint "eagle-import:0402")
      (libsource (lib "eagle-import") (part "FB0402"))
    )
    (comp (ref "FB6")
      (value "120R 1A")
      (footprint "eagle-import:0402")
      (libsource (lib "eagle-import") (part "FB0402"))
    )
    (comp (ref "Q5")
      (value "32.768kHz")
      (footprint "eagle-import:ASF")
      (fields (field (name "MF") "Abracon Corporation") (field (name "MPN") "ASFL1-125.000MHZ-EC-T"))
      (libsource (lib "eagle-import") (part "ASFL1"))
    )
    (comp (ref "R144")
      (value "DNP")
      (footprint "eagle-import:0402")
      (libsource (lib "eagle-import") (part "R0402"))
    )
    (comp (ref "RP5")
      (value "10K0")
      (footprint "eagle-import:741X16")
      (libsource (lib "eagle-import") (part "RP741X163"))
    )
    (comp (ref "RP6")
      (value "33R0")
      (footprint "eagle-import:741X16")
      (libsource (lib "eagle-import") (part "RP741X163"))
    )
    (comp (ref "U28")
      (value "WL1831MOD")
      (footprint "eagle-import:WL1801MOD")
      (libsource (lib "eagle-import") (part "WL1801MOD"))
    )
    (comp (ref "WLDB")
      (value "DNP")
      (footprint "eagle-import:TP0500")
      (libsource (lib "eagle-import") (part "TP05"))
    )
    (comp (ref "WLEN")
      (value "DNP")
      (footprint "eagle-import:TP0500")
      (libsource (lib "eagle-import") (part "TP05"))
    )
    (comp (ref "WLRX")
      (value "DNP")
      (footprint "eagle-import:TP0500")
      (libsource (lib "eagle-import") (part "TP05"))
    )
    (comp (ref "WLTX")
      (value "DNP")
      (footprint "eagle-import:TP0500")
      (libsource (lib "eagle-import") (part "TP05"))
    )
    (comp (ref "C4")
      (value "10uF")
      (footprint "eagle-import:0402")
      (libsource (lib "eagle-import") (part "C0402"))
    )
    (comp (ref "C5")
      (value "10uF")
      (footprint "eagle-import:0402")
      (libsource (lib "eagle-import") (part "C0402"))
    )
    (comp (ref "C6")
      (value "0.1uF")
      (footprint "eagle-import:0201")
      (libsource (lib "eagle-import") (part "C0201"))
    )
    (comp (ref "C7")
      (value "0.1uF")
      (footprint "eagle-import:0201")
      (libsource (lib "eagle-import") (part "C0201"))
    )
    (comp (ref "C8")
      (value "1.0uF")
      (footprint "eagle-import:0402")
      (libsource (lib "eagle-import") (part "C0402"))
    )
    (comp (ref "F1")
      (value "0603L100SLYR")
      (footprint "eagle-import:0603")
      (libsource (lib "eagle-import") (part "PTC0603"))
    )
    (comp (ref "F2")
      (value "0603L100SLYR")
      (footprint "eagle-import:0603")
      (libsource (lib "eagle-import") (part "PTC0603"))
    )
    (comp (ref "J2")
      (value "0.100 MALE PIN")
      (footprint "eagle-import:2X03_SHROUD")
      (libsource (lib "eagle-import") (part "2X03SHROUD"))
    )
    (comp (ref "U2")
      (value "TXS0102")
      (footprint "eagle-import:DFN8-0.4P")
      (libsource (lib "eagle-import") (part "TXS0102"))
    )
    (comp (ref "C112")
      (value "0.1uF")
      (footprint "eagle-import:0201")
      (libsource (lib "eagle-import") (part "C0201"))
    )
    (comp (ref "C113")
      (value "0.1uF")
      (footprint "eagle-import:0201")
      (libsource (lib "eagle-import") (part "C0201"))
    )
    (comp (ref "C114")
      (value "1.0uF")
      (footprint "eagle-import:0402")
      (libsource (lib "eagle-import") (part "C0402"))
    )
    (comp (ref "J11")
      (value "MA03X1 MALE")
      (footprint "eagle-import:MA03-100")
      (libsource (lib "eagle-import") (part "MA03X1100"))
    )
    (comp (ref "U27")
      (value "TXS0102")
      (footprint "eagle-import:DFN8-0.4P")
      (libsource (lib "eagle-import") (part "TXS0102"))
    )
    (comp (ref "C153")
      (value "0.1uF")
      (footprint "eagle-import:0402")
      (libsource (lib "eagle-import") (part "C0402"))
    )
    (comp (ref "C154")
      (value "0.1uF")
      (footprint "eagle-import:0402")
      (libsource (lib "eagle-import") (part "C0402"))
    )
    (comp (ref "C155")
      (value "0.1uF")
      (footprint "eagle-import:0402")
      (libsource (lib "eagle-import") (part "C0402"))
    )
    (comp (ref "C156")
      (value "0.1uF")
      (footprint "eagle-import:0402")
      (libsource (lib "eagle-import") (part "C0402"))
    )
    (comp (ref "C157")
      (value "0.1uF")
      (footprint "eagle-import:0402")
      (libsource (lib "eagle-import") (part "C0402"))
    )
    (comp (ref "C158")
      (value "10uF")
      (footprint "eagle-import:0603")
      (libsource (lib "eagle-import") (part "C0603"))
    )
    (comp (ref "C159")
      (value "10uF")
      (footprint "eagle-import:0603")
      (libsource (lib "eagle-import") (part "C0603"))
    )
    (comp (ref "C160")
      (value "10uF")
      (footprint "eagle-import:0603")
      (libsource (lib "eagle-import") (part "C0603"))
    )
    (comp (ref "C161")
      (value "0.1uF")
      (footprint "eagle-import:0402")
      (libsource (lib "eagle-import") (part "C0402"))
    )
    (comp (ref "C162")
      (value "0.1uF")
      (footprint "eagle-import:0402")
      (libsource (lib "eagle-import") (part "C0402"))
    )
    (comp (ref "C163")
      (value "0.1uF")
      (footprint "eagle-import:0402")
      (libsource (lib "eagle-import") (part "C0402"))
    )
    (comp (ref "D21")
      (value "PS04LTVA1")
      (footprint "eagle-import:D0402")
      (libsource (lib "eagle-import") (part "ESD-DIODE"))
    )
    (comp (ref "D22")
      (value "PS04LTVA1")
      (footprint "eagle-import:D0402")
      (libsource (lib "eagle-import") (part "ESD-DIODE"))
    )
    (comp (ref "D23")
      (value "PS04LTVA1")
      (footprint "eagle-import:D0402")
      (libsource (lib "eagle-import") (part "ESD-DIODE"))
    )
    (comp (ref "D24")
      (value "PS04LTVA1")
      (footprint "eagle-import:D0402")
      (libsource (lib "eagle-import") (part "ESD-DIODE"))
    )
    (comp (ref "D25")
      (value "PS04LTVA1")
      (footprint "eagle-import:D0402")
      (libsource (lib "eagle-import") (part "ESD-DIODE"))
    )
    (comp (ref "D26")
      (value "PS04LTVA1")
      (footprint "eagle-import:D0402")
      (libsource (lib "eagle-import") (part "ESD-DIODE"))
    )
    (comp (ref "D27")
      (value "PS04LTVA1")
      (footprint "eagle-import:D0402")
      (libsource (lib "eagle-import") (part "ESD-DIODE"))
    )
    (comp (ref "D28")
      (value "PS04LTVA1")
      (footprint "eagle-import:D0402")
      (libsource (lib "eagle-import") (part "ESD-DIODE"))
    )
    (comp (ref "D29")
      (value "PS04LTVA1")
      (footprint "eagle-import:D0402")
      (libsource (lib "eagle-import") (part "ESD-DIODE"))
    )
    (comp (ref "D30")
      (value "PS04LTVA1")
      (footprint "eagle-import:D0402")
      (libsource (lib "eagle-import") (part "ESD-DIODE"))
    )
    (comp (ref "FB7")
      (value "120R 1A")
      (footprint "eagle-import:0402")
      (libsource (lib "eagle-import") (part "FB0402"))
    )
    (comp (ref "FB8")
      (value "120R 1A")
      (footprint "eagle-import:0402")
      (libsource (lib "eagle-import") (part "FB0402"))
    )
    (comp (ref "IC4")
      (value "TFP410")
      (footprint "eagle-import:TQFP-64")
      (libsource (lib "eagle-import") (part "TFP100"))
    )
    (comp (ref "J15")
      (value "HDMIMICRO")
      (footprint "eagle-import:46765-001")
      (libsource (lib "eagle-import") (part "HDMIMICRO"))
    )
    (comp (ref "L7")
      (value "DLP0NSN900HL2")
      (footprint "eagle-import:03025-DLP0NS")
      (libsource (lib "eagle-import") (part "COM_MODE_CHOKE03025"))
    )
    (comp (ref "L8")
      (value "DLP0NSN900HL2")
      (footprint "eagle-import:03025-DLP0NS")
      (libsource (lib "eagle-import") (part "COM_MODE_CHOKE03025"))
    )
    (comp (ref "L9")
      (value "DLP0NSN900HL2")
      (footprint "eagle-import:03025-DLP0NS")
      (libsource (lib "eagle-import") (part "COM_MODE_CHOKE03025"))
    )
    (comp (ref "L10")
      (value "DLP0NSN900HL2")
      (footprint "eagle-import:03025-DLP0NS")
      (libsource (lib "eagle-import") (part "COM_MODE_CHOKE03025"))
    )
    (comp (ref "R96")
      (value "10K")
      (footprint "eagle-import:0402")
      (libsource (lib "eagle-import") (part "R0402"))
    )
    (comp (ref "R97")
      (value "10K")
      (footprint "eagle-import:0402")
      (libsource (lib "eagle-import") (part "R0402"))
    )
    (comp (ref "R98")
      (value "10K")
      (footprint "eagle-import:0402")
      (libsource (lib "eagle-import") (part "R0402"))
    )
    (comp (ref "R99")
      (value "10K")
      (footprint "eagle-import:0402")
      (libsource (lib "eagle-import") (part "R0402"))
    )
    (comp (ref "R100")
      (value "10K")
      (footprint "eagle-import:0402")
      (libsource (lib "eagle-import") (part "R0402"))
    )
    (comp (ref "R101")
      (value "10K")
      (footprint "eagle-import:0402")
      (libsource (lib "eagle-import") (part "R0402"))
    )
    (comp (ref "R102")
      (value "510R")
      (footprint "eagle-import:0402")
      (libsource (lib "eagle-import") (part "R0402"))
    )
    (comp (ref "R103")
      (value "DNP")
      (footprint "eagle-import:0402")
      (libsource (lib "eagle-import") (part "R0402"))
    )
    (comp (ref "R104")
      (value "4K7")
      (footprint "eagle-import:0402")
      (libsource (lib "eagle-import") (part "R0402"))
    )
    (comp (ref "R105")
      (value "10K")
      (footprint "eagle-import:0402")
      (libsource (lib "eagle-import") (part "R0402"))
    )
    (comp (ref "R106")
      (value "200K")
      (footprint "eagle-import:0402")
      (libsource (lib "eagle-import") (part "R0402"))
    )
    (comp (ref "R107")
      (value "1K5")
      (footprint "eagle-import:0402")
      (libsource (lib "eagle-import") (part "R0402"))
    )
    (comp (ref "R108")
      (value "1K5")
      (footprint "eagle-import:0402")
      (libsource (lib "eagle-import") (part "R0402"))
    )
    (comp (ref "R109")
      (value "1K5")
      (footprint "eagle-import:0402")
      (libsource (lib "eagle-import") (part "R0402"))
    )
    (comp (ref "R112")
      (value "1K5")
      (footprint "eagle-import:0402")
      (libsource (lib "eagle-import") (part "R0402"))
    )
    (comp (ref "R113")
      (value "10R0")
      (footprint "eagle-import:0402")
      (libsource (lib "eagle-import") (part "R0402"))
    )
    (comp (ref "R114")
      (value "DNP")
      (footprint "eagle-import:0402")
      (libsource (lib "eagle-import") (part "R0402"))
    )
    (comp (ref "R115")
      (value "10R0")
      (footprint "eagle-import:0402")
      (libsource (lib "eagle-import") (part "R0402"))
    )
    (comp (ref "R116")
      (value "10R0")
      (footprint "eagle-import:0402")
      (libsource (lib "eagle-import") (part "R0402"))
    )
    (comp (ref "R117")
      (value "10R0")
      (footprint "eagle-import:0402")
      (libsource (lib "eagle-import") (part "R0402"))
    )
    (comp (ref "R143")
      (value "10K")
      (footprint "eagle-import:0402")
      (libsource (lib "eagle-import") (part "R0402"))
    )
    (comp (ref "RP8")
      (value "10R0")
      (footprint "eagle-import:741X16")
      (libsource (lib "eagle-import") (part "RP741X163"))
    )
    (comp (ref "RP9")
      (value "10R0")
      (footprint "eagle-import:741X16")
      (libsource (lib "eagle-import") (part "RP741X163"))
    )
    (comp (ref "RP10")
      (value "10R0")
      (footprint "eagle-import:741X16")
      (libsource (lib "eagle-import") (part "RP741X163"))
    )
    (comp (ref "U33")
      (value "PCA9306")
      (footprint "eagle-import:DCT-8(SSOP)")
      (libsource (lib "eagle-import") (part "PCA9306"))
    )
    (comp (ref "C93")
      (value "0.1uF")
      (footprint "eagle-import:0201")
      (libsource (lib "eagle-import") (part "C0201"))
    )
    (comp (ref "C94")
      (value "0.1uF")
      (footprint "eagle-import:0201")
      (libsource (lib "eagle-import") (part "C0201"))
    )
    (comp (ref "C95")
      (value "1.0uF")
      (footprint "eagle-import:0402")
      (libsource (lib "eagle-import") (part "C0402"))
    )
    (comp (ref "J7")
      (value "DNP")
      (footprint "eagle-import:2X03")
      (libsource (lib "eagle-import") (part "2X03"))
    )
    (comp (ref "RP4")
      (value "DNP")
      (footprint "eagle-import:741X16")
      (libsource (lib "eagle-import") (part "RP741X163"))
    )
    (comp (ref "U20")
      (value "TXS0108E")
      (footprint "eagle-import:QFN20")
      (libsource (lib "eagle-import") (part "TXS0108E"))
    )
    (comp (ref "D1")
      (value "RED")
      (footprint "eagle-import:D0603")
      (libsource (lib "eagle-import") (part "LED0603"))
    )
    (comp (ref "F3")
      (value "2920L500/16MR")
      (footprint "eagle-import:2920")
      (libsource (lib "eagle-import") (part "PTC2920"))
    )
    (comp (ref "Q1")
      (value "FDT434P")
      (footprint "eagle-import:SOT223")
      (libsource (lib "eagle-import") (part "BSP170P"))
    )
    (comp (ref "Q6")
      (value "FDT434P")
      (footprint "eagle-import:SOT223")
      (libsource (lib "eagle-import") (part "BSP170P"))
    )
    (comp (ref "R18")
      (value "330R")
      (footprint "eagle-import:0201")
      (libsource (lib "eagle-import") (part "R0201"))
    )
    (comp (ref "R19")
      (value "30K")
      (footprint "eagle-import:0201")
      (libsource (lib "eagle-import") (part "R0201"))
    )
    (comp (ref "R20")
      (value "1K")
      (footprint "eagle-import:0201")
      (libsource (lib "eagle-import") (part "R0201"))
    )
    (comp (ref "U9")
      (value "JS102011SAQN")
      (footprint "eagle-import:JS102011SAQN")
      (libsource (lib "eagle-import") (part "JS102011SAQN"))
    )
    (comp (ref "D12")
      (value "YELLOW")
      (footprint "eagle-import:D0603")
      (libsource (lib "eagle-import") (part "LED0603"))
    )
    (comp (ref "Q4")
      (value "BSS138")
      (footprint "eagle-import:SOT23")
      (libsource (lib "eagle-import") (part "BSS138"))
    )
    (comp (ref "R58")
      (value "180R")
      (footprint "eagle-import:0402")
      (libsource (lib "eagle-import") (part "R0402"))
    )
    (comp (ref "R59")
      (value "10K")
      (footprint "eagle-import:0402")
      (libsource (lib "eagle-import") (part "R0402"))
    )
    (comp (ref "R60")
      (value "1K")
      (footprint "eagle-import:0402")
      (libsource (lib "eagle-import") (part "R0402"))
    )
    (comp (ref "C9")
      (value "0.1uF")
      (footprint "eagle-import:0402")
      (libsource (lib "eagle-import") (part "C0402"))
    )
    (comp (ref "R1")
      (value "15K")
      (footprint "eagle-import:0402")
      (libsource (lib "eagle-import") (part "R0402"))
    )
    (comp (ref "R2")
      (value "DNP")
      (footprint "eagle-import:0402")
      (libsource (lib "eagle-import") (part "R0402"))
    )
    (comp (ref "S1")
      (value "EVQ")
      (footprint "eagle-import:EVQ")
      (libsource (lib "eagle-import") (part "EVQ"))
    )
    (comp (ref "C220")
      (value "0.1uF")
      (footprint "eagle-import:0201")
      (libsource (lib "eagle-import") (part "C0201"))
    )
    (comp (ref "C252")
      (value "0.1uF")
      (footprint "eagle-import:0201")
      (libsource (lib "eagle-import") (part "C0201"))
    )
    (comp (ref "C253")
      (value "0.1uF")
      (footprint "eagle-import:0201")
      (libsource (lib "eagle-import") (part "C0201"))
    )
    (comp (ref "C254")
      (value "0.1uF")
      (footprint "eagle-import:0201")
      (libsource (lib "eagle-import") (part "C0201"))
    )
    (comp (ref "C255")
      (value "0.1uF")
      (footprint "eagle-import:0201")
      (libsource (lib "eagle-import") (part "C0201"))
    )
    (comp (ref "C256")
      (value "0.1uF")
      (footprint "eagle-import:0201")
      (libsource (lib "eagle-import") (part "C0201"))
    )
    (comp (ref "C257")
      (value "0.1uF")
      (footprint "eagle-import:0201")
      (libsource (lib "eagle-import") (part "C0201"))
    )
    (comp (ref "C258")
      (value "0.1uF")
      (footprint "eagle-import:0201")
      (libsource (lib "eagle-import") (part "C0201"))
    )
    (comp (ref "C259")
      (value "0.1uF")
      (footprint "eagle-import:0201")
      (libsource (lib "eagle-import") (part "C0201"))
    )
    (comp (ref "C260")
      (value "0.1uF")
      (footprint "eagle-import:0201")
      (libsource (lib "eagle-import") (part "C0201"))
    )
    (comp (ref "C261")
      (value "0.1uF")
      (footprint "eagle-import:0201")
      (libsource (lib "eagle-import") (part "C0201"))
    )
    (comp (ref "C262")
      (value "0.1uF")
      (footprint "eagle-import:0201")
      (libsource (lib "eagle-import") (part "C0201"))
    )
    (comp (ref "R122")
      (value "1K5")
      (footprint "eagle-import:0201")
      (libsource (lib "eagle-import") (part "R0201"))
    )
    (comp (ref "R123")
      (value "1K5")
      (footprint "eagle-import:0201")
      (libsource (lib "eagle-import") (part "R0201"))
    )
    (comp (ref "R131")
      (value "10K")
      (footprint "eagle-import:0201")
      (libsource (lib "eagle-import") (part "R0201"))
    )
    (comp (ref "R132")
      (value "10K")
      (footprint "eagle-import:0201")
      (libsource (lib "eagle-import") (part "R0201"))
    )
    (comp (ref "R133")
      (value "240R0")
      (footprint "eagle-import:0201")
      (libsource (lib "eagle-import") (part "R0201"))
    )
    (comp (ref "R134")
      (value "1K5")
      (footprint "eagle-import:0201")
      (libsource (lib "eagle-import") (part "R0201"))
    )
    (comp (ref "R135")
      (value "10K")
      (footprint "eagle-import:0201")
      (libsource (lib "eagle-import") (part "R0201"))
    )
    (comp (ref "R340")
      (value "100K")
      (footprint "eagle-import:0201")
      (libsource (lib "eagle-import") (part "R0201"))
    )
    (comp (ref "R342")
      (value "100K")
      (footprint "eagle-import:0201")
      (libsource (lib "eagle-import") (part "R0201"))
    )
    (comp (ref "R344")
      (value "100K")
      (footprint "eagle-import:0201")
      (libsource (lib "eagle-import") (part "R0201"))
    )
    (comp (ref "U$101")
      (value "MT41K256M16")
      (footprint "eagle-import:FBGA_96_10_14")
      (libsource (lib "eagle-import") (part "MT41K256M16"))
    )
    (comp (ref "U34")
      (value "AT24C01B-TH_B")
      (footprint "eagle-import:TSSOP8")
      (libsource (lib "eagle-import") (part "AT24CA"))
    )
    (comp (ref "C55")
      (value "0.1uF")
      (footprint "eagle-import:0201")
      (libsource (lib "eagle-import") (part "C0201"))
    )
    (comp (ref "C56")
      (value "0.1uF")
      (footprint "eagle-import:0201")
      (libsource (lib "eagle-import") (part "C0201"))
    )
    (comp (ref "R36")
      (value "DNP")
      (footprint "eagle-import:0201")
      (libsource (lib "eagle-import") (part "R0201"))
    )
    (comp (ref "R37")
      (value "DNP")
      (footprint "eagle-import:0201")
      (libsource (lib "eagle-import") (part "R0201"))
    )
    (comp (ref "U16")
      (value "74AVC2T245")
      (footprint "eagle-import:UQFN-10")
      (libsource (lib "eagle-import") (part "74AVC2T245"))
    )
    (comp (ref "C57")
      (value "4.7uF")
      (footprint "eagle-import:0603")
      (libsource (lib "eagle-import") (part "C0603"))
    )
    (comp (ref "C58")
      (value "0.1uF")
      (footprint "eagle-import:0201")
      (libsource (lib "eagle-import") (part "C0201"))
    )
    (comp (ref "C59")
      (value "22uF")
      (footprint "eagle-import:0805")
      (libsource (lib "eagle-import") (part "C0805"))
    )
    (comp (ref "IC1")
      (value "EP5368")
      (footprint "eagle-import:EP-3X3MMQFN16")
      (libsource (lib "eagle-import") (part "EP5368"))
    )
    (comp (ref "C26")
      (value "10uF")
      (footprint "eagle-import:0603")
      (libsource (lib "eagle-import") (part "C0603"))
    )
    (comp (ref "C27")
      (value "0.01uF")
      (footprint "eagle-import:0402")
      (libsource (lib "eagle-import") (part "C0402"))
    )
    (comp (ref "C28")
      (value "0.1uF")
      (footprint "eagle-import:0402")
      (libsource (lib "eagle-import") (part "C0402"))
    )
    (comp (ref "C29")
      (value "100uF")
      (footprint "eagle-import:1206")
      (libsource (lib "eagle-import") (part "C1206"))
    )
    (comp (ref "C30")
      (value "100uF")
      (footprint "eagle-import:1206")
      (libsource (lib "eagle-import") (part "C1206"))
    )
    (comp (ref "C31")
      (value "100uF")
      (footprint "eagle-import:1206")
      (libsource (lib "eagle-import") (part "C1206"))
    )
    (comp (ref "C32")
      (value "100uF")
      (footprint "eagle-import:1206")
      (libsource (lib "eagle-import") (part "C1206"))
    )
    (comp (ref "D3")
      (value "PS04LTVA1")
      (footprint "eagle-import:D0402")
      (libsource (lib "eagle-import") (part "ESD-DIODE"))
    )
    (comp (ref "D4")
      (value "PS04LTVA1")
      (footprint "eagle-import:D0402")
      (libsource (lib "eagle-import") (part "ESD-DIODE"))
    )
    (comp (ref "D5")
      (value "B72590D50A060")
      (footprint "eagle-import:D0402")
      (libsource (lib "eagle-import") (part "ESD-DIODE"))
    )
    (comp (ref "D6")
      (value "B72590D50A060")
      (footprint "eagle-import:D0402")
      (libsource (lib "eagle-import") (part "ESD-DIODE"))
    )
    (comp (ref "D7")
      (value "PS04LTVA1")
      (footprint "eagle-import:D0402")
      (libsource (lib "eagle-import") (part "ESD-DIODE"))
    )
    (comp (ref "D8")
      (value "PS04LTVA1")
      (footprint "eagle-import:D0402")
      (libsource (lib "eagle-import") (part "ESD-DIODE"))
    )
    (comp (ref "D9")
      (value "B72590D50A060")
      (footprint "eagle-import:D0402")
      (libsource (lib "eagle-import") (part "ESD-DIODE"))
    )
    (comp (ref "FB1")
      (value "120R 1A")
      (footprint "eagle-import:0402")
      (libsource (lib "eagle-import") (part "FB0402"))
    )
    (comp (ref "FB2")
      (value "120R 1A")
      (footprint "eagle-import:0402")
      (libsource (lib "eagle-import") (part "FB0402"))
    )
    (comp (ref "FB3")
      (value "120R 1A")
      (footprint "eagle-import:0402")
      (libsource (lib "eagle-import") (part "FB0402"))
    )
    (comp (ref "FB4")
      (value "120R 1A")
      (footprint "eagle-import:0402")
      (libsource (lib "eagle-import") (part "FB0402"))
    )
    (comp (ref "K1")
      (value "61400826021")
      (footprint "eagle-import:61400826021")
      (libsource (lib "eagle-import") (part "61400826021"))
    )
    (comp (ref "L3")
      (value "DLP11SN900HL2")
      (footprint "eagle-import:0504-DLP11S")
      (libsource (lib "eagle-import") (part "COM_MODE_CHOKE"))
    )
    (comp (ref "L4")
      (value "DLP11SN900HL2")
      (footprint "eagle-import:0504-DLP11S")
      (libsource (lib "eagle-import") (part "COM_MODE_CHOKE"))
    )
    (comp (ref "U14")
      (value "TPS2052B")
      (footprint "eagle-import:MSOP8-PAD")
      (libsource (lib "eagle-import") (part "TPS2052"))
    )
  )
  (nets
    (net (code "1") (name "3V_DISPLAY_EN$43") (class "Default")
      (node (ref "U$67") (pin "38") (pinfunction "1A6_38") (pintype "bidirectional"))
      (node (ref "U$70") (pin "31") (pinfunction "DISP_31") (pintype "output"))
    )
    (net (code "2") (name "3V_L_BIAS$43") (class "Default")
      (node (ref "U$67") (pin "43") (pinfunction "1A3_43") (pintype "bidirectional"))
      (node (ref "U$70") (pin "34") (pinfunction "DE_34") (pintype "output"))
    )
    (net (code "3") (name "3V_L_FCLK$43") (class "Default")
      (node (ref "U$67") (pin "41") (pinfunction "1A4_41") (pintype "bidirectional"))
      (node (ref "U$70") (pin "33") (pinfunction "VSYNC_33") (pintype "output"))
    )
    (net (code "4") (name "3V_L_LCLK$43") (class "Default")
      (node (ref "U$67") (pin "40") (pinfunction "1A5_40") (pintype "bidirectional"))
      (node (ref "U$70") (pin "32") (pinfunction "HSYNC_32") (pintype "output"))
    )
    (net (code "5") (name "3V_L_PCLK$43") (class "Default")
      (node (ref "U$67") (pin "37") (pinfunction "1A7_37") (pintype "bidirectional"))
      (node (ref "U$70") (pin "30") (pinfunction "PCLK_30") (pintype "output"))
    )
    (net (code "6") (name "3V_MISO$43") (class "Default")
      (node (ref "U$66") (pin "16") (pinfunction "DOUT_16") (pintype "bidirectional"))
      (node (ref "U$69") (pin "41") (pinfunction "1A4_41") (pintype "bidirectional"))
    )
    (net (code "7") (name "3V_MOSI$43") (class "Default")
      (node (ref "U$66") (pin "2") (pinfunction "DIN_2") (pintype "bidirectional"))
      (node (ref "U$67") (pin "44") (pinfunction "1A2_44") (pintype "bidirectional"))
    )
    (net (code "8") (name "3V_NPENIRQ$43") (class "Default")
      (node (ref "R95") (pin "2") (pinfunction "2_2") (pintype "passive"))
      (node (ref "U$66") (pin "15") (pinfunction "NPENIRQ_15") (pintype "bidirectional"))
      (node (ref "U$69") (pin "38") (pinfunction "1A6_38") (pintype "bidirectional"))
    )
    (net (code "9") (name "3V_SPI_CLK$43") (class "Default")
      (node (ref "U$66") (pin "4") (pinfunction "DCLK_4") (pintype "bidirectional"))
      (node (ref "U$67") (pin "47") (pinfunction "1A0_47") (pintype "bidirectional"))
    )
    (net (code "10") (name "3V_TS_BUSY$43") (class "Default")
      (node (ref "U$66") (pin "1") (pinfunction "BUSY_1") (pintype "bidirectional"))
    )
    (net (code "11") (name "4.VCC_BATT") (class "Default")
      (node (ref "F3") (pin "2") (pinfunction "2_2") (pintype "passive"))
      (node (ref "Q6") (pin "3") (pinfunction "S_3") (pintype "passive"))
      (node (ref "R19") (pin "2") (pinfunction "2_2") (pintype "passive"))
      (node (ref "R88") (pin "1") (pinfunction "1_1") (pintype "passive"))
    )
    (net (code "12") (name "5V_1$2") (class "Default")
      (node (ref "F1") (pin "1") (pinfunction "1_1") (pintype "passive"))
      (node (ref "J2") (pin "B2") (pinfunction "B2_B2") (pintype "bidirectional"))
    )
    (net (code "13") (name "5V_1$28") (class "Default")
      (node (ref "F4") (pin "1") (pinfunction "1_1") (pintype "passive"))
      (node (ref "J9") (pin "B2") (pinfunction "B2_B2") (pintype "bidirectional"))
    )
    (net (code "14") (name "5V_2$2") (class "Default")
      (node (ref "F2") (pin "1") (pinfunction "1_1") (pintype "passive"))
      (node (ref "J2") (pin "A2") (pinfunction "A2_A2") (pintype "bidirectional"))
    )
    (net (code "15") (name "5V_2$28") (class "Default")
      (node (ref "F5") (pin "1") (pinfunction "1_1") (pintype "passive"))
      (node (ref "J9") (pin "A2") (pinfunction "A2_A2") (pintype "bidirectional"))
    )
    (net (code "16") (name "5V_SCL$44") (class "Default")
      (node (ref "D29") (pin "P2") (pinfunction "P2_P2") (pintype "passive"))
      (node (ref "J15") (pin "17") (pinfunction "15_17") (pintype "passive"))
      (node (ref "R112") (pin "2") (pinfunction "2_2") (pintype "passive"))
      (node (ref "U33") (pin "6") (pinfunction "SCL2_6") (pintype "bidirectional"))
    )
    (net (code "17") (name "5V_SDA$44") (class "Default")
      (node (ref "D30") (pin "P2") (pinfunction "P2_P2") (pintype "passive"))
      (node (ref "J15") (pin "18") (pinfunction "16_18") (pintype "passive"))
      (node (ref "R109") (pin "2") (pinfunction "2_2") (pintype "passive"))
      (node (ref "U33") (pin "5") (pinfunction "SDA2_5") (pintype "bidirectional"))
    )
    (net (code "18") (name "9.VCC_BATT_NOFUSE") (class "Default")
      (node (ref "C61") (pin "1") (pinfunction "1_1") (pintype "passive"))
      (node (ref "C62") (pin "1") (pinfunction "1_1") (pintype "passive"))
      (node (ref "C63") (pin "1") (pinfunction "1_1") (pintype "passive"))
      (node (ref "IC2") (pin "2") (pinfunction "VIN_2") (pintype "power_in"))
      (node (ref "IC2") (pin "3") (pinfunction "VIN_3") (pintype "power_in"))
      (node (ref "IC2") (pin "4") (pinfunction "EN_4") (pintype "input"))
      (node (ref "IC2") (pin "8") (pinfunction "VIN_8") (pintype "power_in"))
      (node (ref "Q6") (pin "2") (pinfunction "D_2") (pintype "passive"))
      (node (ref "Q6") (pin "4") (pinfunction "D_4") (pintype "passive"))
      (node (ref "R140") (pin "1") (pinfunction "1_1") (pintype "passive"))
      (node (ref "R52") (pin "1") (pinfunction "1_1") (pintype "passive"))
      (node (ref "TP1") (pin "1") (pinfunction "TP_1") (pintype "bidirectional"))
      (node (ref "TP2") (pin "1") (pinfunction "TP_1") (pintype "bidirectional"))
    )
    (net (code "19") (name "9.VCC_BATT_OUT") (class "Default")
      (node (ref "C107") (pin "+") (pinfunction "1_+") (pintype "passive"))
      (node (ref "C108") (pin "1") (pinfunction "1_1") (pintype "passive"))
      (node (ref "C109") (pin "1") (pinfunction "1_1") (pintype "passive"))
      (node (ref "C11") (pin "+") (pinfunction "1_+") (pintype "passive"))
      (node (ref "C12") (pin "1") (pinfunction "1_1") (pintype "passive"))
      (node (ref "C13") (pin "1") (pinfunction "1_1") (pintype "passive"))
      (node (ref "Q1") (pin "2") (pinfunction "D_2") (pintype "passive"))
      (node (ref "Q1") (pin "4") (pinfunction "D_4") (pintype "passive"))
      (node (ref "U23") (pin "13") (pinfunction "VM2_13") (pintype "bidirectional"))
      (node (ref "U23") (pin "14") (pinfunction "VM3_14") (pintype "bidirectional"))
      (node (ref "U23") (pin "24") (pinfunction "VM1_24") (pintype "bidirectional"))
      (node (ref "U4") (pin "13") (pinfunction "VM2_13") (pintype "bidirectional"))
      (node (ref "U4") (pin "14") (pinfunction "VM3_14") (pintype "bidirectional"))
      (node (ref "U4") (pin "24") (pinfunction "VM1_24") (pintype "bidirectional"))
    )
    (net (code "20") (name "15.HSO_L") (class "Default")
      (node (ref "C67") (pin "2") (pinfunction "2_2") (pintype "passive"))
      (node (ref "U15") (pin "18") (pinfunction "HPLOUT_18") (pintype "bidirectional"))
    )
    (net (code "21") (name "17.VCC_1.8") (class "Default")
      (node (ref "C112") (pin "1") (pinfunction "1_1") (pintype "passive"))
      (node (ref "C117") (pin "1") (pinfunction "1_1") (pintype "passive"))
      (node (ref "C139") (pin "1") (pinfunction "1_1") (pintype "passive"))
      (node (ref "C149") (pin "1") (pinfunction "1_1") (pintype "passive"))
      (node (ref "C150") (pin "1") (pinfunction "1_1") (pintype "passive"))
      (node (ref "C152") (pin "1") (pinfunction "1_1") (pintype "passive"))
      (node (ref "C16") (pin "1") (pinfunction "1_1") (pintype "passive"))
      (node (ref "C161") (pin "1") (pinfunction "1_1") (pintype "passive"))
      (node (ref "C18") (pin "1") (pinfunction "1_1") (pintype "passive"))
      (node (ref "C3") (pin "1") (pinfunction "1_1") (pintype "passive"))
      (node (ref "C40") (pin "1") (pinfunction "1_1") (pintype "passive"))
      (node (ref "C41") (pin "1") (pinfunction "1_1") (pintype "passive"))
      (node (ref "C42") (pin "1") (pinfunction "1_1") (pintype "passive"))
      (node (ref "C51") (pin "1") (pinfunction "1_1") (pintype "passive"))
      (node (ref "C55") (pin "1") (pinfunction "1_1") (pintype "passive"))
      (node (ref "C58") (pin "1") (pinfunction "1_1") (pintype "passive"))
      (node (ref "C59") (pin "1") (pinfunction "1_1") (pintype "passive"))
      (node (ref "FB6") (pin "1") (pinfunction "1_1") (pintype "passive"))
      (node (ref "IC1") (pin "5") (pinfunction "VSENSE_5") (pintype "input"))
      (node (ref "IC1") (pin "7") (pinfunction "VOUT_7") (pintype "power_in"))
      (node (ref "IC1") (pin "8") (pinfunction "VOUT_8") (pintype "power_in"))
      (node (ref "R107") (pin "1") (pinfunction "1_1") (pintype "passive"))
      (node (ref "R108") (pin "1") (pinfunction "1_1") (pintype "passive"))
      (node (ref "R26") (pin "2") (pinfunction "2_2") (pintype "passive"))
      (node (ref "R29") (pin "2") (pinfunction "2_2") (pintype "passive"))
      (node (ref "R3") (pin "2") (pinfunction "2_2") (pintype "passive"))
      (node (ref "R31") (pin "1") (pinfunction "1_1") (pintype "passive"))
      (node (ref "R99") (pin "2") (pinfunction "2_2") (pintype "passive"))
      (node (ref "RP5") (pin "10") (pinfunction "10_10") (pintype "passive"))
      (node (ref "RP5") (pin "11") (pinfunction "11_11") (pintype "passive"))
      (node (ref "RP5") (pin "12") (pinfunction "12_12") (pintype "passive"))
      (node (ref "RP5") (pin "13") (pinfunction "13_13") (pintype "passive"))
      (node (ref "RP5") (pin "14") (pinfunction "14_14") (pintype "passive"))
      (node (ref "RP5") (pin "15") (pinfunction "15_15") (pintype "passive"))
      (node (ref "RP5") (pin "16") (pinfunction "16_16") (pintype "passive"))
      (node (ref "RP5") (pin "9") (pinfunction "9_9") (pintype "passive"))
      (node (ref "U$67") (pin "18") (pinfunction "VCCB_18") (pintype "power_in"))
      (node (ref "U$67") (pin "7") (pinfunction "VCCB_7") (pintype "power_in"))
      (node (ref "U$68") (pin "18") (pinfunction "VCCB_18") (pintype "power_in"))
      (node (ref "U$68") (pin "7") (pinfunction "VCCB_7") (pintype "power_in"))
      (node (ref "U$69") (pin "18") (pinfunction "VCCB_18") (pintype "power_in"))
      (node (ref "U$69") (pin "7") (pinfunction "VCCB_7") (pintype "power_in"))
      (node (ref "U1") (pin "1") (pinfunction "VCCA_1") (pintype "power_in"))
      (node (ref "U1") (pin "5") (pinfunction "OE_5") (pintype "input"))
      (node (ref "U10") (pin "1") (pinfunction "VCCA_1") (pintype "power_in"))
      (node (ref "U10") (pin "5") (pinfunction "OE_5") (pintype "input"))
      (node (ref "U15") (pin "36") (pinfunction "DVDD_36") (pintype "bidirectional"))
      (node (ref "U15") (pin "44") (pinfunction "IOVDD_44") (pintype "bidirectional"))
      (node (ref "U16") (pin "1") (pinfunction "2DIR_1") (pintype "input"))
      (node (ref "U16") (pin "7") (pinfunction "VCCA_7") (pintype "power_in"))
      (node (ref "U27") (pin "1") (pinfunction "VCCA_1") (pintype "power_in"))
      (node (ref "U27") (pin "5") (pinfunction "OE_5") (pintype "input"))
      (node (ref "U3") (pin "8") (pinfunction "VCC_8") (pintype "power_in"))
      (node (ref "U32") (pin "1") (pinfunction "VCCA_1") (pintype "power_in"))
      (node (ref "U32") (pin "5") (pinfunction "OE_5") (pintype "input"))
      (node (ref "U33") (pin "2") (pinfunction "VREF1_2") (pintype "input"))
      (node (ref "U8") (pin "10") (pinfunction "OE_10") (pintype "input"))
      (node (ref "U8") (pin "2") (pinfunction "VCCA_2") (pintype "power_in"))
      (node (ref "X2") (pin "1") (pinfunction "OE_1") (pintype "input"))
      (node (ref "X2") (pin "4") (pinfunction "VCC_4") (pintype "power_in"))
    )
    (net (code "22") (name "18.VCC_3.3") (class "Default")
      (node (ref "C10") (pin "1") (pinfunction "1_1") (pintype "passive"))
      (node (ref "C101") (pin "1") (pinfunction "1_1") (pintype "passive"))
      (node (ref "C106") (pin "1") (pinfunction "1_1") (pintype "passive"))
      (node (ref "C116") (pin "1") (pinfunction "1_1") (pintype "passive"))
      (node (ref "C118") (pin "1") (pinfunction "1_1") (pintype "passive"))
      (node (ref "C119") (pin "1") (pinfunction "1_1") (pintype "passive"))
      (node (ref "C124") (pin "1") (pinfunction "1_1") (pintype "passive"))
      (node (ref "C125") (pin "1") (pinfunction "1_1") (pintype "passive"))
      (node (ref "C126") (pin "1") (pinfunction "1_1") (pintype "passive"))
      (node (ref "C127") (pin "1") (pinfunction "1_1") (pintype "passive"))
      (node (ref "C128") (pin "1") (pinfunction "1_1") (pintype "passive"))
      (node (ref "C129") (pin "1") (pinfunction "1_1") (pintype "passive"))
      (node (ref "C130") (pin "1") (pinfunction "1_1") (pintype "passive"))
      (node (ref "C137") (pin "1") (pinfunction "1_1") (pintype "passive"))
      (node (ref "C138") (pin "1") (pinfunction "1_1") (pintype "passive"))
      (node (ref "C140") (pin "1") (pinfunction "1_1") (pintype "passive"))
      (node (ref "C141") (pin "1") (pinfunction "1_1") (pintype "passive"))
      (node (ref "C144") (pin "1") (pinfunction "1_1") (pintype "passive"))
      (node (ref "C146") (pin "1") (pinfunction "1_1") (pintype "passive"))
      (node (ref "C147") (pin "1") (pinfunction "1_1") (pintype "passive"))
      (node (ref "C148") (pin "1") (pinfunction "1_1") (pintype "passive"))
      (node (ref "C151") (pin "1") (pinfunction "1_1") (pintype "passive"))
      (node (ref "C155") (pin "1") (pinfunction "1_1") (pintype "passive"))
      (node (ref "C156") (pin "1") (pinfunction "1_1") (pintype "passive"))
      (node (ref "C157") (pin "1") (pinfunction "1_1") (pintype "passive"))
      (node (ref "C158") (pin "1") (pinfunction "1_1") (pintype "passive"))
      (node (ref "C17") (pin "1") (pinfunction "1_1") (pintype "passive"))
      (node (ref "C19") (pin "1") (pinfunction "1_1") (pintype "passive"))
      (node (ref "C20") (pin "1") (pinfunction "1_1") (pintype "passive"))
      (node (ref "C21") (pin "1") (pinfunction "1_1") (pintype "passive"))
      (node (ref "C267") (pin "1") (pinfunction "1_1") (pintype "passive"))
      (node (ref "C269") (pin "1") (pinfunction "1_1") (pintype "passive"))
      (node (ref "C272") (pin "1") (pinfunction "1_1") (pintype "passive"))
      (node (ref "C273") (pin "1") (pinfunction "1_1") (pintype "passive"))
      (node (ref "C274") (pin "1") (pinfunction "1_1") (pintype "passive"))
      (node (ref "C275") (pin "1") (pinfunction "1_1") (pintype "passive"))
      (node (ref "C33") (pin "1") (pinfunction "1_1") (pintype "passive"))
      (node (ref "C34") (pin "1") (pinfunction "1_1") (pintype "passive"))
      (node (ref "C35") (pin "1") (pinfunction "1_1") (pintype "passive"))
      (node (ref "C36") (pin "1") (pinfunction "1_1") (pintype "passive"))
      (node (ref "C37") (pin "1") (pinfunction "1_1") (pintype "passive"))
      (node (ref "C38") (pin "1") (pinfunction "1_1") (pintype "passive"))
      (node (ref "C39") (pin "1") (pinfunction "1_1") (pintype "passive"))
      (node (ref "C56") (pin "1") (pinfunction "1_1") (pintype "passive"))
      (node (ref "C57") (pin "1") (pinfunction "1_1") (pintype "passive"))
      (node (ref "C6") (pin "1") (pinfunction "1_1") (pintype "passive"))
      (node (ref "C60") (pin "1") (pinfunction "1_1") (pintype "passive"))
      (node (ref "C64") (pin "1") (pinfunction "1_1") (pintype "passive"))
      (node (ref "C69") (pin "1") (pinfunction "1_1") (pintype "passive"))
      (node (ref "C75") (pin "1") (pinfunction "1_1") (pintype "passive"))
      (node (ref "C76") (pin "1") (pinfunction "1_1") (pintype "passive"))
      (node (ref "C77") (pin "1") (pinfunction "1_1") (pintype "passive"))
      (node (ref "C78") (pin "1") (pinfunction "1_1") (pintype "passive"))
      (node (ref "C79") (pin "1") (pinfunction "1_1") (pintype "passive"))
      (node (ref "C80") (pin "1") (pinfunction "1_1") (pintype "passive"))
      (node (ref "C81") (pin "1") (pinfunction "1_1") (pintype "passive"))
      (node (ref "C82") (pin "1") (pinfunction "1_1") (pintype "passive"))
      (node (ref "C91") (pin "1") (pinfunction "1_1") (pintype "passive"))
      (node (ref "C92") (pin "1") (pinfunction "1_1") (pintype "passive"))
      (node (ref "C93") (pin "1") (pinfunction "1_1") (pintype "passive"))
      (node (ref "C96") (pin "1") (pinfunction "1_1") (pintype "passive"))
      (node (ref "FB5") (pin "1") (pinfunction "1_1") (pintype "passive"))
      (node (ref "FB7") (pin "1") (pinfunction "1_1") (pintype "passive"))
      (node (ref "FB8") (pin "1") (pinfunction "1_1") (pintype "passive"))
      (node (ref "FB9") (pin "2") (pinfunction "2_2") (pintype "passive"))
      (node (ref "IC1") (pin "11") (pinfunction "VS1_11") (pintype "input"))
      (node (ref "IC1") (pin "14") (pinfunction "VIN_14") (pintype "input"))
      (node (ref "IC3") (pin "100") (pinfunction "VDD_3_100") (pintype "power_in"))
      (node (ref "IC3") (pin "11") (pinfunction "VDD_5_11") (pintype "power_in"))
      (node (ref "IC3") (pin "19") (pinfunction "VSSA_OR_VDD_19") (pintype "power_in"))
      (node (ref "IC3") (pin "28") (pinfunction "VDD_4_28") (pintype "power_in"))
      (node (ref "IC3") (pin "50") (pinfunction "VDD_1_50") (pintype "power_in"))
      (node (ref "IC3") (pin "75") (pinfunction "VDD_2_75") (pintype "power_in"))
      (node (ref "IC4") (pin "1") (pinfunction "VDD_1") (pintype "power_in"))
      (node (ref "IC4") (pin "12") (pinfunction "VDD_12") (pintype "power_in"))
      (node (ref "IC4") (pin "33") (pinfunction "VDD_33") (pintype "power_in"))
      (node (ref "J5") (pin "B1") (pinfunction "2_B1") (pintype "passive"))
      (node (ref "J5") (pin "B2") (pinfunction "4_B2") (pintype "passive"))
      (node (ref "J5") (pin "B3") (pinfunction "6_B3") (pintype "passive"))
      (node (ref "J5") (pin "B4") (pinfunction "8_B4") (pintype "passive"))
      (node (ref "J5") (pin "B5") (pinfunction "10_B5") (pintype "passive"))
      (node (ref "J5") (pin "B6") (pinfunction "12_B6") (pintype "passive"))
      (node (ref "JTAG") (pin "1") (pinfunction "S_1") (pintype "passive"))
      (node (ref "L1") (pin "2") (pinfunction "2_2") (pintype "passive"))
      (node (ref "R1") (pin "2") (pinfunction "2_2") (pintype "passive"))
      (node (ref "R104") (pin "1") (pinfunction "1_1") (pintype "passive"))
      (node (ref "R105") (pin "2") (pinfunction "2_2") (pintype "passive"))
      (node (ref "R111") (pin "2") (pinfunction "2_2") (pintype "passive"))
      (node (ref "R136") (pin "2") (pinfunction "2_2") (pintype "passive"))
      (node (ref "R137") (pin "2") (pinfunction "2_2") (pintype "passive"))
      (node (ref "R138") (pin "2") (pinfunction "2_2") (pintype "passive"))
      (node (ref "R139") (pin "2") (pinfunction "2_2") (pintype "passive"))
      (node (ref "R143") (pin "1") (pinfunction "1_1") (pintype "passive"))
      (node (ref "R15") (pin "2") (pinfunction "2_2") (pintype "passive"))
      (node (ref "R23") (pin "1") (pinfunction "1_1") (pintype "passive"))
      (node (ref "R38") (pin "2") (pinfunction "2_2") (pintype "passive"))
      (node (ref "R39") (pin "2") (pinfunction "2_2") (pintype "passive"))
      (node (ref "R44") (pin "1") (pinfunction "1_1") (pintype "passive"))
      (node (ref "R45") (pin "2") (pinfunction "2_2") (pintype "passive"))
      (node (ref "R55") (pin "1") (pinfunction "1_1") (pintype "passive"))
      (node (ref "R58") (pin "1") (pinfunction "1_1") (pintype "passive"))
      (node (ref "R61") (pin "2") (pinfunction "2_2") (pintype "passive"))
      (node (ref "R63") (pin "2") (pinfunction "2_2") (pintype "passive"))
      (node (ref "R68") (pin "2") (pinfunction "2_2") (pintype "passive"))
      (node (ref "R75") (pin "2") (pinfunction "2_2") (pintype "passive"))
      (node (ref "R78") (pin "2") (pinfunction "2_2") (pintype "passive"))
      (node (ref "R79") (pin "2") (pinfunction "2_2") (pintype "passive"))
      (node (ref "R8") (pin "2") (pinfunction "2_2") (pintype "passive"))
      (node (ref "R90") (pin "1") (pinfunction "1_1") (pintype "passive"))
      (node (ref "R95") (pin "1") (pinfunction "1_1") (pintype "passive"))
      (node (ref "R96") (pin "1") (pinfunction "1_1") (pintype "passive"))
      (node (ref "R98") (pin "1") (pinfunction "1_1") (pintype "passive"))
      (node (ref "RP2") (pin "1") (pinfunction "1_1") (pintype "passive"))
      (node (ref "RP2") (pin "2") (pinfunction "2_2") (pintype "passive"))
      (node (ref "RP2") (pin "3") (pinfunction "3_3") (pintype "passive"))
      (node (ref "RP2") (pin "4") (pinfunction "4_4") (pintype "passive"))
      (node (ref "RP2") (pin "5") (pinfunction "5_5") (pintype "passive"))
      (node (ref "RP2") (pin "6") (pinfunction "6_6") (pintype "passive"))
      (node (ref "RP2") (pin "7") (pinfunction "7_7") (pintype "passive"))
      (node (ref "RP2") (pin "8") (pinfunction "8_8") (pintype "passive"))
      (node (ref "U$30") (pin "4") (pinfunction "VDD_4") (pintype "bidirectional"))
      (node (ref "U$66") (pin "14") (pinfunction "VCC_14") (pintype "bidirectional"))
      (node (ref "U$66") (pin "5") (pinfunction "VCC_5") (pintype "bidirectional"))
      (node (ref "U$67") (pin "31") (pinfunction "VCCA_31") (pintype "power_in"))
      (node (ref "U$67") (pin "42") (pinfunction "VCCA_42") (pintype "power_in"))
      (node (ref "U$68") (pin "31") (pinfunction "VCCA_31") (pintype "power_in"))
      (node (ref "U$68") (pin "42") (pinfunction "VCCA_42") (pintype "power_in"))
      (node (ref "U$69") (pin "1") (pinfunction "1DIR_1") (pintype "input"))
      (node (ref "U$69") (pin "31") (pinfunction "VCCA_31") (pintype "power_in"))
      (node (ref "U$69") (pin "42") (pinfunction "VCCA_42") (pintype "power_in"))
      (node (ref "U$70") (pin "4") (pinfunction "VDD_4") (pintype "power_in"))
      (node (ref "U10") (pin "8") (pinfunction "VCCB_8") (pintype "power_in"))
      (node (ref "U11") (pin "1") (pinfunction "VCCA_1") (pintype "power_in"))
      (node (ref "U11") (pin "5") (pinfunction "OE_5") (pintype "input"))
      (node (ref "U15") (pin "16") (pinfunction "DRVDD.1_16") (pintype "bidirectional"))
      (node (ref "U15") (pin "17") (pinfunction "DRVDD.2_17") (pintype "bidirectional"))
      (node (ref "U15") (pin "24") (pinfunction "AVDD_ADC_24") (pintype "bidirectional"))
      (node (ref "U15") (pin "25") (pinfunction "AVDD_DAC_25") (pintype "bidirectional"))
      (node (ref "U16") (pin "6") (pinfunction "VCCB_6") (pintype "power_in"))
      (node (ref "U17") (pin "6") (pinfunction "VDD_6") (pintype "power_in"))
      (node (ref "U18") (pin "10") (pinfunction "VDD33_10") (pintype "power_in"))
      (node (ref "U18") (pin "15") (pinfunction "VDD33_15") (pintype "power_in"))
      (node (ref "U18") (pin "23") (pinfunction "VDD33_23") (pintype "power_in"))
      (node (ref "U18") (pin "29") (pinfunction "VDD33_29") (pintype "power_in"))
      (node (ref "U18") (pin "36") (pinfunction "VDD33_36") (pintype "power_in"))
      (node (ref "U18") (pin "5") (pinfunction "VDD33_5") (pintype "power_in"))
      (node (ref "U2") (pin "1") (pinfunction "VCCA_1") (pintype "power_in"))
      (node (ref "U2") (pin "5") (pinfunction "OE_5") (pintype "input"))
      (node (ref "U20") (pin "10") (pinfunction "OE_10") (pintype "input"))
      (node (ref "U20") (pin "2") (pinfunction "VCCA_2") (pintype "power_in"))
      (node (ref "U21") (pin "1") (pinfunction "VCCA_1") (pintype "power_in"))
      (node (ref "U21") (pin "5") (pinfunction "OE_5") (pintype "input"))
      (node (ref "U22") (pin "1") (pinfunction "VCCA_1") (pintype "power_in"))
      (node (ref "U22") (pin "5") (pinfunction "OE_5") (pintype "input"))
      (node (ref "U23") (pin "19") (pinfunction "STBY_19") (pintype "bidirectional"))
      (node (ref "U23") (pin "20") (pinfunction "VCC_20") (pintype "bidirectional"))
      (node (ref "U29") (pin "10") (pinfunction "OE_10") (pintype "input"))
      (node (ref "U29") (pin "2") (pinfunction "VCCA_2") (pintype "power_in"))
      (node (ref "U30") (pin "1") (pinfunction "VCCA_1") (pintype "power_in"))
      (node (ref "U30") (pin "5") (pinfunction "OE_5") (pintype "input"))
      (node (ref "U31") (pin "1") (pinfunction "A_1") (pintype "passive"))
      (node (ref "U31") (pin "2") (pinfunction "A'_2") (pintype "passive"))
      (node (ref "U32") (pin "8") (pinfunction "VCCB_8") (pintype "power_in"))
      (node (ref "U36") (pin "P1") (pinfunction "VDD_IO_P1") (pintype "power_in"))
      (node (ref "U36") (pin "P15") (pinfunction "RSVD_VDD_P15") (pintype "power_in"))
      (node (ref "U36") (pin "P16") (pinfunction "VDD_P16") (pintype "power_in"))
      (node (ref "U37") (pin "1") (pinfunction "VDD_IO_1") (pintype "power_in"))
      (node (ref "U37") (pin "14") (pinfunction "VDD_14") (pintype "power_in"))
      (node (ref "U4") (pin "19") (pinfunction "STBY_19") (pintype "bidirectional"))
      (node (ref "U4") (pin "20") (pinfunction "VCC_20") (pintype "bidirectional"))
      (node (ref "U8") (pin "19") (pinfunction "VCCB_19") (pintype "power_in"))
      (node (ref "VCC1") (pin "1") (pinfunction "TP_1") (pintype "bidirectional"))
    )
    (net (code "23") (name "20.USBH1_N") (class "Default")
      (node (ref "L3") (pin "2") (pinfunction "2_2") (pintype "passive"))
      (node (ref "U18") (pin "1") (pinfunction "USBDM_DN1_1") (pintype "bidirectional"))
    )
    (net (code "24") (name "20.USBH1_NOC") (class "Default")
      (node (ref "U14") (pin "8") (pinfunction "NOC1_8") (pintype "output"))
      (node (ref "U18") (pin "13") (pinfunction "OCS_N1_13") (pintype "bidirectional"))
    )
    (net (code "25") (name "20.USBH1_P") (class "Default")
      (node (ref "L3") (pin "3") (pinfunction "3_3") (pintype "passive"))
      (node (ref "U18") (pin "2") (pinfunction "USBDP_DN1_2") (pintype "bidirectional"))
    )
    (net (code "26") (name "20.USBH1_PWREN") (class "Default")
      (node (ref "U14") (pin "3") (pinfunction "EN1_3") (pintype "bidirectional"))
      (node (ref "U18") (pin "12") (pinfunction "PRTPWR1_12") (pintype "bidirectional"))
    )
    (net (code "27") (name "20.USBH1_VBUS") (class "Default")
      (node (ref "D5") (pin "P2") (pinfunction "P2_P2") (pintype "passive"))
      (node (ref "FB4") (pin "2") (pinfunction "2_2") (pintype "passive"))
      (node (ref "U14") (pin "7") (pinfunction "OUT1_7") (pintype "power_in"))
    )
    (net (code "28") (name "20.USBH2_N") (class "Default")
      (node (ref "L4") (pin "2") (pinfunction "2_2") (pintype "passive"))
      (node (ref "U18") (pin "3") (pinfunction "USBDM_DN2_3") (pintype "bidirectional"))
    )
    (net (code "29") (name "20.USBH2_NOC") (class "Default")
      (node (ref "U14") (pin "5") (pinfunction "NOC2_5") (pintype "output"))
      (node (ref "U18") (pin "17") (pinfunction "OCS_N2_17") (pintype "bidirectional"))
    )
    (net (code "30") (name "20.USBH2_P") (class "Default")
      (node (ref "L4") (pin "3") (pinfunction "3_3") (pintype "passive"))
      (node (ref "U18") (pin "4") (pinfunction "USBDP_DN2_4") (pintype "bidirectional"))
    )
    (net (code "31") (name "20.USBH2_PWREN") (class "Default")
      (node (ref "U14") (pin "4") (pinfunction "EN2_4") (pintype "bidirectional"))
      (node (ref "U18") (pin "16") (pinfunction "PRTPWR2_16") (pintype "bidirectional"))
    )
    (net (code "32") (name "20.USBH2_VBUS") (class "Default")
      (node (ref "D9") (pin "P2") (pinfunction "P2_P2") (pintype "passive"))
      (node (ref "FB3") (pin "2") (pinfunction "2_2") (pintype "passive"))
      (node (ref "U14") (pin "6") (pinfunction "OUT2_6") (pintype "power_in"))
    )
    (net (code "33") (name "21.VCC_6.0") (class "Default")
      (node (ref "C100") (pin "1") (pinfunction "1_1") (pintype "passive"))
      (node (ref "C102") (pin "1") (pinfunction "1_1") (pintype "passive"))
      (node (ref "C103") (pin "1") (pinfunction "1_1") (pintype "passive"))
      (node (ref "C4") (pin "1") (pinfunction "1_1") (pintype "passive"))
      (node (ref "C5") (pin "1") (pinfunction "1_1") (pintype "passive"))
      (node (ref "C7") (pin "1") (pinfunction "1_1") (pintype "passive"))
      (node (ref "C8") (pin "1") (pinfunction "1_1") (pintype "passive"))
      (node (ref "C89") (pin "1") (pinfunction "1_1") (pintype "passive"))
      (node (ref "C90") (pin "+") (pinfunction "1_+") (pintype "passive"))
      (node (ref "C99") (pin "1") (pinfunction "1_1") (pintype "passive"))
      (node (ref "F1") (pin "2") (pinfunction "2_2") (pintype "passive"))
      (node (ref "F2") (pin "2") (pinfunction "2_2") (pintype "passive"))
      (node (ref "F4") (pin "2") (pinfunction "2_2") (pintype "passive"))
      (node (ref "F5") (pin "2") (pinfunction "2_2") (pintype "passive"))
      (node (ref "L2") (pin "2") (pinfunction "2_2") (pintype "passive"))
      (node (ref "R53") (pin "1") (pinfunction "1_1") (pintype "passive"))
      (node (ref "U2") (pin "8") (pinfunction "VCCB_8") (pintype "power_in"))
      (node (ref "U22") (pin "8") (pinfunction "VCCB_8") (pintype "power_in"))
    )
    (net (code "34") (name "22.MMC0_CLK") (class "Default")
      (node (ref "RP1") (pin "2") (pinfunction "2_2") (pintype "passive"))
      (node (ref "RP2") (pin "15") (pinfunction "15_15") (pintype "passive"))
      (node (ref "U$72") (pin "G17") (pinfunction "MMC0_CLK|GPMC_A24|UART3_CTSN|UART2_RXD|DCAN1_TX|PR1_PRU0_PRU_R30_12|PR1_PRU0_PRU_R31_12|GPIO2_30_G17") (pintype "bidirectional"))
    )
    (net (code "35") (name "22.MMC0_CMD") (class "Default")
      (node (ref "RP1") (pin "1") (pinfunction "1_1") (pintype "passive"))
      (node (ref "RP2") (pin "16") (pinfunction "16_16") (pintype "passive"))
      (node (ref "U$72") (pin "G18") (pinfunction "MMC0_CMD|GPMC_A25|UART3_RTSN|UART2_TXD|DCAN1_RX|PR1_PRU0_PRU_R30_13|PR1_PRU0_PRU_R31_13|GPIO2_31_G18") (pintype "bidirectional"))
    )
    (net (code "36") (name "22.MMC0_DAT0") (class "Default")
      (node (ref "RP1") (pin "5") (pinfunction "5_5") (pintype "passive"))
      (node (ref "RP2") (pin "14") (pinfunction "14_14") (pintype "passive"))
      (node (ref "U$72") (pin "G16") (pinfunction "MMC0_DAT0|GPMC_A23|UART5_RTSN|UART3_TXD|UART1_RIN|PR1_PRU0_PRU_R30_11|PR1_PRU0_PRU_R31_11|GPIO2_29_G16") (pintype "bidirectional"))
    )
    (net (code "37") (name "22.MMC0_DAT1") (class "Default")
      (node (ref "RP1") (pin "6") (pinfunction "6_6") (pintype "passive"))
      (node (ref "RP2") (pin "13") (pinfunction "13_13") (pintype "passive"))
      (node (ref "U$72") (pin "G15") (pinfunction "MMC0_DAT1|GPMC_A22|UART5_CTSN|UART3_RXD|UART1_DTRN|PR1_PRU0_PRU_R30_10|PR1_PRU0_PRU_R31_10|GPIO2_28_G15") (pintype "bidirectional"))
    )
    (net (code "38") (name "22.MMC0_DAT2") (class "Default")
      (node (ref "RP1") (pin "7") (pinfunction "7_7") (pintype "passive"))
      (node (ref "RP2") (pin "12") (pinfunction "12_12") (pintype "passive"))
      (node (ref "U$72") (pin "F18") (pinfunction "MMC0_DAT2|GPMC_A21|UART4_RTSN|TIMER6|UART1_DSRN|PR1_PRU0_PRU_R30_9|PR1_PRU0_PRU_R31_9|GPIO2_27_F18") (pintype "bidirectional"))
    )
    (net (code "39") (name "22.MMC0_DAT3") (class "Default")
      (node (ref "RP1") (pin "8") (pinfunction "8_8") (pintype "passive"))
      (node (ref "RP2") (pin "11") (pinfunction "11_11") (pintype "passive"))
      (node (ref "U$72") (pin "F17") (pinfunction "MMC0_DAT3|GPMC_A20|UART4_CTSN|TIMER5|UART1_DCDN|PR1_PRU0_PRU_R30_8|PR1_PRU0_PRU_R31_8|GPIO2_26_F17") (pintype "bidirectional"))
    )
    (net (code "40") (name "39.ADC12_IN4") (class "Default")
      (node (ref "C110") (pin "1") (pinfunction "1_1") (pintype "passive"))
      (node (ref "IC3") (pin "29") (pinfunction "PA4_29") (pintype "bidirectional"))
      (node (ref "R64") (pin "2") (pinfunction "2_2") (pintype "passive"))
      (node (ref "R66") (pin "1") (pinfunction "1_1") (pintype "passive"))
    )
    (net (code "41") (name "39.ADC12_IN5") (class "Default")
      (node (ref "C110") (pin "2") (pinfunction "2_2") (pintype "passive"))
      (node (ref "IC3") (pin "30") (pinfunction "PA5_30") (pintype "bidirectional"))
      (node (ref "R65") (pin "2") (pinfunction "2_2") (pintype "passive"))
      (node (ref "R67") (pin "1") (pinfunction "1_1") (pintype "passive"))
    )
    (net (code "42") (name "39.ADC12_IN6") (class "Default")
      (node (ref "C111") (pin "1") (pinfunction "1_1") (pintype "passive"))
      (node (ref "IC3") (pin "31") (pinfunction "PA6_31") (pintype "bidirectional"))
      (node (ref "R71") (pin "2") (pinfunction "2_2") (pintype "passive"))
      (node (ref "R73") (pin "1") (pinfunction "1_1") (pintype "passive"))
    )
    (net (code "43") (name "39.ADC12_IN7") (class "Default")
      (node (ref "C111") (pin "2") (pinfunction "2_2") (pintype "passive"))
      (node (ref "IC3") (pin "32") (pinfunction "PA7_32") (pintype "bidirectional"))
      (node (ref "R72") (pin "2") (pinfunction "2_2") (pintype "passive"))
      (node (ref "R74") (pin "1") (pinfunction "1_1") (pintype "passive"))
    )
    (net (code "44") (name "39.ADC12_IN9") (class "Default")
      (node (ref "IC3") (pin "36") (pinfunction "PB1_36") (pintype "bidirectional"))
      (node (ref "J4") (pin "1") (pinfunction "1_1") (pintype "passive"))
    )
    (net (code "45") (name "39.ADC12_IN14") (class "Default")
      (node (ref "IC3") (pin "33") (pinfunction "PC4_33") (pintype "bidirectional"))
      (node (ref "J4") (pin "5") (pinfunction "5_5") (pintype "passive"))
    )
    (net (code "46") (name "39.ADC12_IN15") (class "Default")
      (node (ref "IC3") (pin "34") (pinfunction "PC5_34") (pintype "bidirectional"))
      (node (ref "J4") (pin "6") (pinfunction "6_6") (pintype "passive"))
    )
    (net (code "47") (name "39.ADC123_IN0") (class "Default")
      (node (ref "C14") (pin "1") (pinfunction "1_1") (pintype "passive"))
      (node (ref "IC3") (pin "23") (pinfunction "PA0_23") (pintype "bidirectional"))
      (node (ref "R4") (pin "2") (pinfunction "2_2") (pintype "passive"))
      (node (ref "R6") (pin "1") (pinfunction "1_1") (pintype "passive"))
    )
    (net (code "48") (name "39.ADC123_IN1") (class "Default")
      (node (ref "C14") (pin "2") (pinfunction "2_2") (pintype "passive"))
      (node (ref "IC3") (pin "24") (pinfunction "PA1_24") (pintype "bidirectional"))
      (node (ref "R5") (pin "2") (pinfunction "2_2") (pintype "passive"))
      (node (ref "R7") (pin "1") (pinfunction "1_1") (pintype "passive"))
    )
    (net (code "49") (name "39.ADC123_IN2") (class "Default")
      (node (ref "C15") (pin "1") (pinfunction "1_1") (pintype "passive"))
      (node (ref "IC3") (pin "25") (pinfunction "PA2_25") (pintype "bidirectional"))
      (node (ref "R11") (pin "2") (pinfunction "2_2") (pintype "passive"))
      (node (ref "R13") (pin "1") (pinfunction "1_1") (pintype "passive"))
    )
    (net (code "50") (name "39.ADC123_IN3") (class "Default")
      (node (ref "C15") (pin "2") (pinfunction "2_2") (pintype "passive"))
      (node (ref "IC3") (pin "26") (pinfunction "PA3_26") (pintype "bidirectional"))
      (node (ref "R12") (pin "2") (pinfunction "2_2") (pintype "passive"))
      (node (ref "R14") (pin "1") (pinfunction "1_1") (pintype "passive"))
    )
    (net (code "51") (name "39.ADC123_IN11") (class "Default")
      (node (ref "IC3") (pin "16") (pinfunction "PC1_16") (pintype "bidirectional"))
      (node (ref "J4") (pin "2") (pinfunction "2_2") (pintype "passive"))
    )
    (net (code "52") (name "39.ADC123_IN12") (class "Default")
      (node (ref "IC3") (pin "17") (pinfunction "PC2_17") (pintype "bidirectional"))
      (node (ref "J4") (pin "3") (pinfunction "3_3") (pintype "passive"))
    )
    (net (code "53") (name "39.ADC123_IN13") (class "Default")
      (node (ref "IC3") (pin "18") (pinfunction "PC3_18") (pintype "bidirectional"))
      (node (ref "J4") (pin "4") (pinfunction "4_4") (pintype "passive"))
    )
    (net (code "54") (name "39.AGND") (class "Default")
      (node (ref "C133") (pin "2") (pinfunction "2_2") (pintype "passive"))
      (node (ref "C134") (pin "2") (pinfunction "2_2") (pintype "passive"))
      (node (ref "IC3") (pin "20") (pinfunction "VSSA_OR_VREF-_20") (pintype "input"))
      (node (ref "J5") (pin "A1") (pinfunction "1_A1") (pintype "passive"))
      (node (ref "J5") (pin "A2") (pinfunction "3_A2") (pintype "passive"))
      (node (ref "J5") (pin "A3") (pinfunction "5_A3") (pintype "passive"))
      (node (ref "J5") (pin "A4") (pinfunction "7_A4") (pintype "passive"))
      (node (ref "J5") (pin "A5") (pinfunction "9_A5") (pintype "passive"))
      (node (ref "J5") (pin "A6") (pinfunction "11_A6") (pintype "passive"))
      (node (ref "R87") (pin "1") (pinfunction "1_1") (pintype "passive"))
    )
    (net (code "55") (name "39.BOOT0") (class "Default")
      (node (ref "BOOT0") (pin "1") (pinfunction "TP_1") (pintype "bidirectional"))
      (node (ref "IC3") (pin "94") (pinfunction "BOOT0_94") (pintype "input"))
      (node (ref "R85") (pin "1") (pinfunction "1_1") (pintype "passive"))
      (node (ref "R91") (pin "2") (pinfunction "2_2") (pintype "passive"))
      (node (ref "R93") (pin "2") (pinfunction "2_2") (pintype "passive"))
      (node (ref "U32") (pin "7") (pinfunction "B1_7") (pintype "output"))
    )
    (net (code "56") (name "39.I2C1_SCL") (class "Default")
      (node (ref "IC3") (pin "92") (pinfunction "PB6_92") (pintype "bidirectional"))
      (node (ref "R138") (pin "1") (pinfunction "1_1") (pintype "passive"))
      (node (ref "U21") (pin "2") (pinfunction "A1_2") (pintype "input"))
    )
    (net (code "57") (name "39.I2C1_SDA") (class "Default")
      (node (ref "IC3") (pin "93") (pinfunction "PB7_93") (pintype "bidirectional"))
      (node (ref "R139") (pin "1") (pinfunction "1_1") (pintype "passive"))
      (node (ref "U21") (pin "3") (pinfunction "A2_3") (pintype "input"))
    )
    (net (code "58") (name "39.PB0") (class "Default")
      (node (ref "C9") (pin "1") (pinfunction "1_1") (pintype "passive"))
      (node (ref "IC3") (pin "35") (pinfunction "PB0_35") (pintype "bidirectional"))
      (node (ref "R1") (pin "1") (pinfunction "1_1") (pintype "passive"))
      (node (ref "R2") (pin "2") (pinfunction "2_2") (pintype "passive"))
      (node (ref "S1") (pin "B@2") (pinfunction "B'_B@2") (pintype "passive"))
    )
    (net (code "59") (name "39.PB4") (class "Default")
      (node (ref "IC3") (pin "90") (pinfunction "PB4_90") (pintype "bidirectional"))
      (node (ref "U8") (pin "18") (pinfunction "B2_18") (pintype "bidirectional"))
    )
    (net (code "60") (name "39.PB5") (class "Default")
      (node (ref "IC3") (pin "91") (pinfunction "PB5_91") (pintype "bidirectional"))
      (node (ref "U8") (pin "15") (pinfunction "B5_15") (pintype "bidirectional"))
    )
    (net (code "61") (name "39.PB8") (class "Default")
      (node (ref "IC3") (pin "95") (pinfunction "PB8_95") (pintype "bidirectional"))
      (node (ref "RP7") (pin "3") (pinfunction "3_3") (pintype "passive"))
      (node (ref "U29") (pin "7") (pinfunction "A6_7") (pintype "bidirectional"))
    )
    (net (code "62") (name "39.PB9") (class "Default")
      (node (ref "IC3") (pin "96") (pinfunction "PB9_96") (pintype "bidirectional"))
      (node (ref "RP7") (pin "4") (pinfunction "4_4") (pintype "passive"))
      (node (ref "U29") (pin "6") (pinfunction "A5_6") (pintype "bidirectional"))
    )
    (net (code "63") (name "39.PC9") (class "Default")
      (node (ref "IC3") (pin "66") (pinfunction "PC9_66") (pintype "bidirectional"))
      (node (ref "RP7") (pin "2") (pinfunction "2_2") (pintype "passive"))
      (node (ref "U29") (pin "8") (pinfunction "A7_8") (pintype "bidirectional"))
    )
    (net (code "64") (name "39.PC13") (class "Default")
      (node (ref "IC3") (pin "7") (pinfunction "PC13_7") (pintype "bidirectional"))
      (node (ref "U4") (pin "16") (pinfunction "BIN2_16") (pintype "bidirectional"))
    )
    (net (code "65") (name "39.PC14") (class "Default")
      (node (ref "IC3") (pin "8") (pinfunction "PC14_8") (pintype "bidirectional"))
      (node (ref "U23") (pin "21") (pinfunction "AIN1_21") (pintype "bidirectional"))
    )
    (net (code "66") (name "39.PC15") (class "Default")
      (node (ref "IC3") (pin "9") (pinfunction "PC15_9") (pintype "bidirectional"))
      (node (ref "U23") (pin "22") (pinfunction "AIN2_22") (pintype "bidirectional"))
    )
    (net (code "67") (name "39.PD0") (class "Default")
      (node (ref "IC3") (pin "81") (pinfunction "PD0_81") (pintype "bidirectional"))
      (node (ref "RP4") (pin "12") (pinfunction "12_12") (pintype "passive"))
      (node (ref "U20") (pin "7") (pinfunction "A6_7") (pintype "bidirectional"))
    )
    (net (code "68") (name "39.PD1") (class "Default")
      (node (ref "IC3") (pin "82") (pinfunction "PD1_82") (pintype "bidirectional"))
      (node (ref "U4") (pin "21") (pinfunction "AIN1_21") (pintype "bidirectional"))
    )
    (net (code "69") (name "39.PD2") (class "Default")
      (node (ref "IC3") (pin "83") (pinfunction "PD2_83") (pintype "bidirectional"))
      (node (ref "U36") (pin "P6") (pinfunction "DRDY_P6") (pintype "bidirectional"))
    )
    (net (code "70") (name "39.PD3") (class "Default")
      (node (ref "IC3") (pin "84") (pinfunction "PD3_84") (pintype "bidirectional"))
      (node (ref "U37") (pin "11") (pinfunction "INT1_11") (pintype "bidirectional"))
    )
    (net (code "71") (name "39.PD4") (class "Default")
      (node (ref "IC3") (pin "85") (pinfunction "PD4_85") (pintype "bidirectional"))
      (node (ref "U37") (pin "9") (pinfunction "INT2_9") (pintype "bidirectional"))
    )
    (net (code "72") (name "39.PD7") (class "Default")
      (node (ref "IC3") (pin "88") (pinfunction "PD7_88") (pintype "bidirectional"))
      (node (ref "U4") (pin "22") (pinfunction "AIN2_22") (pintype "bidirectional"))
    )
    (net (code "73") (name "39.PD8") (class "Default")
      (node (ref "IC3") (pin "55") (pinfunction "PD8_55") (pintype "bidirectional"))
      (node (ref "R21") (pin "2") (pinfunction "2_2") (pintype "passive"))
      (node (ref "U10") (pin "7") (pinfunction "B1_7") (pintype "output"))
    )
    (net (code "74") (name "39.PD9") (class "Default")
      (node (ref "IC3") (pin "56") (pinfunction "PD9_56") (pintype "bidirectional"))
      (node (ref "R22") (pin "2") (pinfunction "2_2") (pintype "passive"))
      (node (ref "U10") (pin "6") (pinfunction "B2_6") (pintype "output"))
    )
    (net (code "75") (name "39.PD10") (class "Default")
      (node (ref "IC3") (pin "57") (pinfunction "PD10_57") (pintype "bidirectional"))
      (node (ref "U23") (pin "17") (pinfunction "BIN1_17") (pintype "bidirectional"))
    )
    (net (code "76") (name "39.PD11") (class "Default")
      (node (ref "IC3") (pin "58") (pinfunction "PD11_58") (pintype "bidirectional"))
      (node (ref "U23") (pin "16") (pinfunction "BIN2_16") (pintype "bidirectional"))
    )
    (net (code "77") (name "39.PD12") (class "Default")
      (node (ref "IC3") (pin "59") (pinfunction "PD12_59") (pintype "bidirectional"))
      (node (ref "RP7") (pin "8") (pinfunction "8_8") (pintype "passive"))
      (node (ref "U29") (pin "1") (pinfunction "A1_1") (pintype "bidirectional"))
    )
    (net (code "78") (name "39.PD13") (class "Default")
      (node (ref "IC3") (pin "60") (pinfunction "PD13_60") (pintype "bidirectional"))
      (node (ref "RP7") (pin "7") (pinfunction "7_7") (pintype "passive"))
      (node (ref "U29") (pin "3") (pinfunction "A2_3") (pintype "bidirectional"))
    )
    (net (code "79") (name "39.PD14") (class "Default")
      (node (ref "IC3") (pin "61") (pinfunction "PD14_61") (pintype "bidirectional"))
      (node (ref "RP7") (pin "6") (pinfunction "6_6") (pintype "passive"))
      (node (ref "U29") (pin "4") (pinfunction "A3_4") (pintype "bidirectional"))
    )
    (net (code "80") (name "39.PD15") (class "Default")
      (node (ref "IC3") (pin "62") (pinfunction "PD15_62") (pintype "bidirectional"))
      (node (ref "RP7") (pin "5") (pinfunction "5_5") (pintype "passive"))
      (node (ref "U29") (pin "5") (pinfunction "A4_5") (pintype "bidirectional"))
    )
    (net (code "81") (name "39.PE0") (class "Default")
      (node (ref "IC3") (pin "97") (pinfunction "PE0_97") (pintype "bidirectional"))
      (node (ref "RP7") (pin "1") (pinfunction "1_1") (pintype "passive"))
      (node (ref "U29") (pin "9") (pinfunction "A8_9") (pintype "bidirectional"))
    )
    (net (code "82") (name "39.PE1") (class "Default")
      (node (ref "IC3") (pin "98") (pinfunction "PE1_98") (pintype "bidirectional"))
      (node (ref "R80") (pin "1") (pinfunction "1_1") (pintype "passive"))
      (node (ref "U30") (pin "2") (pinfunction "A1_2") (pintype "input"))
    )
    (net (code "83") (name "39.PE4") (class "Default")
      (node (ref "IC3") (pin "3") (pinfunction "PE4_3") (pintype "bidirectional"))
      (node (ref "R81") (pin "1") (pinfunction "1_1") (pintype "passive"))
      (node (ref "U30") (pin "3") (pinfunction "A2_3") (pintype "input"))
    )
    (net (code "84") (name "39.PE9") (class "Default")
      (node (ref "IC3") (pin "40") (pinfunction "PE9_40") (pintype "bidirectional"))
      (node (ref "R59") (pin "1") (pinfunction "1_1") (pintype "passive"))
      (node (ref "R60") (pin "1") (pinfunction "1_1") (pintype "passive"))
    )
    (net (code "85") (name "39.PE10") (class "Default")
      (node (ref "IC3") (pin "41") (pinfunction "PE10_41") (pintype "bidirectional"))
      (node (ref "R33") (pin "1") (pinfunction "1_1") (pintype "passive"))
    )
    (net (code "86") (name "39.PE11") (class "Default")
      (node (ref "IC3") (pin "42") (pinfunction "PE11_42") (pintype "bidirectional"))
      (node (ref "RP4") (pin "14") (pinfunction "14_14") (pintype "passive"))
      (node (ref "U20") (pin "5") (pinfunction "A4_5") (pintype "bidirectional"))
    )
    (net (code "87") (name "39.PE15") (class "Default")
      (node (ref "IC3") (pin "46") (pinfunction "PE15_46") (pintype "bidirectional"))
      (node (ref "U4") (pin "17") (pinfunction "BIN1_17") (pintype "bidirectional"))
    )
    (net (code "88") (name "39.PWM1") (class "Default")
      (node (ref "IC3") (pin "67") (pinfunction "PA8_67") (pintype "bidirectional"))
      (node (ref "U4") (pin "23") (pinfunction "PWMA_23") (pintype "bidirectional"))
    )
    (net (code "89") (name "39.PWM2") (class "Default")
      (node (ref "IC3") (pin "68") (pinfunction "PA9_68") (pintype "bidirectional"))
      (node (ref "R92") (pin "2") (pinfunction "2_2") (pintype "passive"))
      (node (ref "U4") (pin "15") (pinfunction "PWMB_15") (pintype "bidirectional"))
    )
    (net (code "90") (name "39.PWM3") (class "Default")
      (node (ref "IC3") (pin "69") (pinfunction "PA10_69") (pintype "bidirectional"))
      (node (ref "U23") (pin "23") (pinfunction "PWMA_23") (pintype "bidirectional"))
    )
    (net (code "91") (name "39.PWM4") (class "Default")
      (node (ref "IC3") (pin "63") (pinfunction "PC6_63") (pintype "bidirectional"))
      (node (ref "U23") (pin "15") (pinfunction "PWMB_15") (pintype "bidirectional"))
    )
    (net (code "92") (name "39.PWM5") (class "Default")
      (node (ref "IC3") (pin "64") (pinfunction "PC7_64") (pintype "bidirectional"))
      (node (ref "U2") (pin "2") (pinfunction "A1_2") (pintype "input"))
    )
    (net (code "93") (name "39.PWM6") (class "Default")
      (node (ref "IC3") (pin "65") (pinfunction "PC8_65") (pintype "bidirectional"))
      (node (ref "U2") (pin "3") (pinfunction "A2_3") (pintype "input"))
    )
    (net (code "94") (name "39.PWM7") (class "Default")
      (node (ref "IC3") (pin "4") (pinfunction "PE5_4") (pintype "bidirectional"))
      (node (ref "U22") (pin "2") (pinfunction "A1_2") (pintype "input"))
    )
    (net (code "95") (name "39.PWM8") (class "Default")
      (node (ref "IC3") (pin "5") (pinfunction "PE6_5") (pintype "bidirectional"))
      (node (ref "U22") (pin "3") (pinfunction "A2_3") (pintype "input"))
    )
    (net (code "96") (name "39.SPI2_CLK") (class "Default")
      (node (ref "IC3") (pin "52") (pinfunction "PB13_52") (pintype "bidirectional"))
      (node (ref "RP3") (pin "7") (pinfunction "7_7") (pintype "passive"))
      (node (ref "U8") (pin "14") (pinfunction "B6_14") (pintype "bidirectional"))
    )
    (net (code "97") (name "39.SPI2_CS0") (class "Default")
      (node (ref "IC3") (pin "51") (pinfunction "PB12_51") (pintype "bidirectional"))
      (node (ref "RP3") (pin "6") (pinfunction "6_6") (pintype "passive"))
      (node (ref "U8") (pin "16") (pinfunction "B4_16") (pintype "bidirectional"))
    )
    (net (code "98") (name "39.SPI2_MISO") (class "Default")
      (node (ref "IC3") (pin "53") (pinfunction "PB14_53") (pintype "bidirectional"))
      (node (ref "RP3") (pin "5") (pinfunction "5_5") (pintype "passive"))
      (node (ref "U8") (pin "17") (pinfunction "B3_17") (pintype "bidirectional"))
    )
    (net (code "99") (name "39.SPI2_MOSI") (class "Default")
      (node (ref "IC3") (pin "54") (pinfunction "PB15_54") (pintype "bidirectional"))
      (node (ref "RP3") (pin "8") (pinfunction "8_8") (pintype "passive"))
      (node (ref "U8") (pin "13") (pinfunction "B7_13") (pintype "bidirectional"))
    )
    (net (code "100") (name "39.SPI3_CLK") (class "Default")
      (node (ref "IC3") (pin "78") (pinfunction "PC10_78") (pintype "bidirectional"))
      (node (ref "U36") (pin "P2") (pinfunction "SCL/SPC_P2") (pintype "bidirectional"))
      (node (ref "U37") (pin "4") (pinfunction "SCL/SPC_4") (pintype "bidirectional"))
    )
    (net (code "101") (name "39.SPI3_CS0") (class "Default")
      (node (ref "IC3") (pin "1") (pinfunction "PE2_1") (pintype "bidirectional"))
      (node (ref "U37") (pin "8") (pinfunction "CS_8") (pintype "bidirectional"))
    )
    (net (code "102") (name "39.SPI3_CS1") (class "Default")
      (node (ref "IC3") (pin "2") (pinfunction "PE3_2") (pintype "bidirectional"))
      (node (ref "U36") (pin "P5") (pinfunction "CS_P5") (pintype "bidirectional"))
    )
    (net (code "103") (name "39.SPI3_MISO") (class "Default")
      (node (ref "IC3") (pin "79") (pinfunction "PC11_79") (pintype "bidirectional"))
      (node (ref "U36") (pin "P4") (pinfunction "SDO/SA0_P4") (pintype "bidirectional"))
      (node (ref "U37") (pin "7") (pinfunction "SDO/SA0_7") (pintype "bidirectional"))
    )
    (net (code "104") (name "39.SPI3_MOSI") (class "Default")
      (node (ref "IC3") (pin "80") (pinfunction "PC12_80") (pintype "bidirectional"))
      (node (ref "U36") (pin "P3") (pinfunction "SDA/SDI_P3") (pintype "bidirectional"))
      (node (ref "U37") (pin "6") (pinfunction "SDA/SDI_6") (pintype "bidirectional"))
    )
    (net (code "105") (name "39.SPI4_CLK") (class "Default")
      (node (ref "IC3") (pin "43") (pinfunction "PE12_43") (pintype "bidirectional"))
      (node (ref "RP4") (pin "15") (pinfunction "15_15") (pintype "passive"))
      (node (ref "U20") (pin "4") (pinfunction "A3_4") (pintype "bidirectional"))
    )
    (net (code "106") (name "39.SPI4_MISO") (class "Default")
      (node (ref "IC3") (pin "44") (pinfunction "PE13_44") (pintype "bidirectional"))
      (node (ref "RP4") (pin "11") (pinfunction "11_11") (pintype "passive"))
      (node (ref "U20") (pin "8") (pinfunction "A7_8") (pintype "bidirectional"))
    )
    (net (code "107") (name "39.SPI4_MOSI") (class "Default")
      (node (ref "IC3") (pin "45") (pinfunction "PE14_45") (pintype "bidirectional"))
      (node (ref "RP4") (pin "16") (pinfunction "16_16") (pintype "passive"))
      (node (ref "U20") (pin "3") (pinfunction "A2_3") (pintype "bidirectional"))
    )
    (net (code "108") (name "39.STM_RESET") (class "Default")
      (node (ref "C123") (pin "1") (pinfunction "1_1") (pintype "passive"))
      (node (ref "IC3") (pin "14") (pinfunction "NRST_14") (pintype "input"))
      (node (ref "JTAG") (pin "10") (pinfunction "S_10") (pintype "passive"))
      (node (ref "R94") (pin "2") (pinfunction "2_2") (pintype "passive"))
      (node (ref "U32") (pin "6") (pinfunction "B2_6") (pintype "output"))
    )
    (net (code "109") (name "39.UART2_RX") (class "Default")
      (node (ref "IC3") (pin "87") (pinfunction "PD6_87") (pintype "bidirectional"))
      (node (ref "U11") (pin "2") (pinfunction "A1_2") (pintype "input"))
    )
    (net (code "110") (name "39.UART2_TX") (class "Default")
      (node (ref "IC3") (pin "86") (pinfunction "PD5_86") (pintype "bidirectional"))
      (node (ref "U11") (pin "3") (pinfunction "A2_3") (pintype "input"))
    )
    (net (code "111") (name "39.UART3_RX") (class "Default")
      (node (ref "IC3") (pin "48") (pinfunction "PB11_48") (pintype "bidirectional"))
      (node (ref "R37") (pin "2") (pinfunction "2_2") (pintype "passive"))
      (node (ref "U16") (pin "4") (pinfunction "B2_4") (pintype "bidirectional"))
    )
    (net (code "112") (name "39.UART3_TX") (class "Default")
      (node (ref "IC3") (pin "47") (pinfunction "PB10_47") (pintype "bidirectional"))
      (node (ref "R36") (pin "2") (pinfunction "2_2") (pintype "passive"))
      (node (ref "U16") (pin "5") (pinfunction "B1_5") (pintype "bidirectional"))
    )
    (net (code "113") (name "39.USB_DEVICE_N") (class "Default")
      (node (ref "IC3") (pin "70") (pinfunction "PA11_70") (pintype "bidirectional"))
      (node (ref "L5") (pin "2") (pinfunction "2_2") (pintype "passive"))
    )
    (net (code "114") (name "39.USB_DEVICE_P") (class "Default")
      (node (ref "IC3") (pin "71") (pinfunction "PA12_71") (pintype "bidirectional"))
      (node (ref "L5") (pin "3") (pinfunction "3_3") (pintype "passive"))
    )
    (net (code "115") (name "39.USB_DEVICE_VBUS") (class "Default")
      (node (ref "D32") (pin "P2") (pinfunction "P2_P2") (pintype "passive"))
      (node (ref "J10") (pin "P1") (pinfunction "VBUS_P1") (pintype "bidirectional"))
      (node (ref "R92") (pin "1") (pinfunction "1_1") (pintype "passive"))
    )
    (net (code "116") (name "45.BACKLIGHT_ENABLE") (class "Default")
      (node (ref "U$67") (pin "11") (pinfunction "1B6_11") (pintype "bidirectional"))
      (node (ref "U$72") (pin "V17") (pinfunction "GPMC_A11|GMII2_RXD0|RGMII2_RD0|RMII2_RXD0|GPMC_A27|PR1_MII1_RXER|MCASP0_AXR1|GPIO1_27_V17") (pintype "output"))
    )
    (net (code "117") (name "45.BACKLIGHT_N") (class "Default")
      (node (ref "U$70") (pin "1") (pinfunction "LED-_1") (pintype "power_in"))
      (node (ref "U35") (pin "33") (pinfunction "ISINK2_33") (pintype "input"))
      (node (ref "U35") (pin "34") (pinfunction "ISINK1_34") (pintype "input"))
    )
    (net (code "118") (name "45.BACKLIGHT_P") (class "Default")
      (node (ref "C234") (pin "1") (pinfunction "1_1") (pintype "passive"))
      (node (ref "D31") (pin "C") (pinfunction "C_C") (pintype "passive"))
      (node (ref "U$70") (pin "2") (pinfunction "LED+_2") (pintype "power_in"))
      (node (ref "U35") (pin "38") (pinfunction "FB_WLED_38") (pintype "input"))
    )
    (net (code "119") (name "45.CLKOUT1") (class "Default")
      (node (ref "R144") (pin "2") (pinfunction "2_2") (pintype "passive"))
      (node (ref "U$72") (pin "A15") (pinfunction "XDMA_EVENT_INTR0|TIMER4|CLKOUT1|SPI1_CS1|PR1_PRU1_R31_16|EMU2|GPIO0_19_A15") (pintype "input"))
    )
    (net (code "120") (name "45.GPIO0_7") (class "Default")
      (node (ref "U$69") (pin "11") (pinfunction "1B6_11") (pintype "bidirectional"))
      (node (ref "U$72") (pin "C18") (pinfunction "ECAP0_IN_PWM0_OUT|UART3_TXD|SPI1_CS1|PR1_ECAP0_ECAP_CAPIN_APWM_O|SPI1_SCLK|MMC0_SDWP|XDMA_EVENT_INTR2|GPIO0_7_C18") (pintype "bidirectional"))
    )
    (net (code "121") (name "45.GPIO1_1") (class "Default")
      (node (ref "R93") (pin "1") (pinfunction "1_1") (pintype "passive"))
      (node (ref "U$72") (pin "V7") (pinfunction "GPMC_AD1|MMC1_DAT1||||||GPIO1_1_V7") (pintype "bidirectional"))
      (node (ref "U32") (pin "2") (pinfunction "A1_2") (pintype "input"))
    )
    (net (code "122") (name "45.GPIO1_2") (class "Default")
      (node (ref "R94") (pin "1") (pinfunction "1_1") (pintype "passive"))
      (node (ref "U$72") (pin "R8") (pinfunction "GPMC_AD2|MMC1_DAT2||||||GPIO1_2_R8") (pintype "bidirectional"))
      (node (ref "U32") (pin "3") (pinfunction "A2_3") (pintype "input"))
    )
    (net (code "123") (name "45.GPIO1_3") (class "Default")
      (node (ref "R21") (pin "1") (pinfunction "1_1") (pintype "passive"))
      (node (ref "U$72") (pin "T8") (pinfunction "GPMC_AD3|MMC1_DAT3||||||GPIO1_3_T8") (pintype "bidirectional"))
      (node (ref "U10") (pin "2") (pinfunction "A1_2") (pintype "input"))
    )
    (net (code "124") (name "45.GPIO1_4") (class "Default")
      (node (ref "R22") (pin "1") (pinfunction "1_1") (pintype "passive"))
      (node (ref "U$72") (pin "U8") (pinfunction "GPMC_AD4|MMC1_DAT4||||||GPIO1_4_U8") (pintype "bidirectional"))
      (node (ref "U10") (pin "3") (pinfunction "A2_3") (pintype "input"))
    )
    (net (code "125") (name "45.GPIO1_5") (class "Default")
      (node (ref "R103") (pin "1") (pinfunction "1_1") (pintype "passive"))
      (node (ref "U$72") (pin "V8") (pinfunction "GPMC_AD5|MMC1_DAT5||||||GPIO1_5_V8") (pintype "bidirectional"))
    )
    (net (code "126") (name "45.GPIO1_16") (class "Default")
      (node (ref "R31") (pin "2") (pinfunction "2_2") (pintype "passive"))
      (node (ref "U$72") (pin "R13") (pinfunction "GPMC_A0|GMII2_TXEN|RGMII2_TCTL|RMII2_TXEN|GPMC_A16|PR1_MII_MT1_CLK|EHRPWM1_TRIPZONE_INPUT|GPIO1_16_R13") (pintype "output"))
      (node (ref "U15") (pin "33") (pinfunction "~{RESET}_33") (pintype "bidirectional"))
    )
    (net (code "127") (name "45.GPIO1_20") (class "Default")
      (node (ref "R56") (pin "1") (pinfunction "1_1") (pintype "passive"))
      (node (ref "R57") (pin "1") (pinfunction "1_1") (pintype "passive"))
      (node (ref "U$72") (pin "R14") (pinfunction "GPMC_A4|GMII2_TXD1|RGMII2_TD1|RMII2_TXD1|GPMC_A20|PR1_MII1_TXD0|EQEP1A_IN|GPIO1_20_R14") (pintype "output"))
    )
    (net (code "128") (name "45.GPIO1_21") (class "Default")
      (node (ref "R24") (pin "1") (pinfunction "1_1") (pintype "passive"))
      (node (ref "R25") (pin "1") (pinfunction "1_1") (pintype "passive"))
      (node (ref "U$72") (pin "V15") (pinfunction "GPMC_A5|GMII2_TXD0|RGMII2_TD0|RMII2_TXD0|GPMC_A21|PR1_MII1_RXD3|EQEP1B_IN|GPIO1_21_V15") (pintype "output"))
    )
    (net (code "129") (name "45.GPIO1_22") (class "Default")
      (node (ref "C104") (pin "1") (pinfunction "1_1") (pintype "passive"))
      (node (ref "R61") (pin "1") (pinfunction "1_1") (pintype "passive"))
      (node (ref "R62") (pin "2") (pinfunction "2_2") (pintype "passive"))
      (node (ref "S2") (pin "B@2") (pinfunction "B'_B@2") (pintype "passive"))
      (node (ref "U$72") (pin "U15") (pinfunction "GPMC_A6|GMII2_TXCLK|RGMII2_TCLK|MMC2_DAT4|GPMC_A22|PR1_MII1_RXD2|EQEP1_INDEX|GPIO1_22_U15") (pintype "output"))
    )
    (net (code "130") (name "45.GPIO1_29") (class "Default")
      (node (ref "BTEN") (pin "1") (pinfunction "TP_1") (pintype "bidirectional"))
      (node (ref "U$72") (pin "V6") (pinfunction "GPMC_CSN0|GPIO1_29_V6") (pintype "output"))
      (node (ref "U28") (pin "41") (pinfunction "BT_EN_SOC_41") (pintype "bidirectional"))
    )
    (net (code "131") (name "45.GPIO1_30") (class "Default")
      (node (ref "U$72") (pin "U9") (pinfunction "GPMC_CSN1|GPMC_CLK|MMC1_CLK|PRT1EDIO_DATA_IN6|PRT1_EDIO_DATA_OUT6|PR1_PRU1_PRU_R30_12|PR1_PRU1_PRU_R31_12|GPIO1_30_U9") (pintype "output"))
      (node (ref "U28") (pin "40") (pinfunction "WLAN_EN_SOC_40") (pintype "bidirectional"))
      (node (ref "WLEN") (pin "1") (pinfunction "TP_1") (pintype "bidirectional"))
    )
    (net (code "132") (name "45.GPIO1_31") (class "Default")
      (node (ref "U$72") (pin "V9") (pinfunction "GPMC_CSN2|GPMC_BE1N|MMC1_CMD|PR1_EDIO_DATA_IN7|PR1_EDIO_DATA_OUT7|PR1_PRU1_PRU_R30_13|PR1_PRU1_PRU_R31_13|GPIO1_31_V9") (pintype "output"))
      (node (ref "U28") (pin "14") (pinfunction "WLAN_IRQ_14") (pintype "bidirectional"))
    )
    (net (code "133") (name "45.GPIO114") (class "Default")
      (node (ref "U$72") (pin "B12") (pinfunction "MCASP0_ACLKR|EQEP0A_IN|MCASP0_AXR2|MCASP1_ACLKX|MMC0_SDWP|PR1_PRU0_PRU_R30_4|PR1_PRU0_PRU_R31_4|GPIO3_18_B12") (pintype "bidirectional"))
      (node (ref "U8") (pin "3") (pinfunction "A2_3") (pintype "bidirectional"))
    )
    (net (code "134") (name "45.GPIO117") (class "Default")
      (node (ref "U$72") (pin "A14") (pinfunction "MCASP0_AHCLKX|EQEP0_STROBE|MCASP0_AXR3|MCASP1_AXR1|EMU4|PR1_PRU0_PRU_R30_7|PR1_PRU0_PRU_R31_7|GPIO3_21_A14") (pintype "bidirectional"))
      (node (ref "U8") (pin "6") (pinfunction "A5_6") (pintype "bidirectional"))
    )
    (net (code "135") (name "45.I2C0_SCL") (class "Default")
      (node (ref "R123") (pin "1") (pinfunction "1_1") (pintype "passive"))
      (node (ref "U$72") (pin "C16") (pinfunction "I2C0_SCL|TIMER7|UART2_RTSN|ECAP1_IN_PWM1_OUT||||GPIO3_6_C16") (pintype "bidirectional"))
      (node (ref "U15") (pin "1") (pinfunction "SCL_1") (pintype "bidirectional"))
      (node (ref "U34") (pin "6") (pinfunction "SCL_6") (pintype "bidirectional"))
      (node (ref "U35") (pin "28") (pinfunction "SCL_28") (pintype "input"))
    )
    (net (code "136") (name "45.I2C0_SDA") (class "Default")
      (node (ref "R122") (pin "1") (pinfunction "1_1") (pintype "passive"))
      (node (ref "U$72") (pin "C17") (pinfunction "I2C0_SDA|TIMER4|UART2_CTSN|ECAP2_IN_PWM2_OUT||||GPIO3_5_C17") (pintype "bidirectional"))
      (node (ref "U15") (pin "2") (pinfunction "SDA_2") (pintype "bidirectional"))
      (node (ref "U34") (pin "5") (pinfunction "SDA_5") (pintype "bidirectional"))
      (node (ref "U35") (pin "27") (pinfunction "SDA_27") (pintype "bidirectional"))
    )
    (net (code "137") (name "45.I2C1_SCL") (class "Default")
      (node (ref "R107") (pin "2") (pinfunction "2_2") (pintype "passive"))
      (node (ref "U$72") (pin "E17") (pinfunction "UART0_RTSN|UART4_TXD|DCAN1_RX|I2C1_SCL|SPI1_D1|SPI1_CS0|PR1_EDC_SYNC1_OUT|GPIO1_9_E17") (pintype "output"))
      (node (ref "U3") (pin "6") (pinfunction "SCL_6") (pintype "bidirectional"))
      (node (ref "U33") (pin "3") (pinfunction "SCL1_3") (pintype "bidirectional"))
    )
    (net (code "138") (name "45.I2C1_SDA") (class "Default")
      (node (ref "R108") (pin "2") (pinfunction "2_2") (pintype "passive"))
      (node (ref "U$72") (pin "E18") (pinfunction "UART0_CTSN|UART4_RXD|DCAN1_TX|I2C1_SDA|SPI1_D0|TIMER7|PR1_EDC_SYNC0_OUT|GPIO1_8_E18") (pintype "input"))
      (node (ref "U3") (pin "5") (pinfunction "SDA_5") (pintype "bidirectional"))
      (node (ref "U33") (pin "4") (pinfunction "SDA1_4") (pintype "bidirectional"))
    )
    (net (code "139") (name "45.I2C2_SCL") (class "Default")
      (node (ref "R128") (pin "1") (pinfunction "1_1") (pintype "passive"))
      (node (ref "U$72") (pin "D17") (pinfunction "UART1_RTSN|TIMER5|DCAN0_RX|I2C2_SCL|SPI1_CS1|PR1_UART0_RTS_N|PR1_EDC_LATCH1_IN|GPIO0_13_D17") (pintype "output"))
      (node (ref "U1") (pin "2") (pinfunction "A1_2") (pintype "input"))
    )
    (net (code "140") (name "45.I2C2_SDA") (class "Default")
      (node (ref "R130") (pin "1") (pinfunction "1_1") (pintype "passive"))
      (node (ref "U$72") (pin "D18") (pinfunction "UART1_CTSN|TIMER6|DCAN0_TX|I2C2_SDA|SPI1_CS0|PR1_UART0_CTS_N|PR1_EDC_LATCH0_IN|GPIO0_12_D18") (pintype "input"))
      (node (ref "U1") (pin "3") (pinfunction "A2_3") (pintype "input"))
    )
    (net (code "141") (name "45.LCD_BIAS") (class "Default")
      (node (ref "R115") (pin "1") (pinfunction "1_1") (pintype "passive"))
      (node (ref "U$67") (pin "6") (pinfunction "1B3_6") (pintype "bidirectional"))
      (node (ref "U$72") (pin "R6") (pinfunction "LCD_AC_BIAS_EN|GPMC_A11||PR1_EDIO_DATA_IN5|PR1_EDIO_DATA_OUT5|PR1_PRU1_PRU_R30_11|PR1_PRU1_PRU_R31_11|GPIO2_25_R6") (pintype "bidirectional"))
    )
    (net (code "142") (name "45.LCD_DD0") (class "Default")
      (node (ref "RP10") (pin "13") (pinfunction "13_13") (pintype "passive"))
      (node (ref "U$68") (pin "19") (pinfunction "2B4_19") (pintype "bidirectional"))
      (node (ref "U$72") (pin "R1") (pinfunction "LCD_DATA0|GPMC_A0||EHRPWM2A||PR1_PRU1_PRU_R30_0|PR1_PRU1_PRU_R31_0|GPIO2_6_R1") (pintype "bidirectional"))
      (node (ref "U$80") (pin "P5") (pinfunction "P$5_P5") (pintype "bidirectional"))
    )
    (net (code "143") (name "45.LCD_DD1") (class "Default")
      (node (ref "RP10") (pin "12") (pinfunction "12_12") (pintype "passive"))
      (node (ref "U$68") (pin "17") (pinfunction "2B3_17") (pintype "bidirectional"))
      (node (ref "U$72") (pin "R2") (pinfunction "LCD_DATA1|GPMC_A1||EHRPWM2B||PR1_PRU1_PRU_R30_1|PR1_PRU1_PRU_R31_1|GPIO2_7_R2") (pintype "bidirectional"))
      (node (ref "U$80") (pin "P7") (pinfunction "P$7_P7") (pintype "bidirectional"))
    )
    (net (code "144") (name "45.LCD_DD2") (class "Default")
      (node (ref "RP10") (pin "11") (pinfunction "11_11") (pintype "passive"))
      (node (ref "U$68") (pin "16") (pinfunction "2B2_16") (pintype "bidirectional"))
      (node (ref "U$72") (pin "R3") (pinfunction "LCD_DATA2|GPMC_A2||EHRPWM2_TRIPZONE_INPUT||PR1_PRU1_PRU_R30_2|PR1_PRU1_PRU_R31_2|GPIO2_8_R3") (pintype "bidirectional"))
      (node (ref "U$80") (pin "P6") (pinfunction "P$6_P6") (pintype "bidirectional"))
    )
    (net (code "145") (name "45.LCD_DD3") (class "Default")
      (node (ref "RP10") (pin "10") (pinfunction "10_10") (pintype "passive"))
      (node (ref "U$68") (pin "14") (pinfunction "2B1_14") (pintype "bidirectional"))
      (node (ref "U$72") (pin "R4") (pinfunction "LCD_DATA3|GPMC_A3||EHRPWM2_SYNCI_O||PR1_PRU1_PRU_R30_3|PR1_PRU1_PRU_R31_3|GPIO2_9_R4") (pintype "bidirectional"))
      (node (ref "U$80") (pin "P8") (pinfunction "P$8_P8") (pintype "bidirectional"))
    )
    (net (code "146") (name "45.LCD_DD4") (class "Default")
      (node (ref "RP10") (pin "9") (pinfunction "9_9") (pintype "passive"))
      (node (ref "U$68") (pin "13") (pinfunction "2B0_13") (pintype "bidirectional"))
      (node (ref "U$72") (pin "T1") (pinfunction "LCD_DATA4|GPMC_A4||EQEP2A_IN||PR1_PRU1_PRU_R30_4|PR1_PRU1_PRU_R31_4|GPIO2_10_T1") (pintype "bidirectional"))
      (node (ref "U$79") (pin "P5") (pinfunction "P$5_P5") (pintype "bidirectional"))
    )
    (net (code "147") (name "45.LCD_DD5") (class "Default")
      (node (ref "RP9") (pin "14") (pinfunction "14_14") (pintype "passive"))
      (node (ref "U$68") (pin "9") (pinfunction "1B5_9") (pintype "bidirectional"))
      (node (ref "U$72") (pin "T2") (pinfunction "LCD_DATA5|GPMC_A5||EQEP2B_IN||PR1_PRU1_PRU_R30_5|PR1_PRU1_PRU_R31_5|GPIO2_11_T2") (pintype "bidirectional"))
      (node (ref "U$79") (pin "P7") (pinfunction "P$7_P7") (pintype "bidirectional"))
    )
    (net (code "148") (name "45.LCD_DD6") (class "Default")
      (node (ref "RP9") (pin "13") (pinfunction "13_13") (pintype "passive"))
      (node (ref "U$68") (pin "8") (pinfunction "1B4_8") (pintype "bidirectional"))
      (node (ref "U$72") (pin "T3") (pinfunction "LCD_DATA6|GPMC_A6|PR1_EDIO_DATA_IN6|EQEP2_INDEX|PR1_EDIO_DATA_OUT6|PR1_PRU1_PRU_R30_6|PR1_PRU1_PRU_R31_6|GPIO2_12_T3") (pintype "bidirectional"))
      (node (ref "U$79") (pin "P6") (pinfunction "P$6_P6") (pintype "bidirectional"))
    )
    (net (code "149") (name "45.LCD_DD7") (class "Default")
      (node (ref "RP9") (pin "12") (pinfunction "12_12") (pintype "passive"))
      (node (ref "U$68") (pin "6") (pinfunction "1B3_6") (pintype "bidirectional"))
      (node (ref "U$72") (pin "T4") (pinfunction "LCD_DATA7|GPMC_A7|PR1_EDIO_DATA_IN7|EQEP2_STROBE|PR1_EDIO_DATA_OUT7|PR1_PRU1_PRU_R30_7|PR1_PRU1_PRU_R31_7|GPIO2_13_T4") (pintype "bidirectional"))
      (node (ref "U$81") (pin "P5") (pinfunction "P$5_P5") (pintype "bidirectional"))
    )
    (net (code "150") (name "45.LCD_DD8") (class "Default")
      (node (ref "RP9") (pin "11") (pinfunction "11_11") (pintype "passive"))
      (node (ref "U$68") (pin "5") (pinfunction "1B2_5") (pintype "bidirectional"))
      (node (ref "U$72") (pin "U1") (pinfunction "LCD_DATA8|GPMC_A12|EHRPWM1_TRIPZONE_INPUT|MCASP0_ACLKX|UART5_TXD|PR1_MII0_RXD3|UART2_CTSN|GPIO2_14_U1") (pintype "bidirectional"))
      (node (ref "U$79") (pin "P8") (pinfunction "P$8_P8") (pintype "bidirectional"))
    )
    (net (code "151") (name "45.LCD_DD9") (class "Default")
      (node (ref "RP9") (pin "10") (pinfunction "10_10") (pintype "passive"))
      (node (ref "U$68") (pin "3") (pinfunction "1B1_3") (pintype "bidirectional"))
      (node (ref "U$72") (pin "U2") (pinfunction "LCD_DATA9|GPMC_A13|EHRPWM1_SYNCI_O|MCASP0_FSX|UART5_RXD|PR1_MII0_RXD2|UART2_RTSN|GPIO2_15_U2") (pintype "bidirectional"))
      (node (ref "U$81") (pin "P6") (pinfunction "P$6_P6") (pintype "bidirectional"))
    )
    (net (code "152") (name "45.LCD_DD10") (class "Default")
      (node (ref "RP9") (pin "9") (pinfunction "9_9") (pintype "passive"))
      (node (ref "U$68") (pin "2") (pinfunction "1B0_2") (pintype "bidirectional"))
      (node (ref "U$72") (pin "U3") (pinfunction "LCD_DATA10|GPMC_A14|EHRPWM1A|MCASP0_AXR0||PR1_MII0_RXD1|UART3_CTSN|GPIO2_16_U3") (pintype "bidirectional"))
      (node (ref "U$81") (pin "P8") (pinfunction "P$8_P8") (pintype "bidirectional"))
    )
    (net (code "153") (name "45.LCD_DD11") (class "Default")
      (node (ref "RP8") (pin "14") (pinfunction "14_14") (pintype "passive"))
      (node (ref "U$67") (pin "19") (pinfunction "2B4_19") (pintype "bidirectional"))
      (node (ref "U$72") (pin "U4") (pinfunction "LCD_DATA11|GPMC_A15|EHRPWM1B|MCASP0_AHCLKR|MCASP0_AXR2|PR1_MII0_RXD0|UART3_RTSN|GPIO2_17_U4") (pintype "bidirectional"))
      (node (ref "U$82") (pin "P6") (pinfunction "P$6_P6") (pintype "bidirectional"))
    )
    (net (code "154") (name "45.LCD_DD12") (class "Default")
      (node (ref "RP8") (pin "13") (pinfunction "13_13") (pintype "passive"))
      (node (ref "U$67") (pin "17") (pinfunction "2B3_17") (pintype "bidirectional"))
      (node (ref "U$72") (pin "V2") (pinfunction "LCD_DATA12|GPMC_A16|EQEP1A_IN|MCASP0_ACLKR|MCASP0_AXR2|PR1_MII0_RXLINK|UART4_CTSN|GPIO0_8_V2") (pintype "bidirectional"))
      (node (ref "U$81") (pin "P7") (pinfunction "P$7_P7") (pintype "bidirectional"))
    )
    (net (code "155") (name "45.LCD_DD13") (class "Default")
      (node (ref "RP8") (pin "12") (pinfunction "12_12") (pintype "passive"))
      (node (ref "U$67") (pin "16") (pinfunction "2B2_16") (pintype "bidirectional"))
      (node (ref "U$72") (pin "V3") (pinfunction "LCD_DATA13|GPMC_A17|EQEP1B_IN|MCASP0_FSR|MCASP0_AXR3|PR1_MII0_RXER|UART4_RTSN|GPIO0_9_V3") (pintype "bidirectional"))
      (node (ref "U$82") (pin "P5") (pinfunction "P$5_P5") (pintype "bidirectional"))
    )
    (net (code "156") (name "45.LCD_DD14") (class "Default")
      (node (ref "RP8") (pin "10") (pinfunction "10_10") (pintype "passive"))
      (node (ref "U$67") (pin "14") (pinfunction "2B1_14") (pintype "bidirectional"))
      (node (ref "U$72") (pin "V4") (pinfunction "LCD_DATA14|GPMC_A18|EQEP1_INDEX|MCASP0_AXR1|UART5_RXD|PR1_MII_MR0_CLK|UART5_CTSN|GPIO0_10_V4") (pintype "bidirectional"))
      (node (ref "U$82") (pin "P7") (pinfunction "P$7_P7") (pintype "bidirectional"))
    )
    (net (code "157") (name "45.LCD_DD15") (class "Default")
      (node (ref "RP8") (pin "9") (pinfunction "9_9") (pintype "passive"))
      (node (ref "U$67") (pin "13") (pinfunction "2B0_13") (pintype "bidirectional"))
      (node (ref "U$72") (pin "T5") (pinfunction "LCD_DATA15|GPMC_A19|EQEP1_STROBE|MCASP0_AHCLKX|MCASP0_AXR3|PR1_MII0_RXDV|UART5_RTSN|GPIO0_11_T5") (pintype "bidirectional"))
      (node (ref "U$82") (pin "P8") (pinfunction "P$8_P8") (pintype "bidirectional"))
    )
    (net (code "158") (name "45.LCD_DD16") (class "Default")
      (node (ref "RP10") (pin "14") (pinfunction "14_14") (pintype "passive"))
      (node (ref "U$68") (pin "20") (pinfunction "2B5_20") (pintype "bidirectional"))
      (node (ref "U$72") (pin "U13") (pinfunction "GPMC_AD15|LCD_DATA16|MMC1_DAT7|MMC2_DAT3|EQEP2_STROBE|PR1_ECAP0_ECAP_CAPIN_APWM_O|PR1_PRU0_PRU_R31_15|GPIO1_15_U13") (pintype "bidirectional"))
    )
    (net (code "159") (name "45.LCD_DD17") (class "Default")
      (node (ref "RP8") (pin "15") (pinfunction "15_15") (pintype "passive"))
      (node (ref "U$67") (pin "20") (pinfunction "2B5_20") (pintype "bidirectional"))
      (node (ref "U$72") (pin "V13") (pinfunction "GPMC_AD14|LCD_DATA17|MMC1_DAT6|MMC2_DAT2|EQEP2_INDEX|PR1_MII0_TXD0|PR1_PRU0_PRU_R31_14|GPIO1_14_V13") (pintype "bidirectional"))
    )
    (net (code "160") (name "45.LCD_DD18") (class "Default")
      (node (ref "RP10") (pin "15") (pinfunction "15_15") (pintype "passive"))
      (node (ref "U$68") (pin "22") (pinfunction "2B6_22") (pintype "bidirectional"))
      (node (ref "U$72") (pin "R12") (pinfunction "GPMC_AD13|LCD_DATA18|MMC1_DAT5|MMC2_DAT1|EQEP2B_IN|PR1_MII0_TXD1|PR1_PRU0_PRU_R30_15|GPIO1_13_R12") (pintype "bidirectional"))
    )
    (net (code "161") (name "45.LCD_DD19") (class "Default")
      (node (ref "RP9") (pin "15") (pinfunction "15_15") (pintype "passive"))
      (node (ref "U$68") (pin "11") (pinfunction "1B6_11") (pintype "bidirectional"))
      (node (ref "U$72") (pin "T12") (pinfunction "GPMC_AD12|LCD_DATA19|MMC1_DAT4|MMC2_DAT0|EQEP2A_IN|PR1_MII0_TXD2|PR1_PRU0_PRU_R30_14|GPIO1_12_T12") (pintype "bidirectional"))
    )
    (net (code "162") (name "45.LCD_DD20") (class "Default")
      (node (ref "RP8") (pin "16") (pinfunction "16_16") (pintype "passive"))
      (node (ref "U$67") (pin "22") (pinfunction "2B6_22") (pintype "bidirectional"))
      (node (ref "U$72") (pin "U12") (pinfunction "GPMC_AD11|LCD_DATA20|MMC1_DAT3|MMC2_DAT7|EHRPWM2_SYNCI_O|PR1_MII0_TXD3||GPIO0_27_U12") (pintype "bidirectional"))
    )
    (net (code "163") (name "45.LCD_DD21") (class "Default")
      (node (ref "RP10") (pin "16") (pinfunction "16_16") (pintype "passive"))
      (node (ref "U$68") (pin "23") (pinfunction "2B7_23") (pintype "bidirectional"))
      (node (ref "U$72") (pin "T11") (pinfunction "GPMC_AD10|LCD_DATA21|MMC1_DAT2|MMC2_DAT6|EHRPWM2_TRIPZONE_INPUT|PR1_MII0_TXEN||GPIO0_26_T11") (pintype "bidirectional"))
    )
    (net (code "164") (name "45.LCD_DD22") (class "Default")
      (node (ref "RP9") (pin "16") (pinfunction "16_16") (pintype "passive"))
      (node (ref "U$68") (pin "12") (pinfunction "1B7_12") (pintype "bidirectional"))
      (node (ref "U$72") (pin "T10") (pinfunction "GPMC_AD9|LCD_DATA22|MMC1_DAT1|MMC2_DAT5|EHRPWM2B|PR1_MII0_CRS||GPIO0_23_T10") (pintype "bidirectional"))
    )
    (net (code "165") (name "45.LCD_DD23") (class "Default")
      (node (ref "R113") (pin "1") (pinfunction "1_1") (pintype "passive"))
      (node (ref "U$67") (pin "23") (pinfunction "2B7_23") (pintype "bidirectional"))
      (node (ref "U$72") (pin "U10") (pinfunction "GPMC_AD8|LCD_DATA23|MMC1_DAT0|MMC2_DAT4|EHRPWM2A|PR1_MII_MT0_CLK||GPIO0_22_U10") (pintype "bidirectional"))
    )
    (net (code "166") (name "45.LCD_HSYNC") (class "Default")
      (node (ref "R117") (pin "1") (pinfunction "1_1") (pintype "passive"))
      (node (ref "U$67") (pin "9") (pinfunction "1B5_9") (pintype "bidirectional"))
      (node (ref "U$72") (pin "R5") (pinfunction "LCD_HSYNC|GPMC_A9||PR1_EDIO_DATA_IN3|PR1_EDIO_DATA_OUT3|PR1_PRU1_PRU_R30_9|PR1_PRU1_PRU_R31_9|GPIO2_23_R5") (pintype "output"))
    )
    (net (code "167") (name "45.LCD_PCLK") (class "Default")
      (node (ref "RP8") (pin "11") (pinfunction "11_11") (pintype "passive"))
      (node (ref "U$67") (pin "12") (pinfunction "1B7_12") (pintype "bidirectional"))
      (node (ref "U$72") (pin "V5") (pinfunction "LCD_PCLK|GPMC_A10||PR1_EDIO_DATA_IN4|PR1_EDIO_DATA_OUT4|PR1_PRU1_PRU_R30_10|PR1_PRU1_PRU_R31_10|GPIO2_24_V5") (pintype "output"))
    )
    (net (code "168") (name "45.LCD_VSYNC") (class "Default")
      (node (ref "R116") (pin "1") (pinfunction "1_1") (pintype "passive"))
      (node (ref "U$67") (pin "8") (pinfunction "1B4_8") (pintype "bidirectional"))
      (node (ref "U$72") (pin "U5") (pinfunction "LCD_VSYNC|GPMC_A8||PR1_EDIO_DATA_IN2|PR1_EDIO_DATA_OUT2|PR1_PRU1_PRU_R30_8|PR1_PRU1_PRU_R31_8|GPIO2_22_U5") (pintype "output"))
    )
    (net (code "169") (name "45.MCASP0_ACLKX") (class "Default")
      (node (ref "U$72") (pin "K18") (pinfunction "GMII1_TXCLK|UART2_RXD|RGMII1_TCLK|MMC0_DAT7|MMC1_DAT0|UART1_DCDN|MCASP0_ACLKX|GPIO3_9_K18") (pintype "input"))
      (node (ref "U15") (pin "38") (pinfunction "BCLK_38") (pintype "bidirectional"))
    )
    (net (code "170") (name "45.MCASP0_AXR0") (class "Default")
      (node (ref "U$72") (pin "L17") (pinfunction "GMII1_RXD3|UART3_RXD|RGMII1_RD3|MMC0_DAT5|MMC1_DAT2|UART1_DTRN|MCASP0_AXR0|GPIO2_18_L17") (pintype "input"))
      (node (ref "U15") (pin "40") (pinfunction "DIN_40") (pintype "bidirectional"))
    )
    (net (code "171") (name "45.MCASP0_AXR1") (class "Default")
      (node (ref "U$72") (pin "D13") (pinfunction "MCASP0_AXR1|EQEP0_INDEX||MCASP1_AXR0|EMU3|PR1_PRU0_PRU_R30_6|PR1_PRU0_PRU_R31_6|GPIO3_20_D13") (pintype "bidirectional"))
      (node (ref "U15") (pin "41") (pinfunction "DOUT_41") (pintype "bidirectional"))
    )
    (net (code "172") (name "45.MCASP0_FSX") (class "Default")
      (node (ref "U$72") (pin "L18") (pinfunction "GMII1_RXCLK|UART2_TXD|RGMII1_RCLK|MMC0_DAT6|MMC1_DAT1|UART1_DSRN|MCASP0_FSX|GPIO3_10_L18") (pintype "input"))
      (node (ref "U15") (pin "39") (pinfunction "WCLK_39") (pintype "bidirectional"))
    )
    (net (code "173") (name "45.MMC2_CLK") (class "Default")
      (node (ref "RP5") (pin "7") (pinfunction "7_7") (pintype "passive"))
      (node (ref "RP6") (pin "10") (pinfunction "10_10") (pintype "passive"))
      (node (ref "U$72") (pin "V12") (pinfunction "GPMC_CLK|LCD_MEM_CLK|GPMC_WAIT1|MMC2_CLK|PRT1_MII1_TXEN|MCASP0_FSR|GPIO2_1_V12") (pintype "output"))
    )
    (net (code "174") (name "45.MMC2_CMD") (class "Default")
      (node (ref "RP5") (pin "8") (pinfunction "8_8") (pintype "passive"))
      (node (ref "RP6") (pin "9") (pinfunction "9_9") (pintype "passive"))
      (node (ref "U$72") (pin "T13") (pinfunction "GPMC_CSN3|MMC2_CMD|PR1_MDIO_DATA|GPIO2_0_T13") (pintype "output"))
    )
    (net (code "175") (name "45.MMC2_DAT0") (class "Default")
      (node (ref "RP5") (pin "5") (pinfunction "5_5") (pintype "passive"))
      (node (ref "RP6") (pin "12") (pinfunction "12_12") (pintype "passive"))
      (node (ref "U$72") (pin "V14") (pinfunction "GPMC_A1|GMII2_RXDV|RGMII2_RCTL|MMC2_DAT0|GPMC_A17|PR1_MII1_TXD3|EHRPWM1_SYNCI_O|GPIO1_17_V14") (pintype "output"))
    )
    (net (code "176") (name "45.MMC2_DAT1") (class "Default")
      (node (ref "RP5") (pin "4") (pinfunction "4_4") (pintype "passive"))
      (node (ref "RP6") (pin "13") (pinfunction "13_13") (pintype "passive"))
      (node (ref "U$72") (pin "U14") (pinfunction "GPMC_A2|GMII2_TXD3|RGMII2_TD3|MMC2_DAT1|GPMC_A18|PR1_MII1_TXD2|EHRPWM1A|GPIO1_18_U14") (pintype "output"))
    )
    (net (code "177") (name "45.MMC2_DAT2") (class "Default")
      (node (ref "RP5") (pin "2") (pinfunction "2_2") (pintype "passive"))
      (node (ref "RP6") (pin "15") (pinfunction "15_15") (pintype "passive"))
      (node (ref "U$72") (pin "T14") (pinfunction "GPMC_A3|GMII2_TXD2|RGMII2_TD2|MMC2_DAT2|GPMC_A19|PR1_MII1_TXD1|EHRPWM1B|GPIO1_19_T14") (pintype "output"))
    )
    (net (code "178") (name "45.MMC2_DAT3") (class "Default")
      (node (ref "RP5") (pin "1") (pinfunction "1_1") (pintype "passive"))
      (node (ref "RP6") (pin "16") (pinfunction "16_16") (pintype "passive"))
      (node (ref "U$72") (pin "U18") (pinfunction "GPMC_BE1N|GMII2_COL|GPMC_CSN6|MMC2_DAT3|GPMC_DIR|PR1_MII1_RXLINK|MCASP0_ACLKR|GPIO1_28_U18") (pintype "output"))
    )
    (net (code "179") (name "45.PMIC_PGOOD") (class "Default")
      (node (ref "IC1") (pin "13") (pinfunction "ENABLE_13") (pintype "input"))
      (node (ref "U$72") (pin "B15") (pinfunction "PWRONRSTN_B15") (pintype "input"))
      (node (ref "U35") (pin "26") (pinfunction "PGOOD_26") (pintype "open_collector"))
    )
    (net (code "180") (name "45.SPI0_CLK") (class "Default")
      (node (ref "U$67") (pin "2") (pinfunction "1B0_2") (pintype "bidirectional"))
      (node (ref "U$72") (pin "A17") (pinfunction "SPI0_SCLK|UART2_RXD|I2C2_SDA|EHRPWM0A|PR1_UART0_CTS_N|PR1_EDIO_SOF|EMU2|GPIO0_2_A17") (pintype "bidirectional"))
    )
    (net (code "181") (name "45.SPI0_CS0") (class "Default")
      (node (ref "U$67") (pin "3") (pinfunction "1B1_3") (pintype "bidirectional"))
      (node (ref "U$72") (pin "A16") (pinfunction "SPI0_CS0|MMC2_SDWP|I2C1_SCL|EHRPWM0_SYNCI_O|PR1_UART0_TXD|PR1_EDIO_DATA_IN1|PR1_EDIO_DATA_OUT1|GPIO0_5_A16") (pintype "bidirectional"))
    )
    (net (code "182") (name "45.SPI0_MISO") (class "Default")
      (node (ref "U$69") (pin "8") (pinfunction "1B4_8") (pintype "bidirectional"))
      (node (ref "U$72") (pin "B17") (pinfunction "SPI0_D0|UART2_TXD|I2C2_SCL|EHRPWM0B|PR1_UART0_RTS_N|PR1_EDIO_LATCH_IN|EMU3|GPIO0_3_B17") (pintype "bidirectional"))
    )
    (net (code "183") (name "45.SPI0_MOSI") (class "Default")
      (node (ref "U$67") (pin "5") (pinfunction "1B2_5") (pintype "bidirectional"))
      (node (ref "U$72") (pin "B16") (pinfunction "SPI0_D1|MMC1_SDWP|I2C1_SDA|EHRPWM0_TRIPZONE_INPUT|PR1_UART0_RXD|PR1_EDIO_DATA_IN0|PR1_EDIO_DATA_OUT0|GPIO0_4_B16") (pintype "bidirectional"))
    )
    (net (code "184") (name "45.SPI1_CLK") (class "Default")
      (node (ref "RP3") (pin "2") (pinfunction "2_2") (pintype "passive"))
      (node (ref "U$72") (pin "A13") (pinfunction "MCASP0_ACLKX|EHRPWM0A||SPI1_SCLK|MMC0_SDCD|PR1_PRU0_PRU_R30_0|PR1_PRU0_PRU_R31_0|GPIO3_14_A13") (pintype "bidirectional"))
      (node (ref "U8") (pin "7") (pinfunction "A6_7") (pintype "bidirectional"))
    )
    (net (code "185") (name "45.SPI1_CS0") (class "Default")
      (node (ref "RP3") (pin "3") (pinfunction "3_3") (pintype "passive"))
      (node (ref "U$72") (pin "C12") (pinfunction "MCASP0_AHCLKR|EHRPWM0_SYNCI_O|MCASP0_AXR2|SPI1_CS0|ECAP2_IN_PWM2_OUT|PR1_PRU0_PRU_R30_3|PR1_PRU0_PRU_R31_3|GPIO3_17_C12") (pintype "bidirectional"))
      (node (ref "U8") (pin "5") (pinfunction "A4_5") (pintype "bidirectional"))
    )
    (net (code "186") (name "45.SPI1_MISO") (class "Default")
      (node (ref "RP3") (pin "4") (pinfunction "4_4") (pintype "passive"))
      (node (ref "U$72") (pin "B13") (pinfunction "MCASP0_FSX|EHRPWM0B||SPI1_D0|MMC1_SDCD|PR1_PRU0_PRU_R30_1|PR1_PRU0_PRU_R31_1|GPIO3_15_B13") (pintype "bidirectional"))
      (node (ref "U8") (pin "4") (pinfunction "A3_4") (pintype "bidirectional"))
    )
    (net (code "187") (name "45.SPI1_MOSI") (class "Default")
      (node (ref "RP3") (pin "1") (pinfunction "1_1") (pintype "passive"))
      (node (ref "U$72") (pin "D12") (pinfunction "MCASP0_AXR0|EHRPWM0_TRIPZONE_INPUT||SPI1_D1|MMC2_SDCD|PR1_PRU0_PRU_R30_2|PR1_PRU0_PRU_R31_2|GPIO3_16_D12") (pintype "bidirectional"))
      (node (ref "U8") (pin "8") (pinfunction "A7_8") (pintype "bidirectional"))
    )
    (net (code "188") (name "45.UART0_RX") (class "Default")
      (node (ref "U$72") (pin "E15") (pinfunction "UART0_RXD|SPI1_CS0|DCAN0_TX|I2C2_SDA|ECAP2_IN_PWM2_OUT|PR1_PRU1_PRU_R30_14|PR1_PRU1_PRU_R31_14|GPIO1_10_E15") (pintype "input"))
      (node (ref "U27") (pin "2") (pinfunction "A1_2") (pintype "input"))
    )
    (net (code "189") (name "45.UART0_TX") (class "Default")
      (node (ref "U$72") (pin "E16") (pinfunction "UART0_TXD|SPI1_CS1|DCAN0_RX|I2C2_SCL|ECAP1_IN_PWM1_OUT|PR1_PRU1_PRU_R30_15|PR1_PRU1_PRU_R31_15|GPIO1_11_E16") (pintype "output"))
      (node (ref "U27") (pin "3") (pinfunction "A2_3") (pintype "input"))
    )
    (net (code "190") (name "45.UART1_RX") (class "Default")
      (node (ref "R36") (pin "1") (pinfunction "1_1") (pintype "passive"))
      (node (ref "U$72") (pin "D16") (pinfunction "UART1_RXD|MMC1_SDWP|DCAN1_TX|I2C1_SDA||PR1_UART0_RXD|PR1_PRU1_PRU_R31_16|GPIO0_14_D16") (pintype "input"))
      (node (ref "U16") (pin "8") (pinfunction "A1_8") (pintype "bidirectional"))
    )
    (net (code "191") (name "45.UART1_TX") (class "Default")
      (node (ref "R37") (pin "1") (pinfunction "1_1") (pintype "passive"))
      (node (ref "U$72") (pin "D15") (pinfunction "UART1_TXD|MMC2_SDWP|DCAN1_RX|I2C1_SCL||PR1_UART0_TXD|PR1_PRU0_PRU_R31_16|GPIO0_15_D15") (pintype "output"))
      (node (ref "U16") (pin "9") (pinfunction "A2_9") (pintype "bidirectional"))
    )
    (net (code "192") (name "45.UART5_CTS") (class "Default")
      (node (ref "U$72") (pin "H17") (pinfunction "GMII1_CRS|RMII1_CRS_DV|SPI1_D0|I2C1_SDA|MCASP1_ACLKX|UART5_CTSN|UART2_RXD|GPIO3_1_H17") (pintype "input"))
      (node (ref "U28") (pin "50") (pinfunction "BT_HCI_RTS_50") (pintype "bidirectional"))
    )
    (net (code "193") (name "45.UART5_RTS") (class "Default")
      (node (ref "U$72") (pin "J15") (pinfunction "GMII1_RXERR|RMII1_RXERR|SPI1_D1|I2C1_SCL|MCASP1_FSX|UART5_RTSN|UART2_TXD|GPIO3_2_J15") (pintype "input"))
      (node (ref "U28") (pin "51") (pinfunction "BT_HCI_CTS_51") (pintype "bidirectional"))
    )
    (net (code "194") (name "45.UART5_RX") (class "Default")
      (node (ref "U$72") (pin "H16") (pinfunction "GMII1_COL|RMII2_REFCLK|SPI1_SCLK|UART5_RXD|MCASP1_AXR2|MMC2_DAT3|MCASP0_AXR2|GPIO3_0_H16") (pintype "input"))
      (node (ref "U28") (pin "52") (pinfunction "BT_HCI_TX_52") (pintype "bidirectional"))
    )
    (net (code "195") (name "45.UART5_TX") (class "Default")
      (node (ref "U$72") (pin "J17") (pinfunction "GMII1_RXDV|LCD_MEMORY_CLK|RGMII1_RCTL|UART5_TXD|MCASP1_ACLKX|MMC2_DAT0|MCASP0_ACLKR|GPIO3_4_J17") (pintype "input"))
      (node (ref "U28") (pin "53") (pinfunction "BT_HCI_RX_53") (pintype "bidirectional"))
    )
    (net (code "196") (name "45.USB_DEVICE_0_N") (class "Default")
      (node (ref "L6") (pin "2") (pinfunction "2_2") (pintype "passive"))
      (node (ref "U$72") (pin "N18") (pinfunction "USB0_DM_N18") (pintype "bidirectional"))
    )
    (net (code "197") (name "45.USB_DEVICE_0_P") (class "Default")
      (node (ref "L6") (pin "3") (pinfunction "3_3") (pintype "passive"))
      (node (ref "U$72") (pin "N17") (pinfunction "USB0_DP_N17") (pintype "bidirectional"))
    )
    (net (code "198") (name "45.USB_DEVICE_0_VBUS") (class "Default")
      (node (ref "R82") (pin "1") (pinfunction "1_1") (pintype "passive"))
      (node (ref "U$72") (pin "P15") (pinfunction "USB0_VBUS_P15") (pintype "bidirectional"))
    )
    (net (code "199") (name "45.USB_HOST_1_N") (class "Default")
      (node (ref "U$72") (pin "R18") (pinfunction "USB1_DM_R18") (pintype "bidirectional"))
      (node (ref "U18") (pin "30") (pinfunction "USBDM_UP_30") (pintype "bidirectional"))
    )
    (net (code "200") (name "45.USB_HOST_1_P") (class "Default")
      (node (ref "U$72") (pin "R17") (pinfunction "USB1_DP_R17") (pintype "bidirectional"))
      (node (ref "U18") (pin "31") (pinfunction "USBDP_UP_31") (pintype "bidirectional"))
    )
    (net (code "201") (name "45.USB_HOST_1_PWREN") (class "Default")
      (node (ref "R44") (pin "2") (pinfunction "2_2") (pintype "passive"))
      (node (ref "U$72") (pin "F15") (pinfunction "USB1_DRVVBUS_F15") (pintype "output"))
      (node (ref "U18") (pin "27") (pinfunction "VBUS_DET_27") (pintype "passive"))
    )
    (net (code "202") (name "45.USB_HOST_1_VBUS") (class "Default")
      (node (ref "R110") (pin "1") (pinfunction "1_1") (pintype "passive"))
      (node (ref "U$72") (pin "T18") (pinfunction "USB1_VBUS_T18") (pintype "bidirectional"))
    )
    (net (code "203") (name "46.VCC_5.0") (class "Default")
      (node (ref "C1") (pin "1") (pinfunction "1_1") (pintype "passive"))
      (node (ref "C113") (pin "1") (pinfunction "1_1") (pintype "passive"))
      (node (ref "C114") (pin "1") (pinfunction "1_1") (pintype "passive"))
      (node (ref "C162") (pin "1") (pinfunction "1_1") (pintype "passive"))
      (node (ref "C2") (pin "1") (pinfunction "1_1") (pintype "passive"))
      (node (ref "C22") (pin "1") (pinfunction "1_1") (pintype "passive"))
      (node (ref "C221") (pin "1") (pinfunction "1_1") (pintype "passive"))
      (node (ref "C23") (pin "1") (pinfunction "1_1") (pintype "passive"))
      (node (ref "C265") (pin "1") (pinfunction "1_1") (pintype "passive"))
      (node (ref "C266") (pin "+") (pinfunction "1_+") (pintype "passive"))
      (node (ref "C28") (pin "1") (pinfunction "1_1") (pintype "passive"))
      (node (ref "C94") (pin "1") (pinfunction "1_1") (pintype "passive"))
      (node (ref "C95") (pin "1") (pinfunction "1_1") (pintype "passive"))
      (node (ref "C97") (pin "1") (pinfunction "1_1") (pintype "passive"))
      (node (ref "C98") (pin "1") (pinfunction "1_1") (pintype "passive"))
      (node (ref "FB10") (pin "1") (pinfunction "1_1") (pintype "passive"))
      (node (ref "FB2") (pin "1") (pinfunction "1_1") (pintype "passive"))
      (node (ref "J15") (pin "19") (pinfunction "18_19") (pintype "passive"))
      (node (ref "L15") (pin "2") (pinfunction "2_2") (pintype "passive"))
      (node (ref "R106") (pin "1") (pinfunction "1_1") (pintype "passive"))
      (node (ref "R109") (pin "1") (pinfunction "1_1") (pintype "passive"))
      (node (ref "R110") (pin "2") (pinfunction "2_2") (pintype "passive"))
      (node (ref "R112") (pin "1") (pinfunction "1_1") (pintype "passive"))
      (node (ref "R141") (pin "1") (pinfunction "1_1") (pintype "passive"))
      (node (ref "R18") (pin "2") (pinfunction "2_2") (pintype "passive"))
      (node (ref "U1") (pin "8") (pinfunction "VCCB_8") (pintype "power_in"))
      (node (ref "U11") (pin "8") (pinfunction "VCCB_8") (pintype "power_in"))
      (node (ref "U20") (pin "19") (pinfunction "VCCB_19") (pintype "power_in"))
      (node (ref "U21") (pin "8") (pinfunction "VCCB_8") (pintype "power_in"))
      (node (ref "U27") (pin "8") (pinfunction "VCCB_8") (pintype "power_in"))
    )
    (net (code "204") (name "ACCEL_C1$132") (class "Default")
      (node (ref "C268") (pin "1") (pinfunction "1_1") (pintype "passive"))
      (node (ref "U37") (pin "15") (pinfunction "C1_15") (pintype "power_in"))
    )
    (net (code "205") (name "ACCEL_SET1$132") (class "Default")
      (node (ref "C270") (pin "1") (pinfunction "1_1") (pintype "passive"))
      (node (ref "U37") (pin "3") (pinfunction "SETP_3") (pintype "passive"))
    )
    (net (code "206") (name "ACCEL_SET2$132") (class "Default")
      (node (ref "C270") (pin "2") (pinfunction "2_2") (pintype "passive"))
      (node (ref "U37") (pin "2") (pinfunction "SETC_2") (pintype "power_in"))
    )
    (net (code "207") (name "ACLK$33") (class "Default")
      (node (ref "ACLK") (pin "1") (pinfunction "TP_1") (pintype "bidirectional"))
      (node (ref "U28") (pin "60") (pinfunction "BT_AUD_CLK_60") (pintype "bidirectional"))
    )
    (net (code "208") (name "ACS0$33") (class "Default")
      (node (ref "ACS0") (pin "1") (pinfunction "TP_1") (pintype "bidirectional"))
      (node (ref "U28") (pin "58") (pinfunction "BT_AUD_FSYNC_58") (pintype "bidirectional"))
    )
    (net (code "209") (name "ADC123_IN10$39") (class "Default")
      (node (ref "IC3") (pin "15") (pinfunction "PC0_15") (pintype "bidirectional"))
      (node (ref "R88") (pin "2") (pinfunction "2_2") (pintype "passive"))
      (node (ref "R89") (pin "1") (pinfunction "1_1") (pintype "passive"))
    )
    (net (code "210") (name "AGND$45") (class "Default")
      (node (ref "FB11") (pin "1") (pinfunction "1_1") (pintype "passive"))
      (node (ref "U$72") (pin "A9") (pinfunction "VREFN_A9") (pintype "bidirectional"))
      (node (ref "U$72") (pin "E8") (pinfunction "VSSA_ADC_E8") (pintype "power_in"))
    )
    (net (code "211") (name "AIN7$45") (class "Default")
      (node (ref "U$72") (pin "C9") (pinfunction "AIN7_C9") (pintype "bidirectional"))
      (node (ref "U35") (pin "16") (pinfunction "MUX_OUT_16") (pintype "output"))
    )
    (net (code "212") (name "ARX$33") (class "Default")
      (node (ref "ARX") (pin "1") (pinfunction "TP_1") (pintype "bidirectional"))
      (node (ref "U28") (pin "56") (pinfunction "BT_AUD_IN_56") (pintype "bidirectional"))
    )
    (net (code "213") (name "ATX$33") (class "Default")
      (node (ref "ATX") (pin "1") (pinfunction "TP_1") (pintype "bidirectional"))
      (node (ref "U28") (pin "57") (pinfunction "BT_AUD_OUT_57") (pintype "bidirectional"))
    )
    (net (code "214") (name "AVCC$45") (class "Default")
      (node (ref "C251") (pin "1") (pinfunction "1_1") (pintype "passive"))
      (node (ref "FB12") (pin "2") (pinfunction "2_2") (pintype "passive"))
      (node (ref "U$72") (pin "B9") (pinfunction "VREFP_B9") (pintype "bidirectional"))
      (node (ref "U$72") (pin "D8") (pinfunction "VDDA_ADC_D8") (pintype "power_in"))
    )
    (net (code "215") (name "A_GNDF$14") (class "Default")
      (node (ref "C27") (pin "1") (pinfunction "1_1") (pintype "passive"))
      (node (ref "D6") (pin "P2") (pinfunction "P2_P2") (pintype "passive"))
      (node (ref "FB1") (pin "2") (pinfunction "2_2") (pintype "passive"))
      (node (ref "K1") (pin "A4") (pinfunction "GND_A4") (pintype "bidirectional"))
      (node (ref "K1") (pin "B4") (pinfunction "GND_B4") (pintype "bidirectional"))
    )
    (net (code "216") (name "A_USB_DM$14") (class "Default")
      (node (ref "D3") (pin "P2") (pinfunction "P2_P2") (pintype "passive"))
      (node (ref "K1") (pin "A2") (pinfunction "D-_A2") (pintype "bidirectional"))
      (node (ref "L3") (pin "1") (pinfunction "1_1") (pintype "passive"))
    )
    (net (code "217") (name "A_USB_DP$14") (class "Default")
      (node (ref "D4") (pin "P2") (pinfunction "P2_P2") (pintype "passive"))
      (node (ref "K1") (pin "A3") (pinfunction "D+_A3") (pintype "bidirectional"))
      (node (ref "L3") (pin "4") (pinfunction "4_4") (pintype "passive"))
    )
    (net (code "218") (name "BAT$45") (class "Default")
      (node (ref "U35") (pin "4") (pinfunction "BAT1_4") (pintype "bidirectional"))
      (node (ref "U35") (pin "5") (pinfunction "BAT2_5") (pintype "bidirectional"))
      (node (ref "U35") (pin "6") (pinfunction "BAT_SENSE_6") (pintype "input"))
    )
    (net (code "219") (name "BLUE0$43") (class "Default")
      (node (ref "U$67") (pin "26") (pinfunction "2A7_26") (pintype "bidirectional"))
      (node (ref "U$70") (pin "21") (pinfunction "B0_21") (pintype "output"))
    )
    (net (code "220") (name "BLUE1$43") (class "Default")
      (node (ref "U$67") (pin "27") (pinfunction "2A6_27") (pintype "bidirectional"))
      (node (ref "U$70") (pin "22") (pinfunction "B1_22") (pintype "output"))
    )
    (net (code "221") (name "BLUE2$43") (class "Default")
      (node (ref "U$67") (pin "29") (pinfunction "2A5_29") (pintype "bidirectional"))
      (node (ref "U$70") (pin "23") (pinfunction "B2_23") (pintype "output"))
    )
    (net (code "222") (name "BLUE3$43") (class "Default")
      (node (ref "U$67") (pin "30") (pinfunction "2A4_30") (pintype "bidirectional"))
      (node (ref "U$70") (pin "24") (pinfunction "B3_24") (pintype "output"))
    )
    (net (code "223") (name "BLUE4$43") (class "Default")
      (node (ref "U$67") (pin "32") (pinfunction "2A3_32") (pintype "bidirectional"))
      (node (ref "U$70") (pin "25") (pinfunction "B4_25") (pintype "output"))
    )
    (net (code "224") (name "BLUE5$43") (class "Default")
      (node (ref "U$67") (pin "33") (pinfunction "2A2_33") (pintype "bidirectional"))
      (node (ref "U$70") (pin "26") (pinfunction "B5_26") (pintype "output"))
    )
    (net (code "225") (name "BLUE6$43") (class "Default")
      (node (ref "U$67") (pin "35") (pinfunction "2A1_35") (pintype "bidirectional"))
      (node (ref "U$70") (pin "27") (pinfunction "B6_27") (pintype "output"))
    )
    (net (code "226") (name "BLUE7$43") (class "Default")
      (node (ref "U$67") (pin "36") (pinfunction "2A0_36") (pintype "bidirectional"))
      (node (ref "U$70") (pin "28") (pinfunction "B7_28") (pintype "output"))
    )
    (net (code "227") (name "BOOT1$39") (class "Default")
      (node (ref "IC3") (pin "37") (pinfunction "PB2_37") (pintype "bidirectional"))
      (node (ref "R86") (pin "2") (pinfunction "2_2") (pintype "passive"))
    )
    (net (code "228") (name "BT4$33") (class "Default")
      (node (ref "BT4") (pin "1") (pinfunction "TP_1") (pintype "bidirectional"))
      (node (ref "U28") (pin "43") (pinfunction "BT_UART_DBG_43") (pintype "bidirectional"))
    )
    (net (code "229") (name "BYPASS$45") (class "Default")
      (node (ref "C224") (pin "1") (pinfunction "1_1") (pintype "passive"))
      (node (ref "U35") (pin "47") (pinfunction "BYPASS_47") (pintype "output"))
    )
    (net (code "230") (name "B_USB_DM$14") (class "Default")
      (node (ref "D7") (pin "P2") (pinfunction "P2_P2") (pintype "passive"))
      (node (ref "K1") (pin "B2") (pinfunction "D-_B2") (pintype "bidirectional"))
      (node (ref "L4") (pin "1") (pinfunction "1_1") (pintype "passive"))
    )
    (net (code "231") (name "B_USB_DP$14") (class "Default")
      (node (ref "D8") (pin "P2") (pinfunction "P2_P2") (pintype "passive"))
      (node (ref "K1") (pin "B3") (pinfunction "D+_B3") (pintype "bidirectional"))
      (node (ref "L4") (pin "4") (pinfunction "4_4") (pintype "passive"))
    )
    (net (code "232") (name "C+$44") (class "Default")
      (node (ref "D27") (pin "P2") (pinfunction "P2_P2") (pintype "passive"))
      (node (ref "J15") (pin "12") (pinfunction "10_12") (pintype "passive"))
      (node (ref "L10") (pin "2") (pinfunction "2_2") (pintype "passive"))
    )
    (net (code "233") (name "C-$44") (class "Default")
      (node (ref "D28") (pin "P2") (pinfunction "P2_P2") (pintype "passive"))
      (node (ref "J15") (pin "14") (pinfunction "12_14") (pintype "passive"))
      (node (ref "L10") (pin "3") (pinfunction "3_3") (pintype "passive"))
    )
    (net (code "234") (name "CLK$24") (class "Default")
      (node (ref "J7") (pin "A3") (pinfunction "A3_A3") (pintype "bidirectional"))
      (node (ref "RP4") (pin "2") (pinfunction "2_2") (pintype "passive"))
      (node (ref "U20") (pin "17") (pinfunction "B3_17") (pintype "bidirectional"))
    )
    (net (code "235") (name "COMMON_SHIELD") (class "Default")
      (node (ref "D13") (pin "P1") (pinfunction "P1_P1") (pintype "passive"))
      (node (ref "D14") (pin "P1") (pinfunction "P1_P1") (pintype "passive"))
      (node (ref "D16") (pin "P1") (pinfunction "P1_P1") (pintype "passive"))
      (node (ref "D17") (pin "P1") (pinfunction "P1_P1") (pintype "passive"))
      (node (ref "D18") (pin "P1") (pinfunction "P1_P1") (pintype "passive"))
      (node (ref "D19") (pin "P1") (pinfunction "P1_P1") (pintype "passive"))
      (node (ref "D20") (pin "P1") (pinfunction "P1_P1") (pintype "passive"))
      (node (ref "D21") (pin "P1") (pinfunction "P1_P1") (pintype "passive"))
      (node (ref "D22") (pin "P1") (pinfunction "P1_P1") (pintype "passive"))
      (node (ref "D23") (pin "P1") (pinfunction "P1_P1") (pintype "passive"))
      (node (ref "D24") (pin "P1") (pinfunction "P1_P1") (pintype "passive"))
      (node (ref "D25") (pin "P1") (pinfunction "P1_P1") (pintype "passive"))
      (node (ref "D26") (pin "P1") (pinfunction "P1_P1") (pintype "passive"))
      (node (ref "D27") (pin "P1") (pinfunction "P1_P1") (pintype "passive"))
      (node (ref "D28") (pin "P1") (pinfunction "P1_P1") (pintype "passive"))
      (node (ref "D29") (pin "P1") (pinfunction "P1_P1") (pintype "passive"))
      (node (ref "D3") (pin "P1") (pinfunction "P1_P1") (pintype "passive"))
      (node (ref "D30") (pin "P1") (pinfunction "P1_P1") (pintype "passive"))
      (node (ref "D32") (pin "P1") (pinfunction "P1_P1") (pintype "passive"))
      (node (ref "D4") (pin "P1") (pinfunction "P1_P1") (pintype "passive"))
      (node (ref "D5") (pin "P1") (pinfunction "P1_P1") (pintype "passive"))
      (node (ref "D6") (pin "P1") (pinfunction "P1_P1") (pintype "passive"))
      (node (ref "D7") (pin "P1") (pinfunction "P1_P1") (pintype "passive"))
      (node (ref "D8") (pin "P1") (pinfunction "P1_P1") (pintype "passive"))
      (node (ref "D9") (pin "P1") (pinfunction "P1_P1") (pintype "passive"))
      (node (ref "J10") (pin "COMMON_SHEILD1") (pinfunction "COMMON_SHIELD1_COMMON_SHEILD1") (pintype "bidirectional"))
      (node (ref "J10") (pin "COMMON_SHEILD2") (pinfunction "COMMON_SHIELD2_COMMON_SHEILD2") (pintype "bidirectional"))
      (node (ref "J10") (pin "COMMON_SHEILD3") (pinfunction "COMMON_SHIELD3_COMMON_SHEILD3") (pintype "bidirectional"))
      (node (ref "J10") (pin "COMMON_SHEILD4") (pinfunction "COMMON_SHIELD4_COMMON_SHEILD4") (pintype "bidirectional"))
      (node (ref "J10") (pin "COMMON_SHEILD5") (pinfunction "COMMON_SHIELD5_COMMON_SHEILD5") (pintype "bidirectional"))
      (node (ref "J10") (pin "COMMON_SHEILD6") (pinfunction "COMMON_SHIELD6_COMMON_SHEILD6") (pintype "bidirectional"))
      (node (ref "J14") (pin "COMMON_SHEILD1") (pinfunction "COMMON_SHIELD1_COMMON_SHEILD1") (pintype "bidirectional"))
      (node (ref "J14") (pin "COMMON_SHEILD2") (pinfunction "COMMON_SHIELD2_COMMON_SHEILD2") (pintype "bidirectional"))
      (node (ref "J14") (pin "COMMON_SHEILD3") (pinfunction "COMMON_SHIELD3_COMMON_SHEILD3") (pintype "bidirectional"))
      (node (ref "J14") (pin "COMMON_SHEILD4") (pinfunction "COMMON_SHIELD4_COMMON_SHEILD4") (pintype "bidirectional"))
      (node (ref "J14") (pin "COMMON_SHEILD5") (pinfunction "COMMON_SHIELD5_COMMON_SHEILD5") (pintype "bidirectional"))
      (node (ref "J14") (pin "COMMON_SHEILD6") (pinfunction "COMMON_SHIELD6_COMMON_SHEILD6") (pintype "bidirectional"))
      (node (ref "J15") (pin "CON1") (pinfunction "20_CON1") (pintype "passive"))
      (node (ref "J15") (pin "CON2") (pinfunction "21_CON2") (pintype "passive"))
      (node (ref "J15") (pin "CON3") (pinfunction "22_CON3") (pintype "passive"))
      (node (ref "J15") (pin "CON4") (pinfunction "23_CON4") (pintype "passive"))
    )
    (net (code "236") (name "CS0$24") (class "Default")
      (node (ref "J7") (pin "B2") (pinfunction "B2_B2") (pintype "bidirectional"))
      (node (ref "RP4") (pin "3") (pinfunction "3_3") (pintype "passive"))
      (node (ref "U20") (pin "16") (pinfunction "B4_16") (pintype "bidirectional"))
    )
    (net (code "237") (name "D0+$44") (class "Default")
      (node (ref "D25") (pin "P2") (pinfunction "P2_P2") (pintype "passive"))
      (node (ref "J15") (pin "9") (pinfunction "7_9") (pintype "passive"))
      (node (ref "L9") (pin "2") (pinfunction "2_2") (pintype "passive"))
    )
    (net (code "238") (name "D0-$44") (class "Default")
      (node (ref "D26") (pin "P2") (pinfunction "P2_P2") (pintype "passive"))
      (node (ref "J15") (pin "11") (pinfunction "9_11") (pintype "passive"))
      (node (ref "L9") (pin "3") (pinfunction "3_3") (pintype "passive"))
    )
    (net (code "239") (name "D1+$44") (class "Default")
      (node (ref "D23") (pin "P2") (pinfunction "P2_P2") (pintype "passive"))
      (node (ref "J15") (pin "6") (pinfunction "4_6") (pintype "passive"))
      (node (ref "L8") (pin "2") (pinfunction "2_2") (pintype "passive"))
    )
    (net (code "240") (name "D1-$44") (class "Default")
      (node (ref "D24") (pin "P2") (pinfunction "P2_P2") (pintype "passive"))
      (node (ref "J15") (pin "8") (pinfunction "6_8") (pintype "passive"))
      (node (ref "L8") (pin "3") (pinfunction "3_3") (pintype "passive"))
    )
    (net (code "241") (name "D2+$44") (class "Default")
      (node (ref "D21") (pin "P2") (pinfunction "P2_P2") (pintype "passive"))
      (node (ref "J15") (pin "3") (pinfunction "1_3") (pintype "passive"))
      (node (ref "L7") (pin "2") (pinfunction "2_2") (pintype "passive"))
    )
    (net (code "242") (name "D2-$44") (class "Default")
      (node (ref "D22") (pin "P2") (pinfunction "P2_P2") (pintype "passive"))
      (node (ref "J15") (pin "5") (pinfunction "3_5") (pintype "passive"))
      (node (ref "L7") (pin "3") (pinfunction "3_3") (pintype "passive"))
    )
    (net (code "243") (name "DC_IN$45") (class "Default")
      (node (ref "C225") (pin "1") (pinfunction "1_1") (pintype "passive"))
      (node (ref "FB10") (pin "2") (pinfunction "2_2") (pintype "passive"))
      (node (ref "U35") (pin "10") (pinfunction "AC_10") (pintype "input"))
    )
    (net (code "244") (name "DDR_A0$45") (class "Default")
      (node (ref "U$101") (pin "N3") (pinfunction "A0_N3") (pintype "input"))
      (node (ref "U$72") (pin "F3") (pinfunction "DDR_A0_F3") (pintype "output"))
    )
    (net (code "245") (name "DDR_A1$45") (class "Default")
      (node (ref "U$101") (pin "P7") (pinfunction "A1_P7") (pintype "input"))
      (node (ref "U$72") (pin "H1") (pinfunction "DDR_A1_H1") (pintype "output"))
    )
    (net (code "246") (name "DDR_A2$45") (class "Default")
      (node (ref "U$101") (pin "P3") (pinfunction "A2_P3") (pintype "input"))
      (node (ref "U$72") (pin "E4") (pinfunction "DDR_A2_E4") (pintype "output"))
    )
    (net (code "247") (name "DDR_A3$45") (class "Default")
      (node (ref "U$101") (pin "N2") (pinfunction "A3_N2") (pintype "input"))
      (node (ref "U$72") (pin "C3") (pinfunction "DDR_A3_C3") (pintype "output"))
    )
    (net (code "248") (name "DDR_A4$45") (class "Default")
      (node (ref "U$101") (pin "P8") (pinfunction "A4_P8") (pintype "input"))
      (node (ref "U$72") (pin "C2") (pinfunction "DDR_A4_C2") (pintype "output"))
    )
    (net (code "249") (name "DDR_A5$45") (class "Default")
      (node (ref "U$101") (pin "P2") (pinfunction "A5_P2") (pintype "input"))
      (node (ref "U$72") (pin "B1") (pinfunction "DDR_A5_B1") (pintype "output"))
    )
    (net (code "250") (name "DDR_A6$45") (class "Default")
      (node (ref "U$101") (pin "R8") (pinfunction "A6_R8") (pintype "input"))
      (node (ref "U$72") (pin "D5") (pinfunction "DDR_A6_D5") (pintype "output"))
    )
    (net (code "251") (name "DDR_A7$45") (class "Default")
      (node (ref "U$101") (pin "R2") (pinfunction "A7_R2") (pintype "input"))
      (node (ref "U$72") (pin "E2") (pinfunction "DDR_A7_E2") (pintype "output"))
    )
    (net (code "252") (name "DDR_A8$45") (class "Default")
      (node (ref "U$101") (pin "T8") (pinfunction "A8_T8") (pintype "input"))
      (node (ref "U$72") (pin "D4") (pinfunction "DDR_A8_D4") (pintype "output"))
    )
    (net (code "253") (name "DDR_A9$45") (class "Default")
      (node (ref "U$101") (pin "R3") (pinfunction "A9_R3") (pintype "input"))
      (node (ref "U$72") (pin "C1") (pinfunction "DDR_A9_C1") (pintype "output"))
    )
    (net (code "254") (name "DDR_A10$45") (class "Default")
      (node (ref "U$101") (pin "L7") (pinfunction "A10_L7") (pintype "input"))
      (node (ref "U$72") (pin "F4") (pinfunction "DDR_A10_F4") (pintype "output"))
    )
    (net (code "255") (name "DDR_A11$45") (class "Default")
      (node (ref "U$101") (pin "R7") (pinfunction "A11_R7") (pintype "input"))
      (node (ref "U$72") (pin "F2") (pinfunction "DDR_A11_F2") (pintype "output"))
    )
    (net (code "256") (name "DDR_A12$45") (class "Default")
      (node (ref "U$101") (pin "N7") (pinfunction "A12_N7") (pintype "input"))
      (node (ref "U$72") (pin "E3") (pinfunction "DDR_A12_E3") (pintype "output"))
    )
    (net (code "257") (name "DDR_A13$45") (class "Default")
      (node (ref "U$101") (pin "T3") (pinfunction "A13_T3") (pintype "input"))
      (node (ref "U$72") (pin "H3") (pinfunction "DDR_A13_H3") (pintype "output"))
    )
    (net (code "258") (name "DDR_A14$45") (class "Default")
      (node (ref "U$101") (pin "T7") (pinfunction "A14_T7") (pintype "input"))
      (node (ref "U$72") (pin "H4") (pinfunction "DDR_A14_H4") (pintype "output"))
    )
    (net (code "259") (name "DDR_A15$45") (class "Default")
      (node (ref "U$101") (pin "M7") (pinfunction "A15_M7") (pintype "input"))
      (node (ref "U$72") (pin "D3") (pinfunction "DDR_A15_D3") (pintype "output"))
    )
    (net (code "260") (name "DDR_BA0$45") (class "Default")
      (node (ref "U$101") (pin "M2") (pinfunction "BA0_M2") (pintype "input"))
      (node (ref "U$72") (pin "C4") (pinfunction "DDR_BA0_C4") (pintype "output"))
    )
    (net (code "261") (name "DDR_BA1$45") (class "Default")
      (node (ref "U$101") (pin "N8") (pinfunction "BA1_N8") (pintype "input"))
      (node (ref "U$72") (pin "E1") (pinfunction "DDR_BA1_E1") (pintype "output"))
    )
    (net (code "262") (name "DDR_BA2$45") (class "Default")
      (node (ref "U$101") (pin "M3") (pinfunction "BA2_M3") (pintype "input"))
      (node (ref "U$72") (pin "B3") (pinfunction "DDR_BA2_B3") (pintype "output"))
    )
    (net (code "263") (name "DDR_CASN$45") (class "Default")
      (node (ref "U$101") (pin "K3") (pinfunction "~{CAS}_K3") (pintype "input"))
      (node (ref "U$72") (pin "F1") (pinfunction "DDR_CASN_F1") (pintype "output"))
    )
    (net (code "264") (name "DDR_CKE$45") (class "Default")
      (node (ref "R135") (pin "2") (pinfunction "2_2") (pintype "passive"))
      (node (ref "U$101") (pin "K9") (pinfunction "CKE_K9") (pintype "input"))
      (node (ref "U$72") (pin "G3") (pinfunction "DDR_CKE_G3") (pintype "output"))
    )
    (net (code "265") (name "DDR_CK_N$45") (class "Default")
      (node (ref "U$101") (pin "K7") (pinfunction "~{CK}_K7") (pintype "input"))
      (node (ref "U$72") (pin "D1") (pinfunction "DDR_CKN_D1") (pintype "output"))
    )
    (net (code "266") (name "DDR_CK_P$45") (class "Default")
      (node (ref "U$101") (pin "J7") (pinfunction "CK_J7") (pintype "input"))
      (node (ref "U$72") (pin "D2") (pinfunction "DDR_CK_D2") (pintype "output"))
    )
    (net (code "267") (name "DDR_CSN0$45") (class "Default")
      (node (ref "U$101") (pin "L2") (pinfunction "~{CS}_L2") (pintype "input"))
      (node (ref "U$72") (pin "H2") (pinfunction "DDR_CSN0_H2") (pintype "output"))
    )
    (net (code "268") (name "DDR_D0$45") (class "Default")
      (node (ref "U$101") (pin "E3") (pinfunction "DQ0_E3") (pintype "bidirectional"))
      (node (ref "U$72") (pin "M3") (pinfunction "DDR_D0_M3") (pintype "bidirectional"))
    )
    (net (code "269") (name "DDR_D1$45") (class "Default")
      (node (ref "U$101") (pin "F7") (pinfunction "DQ1_F7") (pintype "bidirectional"))
      (node (ref "U$72") (pin "M4") (pinfunction "DDR_D1_M4") (pintype "bidirectional"))
    )
    (net (code "270") (name "DDR_D2$45") (class "Default")
      (node (ref "U$101") (pin "F2") (pinfunction "DQ2_F2") (pintype "bidirectional"))
      (node (ref "U$72") (pin "N1") (pinfunction "DDR_D2_N1") (pintype "bidirectional"))
    )
    (net (code "271") (name "DDR_D3$45") (class "Default")
      (node (ref "U$101") (pin "F8") (pinfunction "DQ3_F8") (pintype "bidirectional"))
      (node (ref "U$72") (pin "N2") (pinfunction "DDR_D3_N2") (pintype "bidirectional"))
    )
    (net (code "272") (name "DDR_D4$45") (class "Default")
      (node (ref "U$101") (pin "H3") (pinfunction "DQ4_H3") (pintype "bidirectional"))
      (node (ref "U$72") (pin "N3") (pinfunction "DDR_D4_N3") (pintype "bidirectional"))
    )
    (net (code "273") (name "DDR_D5$45") (class "Default")
      (node (ref "U$101") (pin "H8") (pinfunction "DQ5_H8") (pintype "bidirectional"))
      (node (ref "U$72") (pin "N4") (pinfunction "DDR_D5_N4") (pintype "bidirectional"))
    )
    (net (code "274") (name "DDR_D6$45") (class "Default")
      (node (ref "U$101") (pin "G2") (pinfunction "DQ6_G2") (pintype "bidirectional"))
      (node (ref "U$72") (pin "P3") (pinfunction "DDR_D6_P3") (pintype "bidirectional"))
    )
    (net (code "275") (name "DDR_D7$45") (class "Default")
      (node (ref "U$101") (pin "H7") (pinfunction "DQ7_H7") (pintype "bidirectional"))
      (node (ref "U$72") (pin "P4") (pinfunction "DDR_D7_P4") (pintype "bidirectional"))
    )
    (net (code "276") (name "DDR_D8$45") (class "Default")
      (node (ref "U$101") (pin "D7") (pinfunction "DQ8_D7") (pintype "bidirectional"))
      (node (ref "U$72") (pin "J1") (pinfunction "DDR_D8_J1") (pintype "bidirectional"))
    )
    (net (code "277") (name "DDR_D9$45") (class "Default")
      (node (ref "U$101") (pin "C3") (pinfunction "DQ9_C3") (pintype "bidirectional"))
      (node (ref "U$72") (pin "K1") (pinfunction "DDR_D9_K1") (pintype "bidirectional"))
    )
    (net (code "278") (name "DDR_D10$45") (class "Default")
      (node (ref "U$101") (pin "C8") (pinfunction "DQ10_C8") (pintype "bidirectional"))
      (node (ref "U$72") (pin "K2") (pinfunction "DDR_D10_K2") (pintype "bidirectional"))
    )
    (net (code "279") (name "DDR_D11$45") (class "Default")
      (node (ref "U$101") (pin "C2") (pinfunction "DQ11_C2") (pintype "bidirectional"))
      (node (ref "U$72") (pin "K3") (pinfunction "DDR_D11_K3") (pintype "bidirectional"))
    )
    (net (code "280") (name "DDR_D12$45") (class "Default")
      (node (ref "U$101") (pin "A7") (pinfunction "DQ12_A7") (pintype "bidirectional"))
      (node (ref "U$72") (pin "K4") (pinfunction "DDR_D12_K4") (pintype "bidirectional"))
    )
    (net (code "281") (name "DDR_D13$45") (class "Default")
      (node (ref "U$101") (pin "A2") (pinfunction "DQ13_A2") (pintype "bidirectional"))
      (node (ref "U$72") (pin "L3") (pinfunction "DDR_D13_L3") (pintype "bidirectional"))
    )
    (net (code "282") (name "DDR_D14$45") (class "Default")
      (node (ref "U$101") (pin "B8") (pinfunction "DQ14_B8") (pintype "bidirectional"))
      (node (ref "U$72") (pin "L4") (pinfunction "DDR_D14_L4") (pintype "bidirectional"))
    )
    (net (code "283") (name "DDR_D15$45") (class "Default")
      (node (ref "U$101") (pin "A3") (pinfunction "DQ15_A3") (pintype "bidirectional"))
      (node (ref "U$72") (pin "M1") (pinfunction "DDR_D15_M1") (pintype "bidirectional"))
    )
    (net (code "284") (name "DDR_DQM0$45") (class "Default")
      (node (ref "U$101") (pin "E7") (pinfunction "LDM_E7") (pintype "input"))
      (node (ref "U$72") (pin "M2") (pinfunction "DDR_DQM0_M2") (pintype "output"))
    )
    (net (code "285") (name "DDR_DQM1$45") (class "Default")
      (node (ref "U$101") (pin "D3") (pinfunction "UDM_D3") (pintype "bidirectional"))
      (node (ref "U$72") (pin "J2") (pinfunction "DDR_DQM1_J2") (pintype "output"))
    )
    (net (code "286") (name "DDR_DQS0_N$45") (class "Default")
      (node (ref "U$101") (pin "G3") (pinfunction "~{LDQS}_G3") (pintype "bidirectional"))
      (node (ref "U$72") (pin "P2") (pinfunction "DDR_DQSN0_P2") (pintype "bidirectional"))
    )
    (net (code "287") (name "DDR_DQS0_P$45") (class "Default")
      (node (ref "U$101") (pin "F3") (pinfunction "LDQS_F3") (pintype "input"))
      (node (ref "U$72") (pin "P1") (pinfunction "DDR_DQS0_P1") (pintype "bidirectional"))
    )
    (net (code "288") (name "DDR_DQS1_N$45") (class "Default")
      (node (ref "U$101") (pin "B7") (pinfunction "~{UDQS}_B7") (pintype "bidirectional"))
      (node (ref "U$72") (pin "L2") (pinfunction "DDR_DQSN1_L2") (pintype "bidirectional"))
    )
    (net (code "289") (name "DDR_DQS1_P$45") (class "Default")
      (node (ref "U$101") (pin "C7") (pinfunction "UDQS_C7") (pintype "bidirectional"))
      (node (ref "U$72") (pin "L1") (pinfunction "DDR_DQS1_L1") (pintype "bidirectional"))
    )
    (net (code "290") (name "DDR_ODT$45") (class "Default")
      (node (ref "U$101") (pin "K1") (pinfunction "ODT_K1") (pintype "input"))
      (node (ref "U$72") (pin "G1") (pinfunction "DDR_ODT_G1") (pintype "output"))
    )
    (net (code "291") (name "DDR_RASN$45") (class "Default")
      (node (ref "U$101") (pin "J3") (pinfunction "~{RAS}_J3") (pintype "input"))
      (node (ref "U$72") (pin "G4") (pinfunction "DDR_RASN_G4") (pintype "output"))
    )
    (net (code "292") (name "DDR_VREF$45") (class "Default")
      (node (ref "C256") (pin "1") (pinfunction "1_1") (pintype "passive"))
      (node (ref "C257") (pin "1") (pinfunction "1_1") (pintype "passive"))
      (node (ref "R131") (pin "2") (pinfunction "2_2") (pintype "passive"))
      (node (ref "R132") (pin "1") (pinfunction "1_1") (pintype "passive"))
      (node (ref "U$101") (pin "H1") (pinfunction "VREF_DQ_H1") (pintype "power_in"))
      (node (ref "U$101") (pin "M8") (pinfunction "VREF_CA_M8") (pintype "power_in"))
      (node (ref "U$72") (pin "J4") (pinfunction "DDR_VREF_J4") (pintype "bidirectional"))
    )
    (net (code "293") (name "DDR_VTP$45") (class "Default")
      (node (ref "R129") (pin "2") (pinfunction "2_2") (pintype "passive"))
      (node (ref "U$72") (pin "J3") (pinfunction "DDR_VTP_J3") (pintype "input"))
    )
    (net (code "294") (name "DDR_WEN$45") (class "Default")
      (node (ref "U$101") (pin "L3") (pinfunction "~{WE}_L3") (pintype "input"))
      (node (ref "U$72") (pin "B2") (pinfunction "DDR_WEN_B2") (pintype "output"))
    )
    (net (code "295") (name "DE$44") (class "Default")
      (node (ref "IC4") (pin "2") (pinfunction "DE_2") (pintype "bidirectional"))
      (node (ref "R115") (pin "2") (pinfunction "2_2") (pintype "passive"))
    )
    (net (code "296") (name "DKEN$44") (class "Default")
      (node (ref "IC4") (pin "35") (pinfunction "DKEN_35") (pintype "bidirectional"))
      (node (ref "R105") (pin "1") (pinfunction "1_1") (pintype "passive"))
      (node (ref "R114") (pin "1") (pinfunction "1_1") (pintype "passive"))
    )
    (net (code "297") (name "DM$30") (class "Default")
      (node (ref "D13") (pin "P2") (pinfunction "P2_P2") (pintype "passive"))
      (node (ref "J10") (pin "P2") (pinfunction "D-_P2") (pintype "bidirectional"))
      (node (ref "L5") (pin "1") (pinfunction "1_1") (pintype "passive"))
    )
    (net (code "298") (name "DM$38") (class "Default")
      (node (ref "D17") (pin "P2") (pinfunction "P2_P2") (pintype "passive"))
      (node (ref "J14") (pin "P2") (pinfunction "D-_P2") (pintype "bidirectional"))
      (node (ref "L6") (pin "1") (pinfunction "1_1") (pintype "passive"))
    )
    (net (code "299") (name "DP$30") (class "Default")
      (node (ref "D14") (pin "P2") (pinfunction "P2_P2") (pintype "passive"))
      (node (ref "J10") (pin "P3") (pinfunction "D+_P3") (pintype "bidirectional"))
      (node (ref "L5") (pin "4") (pinfunction "4_4") (pintype "passive"))
    )
    (net (code "300") (name "DP$38") (class "Default")
      (node (ref "D18") (pin "P2") (pinfunction "P2_P2") (pintype "passive"))
      (node (ref "J14") (pin "P3") (pinfunction "D+_P3") (pintype "bidirectional"))
      (node (ref "L6") (pin "4") (pinfunction "4_4") (pintype "passive"))
    )
    (net (code "301") (name "DVI_BSEL$44") (class "Default")
      (node (ref "IC4") (pin "15") (pinfunction "BSEL/SCL_15") (pintype "bidirectional"))
      (node (ref "R98") (pin "2") (pinfunction "2_2") (pintype "passive"))
    )
    (net (code "302") (name "DVI_DSEL$44") (class "Default")
      (node (ref "IC4") (pin "14") (pinfunction "DSEL/SDA_14") (pintype "bidirectional"))
      (node (ref "R101") (pin "2") (pinfunction "2_2") (pintype "passive"))
    )
    (net (code "303") (name "DVI_HTPLG$44") (class "Default")
      (node (ref "IC4") (pin "9") (pinfunction "HTPLG_9") (pintype "bidirectional"))
      (node (ref "R96") (pin "2") (pinfunction "2_2") (pintype "passive"))
    )
    (net (code "304") (name "DVI_VREF$44") (class "Default")
      (node (ref "IC4") (pin "3") (pinfunction "VREF_3") (pintype "bidirectional"))
      (node (ref "R100") (pin "1") (pinfunction "1_1") (pintype "passive"))
      (node (ref "R99") (pin "1") (pinfunction "1_1") (pintype "passive"))
    )
    (net (code "305") (name "DVI_~{RESET}$44") (class "Default")
      (node (ref "IC4") (pin "13") (pinfunction "ISEL/~{RESET}_13") (pintype "bidirectional"))
      (node (ref "R97") (pin "2") (pinfunction "2_2") (pintype "passive"))
    )
    (net (code "306") (name "EE_A0$45") (class "Default")
      (node (ref "R340") (pin "2") (pinfunction "2_2") (pintype "passive"))
      (node (ref "U34") (pin "1") (pinfunction "A0_1") (pintype "input"))
    )
    (net (code "307") (name "EE_A1$45") (class "Default")
      (node (ref "R342") (pin "2") (pinfunction "2_2") (pintype "passive"))
      (node (ref "U34") (pin "2") (pinfunction "A1_2") (pintype "input"))
    )
    (net (code "308") (name "EE_A2$45") (class "Default")
      (node (ref "R344") (pin "2") (pinfunction "2_2") (pintype "passive"))
      (node (ref "U34") (pin "3") (pinfunction "A2_3") (pintype "input"))
    )
    (net (code "309") (name "EXT_32K$33") (class "Default")
      (node (ref "Q5") (pin "3") (pinfunction "FO_3") (pintype "output"))
      (node (ref "R144") (pin "1") (pinfunction "1_1") (pintype "passive"))
      (node (ref "U28") (pin "36") (pinfunction "EXT_32K_36") (pintype "bidirectional"))
    )
    (net (code "310") (name "FB_3.3$18") (class "Default")
      (node (ref "C60") (pin "2") (pinfunction "2_2") (pintype "passive"))
      (node (ref "IC2") (pin "10") (pinfunction "FB_10") (pintype "output"))
      (node (ref "R39") (pin "1") (pinfunction "1_1") (pintype "passive"))
      (node (ref "R40") (pin "2") (pinfunction "2_2") (pintype "passive"))
    )
    (net (code "311") (name "GND") (class "Default")
      (node (ref "C1") (pin "2") (pinfunction "2_2") (pintype "passive"))
      (node (ref "C10") (pin "2") (pinfunction "2_2") (pintype "passive"))
      (node (ref "C100") (pin "2") (pinfunction "2_2") (pintype "passive"))
      (node (ref "C101") (pin "2") (pinfunction "2_2") (pintype "passive"))
      (node (ref "C102") (pin "2") (pinfunction "2_2") (pintype "passive"))
      (node (ref "C103") (pin "2") (pinfunction "2_2") (pintype "passive"))
      (node (ref "C104") (pin "2") (pinfunction "2_2") (pintype "passive"))
      (node (ref "C105") (pin "2") (pinfunction "2_2") (pintype "passive"))
      (node (ref "C106") (pin "2") (pinfunction "2_2") (pintype "passive"))
      (node (ref "C107") (pin "-") (pinfunction "2_-") (pintype "passive"))
      (node (ref "C108") (pin "2") (pinfunction "2_2") (pintype "passive"))
      (node (ref "C109") (pin "2") (pinfunction "2_2") (pintype "passive"))
      (node (ref "C11") (pin "-") (pinfunction "2_-") (pintype "passive"))
      (node (ref "C112") (pin "2") (pinfunction "2_2") (pintype "passive"))
      (node (ref "C113") (pin "2") (pinfunction "2_2") (pintype "passive"))
      (node (ref "C114") (pin "2") (pinfunction "2_2") (pintype "passive"))
      (node (ref "C115") (pin "2") (pinfunction "2_2") (pintype "passive"))
      (node (ref "C116") (pin "2") (pinfunction "2_2") (pintype "passive"))
      (node (ref "C117") (pin "2") (pinfunction "2_2") (pintype "passive"))
      (node (ref "C118") (pin "2") (pinfunction "2_2") (pintype "passive"))
      (node (ref "C119") (pin "2") (pinfunction "2_2") (pintype "passive"))
      (node (ref "C12") (pin "2") (pinfunction "2_2") (pintype "passive"))
      (node (ref "C120") (pin "2") (pinfunction "2_2") (pintype "passive"))
      (node (ref "C121") (pin "2") (pinfunction "2_2") (pintype "passive"))
      (node (ref "C122") (pin "2") (pinfunction "2_2") (pintype "passive"))
      (node (ref "C123") (pin "2") (pinfunction "2_2") (pintype "passive"))
      (node (ref "C124") (pin "2") (pinfunction "2_2") (pintype "passive"))
      (node (ref "C125") (pin "2") (pinfunction "2_2") (pintype "passive"))
      (node (ref "C126") (pin "2") (pinfunction "2_2") (pintype "passive"))
      (node (ref "C127") (pin "2") (pinfunction "2_2") (pintype "passive"))
      (node (ref "C128") (pin "2") (pinfunction "2_2") (pintype "passive"))
      (node (ref "C129") (pin "2") (pinfunction "2_2") (pintype "passive"))
      (node (ref "C13") (pin "2") (pinfunction "2_2") (pintype "passive"))
      (node (ref "C130") (pin "2") (pinfunction "2_2") (pintype "passive"))
      (node (ref "C131") (pin "2") (pinfunction "2_2") (pintype "passive"))
      (node (ref "C132") (pin "2") (pinfunction "2_2") (pintype "passive"))
      (node (ref "C135") (pin "2") (pinfunction "2_2") (pintype "passive"))
      (node (ref "C136") (pin "2") (pinfunction "2_2") (pintype "passive"))
      (node (ref "C137") (pin "2") (pinfunction "2_2") (pintype "passive"))
      (node (ref "C138") (pin "2") (pinfunction "2_2") (pintype "passive"))
      (node (ref "C139") (pin "2") (pinfunction "2_2") (pintype "passive"))
      (node (ref "C140") (pin "2") (pinfunction "2_2") (pintype "passive"))
      (node (ref "C141") (pin "2") (pinfunction "2_2") (pintype "passive"))
      (node (ref "C142") (pin "2") (pinfunction "2_2") (pintype "passive"))
      (node (ref "C143") (pin "2") (pinfunction "2_2") (pintype "passive"))
      (node (ref "C144") (pin "2") (pinfunction "2_2") (pintype "passive"))
      (node (ref "C145") (pin "2") (pinfunction "2_2") (pintype "passive"))
      (node (ref "C146") (pin "2") (pinfunction "2_2") (pintype "passive"))
      (node (ref "C147") (pin "2") (pinfunction "2_2") (pintype "passive"))
      (node (ref "C148") (pin "2") (pinfunction "2_2") (pintype "passive"))
      (node (ref "C149") (pin "2") (pinfunction "2_2") (pintype "passive"))
      (node (ref "C150") (pin "2") (pinfunction "2_2") (pintype "passive"))
      (node (ref "C151") (pin "2") (pinfunction "2_2") (pintype "passive"))
      (node (ref "C152") (pin "2") (pinfunction "2_2") (pintype "passive"))
      (node (ref "C153") (pin "2") (pinfunction "2_2") (pintype "passive"))
      (node (ref "C154") (pin "2") (pinfunction "2_2") (pintype "passive"))
      (node (ref "C155") (pin "2") (pinfunction "2_2") (pintype "passive"))
      (node (ref "C156") (pin "2") (pinfunction "2_2") (pintype "passive"))
      (node (ref "C157") (pin "2") (pinfunction "2_2") (pintype "passive"))
      (node (ref "C158") (pin "2") (pinfunction "2_2") (pintype "passive"))
      (node (ref "C159") (pin "2") (pinfunction "2_2") (pintype "passive"))
      (node (ref "C16") (pin "2") (pinfunction "2_2") (pintype "passive"))
      (node (ref "C160") (pin "2") (pinfunction "2_2") (pintype "passive"))
      (node (ref "C161") (pin "2") (pinfunction "2_2") (pintype "passive"))
      (node (ref "C162") (pin "2") (pinfunction "2_2") (pintype "passive"))
      (node (ref "C163") (pin "2") (pinfunction "2_2") (pintype "passive"))
      (node (ref "C164") (pin "2") (pinfunction "2_2") (pintype "passive"))
      (node (ref "C165") (pin "2") (pinfunction "2_2") (pintype "passive"))
      (node (ref "C166") (pin "2") (pinfunction "2_2") (pintype "passive"))
      (node (ref "C167") (pin "2") (pinfunction "2_2") (pintype "passive"))
      (node (ref "C17") (pin "2") (pinfunction "2_2") (pintype "passive"))
      (node (ref "C172") (pin "2") (pinfunction "2_2") (pintype "passive"))
      (node (ref "C173") (pin "2") (pinfunction "2_2") (pintype "passive"))
      (node (ref "C174") (pin "2") (pinfunction "2_2") (pintype "passive"))
      (node (ref "C175") (pin "2") (pinfunction "2_2") (pintype "passive"))
      (node (ref "C176") (pin "2") (pinfunction "2_2") (pintype "passive"))
      (node (ref "C177") (pin "2") (pinfunction "2_2") (pintype "passive"))
      (node (ref "C178") (pin "2") (pinfunction "2_2") (pintype "passive"))
      (node (ref "C179") (pin "2") (pinfunction "2_2") (pintype "passive"))
      (node (ref "C18") (pin "2") (pinfunction "2_2") (pintype "passive"))
      (node (ref "C180") (pin "2") (pinfunction "2_2") (pintype "passive"))
      (node (ref "C181") (pin "2") (pinfunction "2_2") (pintype "passive"))
      (node (ref "C182") (pin "2") (pinfunction "2_2") (pintype "passive"))
      (node (ref "C183") (pin "2") (pinfunction "2_2") (pintype "passive"))
      (node (ref "C184") (pin "2") (pinfunction "2_2") (pintype "passive"))
      (node (ref "C185") (pin "2") (pinfunction "2_2") (pintype "passive"))
      (node (ref "C186") (pin "2") (pinfunction "2_2") (pintype "passive"))
      (node (ref "C187") (pin "2") (pinfunction "2_2") (pintype "passive"))
      (node (ref "C188") (pin "2") (pinfunction "2_2") (pintype "passive"))
      (node (ref "C189") (pin "2") (pinfunction "2_2") (pintype "passive"))
      (node (ref "C19") (pin "2") (pinfunction "2_2") (pintype "passive"))
      (node (ref "C190") (pin "2") (pinfunction "2_2") (pintype "passive"))
      (node (ref "C191") (pin "2") (pinfunction "2_2") (pintype "passive"))
      (node (ref "C192") (pin "2") (pinfunction "2_2") (pintype "passive"))
      (node (ref "C193") (pin "2") (pinfunction "2_2") (pintype "passive"))
      (node (ref "C194") (pin "2") (pinfunction "2_2") (pintype "passive"))
      (node (ref "C195") (pin "2") (pinfunction "2_2") (pintype "passive"))
      (node (ref "C196") (pin "2") (pinfunction "2_2") (pintype "passive"))
      (node (ref "C197") (pin "2") (pinfunction "2_2") (pintype "passive"))
      (node (ref "C198") (pin "2") (pinfunction "2_2") (pintype "passive"))
      (node (ref "C199") (pin "2") (pinfunction "2_2") (pintype "passive"))
      (node (ref "C2") (pin "2") (pinfunction "2_2") (pintype "passive"))
      (node (ref "C20") (pin "2") (pinfunction "2_2") (pintype "passive"))
      (node (ref "C200") (pin "2") (pinfunction "2_2") (pintype "passive"))
      (node (ref "C201") (pin "2") (pinfunction "2_2") (pintype "passive"))
      (node (ref "C202") (pin "2") (pinfunction "2_2") (pintype "passive"))
      (node (ref "C203") (pin "2") (pinfunction "2_2") (pintype "passive"))
      (node (ref "C204") (pin "2") (pinfunction "2_2") (pintype "passive"))
      (node (ref "C205") (pin "2") (pinfunction "2_2") (pintype "passive"))
      (node (ref "C206") (pin "2") (pinfunction "2_2") (pintype "passive"))
      (node (ref "C207") (pin "2") (pinfunction "2_2") (pintype "passive"))
      (node (ref "C208") (pin "2") (pinfunction "2_2") (pintype "passive"))
      (node (ref "C209") (pin "2") (pinfunction "2_2") (pintype "passive"))
      (node (ref "C21") (pin "2") (pinfunction "2_2") (pintype "passive"))
      (node (ref "C210") (pin "2") (pinfunction "2_2") (pintype "passive"))
      (node (ref "C211") (pin "2") (pinfunction "2_2") (pintype "passive"))
      (node (ref "C212") (pin "2") (pinfunction "2_2") (pintype "passive"))
      (node (ref "C213") (pin "2") (pinfunction "2_2") (pintype "passive"))
      (node (ref "C214") (pin "2") (pinfunction "2_2") (pintype "passive"))
      (node (ref "C215") (pin "2") (pinfunction "2_2") (pintype "passive"))
      (node (ref "C216") (pin "2") (pinfunction "2_2") (pintype "passive"))
      (node (ref "C217") (pin "2") (pinfunction "2_2") (pintype "passive"))
      (node (ref "C218") (pin "2") (pinfunction "2_2") (pintype "passive"))
      (node (ref "C219") (pin "2") (pinfunction "2_2") (pintype "passive"))
      (node (ref "C22") (pin "2") (pinfunction "2_2") (pintype "passive"))
      (node (ref "C220") (pin "2") (pinfunction "2_2") (pintype "passive"))
      (node (ref "C221") (pin "2") (pinfunction "2_2") (pintype "passive"))
      (node (ref "C222") (pin "2") (pinfunction "2_2") (pintype "passive"))
      (node (ref "C223") (pin "2") (pinfunction "2_2") (pintype "passive"))
      (node (ref "C224") (pin "2") (pinfunction "2_2") (pintype "passive"))
      (node (ref "C225") (pin "2") (pinfunction "2_2") (pintype "passive"))
      (node (ref "C226") (pin "2") (pinfunction "2_2") (pintype "passive"))
      (node (ref "C227") (pin "2") (pinfunction "2_2") (pintype "passive"))
      (node (ref "C228") (pin "2") (pinfunction "2_2") (pintype "passive"))
      (node (ref "C229") (pin "2") (pinfunction "2_2") (pintype "passive"))
      (node (ref "C23") (pin "2") (pinfunction "2_2") (pintype "passive"))
      (node (ref "C230") (pin "2") (pinfunction "2_2") (pintype "passive"))
      (node (ref "C231") (pin "2") (pinfunction "2_2") (pintype "passive"))
      (node (ref "C232") (pin "2") (pinfunction "2_2") (pintype "passive"))
      (node (ref "C233") (pin "2") (pinfunction "2_2") (pintype "passive"))
      (node (ref "C234") (pin "2") (pinfunction "2_2") (pintype "passive"))
      (node (ref "C235") (pin "2") (pinfunction "2_2") (pintype "passive"))
      (node (ref "C236") (pin "2") (pinfunction "2_2") (pintype "passive"))
      (node (ref "C237") (pin "2") (pinfunction "2_2") (pintype "passive"))
      (node (ref "C238") (pin "2") (pinfunction "2_2") (pintype "passive"))
      (node (ref "C239") (pin "2") (pinfunction "2_2") (pintype "passive"))
      (node (ref "C240") (pin "2") (pinfunction "2_2") (pintype "passive"))
      (node (ref "C241") (pin "2") (pinfunction "2_2") (pintype "passive"))
      (node (ref "C242") (pin "2") (pinfunction "2_2") (pintype "passive"))
      (node (ref "C243") (pin "2") (pinfunction "2_2") (pintype "passive"))
      (node (ref "C244") (pin "2") (pinfunction "2_2") (pintype "passive"))
      (node (ref "C245") (pin "2") (pinfunction "2_2") (pintype "passive"))
      (node (ref "C246") (pin "2") (pinfunction "2_2") (pintype "passive"))
      (node (ref "C247") (pin "2") (pinfunction "2_2") (pintype "passive"))
      (node (ref "C248") (pin "2") (pinfunction "2_2") (pintype "passive"))
      (node (ref "C249") (pin "2") (pinfunction "2_2") (pintype "passive"))
      (node (ref "C250") (pin "2") (pinfunction "2_2") (pintype "passive"))
      (node (ref "C251") (pin "2") (pinfunction "2_2") (pintype "passive"))
      (node (ref "C252") (pin "2") (pinfunction "2_2") (pintype "passive"))
      (node (ref "C253") (pin "2") (pinfunction "2_2") (pintype "passive"))
      (node (ref "C254") (pin "2") (pinfunction "2_2") (pintype "passive"))
      (node (ref "C255") (pin "2") (pinfunction "2_2") (pintype "passive"))
      (node (ref "C256") (pin "2") (pinfunction "2_2") (pintype "passive"))
      (node (ref "C257") (pin "2") (pinfunction "2_2") (pintype "passive"))
      (node (ref "C258") (pin "2") (pinfunction "2_2") (pintype "passive"))
      (node (ref "C259") (pin "2") (pinfunction "2_2") (pintype "passive"))
      (node (ref "C26") (pin "2") (pinfunction "2_2") (pintype "passive"))
      (node (ref "C260") (pin "2") (pinfunction "2_2") (pintype "passive"))
      (node (ref "C261") (pin "2") (pinfunction "2_2") (pintype "passive"))
      (node (ref "C262") (pin "2") (pinfunction "2_2") (pintype "passive"))
      (node (ref "C263") (pin "2") (pinfunction "2_2") (pintype "passive"))
      (node (ref "C265") (pin "2") (pinfunction "2_2") (pintype "passive"))
      (node (ref "C266") (pin "-") (pinfunction "2_-") (pintype "passive"))
      (node (ref "C267") (pin "2") (pinfunction "2_2") (pintype "passive"))
      (node (ref "C268") (pin "2") (pinfunction "2_2") (pintype "passive"))
      (node (ref "C269") (pin "2") (pinfunction "2_2") (pintype "passive"))
      (node (ref "C27") (pin "2") (pinfunction "2_2") (pintype "passive"))
      (node (ref "C271") (pin "2") (pinfunction "2_2") (pintype "passive"))
      (node (ref "C272") (pin "2") (pinfunction "2_2") (pintype "passive"))
      (node (ref "C273") (pin "2") (pinfunction "2_2") (pintype "passive"))
      (node (ref "C274") (pin "2") (pinfunction "2_2") (pintype "passive"))
      (node (ref "C275") (pin "2") (pinfunction "2_2") (pintype "passive"))
      (node (ref "C28") (pin "2") (pinfunction "2_2") (pintype "passive"))
      (node (ref "C29") (pin "2") (pinfunction "2_2") (pintype "passive"))
      (node (ref "C3") (pin "2") (pinfunction "2_2") (pintype "passive"))
      (node (ref "C30") (pin "2") (pinfunction "2_2") (pintype "passive"))
      (node (ref "C31") (pin "2") (pinfunction "2_2") (pintype "passive"))
      (node (ref "C32") (pin "2") (pinfunction "2_2") (pintype "passive"))
      (node (ref "C33") (pin "2") (pinfunction "2_2") (pintype "passive"))
      (node (ref "C34") (pin "2") (pinfunction "2_2") (pintype "passive"))
      (node (ref "C35") (pin "2") (pinfunction "2_2") (pintype "passive"))
      (node (ref "C36") (pin "2") (pinfunction "2_2") (pintype "passive"))
      (node (ref "C37") (pin "2") (pinfunction "2_2") (pintype "passive"))
      (node (ref "C38") (pin "2") (pinfunction "2_2") (pintype "passive"))
      (node (ref "C39") (pin "2") (pinfunction "2_2") (pintype "passive"))
      (node (ref "C4") (pin "2") (pinfunction "2_2") (pintype "passive"))
      (node (ref "C40") (pin "2") (pinfunction "2_2") (pintype "passive"))
      (node (ref "C41") (pin "2") (pinfunction "2_2") (pintype "passive"))
      (node (ref "C42") (pin "2") (pinfunction "2_2") (pintype "passive"))
      (node (ref "C5") (pin "2") (pinfunction "2_2") (pintype "passive"))
      (node (ref "C51") (pin "2") (pinfunction "2_2") (pintype "passive"))
      (node (ref "C52") (pin "2") (pinfunction "2_2") (pintype "passive"))
      (node (ref "C53") (pin "2") (pinfunction "2_2") (pintype "passive"))
      (node (ref "C55") (pin "2") (pinfunction "2_2") (pintype "passive"))
      (node (ref "C56") (pin "2") (pinfunction "2_2") (pintype "passive"))
      (node (ref "C57") (pin "2") (pinfunction "2_2") (pintype "passive"))
      (node (ref "C58") (pin "2") (pinfunction "2_2") (pintype "passive"))
      (node (ref "C59") (pin "2") (pinfunction "2_2") (pintype "passive"))
      (node (ref "C6") (pin "2") (pinfunction "2_2") (pintype "passive"))
      (node (ref "C61") (pin "2") (pinfunction "2_2") (pintype "passive"))
      (node (ref "C62") (pin "2") (pinfunction "2_2") (pintype "passive"))
      (node (ref "C63") (pin "2") (pinfunction "2_2") (pintype "passive"))
      (node (ref "C64") (pin "2") (pinfunction "2_2") (pintype "passive"))
      (node (ref "C65") (pin "2") (pinfunction "2_2") (pintype "passive"))
      (node (ref "C69") (pin "2") (pinfunction "2_2") (pintype "passive"))
      (node (ref "C7") (pin "2") (pinfunction "2_2") (pintype "passive"))
      (node (ref "C70") (pin "2") (pinfunction "2_2") (pintype "passive"))
      (node (ref "C71") (pin "2") (pinfunction "2_2") (pintype "passive"))
      (node (ref "C72") (pin "2") (pinfunction "2_2") (pintype "passive"))
      (node (ref "C73") (pin "2") (pinfunction "2_2") (pintype "passive"))
      (node (ref "C74") (pin "2") (pinfunction "2_2") (pintype "passive"))
      (node (ref "C75") (pin "2") (pinfunction "2_2") (pintype "passive"))
      (node (ref "C76") (pin "2") (pinfunction "2_2") (pintype "passive"))
      (node (ref "C77") (pin "2") (pinfunction "2_2") (pintype "passive"))
      (node (ref "C78") (pin "2") (pinfunction "2_2") (pintype "passive"))
      (node (ref "C79") (pin "2") (pinfunction "2_2") (pintype "passive"))
      (node (ref "C8") (pin "2") (pinfunction "2_2") (pintype "passive"))
      (node (ref "C80") (pin "2") (pinfunction "2_2") (pintype "passive"))
      (node (ref "C81") (pin "2") (pinfunction "2_2") (pintype "passive"))
      (node (ref "C82") (pin "2") (pinfunction "2_2") (pintype "passive"))
      (node (ref "C83") (pin "2") (pinfunction "2_2") (pintype "passive"))
      (node (ref "C84") (pin "2") (pinfunction "2_2") (pintype "passive"))
      (node (ref "C86") (pin "2") (pinfunction "2_2") (pintype "passive"))
      (node (ref "C87") (pin "2") (pinfunction "2_2") (pintype "passive"))
      (node (ref "C89") (pin "2") (pinfunction "2_2") (pintype "passive"))
      (node (ref "C9") (pin "2") (pinfunction "2_2") (pintype "passive"))
      (node (ref "C90") (pin "-") (pinfunction "2_-") (pintype "passive"))
      (node (ref "C91") (pin "2") (pinfunction "2_2") (pintype "passive"))
      (node (ref "C92") (pin "2") (pinfunction "2_2") (pintype "passive"))
      (node (ref "C93") (pin "2") (pinfunction "2_2") (pintype "passive"))
      (node (ref "C94") (pin "2") (pinfunction "2_2") (pintype "passive"))
      (node (ref "C95") (pin "2") (pinfunction "2_2") (pintype "passive"))
      (node (ref "C96") (pin "2") (pinfunction "2_2") (pintype "passive"))
      (node (ref "C97") (pin "2") (pinfunction "2_2") (pintype "passive"))
      (node (ref "C98") (pin "2") (pinfunction "2_2") (pintype "passive"))
      (node (ref "C99") (pin "2") (pinfunction "2_2") (pintype "passive"))
      (node (ref "CONN1") (pin "2") (pinfunction "2_2") (pintype "power_in"))
      (node (ref "CONN1") (pin "3") (pinfunction "3_3") (pintype "power_in"))
      (node (ref "D1") (pin "C") (pinfunction "C_C") (pintype "passive"))
      (node (ref "D10") (pin "A") (pinfunction "A_A") (pintype "passive"))
      (node (ref "D15") (pin "A") (pinfunction "A_A") (pintype "passive"))
      (node (ref "D16") (pin "P2") (pinfunction "P2_P2") (pintype "passive"))
      (node (ref "D20") (pin "P2") (pinfunction "P2_P2") (pintype "passive"))
      (node (ref "FB1") (pin "1") (pinfunction "1_1") (pintype "passive"))
      (node (ref "FB11") (pin "2") (pinfunction "2_2") (pintype "passive"))
      (node (ref "IC1") (pin "10") (pinfunction "VS2_10") (pintype "input"))
      (node (ref "IC1") (pin "12") (pinfunction "VS0_12") (pintype "input"))
      (node (ref "IC1") (pin "2") (pinfunction "PGND_2") (pintype "power_in"))
      (node (ref "IC1") (pin "6") (pinfunction "AGND_6") (pintype "power_in"))
      (node (ref "IC2") (pin "1") (pinfunction "PGND_1") (pintype "power_in"))
      (node (ref "IC2") (pin "11") (pinfunction "GND_11") (pintype "power_in"))
      (node (ref "IC2") (pin "12") (pinfunction "GND_12") (pintype "power_in"))
      (node (ref "IC2") (pin "16") (pinfunction "PGND_16") (pintype "power_in"))
      (node (ref "IC2") (pin "5") (pinfunction "SYNC_5") (pintype "input"))
      (node (ref "IC2") (pin "6") (pinfunction "LBO_6") (pintype "passive"))
      (node (ref "IC2") (pin "7") (pinfunction "LBI_7") (pintype "input"))
      (node (ref "IC2") (pin "9") (pinfunction "GND_9") (pintype "power_in"))
      (node (ref "IC2") (pin "P$1") (pinfunction "GND_P$1") (pintype "power_in"))
      (node (ref "IC3") (pin "10") (pinfunction "VSS_5_10") (pintype "power_in"))
      (node (ref "IC3") (pin "27") (pinfunction "VSS_4_27") (pintype "power_in"))
      (node (ref "IC3") (pin "74") (pinfunction "VSS_2_74") (pintype "power_in"))
      (node (ref "IC3") (pin "99") (pinfunction "VSS_3_99") (pintype "power_in"))
      (node (ref "IC4") (pin "16") (pinfunction "VSS_16") (pintype "power_in"))
      (node (ref "IC4") (pin "17") (pinfunction "VSS_17") (pintype "power_in"))
      (node (ref "IC4") (pin "20") (pinfunction "VSS_20") (pintype "power_in"))
      (node (ref "IC4") (pin "26") (pinfunction "VSS_26") (pintype "power_in"))
      (node (ref "IC4") (pin "32") (pinfunction "VSS_32") (pintype "power_in"))
      (node (ref "IC4") (pin "34") (pinfunction "RSVD2_34") (pintype "bidirectional"))
      (node (ref "IC4") (pin "48") (pinfunction "VSS_48") (pintype "power_in"))
      (node (ref "IC4") (pin "56") (pinfunction "IDCK-_56") (pintype "bidirectional"))
      (node (ref "IC4") (pin "64") (pinfunction "VSS_64") (pintype "power_in"))
      (node (ref "IC4") (pin "TP") (pinfunction "TP_TP") (pintype "power_in"))
      (node (ref "J1") (pin "2") (pinfunction "2_2") (pintype "bidirectional"))
      (node (ref "J10") (pin "P5") (pinfunction "GND_P5") (pintype "bidirectional"))
      (node (ref "J11") (pin "2") (pinfunction "2_2") (pintype "bidirectional"))
      (node (ref "J12") (pin "1") (pinfunction "1_1") (pintype "passive"))
      (node (ref "J12") (pin "11") (pinfunction "11_11") (pintype "passive"))
      (node (ref "J12") (pin "13") (pinfunction "13_13") (pintype "passive"))
      (node (ref "J12") (pin "15") (pinfunction "15_15") (pintype "passive"))
      (node (ref "J12") (pin "17") (pinfunction "17_17") (pintype "passive"))
      (node (ref "J12") (pin "19") (pinfunction "19_19") (pintype "passive"))
      (node (ref "J12") (pin "3") (pinfunction "3_3") (pintype "passive"))
      (node (ref "J12") (pin "5") (pinfunction "5_5") (pintype "passive"))
      (node (ref "J12") (pin "7") (pinfunction "7_7") (pintype "passive"))
      (node (ref "J12") (pin "9") (pinfunction "9_9") (pintype "passive"))
      (node (ref "J14") (pin "P5") (pinfunction "GND_P5") (pintype "bidirectional"))
      (node (ref "J15") (pin "10") (pinfunction "8_10") (pintype "passive"))
      (node (ref "J15") (pin "13") (pinfunction "11_13") (pintype "passive"))
      (node (ref "J15") (pin "16") (pinfunction "17_16") (pintype "passive"))
      (node (ref "J15") (pin "4") (pinfunction "2_4") (pintype "passive"))
      (node (ref "J15") (pin "7") (pinfunction "5_7") (pintype "passive"))
      (node (ref "J2") (pin "A1") (pinfunction "A1_A1") (pintype "bidirectional"))
      (node (ref "J2") (pin "B1") (pinfunction "B1_B1") (pintype "bidirectional"))
      (node (ref "J3") (pin "-") (pinfunction "-_-") (pintype "passive"))
      (node (ref "J6") (pin "2") (pinfunction "2_2") (pintype "bidirectional"))
      (node (ref "J7") (pin "A2") (pinfunction "A2_A2") (pintype "bidirectional"))
      (node (ref "J8") (pin "2") (pinfunction "2_2") (pintype "bidirectional"))
      (node (ref "J9") (pin "A1") (pinfunction "A1_A1") (pintype "bidirectional"))
      (node (ref "J9") (pin "B1") (pinfunction "B1_B1") (pintype "bidirectional"))
      (node (ref "JTAG") (pin "3") (pinfunction "S_3") (pintype "passive"))
      (node (ref "JTAG") (pin "5") (pinfunction "S_5") (pintype "passive"))
      (node (ref "JTAG") (pin "9") (pinfunction "S_9") (pintype "passive"))
      (node (ref "Q2") (pin "2") (pinfunction "S_2") (pintype "passive"))
      (node (ref "Q3") (pin "2") (pinfunction "S_2") (pintype "passive"))
      (node (ref "Q4") (pin "2") (pinfunction "S_2") (pintype "passive"))
      (node (ref "Q5") (pin "2") (pinfunction "GND_2") (pintype "power_in"))
      (node (ref "R100") (pin "2") (pinfunction "2_2") (pintype "passive"))
      (node (ref "R101") (pin "1") (pinfunction "1_1") (pintype "passive"))
      (node (ref "R114") (pin "2") (pinfunction "2_2") (pintype "passive"))
      (node (ref "R120") (pin "1") (pinfunction "1_1") (pintype "passive"))
      (node (ref "R121") (pin "1") (pinfunction "1_1") (pintype "passive"))
      (node (ref "R129") (pin "1") (pinfunction "1_1") (pintype "passive"))
      (node (ref "R132") (pin "2") (pinfunction "2_2") (pintype "passive"))
      (node (ref "R133") (pin "2") (pinfunction "2_2") (pintype "passive"))
      (node (ref "R135") (pin "1") (pinfunction "1_1") (pintype "passive"))
      (node (ref "R142") (pin "2") (pinfunction "2_2") (pintype "passive"))
      (node (ref "R16") (pin "1") (pinfunction "1_1") (pintype "passive"))
      (node (ref "R2") (pin "1") (pinfunction "1_1") (pintype "passive"))
      (node (ref "R24") (pin "2") (pinfunction "2_2") (pintype "passive"))
      (node (ref "R27") (pin "1") (pinfunction "1_1") (pintype "passive"))
      (node (ref "R28") (pin "1") (pinfunction "1_1") (pintype "passive"))
      (node (ref "R30") (pin "1") (pinfunction "1_1") (pintype "passive"))
      (node (ref "R340") (pin "1") (pinfunction "1_1") (pintype "passive"))
      (node (ref "R342") (pin "1") (pinfunction "1_1") (pintype "passive"))
      (node (ref "R344") (pin "1") (pinfunction "1_1") (pintype "passive"))
      (node (ref "R40") (pin "1") (pinfunction "1_1") (pintype "passive"))
      (node (ref "R46") (pin "1") (pinfunction "1_1") (pintype "passive"))
      (node (ref "R47") (pin "1") (pinfunction "1_1") (pintype "passive"))
      (node (ref "R48") (pin "1") (pinfunction "1_1") (pintype "passive"))
      (node (ref "R49") (pin "1") (pinfunction "1_1") (pintype "passive"))
      (node (ref "R50") (pin "1") (pinfunction "1_1") (pintype "passive"))
      (node (ref "R54") (pin "2") (pinfunction "2_2") (pintype "passive"))
      (node (ref "R56") (pin "2") (pinfunction "2_2") (pintype "passive"))
      (node (ref "R59") (pin "2") (pinfunction "2_2") (pintype "passive"))
      (node (ref "R62") (pin "1") (pinfunction "1_1") (pintype "passive"))
      (node (ref "R69") (pin "1") (pinfunction "1_1") (pintype "passive"))
      (node (ref "R76") (pin "1") (pinfunction "1_1") (pintype "passive"))
      (node (ref "R85") (pin "2") (pinfunction "2_2") (pintype "passive"))
      (node (ref "R86") (pin "1") (pinfunction "1_1") (pintype "passive"))
      (node (ref "R87") (pin "2") (pinfunction "2_2") (pintype "passive"))
      (node (ref "R89") (pin "2") (pinfunction "2_2") (pintype "passive"))
      (node (ref "R9") (pin "1") (pinfunction "1_1") (pintype "passive"))
      (node (ref "R97") (pin "1") (pinfunction "1_1") (pintype "passive"))
      (node (ref "S1") (pin "A@1") (pinfunction "A_A@1") (pintype "passive"))
      (node (ref "S2") (pin "A@1") (pinfunction "A_A@1") (pintype "passive"))
      (node (ref "U$101") (pin "A9") (pinfunction "VSS_A9") (pintype "power_in"))
      (node (ref "U$101") (pin "B1") (pinfunction "VSSQ_B1") (pintype "power_in"))
      (node (ref "U$101") (pin "B3") (pinfunction "VSS_B3") (pintype "power_in"))
      (node (ref "U$101") (pin "B9") (pinfunction "VSSQ_B9") (pintype "power_in"))
      (node (ref "U$101") (pin "D1") (pinfunction "VSSQ_D1") (pintype "power_in"))
      (node (ref "U$101") (pin "D8") (pinfunction "VSSQ_D8") (pintype "power_in"))
      (node (ref "U$101") (pin "E1") (pinfunction "VSS_E1") (pintype "power_in"))
      (node (ref "U$101") (pin "E2") (pinfunction "VSSQ_E2") (pintype "power_in"))
      (node (ref "U$101") (pin "E8") (pinfunction "VSSQ_E8") (pintype "power_in"))
      (node (ref "U$101") (pin "F9") (pinfunction "VSSQ_F9") (pintype "power_in"))
      (node (ref "U$101") (pin "G1") (pinfunction "VSSQ_G1") (pintype "power_in"))
      (node (ref "U$101") (pin "G8") (pinfunction "VSS_G8") (pintype "power_in"))
      (node (ref "U$101") (pin "G9") (pinfunction "VSSQ_G9") (pintype "power_in"))
      (node (ref "U$101") (pin "J2") (pinfunction "VSS_J2") (pintype "power_in"))
      (node (ref "U$101") (pin "J8") (pinfunction "VSS_J8") (pintype "power_in"))
      (node (ref "U$101") (pin "M1") (pinfunction "VSS_M1") (pintype "power_in"))
      (node (ref "U$101") (pin "M9") (pinfunction "VSS_M9") (pintype "power_in"))
      (node (ref "U$101") (pin "P1") (pinfunction "VSS_P1") (pintype "power_in"))
      (node (ref "U$101") (pin "P9") (pinfunction "VSS_P9") (pintype "power_in"))
      (node (ref "U$101") (pin "T1") (pinfunction "VSS_T1") (pintype "power_in"))
      (node (ref "U$101") (pin "T9") (pinfunction "VSS_T9") (pintype "power_in"))
      (node (ref "U$19") (pin "6") (pinfunction "GND1_6") (pintype "bidirectional"))
      (node (ref "U$19") (pin "9") (pinfunction "GND2_9") (pintype "bidirectional"))
      (node (ref "U$27") (pin "6") (pinfunction "GND1_6") (pintype "bidirectional"))
      (node (ref "U$27") (pin "9") (pinfunction "GND2_9") (pintype "bidirectional"))
      (node (ref "U$30") (pin "6") (pinfunction "GND_6") (pintype "bidirectional"))
      (node (ref "U$30") (pin "GND1") (pinfunction "SHIELD3_GND1") (pintype "bidirectional"))
      (node (ref "U$30") (pin "GND3") (pinfunction "SHIELD4_GND3") (pintype "bidirectional"))
      (node (ref "U$66") (pin "10") (pinfunction "GND_10") (pintype "bidirectional"))
      (node (ref "U$67") (pin "1") (pinfunction "1DIR_1") (pintype "input"))
      (node (ref "U$67") (pin "10") (pinfunction "GND_10") (pintype "power_in"))
      (node (ref "U$67") (pin "15") (pinfunction "GND_15") (pintype "power_in"))
      (node (ref "U$67") (pin "21") (pinfunction "GND_21") (pintype "power_in"))
      (node (ref "U$67") (pin "24") (pinfunction "2DIR_24") (pintype "input"))
      (node (ref "U$67") (pin "25") (pinfunction "2G_25") (pintype "input"))
      (node (ref "U$67") (pin "28") (pinfunction "GND_28") (pintype "power_in"))
      (node (ref "U$67") (pin "34") (pinfunction "GND_34") (pintype "power_in"))
      (node (ref "U$67") (pin "39") (pinfunction "GND_39") (pintype "power_in"))
      (node (ref "U$67") (pin "4") (pinfunction "GND_4") (pintype "power_in"))
      (node (ref "U$67") (pin "45") (pinfunction "GND_45") (pintype "power_in"))
      (node (ref "U$67") (pin "48") (pinfunction "1G_48") (pintype "input"))
      (node (ref "U$68") (pin "1") (pinfunction "1DIR_1") (pintype "input"))
      (node (ref "U$68") (pin "10") (pinfunction "GND_10") (pintype "power_in"))
      (node (ref "U$68") (pin "15") (pinfunction "GND_15") (pintype "power_in"))
      (node (ref "U$68") (pin "21") (pinfunction "GND_21") (pintype "power_in"))
      (node (ref "U$68") (pin "24") (pinfunction "2DIR_24") (pintype "input"))
      (node (ref "U$68") (pin "25") (pinfunction "2G_25") (pintype "input"))
      (node (ref "U$68") (pin "28") (pinfunction "GND_28") (pintype "power_in"))
      (node (ref "U$68") (pin "34") (pinfunction "GND_34") (pintype "power_in"))
      (node (ref "U$68") (pin "39") (pinfunction "GND_39") (pintype "power_in"))
      (node (ref "U$68") (pin "4") (pinfunction "GND_4") (pintype "power_in"))
      (node (ref "U$68") (pin "45") (pinfunction "GND_45") (pintype "power_in"))
      (node (ref "U$68") (pin "48") (pinfunction "1G_48") (pintype "input"))
      (node (ref "U$69") (pin "10") (pinfunction "GND_10") (pintype "power_in"))
      (node (ref "U$69") (pin "15") (pinfunction "GND_15") (pintype "power_in"))
      (node (ref "U$69") (pin "21") (pinfunction "GND_21") (pintype "power_in"))
      (node (ref "U$69") (pin "24") (pinfunction "2DIR_24") (pintype "input"))
      (node (ref "U$69") (pin "25") (pinfunction "2G_25") (pintype "input"))
      (node (ref "U$69") (pin "28") (pinfunction "GND_28") (pintype "power_in"))
      (node (ref "U$69") (pin "34") (pinfunction "GND_34") (pintype "power_in"))
      (node (ref "U$69") (pin "39") (pinfunction "GND_39") (pintype "power_in"))
      (node (ref "U$69") (pin "4") (pinfunction "GND_4") (pintype "power_in"))
      (node (ref "U$69") (pin "45") (pinfunction "GND_45") (pintype "power_in"))
      (node (ref "U$69") (pin "48") (pinfunction "1G_48") (pintype "input"))
      (node (ref "U$70") (pin "29") (pinfunction "GND_29") (pintype "power_in"))
      (node (ref "U$70") (pin "3") (pinfunction "GND_3") (pintype "power_in"))
      (node (ref "U$70") (pin "36") (pinfunction "GND_36") (pintype "power_in"))
      (node (ref "U$72") (pin "A1") (pinfunction "VSS_A1") (pintype "power_in"))
      (node (ref "U$72") (pin "A18") (pinfunction "VSS_A18") (pintype "power_in"))
      (node (ref "U$72") (pin "F8") (pinfunction "VSS_F8") (pintype "power_in"))
      (node (ref "U$72") (pin "G11") (pinfunction "VSS_G11") (pintype "power_in"))
      (node (ref "U$72") (pin "G12") (pinfunction "VSS_G12") (pintype "power_in"))
      (node (ref "U$72") (pin "G8") (pinfunction "VSS_G8") (pintype "power_in"))
      (node (ref "U$72") (pin "G9") (pinfunction "VSS_G9") (pintype "power_in"))
      (node (ref "U$72") (pin "H10") (pinfunction "VSS_H10") (pintype "power_in"))
      (node (ref "U$72") (pin "H12") (pinfunction "VSS_H12") (pintype "power_in"))
      (node (ref "U$72") (pin "H6") (pinfunction "VSS_H6") (pintype "power_in"))
      (node (ref "U$72") (pin "H7") (pinfunction "VSS_H7") (pintype "power_in"))
      (node (ref "U$72") (pin "H8") (pinfunction "VSS_H8") (pintype "power_in"))
      (node (ref "U$72") (pin "H9") (pinfunction "VSS_H9") (pintype "power_in"))
      (node (ref "U$72") (pin "J10") (pinfunction "VSS_J10") (pintype "power_in"))
      (node (ref "U$72") (pin "J11") (pinfunction "VSS_J11") (pintype "power_in"))
      (node (ref "U$72") (pin "J6") (pinfunction "VSS_J6") (pintype "power_in"))
      (node (ref "U$72") (pin "J7") (pinfunction "VSS_J7") (pintype "power_in"))
      (node (ref "U$72") (pin "J8") (pinfunction "VSS_J8") (pintype "power_in"))
      (node (ref "U$72") (pin "J9") (pinfunction "VSS_J9") (pintype "power_in"))
      (node (ref "U$72") (pin "K10") (pinfunction "VSS_K10") (pintype "power_in"))
      (node (ref "U$72") (pin "K11") (pinfunction "VSS_K11") (pintype "power_in"))
      (node (ref "U$72") (pin "K7") (pinfunction "VSS_K7") (pintype "power_in"))
      (node (ref "U$72") (pin "K9") (pinfunction "VSS_K9") (pintype "power_in"))
      (node (ref "U$72") (pin "L10") (pinfunction "VSS_L10") (pintype "power_in"))
      (node (ref "U$72") (pin "L11") (pinfunction "VSS_L11") (pintype "power_in"))
      (node (ref "U$72") (pin "L12") (pinfunction "VSS_L12") (pintype "power_in"))
      (node (ref "U$72") (pin "L13") (pinfunction "VSS_L13") (pintype "bidirectional"))
      (node (ref "U$72") (pin "M10") (pinfunction "VSS_M10") (pintype "power_in"))
      (node (ref "U$72") (pin "M12") (pinfunction "VSS_M12") (pintype "power_in"))
      (node (ref "U$72") (pin "M14") (pinfunction "VSSA_USB_M14") (pintype "power_in"))
      (node (ref "U$72") (pin "M6") (pinfunction "VSS_M6") (pintype "bidirectional"))
      (node (ref "U$72") (pin "M7") (pinfunction "VSS_M7") (pintype "power_in"))
      (node (ref "U$72") (pin "M8") (pinfunction "VSS_M8") (pintype "power_in"))
      (node (ref "U$72") (pin "M9") (pinfunction "VSS_M9") (pintype "power_in"))
      (node (ref "U$72") (pin "N10") (pinfunction "VSS_N10") (pintype "power_in"))
      (node (ref "U$72") (pin "N11") (pinfunction "VSS_N11") (pintype "power_in"))
      (node (ref "U$72") (pin "N14") (pinfunction "VSSA_USB_N14") (pintype "power_in"))
      (node (ref "U$72") (pin "N7") (pinfunction "VSS_N7") (pintype "power_in"))
      (node (ref "U$72") (pin "P17") (pinfunction "USB1_ID_P17") (pintype "bidirectional"))
      (node (ref "U$72") (pin "V1") (pinfunction "VSS_V1") (pintype "power_in"))
      (node (ref "U$72") (pin "V18") (pinfunction "VSS_V18") (pintype "power_in"))
      (node (ref "U$79") (pin "P4") (pinfunction "P$4_P4") (pintype "bidirectional"))
      (node (ref "U$80") (pin "P4") (pinfunction "P$4_P4") (pintype "bidirectional"))
      (node (ref "U$81") (pin "P2") (pinfunction "P$2_P2") (pintype "bidirectional"))
      (node (ref "U$81") (pin "P3") (pinfunction "P$3_P3") (pintype "bidirectional"))
      (node (ref "U$81") (pin "P4") (pinfunction "P$4_P4") (pintype "bidirectional"))
      (node (ref "U$82") (pin "P1") (pinfunction "P$1_P1") (pintype "bidirectional"))
      (node (ref "U$82") (pin "P2") (pinfunction "P$2_P2") (pintype "bidirectional"))
      (node (ref "U$82") (pin "P4") (pinfunction "P$4_P4") (pintype "bidirectional"))
      (node (ref "U1") (pin "4") (pinfunction "GND_4") (pintype "passive"))
      (node (ref "U10") (pin "4") (pinfunction "GND_4") (pintype "passive"))
      (node (ref "U11") (pin "4") (pinfunction "GND_4") (pintype "passive"))
      (node (ref "U14") (pin "1") (pinfunction "GND_1") (pintype "bidirectional"))
      (node (ref "U14") (pin "TP") (pinfunction "GND_TP") (pintype "bidirectional"))
      (node (ref "U15") (pin "15") (pinfunction "AVSS_ADC_15") (pintype "bidirectional"))
      (node (ref "U15") (pin "20") (pinfunction "DRVSS.1_20") (pintype "bidirectional"))
      (node (ref "U15") (pin "21") (pinfunction "DRVSS.2_21") (pintype "bidirectional"))
      (node (ref "U15") (pin "26") (pinfunction "AVSS_DAC_26") (pintype "bidirectional"))
      (node (ref "U15") (pin "42") (pinfunction "DVSS_42") (pintype "bidirectional"))
      (node (ref "U15") (pin "49") (pinfunction "PPAD_49") (pintype "bidirectional"))
      (node (ref "U16") (pin "10") (pinfunction "1DIR_10") (pintype "input"))
      (node (ref "U16") (pin "2") (pinfunction "OE_2") (pintype "input"))
      (node (ref "U16") (pin "3") (pinfunction "GND_3") (pintype "power_in"))
      (node (ref "U17") (pin "1") (pinfunction "SHUTDOWN_1") (pintype "input"))
      (node (ref "U17") (pin "7") (pinfunction "GND_7") (pintype "power_in"))
      (node (ref "U18") (pin "EPAD") (pinfunction "VSS_EPAD") (pintype "power_in"))
      (node (ref "U2") (pin "4") (pinfunction "GND_4") (pintype "passive"))
      (node (ref "U20") (pin "11") (pinfunction "GND_11") (pintype "power_in"))
      (node (ref "U21") (pin "4") (pinfunction "GND_4") (pintype "passive"))
      (node (ref "U22") (pin "4") (pinfunction "GND_4") (pintype "passive"))
      (node (ref "U23") (pin "10") (pinfunction "PGND2_10") (pintype "bidirectional"))
      (node (ref "U23") (pin "18") (pinfunction "GND_18") (pintype "bidirectional"))
      (node (ref "U23") (pin "3") (pinfunction "PGND1_3") (pintype "bidirectional"))
      (node (ref "U23") (pin "4") (pinfunction "PGND1_4") (pintype "bidirectional"))
      (node (ref "U23") (pin "9") (pinfunction "PGND2_9") (pintype "bidirectional"))
      (node (ref "U27") (pin "4") (pinfunction "GND_4") (pintype "passive"))
      (node (ref "U28") (pin "1") (pinfunction "GND_1") (pintype "bidirectional"))
      (node (ref "U28") (pin "15") (pinfunction "GND_15") (pintype "bidirectional"))
      (node (ref "U28") (pin "16") (pinfunction "GND_16") (pintype "bidirectional"))
      (node (ref "U28") (pin "17") (pinfunction "GND_17") (pintype "bidirectional"))
      (node (ref "U28") (pin "19") (pinfunction "GND_19") (pintype "bidirectional"))
      (node (ref "U28") (pin "20") (pinfunction "GND_20") (pintype "bidirectional"))
      (node (ref "U28") (pin "23") (pinfunction "GND_23") (pintype "bidirectional"))
      (node (ref "U28") (pin "24") (pinfunction "GND_24") (pintype "bidirectional"))
      (node (ref "U28") (pin "28") (pinfunction "GND_28") (pintype "bidirectional"))
      (node (ref "U28") (pin "29") (pinfunction "GND_29") (pintype "bidirectional"))
      (node (ref "U28") (pin "30") (pinfunction "GND_30") (pintype "bidirectional"))
      (node (ref "U28") (pin "31") (pinfunction "GND_31") (pintype "bidirectional"))
      (node (ref "U28") (pin "33") (pinfunction "GND_33") (pintype "bidirectional"))
      (node (ref "U28") (pin "34") (pinfunction "GND_34") (pintype "bidirectional"))
      (node (ref "U28") (pin "35") (pinfunction "GND_35") (pintype "bidirectional"))
      (node (ref "U28") (pin "37") (pinfunction "GND_37") (pintype "bidirectional"))
      (node (ref "U28") (pin "39") (pinfunction "GND_39") (pintype "bidirectional"))
      (node (ref "U28") (pin "44") (pinfunction "GND_44") (pintype "bidirectional"))
      (node (ref "U28") (pin "45") (pinfunction "GND_45") (pintype "bidirectional"))
      (node (ref "U28") (pin "48") (pinfunction "GND_48") (pintype "bidirectional"))
      (node (ref "U28") (pin "49") (pinfunction "GND_49") (pintype "bidirectional"))
      (node (ref "U28") (pin "54") (pinfunction "GND_54") (pintype "bidirectional"))
      (node (ref "U28") (pin "55") (pinfunction "GND_55") (pintype "bidirectional"))
      (node (ref "U28") (pin "59") (pinfunction "GND_59") (pintype "bidirectional"))
      (node (ref "U28") (pin "61") (pinfunction "GND_61") (pintype "bidirectional"))
      (node (ref "U28") (pin "63") (pinfunction "GND_63") (pintype "bidirectional"))
      (node (ref "U28") (pin "64") (pinfunction "GND_64") (pintype "bidirectional"))
      (node (ref "U28") (pin "7") (pinfunction "GND_7") (pintype "bidirectional"))
      (node (ref "U28") (pin "9") (pinfunction "GND_9") (pintype "bidirectional"))
      (node (ref "U28") (pin "G1") (pinfunction "GND_G1") (pintype "bidirectional"))
      (node (ref "U28") (pin "G10") (pinfunction "GND_G10") (pintype "bidirectional"))
      (node (ref "U28") (pin "G11") (pinfunction "GND_G11") (pintype "bidirectional"))
      (node (ref "U28") (pin "G12") (pinfunction "GND_G12") (pintype "bidirectional"))
      (node (ref "U28") (pin "G13") (pinfunction "GND_G13") (pintype "bidirectional"))
      (node (ref "U28") (pin "G14") (pinfunction "GND_G14") (pintype "bidirectional"))
      (node (ref "U28") (pin "G15") (pinfunction "GND_G15") (pintype "bidirectional"))
      (node (ref "U28") (pin "G16") (pinfunction "GND_G16") (pintype "bidirectional"))
      (node (ref "U28") (pin "G17") (pinfunction "GND_G17") (pintype "bidirectional"))
      (node (ref "U28") (pin "G18") (pinfunction "GND_G18") (pintype "bidirectional"))
      (node (ref "U28") (pin "G19") (pinfunction "GND_G19") (pintype "bidirectional"))
      (node (ref "U28") (pin "G2") (pinfunction "GND_G2") (pintype "bidirectional"))
      (node (ref "U28") (pin "G20") (pinfunction "GND_G20") (pintype "bidirectional"))
      (node (ref "U28") (pin "G21") (pinfunction "GND_G21") (pintype "bidirectional"))
      (node (ref "U28") (pin "G22") (pinfunction "GND_G22") (pintype "bidirectional"))
      (node (ref "U28") (pin "G23") (pinfunction "GND_G23") (pintype "bidirectional"))
      (node (ref "U28") (pin "G24") (pinfunction "GND_G24") (pintype "bidirectional"))
      (node (ref "U28") (pin "G25") (pinfunction "GND_G25") (pintype "bidirectional"))
      (node (ref "U28") (pin "G26") (pinfunction "GND_G26") (pintype "bidirectional"))
      (node (ref "U28") (pin "G27") (pinfunction "GND_G27") (pintype "bidirectional"))
      (node (ref "U28") (pin "G28") (pinfunction "GND_G28") (pintype "bidirectional"))
      (node (ref "U28") (pin "G29") (pinfunction "GND_G29") (pintype "bidirectional"))
      (node (ref "U28") (pin "G3") (pinfunction "GND_G3") (pintype "bidirectional"))
      (node (ref "U28") (pin "G30") (pinfunction "GND_G30") (pintype "bidirectional"))
      (node (ref "U28") (pin "G31") (pinfunction "GND_G31") (pintype "bidirectional"))
      (node (ref "U28") (pin "G32") (pinfunction "GND_G32") (pintype "bidirectional"))
      (node (ref "U28") (pin "G33") (pinfunction "GND_G33") (pintype "bidirectional"))
      (node (ref "U28") (pin "G34") (pinfunction "GND_G34") (pintype "bidirectional"))
      (node (ref "U28") (pin "G35") (pinfunction "GND_G35") (pintype "bidirectional"))
      (node (ref "U28") (pin "G36") (pinfunction "GND_G36") (pintype "bidirectional"))
      (node (ref "U28") (pin "G4") (pinfunction "GND_G4") (pintype "bidirectional"))
      (node (ref "U28") (pin "G5") (pinfunction "GND_G5") (pintype "bidirectional"))
      (node (ref "U28") (pin "G6") (pinfunction "GND_G6") (pintype "bidirectional"))
      (node (ref "U28") (pin "G7") (pinfunction "GND_G7") (pintype "bidirectional"))
      (node (ref "U28") (pin "G8") (pinfunction "GND_G8") (pintype "bidirectional"))
      (node (ref "U28") (pin "G9") (pinfunction "GND_G9") (pintype "bidirectional"))
      (node (ref "U29") (pin "11") (pinfunction "GND_11") (pintype "power_in"))
      (node (ref "U3") (pin "4") (pinfunction "GND_4") (pintype "power_in"))
      (node (ref "U30") (pin "4") (pinfunction "GND_4") (pintype "passive"))
      (node (ref "U32") (pin "4") (pinfunction "GND_4") (pintype "passive"))
      (node (ref "U33") (pin "1") (pinfunction "GND_1") (pintype "power_in"))
      (node (ref "U34") (pin "4") (pinfunction "GND_4") (pintype "power_in"))
      (node (ref "U34") (pin "7") (pinfunction "WP_7") (pintype "input"))
      (node (ref "U35") (pin "30") (pinfunction "PGND_30") (pintype "power_in"))
      (node (ref "U35") (pin "41") (pinfunction "AGND_41") (pintype "power_in"))
      (node (ref "U35") (pin "49") (pinfunction "PPAD_49") (pintype "power_in"))
      (node (ref "U36") (pin "P10") (pinfunction "RSVD_GND_P10") (pintype "power_in"))
      (node (ref "U36") (pin "P11") (pinfunction "RSVD_GND_P11") (pintype "power_in"))
      (node (ref "U36") (pin "P12") (pinfunction "RSVD_GND_P12") (pintype "power_in"))
      (node (ref "U36") (pin "P13") (pinfunction "GND_P13") (pintype "power_in"))
      (node (ref "U36") (pin "P8") (pinfunction "RSVD_GND_P8") (pintype "power_in"))
      (node (ref "U36") (pin "P9") (pinfunction "RSVD_GND_P9") (pintype "power_in"))
      (node (ref "U37") (pin "10") (pinfunction "RSVD_GND_10") (pintype "power_in"))
      (node (ref "U37") (pin "12") (pinfunction "GND_12") (pintype "power_in"))
      (node (ref "U37") (pin "13") (pinfunction "GND_13") (pintype "power_in"))
      (node (ref "U37") (pin "16") (pinfunction "GND_16") (pintype "power_in"))
      (node (ref "U37") (pin "5") (pinfunction "GND_5") (pintype "power_in"))
      (node (ref "U4") (pin "10") (pinfunction "PGND2_10") (pintype "bidirectional"))
      (node (ref "U4") (pin "18") (pinfunction "GND_18") (pintype "bidirectional"))
      (node (ref "U4") (pin "3") (pinfunction "PGND1_3") (pintype "bidirectional"))
      (node (ref "U4") (pin "4") (pinfunction "PGND1_4") (pintype "bidirectional"))
      (node (ref "U4") (pin "9") (pinfunction "PGND2_9") (pintype "bidirectional"))
      (node (ref "U8") (pin "11") (pinfunction "GND_11") (pintype "power_in"))
      (node (ref "U9") (pin "3") (pinfunction "3_3") (pintype "passive"))
      (node (ref "X2") (pin "2") (pinfunction "GND_2") (pintype "power_in"))
      (node (ref "Y1") (pin "2") (pinfunction "2_2") (pintype "passive"))
      (node (ref "Y1") (pin "4") (pinfunction "4_4") (pintype "passive"))
      (node (ref "Y2") (pin "2") (pinfunction "2_2") (pintype "passive"))
      (node (ref "Y2") (pin "4") (pinfunction "4_4") (pintype "passive"))
    )
    (net (code "312") (name "GREEN0$43") (class "Default")
      (node (ref "U$68") (pin "37") (pinfunction "1A7_37") (pintype "bidirectional"))
      (node (ref "U$70") (pin "13") (pinfunction "G0_13") (pintype "output"))
    )
    (net (code "313") (name "GREEN1$43") (class "Default")
      (node (ref "U$68") (pin "38") (pinfunction "1A6_38") (pintype "bidirectional"))
      (node (ref "U$70") (pin "14") (pinfunction "G1_14") (pintype "output"))
    )
    (net (code "314") (name "GREEN2$43") (class "Default")
      (node (ref "U$68") (pin "40") (pinfunction "1A5_40") (pintype "bidirectional"))
      (node (ref "U$70") (pin "15") (pinfunction "G2_15") (pintype "output"))
    )
    (net (code "315") (name "GREEN3$43") (class "Default")
      (node (ref "U$68") (pin "41") (pinfunction "1A4_41") (pintype "bidirectional"))
      (node (ref "U$70") (pin "16") (pinfunction "G3_16") (pintype "output"))
    )
    (net (code "316") (name "GREEN4$43") (class "Default")
      (node (ref "U$68") (pin "43") (pinfunction "1A3_43") (pintype "bidirectional"))
      (node (ref "U$70") (pin "17") (pinfunction "G4_17") (pintype "output"))
    )
    (net (code "317") (name "GREEN5$43") (class "Default")
      (node (ref "U$68") (pin "44") (pinfunction "1A2_44") (pintype "bidirectional"))
      (node (ref "U$70") (pin "18") (pinfunction "G5_18") (pintype "output"))
    )
    (net (code "318") (name "GREEN6$43") (class "Default")
      (node (ref "U$68") (pin "46") (pinfunction "1A1_46") (pintype "bidirectional"))
      (node (ref "U$70") (pin "19") (pinfunction "G6_19") (pintype "output"))
    )
    (net (code "319") (name "GREEN7$43") (class "Default")
      (node (ref "U$68") (pin "47") (pinfunction "1A0_47") (pintype "bidirectional"))
      (node (ref "U$70") (pin "20") (pinfunction "G7_20") (pintype "output"))
    )
    (net (code "320") (name "GYRO_PLLFILT$132") (class "Default")
      (node (ref "C271") (pin "1") (pinfunction "1_1") (pintype "passive"))
      (node (ref "U36") (pin "P14") (pinfunction "PLLFILT_P14") (pintype "passive"))
    )
    (net (code "321") (name "HSYNC$44") (class "Default")
      (node (ref "IC4") (pin "4") (pinfunction "HSYNC_4") (pintype "bidirectional"))
      (node (ref "R117") (pin "2") (pinfunction "2_2") (pintype "passive"))
    )
    (net (code "322") (name "I2C_VREF2$44") (class "Default")
      (node (ref "R106") (pin "2") (pinfunction "2_2") (pintype "passive"))
      (node (ref "U33") (pin "7") (pinfunction "VREF2_7") (pintype "input"))
      (node (ref "U33") (pin "8") (pinfunction "EN_8") (pintype "input"))
    )
    (net (code "323") (name "IDCK+$44") (class "Default")
      (node (ref "IC4") (pin "57") (pinfunction "IDCK+_57") (pintype "bidirectional"))
      (node (ref "RP8") (pin "6") (pinfunction "6_6") (pintype "passive"))
    )
    (net (code "324") (name "INT_LDO$45") (class "Default")
      (node (ref "C223") (pin "1") (pinfunction "1_1") (pintype "passive"))
      (node (ref "U35") (pin "48") (pinfunction "INT_LDO_48") (pintype "output"))
    )
    (net (code "325") (name "ISET1$45") (class "Default")
      (node (ref "R120") (pin "2") (pinfunction "2_2") (pintype "passive"))
      (node (ref "U35") (pin "35") (pinfunction "ISET1_35") (pintype "input"))
    )
    (net (code "326") (name "ISET2$45") (class "Default")
      (node (ref "R121") (pin "2") (pinfunction "2_2") (pintype "passive"))
      (node (ref "U35") (pin "36") (pinfunction "ISET2_36") (pintype "input"))
    )
    (net (code "327") (name "JTAG_EMU0$45") (class "Default")
      (node (ref "R126") (pin "1") (pinfunction "1_1") (pintype "passive"))
      (node (ref "U$72") (pin "C14") (pinfunction "EMU0|GPIO3_7_C14") (pintype "bidirectional"))
    )
    (net (code "328") (name "JTAG_EMU1$45") (class "Default")
      (node (ref "R127") (pin "1") (pinfunction "1_1") (pintype "passive"))
      (node (ref "U$72") (pin "B14") (pinfunction "EMU1|GPIO3_8_B14") (pintype "bidirectional"))
    )
    (net (code "329") (name "LDO_PGOOD$45") (class "Default")
      (node (ref "U$72") (pin "B5") (pinfunction "RTC_PWRONRSTN_B5") (pintype "input"))
      (node (ref "U35") (pin "46") (pinfunction "LDO_PGOOD_46") (pintype "open_collector"))
    )
    (net (code "330") (name "LINE1LM$15") (class "Default")
      (node (ref "C52") (pin "1") (pinfunction "1_1") (pintype "passive"))
      (node (ref "U15") (pin "4") (pinfunction "LINE1LM_4") (pintype "bidirectional"))
    )
    (net (code "331") (name "LINE1RM$15") (class "Default")
      (node (ref "C53") (pin "1") (pinfunction "1_1") (pintype "passive"))
      (node (ref "U15") (pin "6") (pinfunction "LINE1RM_6") (pintype "bidirectional"))
    )
    (net (code "332") (name "L_L4$45") (class "Default")
      (node (ref "D31") (pin "A") (pinfunction "A_A") (pintype "passive"))
      (node (ref "L14") (pin "2") (pinfunction "2_2") (pintype "passive"))
      (node (ref "U35") (pin "37") (pinfunction "L4_37") (pintype "passive"))
    )
    (net (code "333") (name "M0A$6") (class "Default")
      (node (ref "R4") (pin "1") (pinfunction "1_1") (pintype "passive"))
      (node (ref "U4") (pin "1") (pinfunction "A01_1") (pintype "bidirectional"))
      (node (ref "U4") (pin "2") (pinfunction "A01_2") (pintype "bidirectional"))
      (node (ref "U5") (pin "A1") (pinfunction "A1_A1") (pintype "bidirectional"))
      (node (ref "U5") (pin "A2") (pinfunction "A2_A2") (pintype "bidirectional"))
      (node (ref "U6") (pin "1") (pinfunction "1_1") (pintype "passive"))
      (node (ref "U6") (pin "4") (pinfunction "4_4") (pintype "passive"))
    )
    (net (code "334") (name "M0A$31") (class "Default")
      (node (ref "R64") (pin "1") (pinfunction "1_1") (pintype "passive"))
      (node (ref "U23") (pin "1") (pinfunction "A01_1") (pintype "bidirectional"))
      (node (ref "U23") (pin "2") (pinfunction "A01_2") (pintype "bidirectional"))
      (node (ref "U24") (pin "A1") (pinfunction "A1_A1") (pintype "bidirectional"))
      (node (ref "U24") (pin "A2") (pinfunction "A2_A2") (pintype "bidirectional"))
      (node (ref "U25") (pin "1") (pinfunction "1_1") (pintype "passive"))
      (node (ref "U25") (pin "4") (pinfunction "4_4") (pintype "passive"))
    )
    (net (code "335") (name "M0B$6") (class "Default")
      (node (ref "R10") (pin "1") (pinfunction "1_1") (pintype "passive"))
      (node (ref "R5") (pin "1") (pinfunction "1_1") (pintype "passive"))
      (node (ref "U4") (pin "5") (pinfunction "A02_5") (pintype "bidirectional"))
      (node (ref "U4") (pin "6") (pinfunction "A02_6") (pintype "bidirectional"))
      (node (ref "U5") (pin "A3") (pinfunction "A3_A3") (pintype "bidirectional"))
    )
    (net (code "336") (name "M0B$31") (class "Default")
      (node (ref "R65") (pin "1") (pinfunction "1_1") (pintype "passive"))
      (node (ref "R70") (pin "1") (pinfunction "1_1") (pintype "passive"))
      (node (ref "U23") (pin "5") (pinfunction "A02_5") (pintype "bidirectional"))
      (node (ref "U23") (pin "6") (pinfunction "A02_6") (pintype "bidirectional"))
      (node (ref "U24") (pin "A3") (pinfunction "A3_A3") (pintype "bidirectional"))
    )
    (net (code "337") (name "M1A$6") (class "Default")
      (node (ref "R11") (pin "1") (pinfunction "1_1") (pintype "passive"))
      (node (ref "U4") (pin "11") (pinfunction "B01_11") (pintype "bidirectional"))
      (node (ref "U4") (pin "12") (pinfunction "B01_12") (pintype "bidirectional"))
      (node (ref "U5") (pin "B1") (pinfunction "B1_B1") (pintype "bidirectional"))
      (node (ref "U5") (pin "B2") (pinfunction "B2_B2") (pintype "bidirectional"))
      (node (ref "U7") (pin "1") (pinfunction "1_1") (pintype "passive"))
      (node (ref "U7") (pin "4") (pinfunction "4_4") (pintype "passive"))
    )
    (net (code "338") (name "M1A$31") (class "Default")
      (node (ref "R71") (pin "1") (pinfunction "1_1") (pintype "passive"))
      (node (ref "U23") (pin "11") (pinfunction "B01_11") (pintype "bidirectional"))
      (node (ref "U23") (pin "12") (pinfunction "B01_12") (pintype "bidirectional"))
      (node (ref "U24") (pin "B1") (pinfunction "B1_B1") (pintype "bidirectional"))
      (node (ref "U24") (pin "B2") (pinfunction "B2_B2") (pintype "bidirectional"))
      (node (ref "U26") (pin "1") (pinfunction "1_1") (pintype "passive"))
      (node (ref "U26") (pin "4") (pinfunction "4_4") (pintype "passive"))
    )
    (net (code "339") (name "M1B$6") (class "Default")
      (node (ref "R12") (pin "1") (pinfunction "1_1") (pintype "passive"))
      (node (ref "R17") (pin "1") (pinfunction "1_1") (pintype "passive"))
      (node (ref "U4") (pin "7") (pinfunction "B02_7") (pintype "bidirectional"))
      (node (ref "U4") (pin "8") (pinfunction "B02_8") (pintype "bidirectional"))
      (node (ref "U5") (pin "B3") (pinfunction "B3_B3") (pintype "bidirectional"))
    )
    (net (code "340") (name "M1B$31") (class "Default")
      (node (ref "R72") (pin "1") (pinfunction "1_1") (pintype "passive"))
      (node (ref "R77") (pin "1") (pinfunction "1_1") (pintype "passive"))
      (node (ref "U23") (pin "7") (pinfunction "B02_7") (pintype "bidirectional"))
      (node (ref "U23") (pin "8") (pinfunction "B02_8") (pintype "bidirectional"))
      (node (ref "U24") (pin "B3") (pinfunction "B3_B3") (pintype "bidirectional"))
    )
    (net (code "341") (name "MISO$24") (class "Default")
      (node (ref "J7") (pin "B1") (pinfunction "B1_B1") (pintype "bidirectional"))
      (node (ref "RP4") (pin "6") (pinfunction "6_6") (pintype "passive"))
      (node (ref "U20") (pin "13") (pinfunction "B7_13") (pintype "bidirectional"))
    )
    (net (code "342") (name "MMC_CLK$22") (class "Default")
      (node (ref "RP1") (pin "15") (pinfunction "15_15") (pintype "passive"))
      (node (ref "U$30") (pin "5") (pinfunction "CLK/SCLK_5") (pintype "bidirectional"))
    )
    (net (code "343") (name "MMC_CMD$22") (class "Default")
      (node (ref "RP1") (pin "16") (pinfunction "16_16") (pintype "passive"))
      (node (ref "U$30") (pin "3") (pinfunction "CMD/DI_3") (pintype "bidirectional"))
    )
    (net (code "344") (name "MMC_D0$22") (class "Default")
      (node (ref "RP1") (pin "12") (pinfunction "12_12") (pintype "passive"))
      (node (ref "U$30") (pin "7") (pinfunction "DAT0/DO_7") (pintype "bidirectional"))
    )
    (net (code "345") (name "MMC_D1$22") (class "Default")
      (node (ref "RP1") (pin "11") (pinfunction "11_11") (pintype "passive"))
      (node (ref "U$30") (pin "8") (pinfunction "DAT1/RSV_8") (pintype "bidirectional"))
    )
    (net (code "346") (name "MMC_D2$22") (class "Default")
      (node (ref "RP1") (pin "10") (pinfunction "10_10") (pintype "passive"))
      (node (ref "U$30") (pin "1") (pinfunction "DAT2/RSV_1") (pintype "bidirectional"))
    )
    (net (code "347") (name "MMC_D3$22") (class "Default")
      (node (ref "RP1") (pin "9") (pinfunction "9_9") (pintype "passive"))
      (node (ref "U$30") (pin "2") (pinfunction "DAT3_CD/CS_2") (pintype "bidirectional"))
    )
    (net (code "348") (name "MOSI$24") (class "Default")
      (node (ref "J7") (pin "B3") (pinfunction "B3_B3") (pintype "bidirectional"))
      (node (ref "RP4") (pin "1") (pinfunction "1_1") (pintype "passive"))
      (node (ref "U20") (pin "18") (pinfunction "B2_18") (pintype "bidirectional"))
    )
    (net (code "349") (name "MSEN$44") (class "Default")
      (node (ref "IC4") (pin "11") (pinfunction "MSEN_11") (pintype "bidirectional"))
      (node (ref "R104") (pin "2") (pinfunction "2_2") (pintype "passive"))
    )
    (net (code "350") (name "NIRQ$24") (class "Default")
      (node (ref "J7") (pin "A1") (pinfunction "A1_A1") (pintype "bidirectional"))
      (node (ref "RP4") (pin "5") (pinfunction "5_5") (pintype "passive"))
      (node (ref "U20") (pin "14") (pinfunction "B6_14") (pintype "bidirectional"))
    )
    (net (code "351") (name "NMI$45") (class "Default")
      (node (ref "R119") (pin "2") (pinfunction "2_2") (pintype "passive"))
      (node (ref "U$72") (pin "B18") (pinfunction "EXTINTN_B18") (pintype "input"))
    )
    (net (code "352") (name "Net-(C29-Pad1)") (class "Default")
      (node (ref "C29") (pin "1") (pinfunction "1_1") (pintype "passive"))
      (node (ref "C30") (pin "1") (pinfunction "1_1") (pintype "passive"))
      (node (ref "FB4") (pin "1") (pinfunction "1_1") (pintype "passive"))
      (node (ref "K1") (pin "A1") (pinfunction "VCC_A1") (pintype "bidirectional"))
    )
    (net (code "353") (name "Net-(C31-Pad1)") (class "Default")
      (node (ref "C31") (pin "1") (pinfunction "1_1") (pintype "passive"))
      (node (ref "C32") (pin "1") (pinfunction "1_1") (pintype "passive"))
      (node (ref "FB3") (pin "1") (pinfunction "1_1") (pintype "passive"))
      (node (ref "K1") (pin "B1") (pinfunction "VCC_B1") (pintype "bidirectional"))
    )
    (net (code "354") (name "Net-(C54-Pad1)") (class "Default")
      (node (ref "C54") (pin "1") (pinfunction "1_1") (pintype "passive"))
      (node (ref "R32") (pin "1") (pinfunction "1_1") (pintype "passive"))
      (node (ref "R34") (pin "1") (pinfunction "1_1") (pintype "passive"))
    )
    (net (code "355") (name "Net-(C67-Pad1)") (class "Default")
      (node (ref "C67") (pin "1") (pinfunction "1_1") (pintype "passive"))
      (node (ref "R41") (pin "2") (pinfunction "2_2") (pintype "passive"))
    )
    (net (code "356") (name "Net-(C121-Pad1)") (class "Default")
      (node (ref "C121") (pin "1") (pinfunction "1_1") (pintype "passive"))
      (node (ref "R83") (pin "2") (pinfunction "2_2") (pintype "passive"))
      (node (ref "Y2") (pin "1") (pinfunction "1_1") (pintype "passive"))
    )
    (net (code "357") (name "Net-(D1-PadA)") (class "Default")
      (node (ref "D1") (pin "A") (pinfunction "A_A") (pintype "passive"))
      (node (ref "R18") (pin "1") (pinfunction "1_1") (pintype "passive"))
    )
    (net (code "358") (name "Net-(D2-PadA)") (class "Default")
      (node (ref "D2") (pin "A") (pinfunction "A_A") (pintype "passive"))
      (node (ref "R23") (pin "2") (pinfunction "2_2") (pintype "passive"))
    )
    (net (code "359") (name "Net-(D11-PadA)") (class "Default")
      (node (ref "D11") (pin "A") (pinfunction "A_A") (pintype "passive"))
      (node (ref "R55") (pin "2") (pinfunction "2_2") (pintype "passive"))
    )
    (net (code "360") (name "Net-(D12-PadA)") (class "Default")
      (node (ref "D12") (pin "A") (pinfunction "A_A") (pintype "passive"))
      (node (ref "R58") (pin "2") (pinfunction "2_2") (pintype "passive"))
    )
    (net (code "361") (name "Net-(IC3A-VCAP_2)") (class "Default")
      (node (ref "C136") (pin "1") (pinfunction "1_1") (pintype "passive"))
      (node (ref "IC3") (pin "73") (pinfunction "VCAP_2_73") (pintype "input"))
    )
    (net (code "362") (name "Net-(IC3B-OSC_IN)") (class "Default")
      (node (ref "C122") (pin "1") (pinfunction "1_1") (pintype "passive"))
      (node (ref "IC3") (pin "12") (pinfunction "OSC_IN_12") (pintype "input"))
      (node (ref "Y2") (pin "3") (pinfunction "3_3") (pintype "passive"))
    )
    (net (code "363") (name "Net-(IC3B-OSC_OUT)") (class "Default")
      (node (ref "IC3") (pin "13") (pinfunction "OSC_OUT_13") (pintype "output"))
      (node (ref "R83") (pin "1") (pinfunction "1_1") (pintype "passive"))
    )
    (net (code "364") (name "Net-(IC3M-VCAP_1)") (class "Default")
      (node (ref "C135") (pin "1") (pinfunction "1_1") (pintype "passive"))
      (node (ref "IC3") (pin "49") (pinfunction "VCAP_1_49") (pintype "power_in"))
    )
    (net (code "365") (name "Net-(J12-Pad10)") (class "Default")
      (node (ref "J12") (pin "10") (pinfunction "10_10") (pintype "passive"))
      (node (ref "J12") (pin "12") (pinfunction "12_12") (pintype "passive"))
      (node (ref "J12") (pin "14") (pinfunction "14_14") (pintype "passive"))
      (node (ref "J12") (pin "16") (pinfunction "16_16") (pintype "passive"))
      (node (ref "J12") (pin "18") (pinfunction "18_18") (pintype "passive"))
      (node (ref "J12") (pin "2") (pinfunction "2_2") (pintype "passive"))
      (node (ref "J12") (pin "20") (pinfunction "20_20") (pintype "passive"))
      (node (ref "J12") (pin "4") (pinfunction "4_4") (pintype "passive"))
      (node (ref "J12") (pin "6") (pinfunction "6_6") (pintype "passive"))
      (node (ref "J12") (pin "8") (pinfunction "8_8") (pintype "passive"))
      (node (ref "R79") (pin "1") (pinfunction "1_1") (pintype "passive"))
    )
    (net (code "366") (name "Net-(Q1-G)") (class "Default")
      (node (ref "Q1") (pin "1") (pinfunction "G_1") (pintype "passive"))
      (node (ref "Q6") (pin "1") (pinfunction "G_1") (pintype "passive"))
      (node (ref "R19") (pin "1") (pinfunction "1_1") (pintype "passive"))
      (node (ref "R20") (pin "1") (pinfunction "1_1") (pintype "passive"))
    )
    (net (code "367") (name "Net-(Q1-S)") (class "Default")
      (node (ref "F3") (pin "1") (pinfunction "1_1") (pintype "passive"))
      (node (ref "Q1") (pin "3") (pinfunction "S_3") (pintype "passive"))
    )
    (net (code "368") (name "Net-(Q2-D)") (class "Default")
      (node (ref "D2") (pin "C") (pinfunction "C_C") (pintype "passive"))
      (node (ref "Q2") (pin "3") (pinfunction "D_3") (pintype "passive"))
    )
    (net (code "369") (name "Net-(Q2-G)") (class "Default")
      (node (ref "Q2") (pin "1") (pinfunction "G_1") (pintype "passive"))
      (node (ref "R25") (pin "2") (pinfunction "2_2") (pintype "passive"))
    )
    (net (code "370") (name "Net-(Q3-D)") (class "Default")
      (node (ref "D11") (pin "C") (pinfunction "C_C") (pintype "passive"))
      (node (ref "Q3") (pin "3") (pinfunction "D_3") (pintype "passive"))
    )
    (net (code "371") (name "Net-(Q3-G)") (class "Default")
      (node (ref "Q3") (pin "1") (pinfunction "G_1") (pintype "passive"))
      (node (ref "R57") (pin "2") (pinfunction "2_2") (pintype "passive"))
    )
    (net (code "372") (name "Net-(Q4-D)") (class "Default")
      (node (ref "D12") (pin "C") (pinfunction "C_C") (pintype "passive"))
      (node (ref "Q4") (pin "3") (pinfunction "D_3") (pintype "passive"))
    )
    (net (code "373") (name "Net-(Q4-G)") (class "Default")
      (node (ref "Q4") (pin "1") (pinfunction "G_1") (pintype "passive"))
      (node (ref "R60") (pin "2") (pinfunction "2_2") (pintype "passive"))
    )
    (net (code "374") (name "Net-(R6-Pad2)") (class "Default")
      (node (ref "R6") (pin "2") (pinfunction "2_2") (pintype "passive"))
      (node (ref "R7") (pin "2") (pinfunction "2_2") (pintype "passive"))
      (node (ref "R8") (pin "1") (pinfunction "1_1") (pintype "passive"))
      (node (ref "R9") (pin "2") (pinfunction "2_2") (pintype "passive"))
    )
    (net (code "375") (name "Net-(R10-Pad2)") (class "Default")
      (node (ref "R10") (pin "2") (pinfunction "2_2") (pintype "passive"))
      (node (ref "U6") (pin "2") (pinfunction "2_2") (pintype "passive"))
      (node (ref "U6") (pin "3") (pinfunction "3_3") (pintype "passive"))
    )
    (net (code "376") (name "Net-(R13-Pad2)") (class "Default")
      (node (ref "R13") (pin "2") (pinfunction "2_2") (pintype "passive"))
      (node (ref "R14") (pin "2") (pinfunction "2_2") (pintype "passive"))
      (node (ref "R15") (pin "1") (pinfunction "1_1") (pintype "passive"))
      (node (ref "R16") (pin "2") (pinfunction "2_2") (pintype "passive"))
    )
    (net (code "377") (name "Net-(R17-Pad2)") (class "Default")
      (node (ref "R17") (pin "2") (pinfunction "2_2") (pintype "passive"))
      (node (ref "U7") (pin "2") (pinfunction "2_2") (pintype "passive"))
      (node (ref "U7") (pin "3") (pinfunction "3_3") (pintype "passive"))
    )
    (net (code "378") (name "Net-(R20-Pad2)") (class "Default")
      (node (ref "R20") (pin "2") (pinfunction "2_2") (pintype "passive"))
      (node (ref "U9") (pin "2") (pinfunction "2_2") (pintype "passive"))
    )
    (net (code "379") (name "Net-(R66-Pad2)") (class "Default")
      (node (ref "R66") (pin "2") (pinfunction "2_2") (pintype "passive"))
      (node (ref "R67") (pin "2") (pinfunction "2_2") (pintype "passive"))
      (node (ref "R68") (pin "1") (pinfunction "1_1") (pintype "passive"))
      (node (ref "R69") (pin "2") (pinfunction "2_2") (pintype "passive"))
    )
    (net (code "380") (name "Net-(R70-Pad2)") (class "Default")
      (node (ref "R70") (pin "2") (pinfunction "2_2") (pintype "passive"))
      (node (ref "U25") (pin "2") (pinfunction "2_2") (pintype "passive"))
      (node (ref "U25") (pin "3") (pinfunction "3_3") (pintype "passive"))
    )
    (net (code "381") (name "Net-(R73-Pad2)") (class "Default")
      (node (ref "R73") (pin "2") (pinfunction "2_2") (pintype "passive"))
      (node (ref "R74") (pin "2") (pinfunction "2_2") (pintype "passive"))
      (node (ref "R75") (pin "1") (pinfunction "1_1") (pintype "passive"))
      (node (ref "R76") (pin "2") (pinfunction "2_2") (pintype "passive"))
    )
    (net (code "382") (name "Net-(R77-Pad2)") (class "Default")
      (node (ref "R77") (pin "2") (pinfunction "2_2") (pintype "passive"))
      (node (ref "U26") (pin "2") (pinfunction "2_2") (pintype "passive"))
      (node (ref "U26") (pin "3") (pinfunction "3_3") (pintype "passive"))
    )
    (net (code "383") (name "Net-(R118-Pad1)") (class "Default")
      (node (ref "R118") (pin "1") (pinfunction "1_1") (pintype "passive"))
      (node (ref "Y4") (pin "1") (pinfunction "1_1") (pintype "passive"))
    )
    (net (code "384") (name "Net-(U$19-BOOT)") (class "Default")
      (node (ref "C264") (pin "1") (pinfunction "1_1") (pintype "passive"))
      (node (ref "U$19") (pin "1") (pinfunction "BOOT_1") (pintype "bidirectional"))
    )
    (net (code "385") (name "Net-(U$19-PH)") (class "Default")
      (node (ref "C264") (pin "2") (pinfunction "2_2") (pintype "passive"))
      (node (ref "D15") (pin "C") (pinfunction "C_C") (pintype "passive"))
      (node (ref "L15") (pin "1") (pinfunction "1_1") (pintype "passive"))
      (node (ref "U$19") (pin "8") (pinfunction "PH_8") (pintype "bidirectional"))
    )
    (net (code "386") (name "Net-(U$19-VSENSE)") (class "Default")
      (node (ref "R141") (pin "2") (pinfunction "2_2") (pintype "passive"))
      (node (ref "R142") (pin "1") (pinfunction "1_1") (pintype "passive"))
      (node (ref "U$19") (pin "4") (pinfunction "VSENSE_4") (pintype "bidirectional"))
    )
    (net (code "387") (name "Net-(U$27-BOOT)") (class "Default")
      (node (ref "C88") (pin "1") (pinfunction "1_1") (pintype "passive"))
      (node (ref "U$27") (pin "1") (pinfunction "BOOT_1") (pintype "bidirectional"))
    )
    (net (code "388") (name "Net-(U$27-ENA)") (class "Default")
      (node (ref "R33") (pin "2") (pinfunction "2_2") (pintype "passive"))
      (node (ref "U$27") (pin "5") (pinfunction "ENA_5") (pintype "bidirectional"))
    )
    (net (code "389") (name "Net-(U$27-PH)") (class "Default")
      (node (ref "C88") (pin "2") (pinfunction "2_2") (pintype "passive"))
      (node (ref "D10") (pin "C") (pinfunction "C_C") (pintype "passive"))
      (node (ref "L2") (pin "1") (pinfunction "1_1") (pintype "passive"))
      (node (ref "U$27") (pin "8") (pinfunction "PH_8") (pintype "bidirectional"))
    )
    (net (code "390") (name "Net-(U$27-VSENSE)") (class "Default")
      (node (ref "R53") (pin "2") (pinfunction "2_2") (pintype "passive"))
      (node (ref "R54") (pin "1") (pinfunction "1_1") (pintype "passive"))
      (node (ref "U$27") (pin "4") (pinfunction "VSENSE_4") (pintype "bidirectional"))
    )
    (net (code "391") (name "Net-(U$72B-CAP_VBB_MPU)") (class "Default")
      (node (ref "C164") (pin "1") (pinfunction "1_1") (pintype "passive"))
      (node (ref "U$72") (pin "C10") (pinfunction "CAP_VBB_MPU_C10") (pintype "bidirectional"))
    )
    (net (code "392") (name "Net-(U$72B-CAP_VDD_SRAM_CORE)") (class "Default")
      (node (ref "C166") (pin "1") (pinfunction "1_1") (pintype "passive"))
      (node (ref "U$72") (pin "D9") (pinfunction "CAP_VDD_SRAM_CORE_D9") (pintype "bidirectional"))
    )
    (net (code "393") (name "Net-(U$72B-CAP_VDD_SRAM_MPU)") (class "Default")
      (node (ref "C167") (pin "1") (pinfunction "1_1") (pintype "passive"))
      (node (ref "U$72") (pin "D11") (pinfunction "CAP_VDD_SRAM_MPU_D11") (pintype "bidirectional"))
    )
    (net (code "394") (name "Net-(U$72B-CAP_VSS_RTC)") (class "Default")
      (node (ref "C165") (pin "1") (pinfunction "1_1") (pintype "passive"))
      (node (ref "U$72") (pin "D6") (pinfunction "CAP_VSS_RTC_D6") (pintype "bidirectional"))
    )
    (net (code "395") (name "Net-(U14-IN)") (class "Default")
      (node (ref "C26") (pin "1") (pinfunction "1_1") (pintype "passive"))
      (node (ref "FB2") (pin "2") (pinfunction "2_2") (pintype "passive"))
      (node (ref "U14") (pin "2") (pinfunction "IN_2") (pintype "bidirectional"))
    )
    (net (code "396") (name "Net-(U15-MCLK)") (class "Default")
      (node (ref "R35") (pin "1") (pinfunction "1_1") (pintype "passive"))
      (node (ref "U15") (pin "37") (pinfunction "MCLK_37") (pintype "bidirectional"))
    )
    (net (code "397") (name "Net-(U15-MFP0)") (class "Default")
      (node (ref "R26") (pin "1") (pinfunction "1_1") (pintype "passive"))
      (node (ref "R27") (pin "2") (pinfunction "2_2") (pintype "passive"))
      (node (ref "U15") (pin "45") (pinfunction "MFP0_45") (pintype "bidirectional"))
    )
    (net (code "398") (name "Net-(U15-MFP1)") (class "Default")
      (node (ref "R28") (pin "2") (pinfunction "2_2") (pintype "passive"))
      (node (ref "R29") (pin "1") (pinfunction "1_1") (pintype "passive"))
      (node (ref "U15") (pin "46") (pinfunction "MFP1_46") (pintype "bidirectional"))
    )
    (net (code "399") (name "Net-(U15-MIC3L)") (class "Default")
      (node (ref "C54") (pin "2") (pinfunction "2_2") (pintype "passive"))
      (node (ref "U15") (pin "11") (pinfunction "MIC3L_11") (pintype "bidirectional"))
    )
    (net (code "400") (name "Net-(U15-MICBIAS)") (class "Default")
      (node (ref "R32") (pin "2") (pinfunction "2_2") (pintype "passive"))
      (node (ref "U15") (pin "13") (pinfunction "MICBIAS_13") (pintype "bidirectional"))
    )
    (net (code "401") (name "Net-(U15-MICDET)") (class "Default")
      (node (ref "R34") (pin "2") (pinfunction "2_2") (pintype "passive"))
      (node (ref "U15") (pin "12") (pinfunction "MICDET_12") (pintype "bidirectional"))
    )
    (net (code "402") (name "Net-(U15-SELECT)") (class "Default")
      (node (ref "R30") (pin "2") (pinfunction "2_2") (pintype "passive"))
      (node (ref "U15") (pin "43") (pinfunction "SELECT_43") (pintype "bidirectional"))
    )
    (net (code "403") (name "Net-(U17-BYPASS)") (class "Default")
      (node (ref "C65") (pin "1") (pinfunction "1_1") (pintype "passive"))
      (node (ref "C66") (pin "2") (pinfunction "2_2") (pintype "passive"))
      (node (ref "R42") (pin "1") (pinfunction "1_1") (pintype "passive"))
      (node (ref "U17") (pin "2") (pinfunction "BYPASS_2") (pintype "passive"))
    )
    (net (code "404") (name "Net-(U17-IN+)") (class "Default")
      (node (ref "C66") (pin "1") (pinfunction "1_1") (pintype "passive"))
      (node (ref "R42") (pin "2") (pinfunction "2_2") (pintype "passive"))
      (node (ref "U17") (pin "3") (pinfunction "IN+_3") (pintype "input"))
    )
    (net (code "405") (name "Net-(U17-IN-)") (class "Default")
      (node (ref "C68") (pin "1") (pinfunction "1_1") (pintype "passive"))
      (node (ref "R41") (pin "1") (pinfunction "1_1") (pintype "passive"))
      (node (ref "R43") (pin "2") (pinfunction "2_2") (pintype "passive"))
      (node (ref "U17") (pin "4") (pinfunction "IN-_4") (pintype "input"))
    )
    (net (code "406") (name "Net-(U17-VO1)") (class "Default")
      (node (ref "C68") (pin "2") (pinfunction "2_2") (pintype "passive"))
      (node (ref "R43") (pin "1") (pinfunction "1_1") (pintype "passive"))
      (node (ref "SPKR-") (pin "TP") (pinfunction "TP_TP") (pintype "input"))
      (node (ref "U17") (pin "5") (pinfunction "VO1_5") (pintype "output"))
    )
    (net (code "407") (name "Net-(U17-VO2)") (class "Default")
      (node (ref "SPKR+") (pin "TP") (pinfunction "TP_TP") (pintype "input"))
      (node (ref "U17") (pin "8") (pinfunction "VO2_8") (pintype "output"))
    )
    (net (code "408") (name "Net-(U28-2G4_ANT1_WB)") (class "Default")
      (node (ref "CONN1") (pin "1") (pinfunction "1_1") (pintype "passive"))
      (node (ref "U28") (pin "32") (pinfunction "2G4_ANT1_WB_32") (pintype "bidirectional"))
    )
    (net (code "409") (name "Net-(U29-VCCB)") (class "Default")
      (node (ref "R78") (pin "1") (pinfunction "1_1") (pintype "passive"))
      (node (ref "U29") (pin "19") (pinfunction "VCCB_19") (pintype "power_in"))
      (node (ref "U30") (pin "8") (pinfunction "VCCB_8") (pintype "power_in"))
    )
    (net (code "410") (name "Net-(U30-B1)") (class "Default")
      (node (ref "J13") (pin "9") (pinfunction "9_9") (pintype "passive"))
      (node (ref "R80") (pin "2") (pinfunction "2_2") (pintype "passive"))
      (node (ref "U30") (pin "7") (pinfunction "B1_7") (pintype "output"))
    )
    (net (code "411") (name "Net-(U30-B2)") (class "Default")
      (node (ref "J13") (pin "10") (pinfunction "10_10") (pintype "passive"))
      (node (ref "R81") (pin "2") (pinfunction "2_2") (pintype "passive"))
      (node (ref "U30") (pin "6") (pinfunction "B2_6") (pintype "output"))
    )
    (net (code "412") (name "Net-(U31-B')") (class "Default")
      (node (ref "R91") (pin "1") (pinfunction "1_1") (pintype "passive"))
      (node (ref "U31") (pin "3") (pinfunction "B_3") (pintype "passive"))
      (node (ref "U31") (pin "4") (pinfunction "B'_4") (pintype "passive"))
    )
    (net (code "413") (name "Net-(U35-L1)") (class "Default")
      (node (ref "L11") (pin "1") (pinfunction "1_1") (pintype "passive"))
      (node (ref "U35") (pin "20") (pinfunction "L1_20") (pintype "passive"))
    )
    (net (code "414") (name "Net-(U35-L2)") (class "Default")
      (node (ref "L12") (pin "1") (pinfunction "1_1") (pintype "passive"))
      (node (ref "U35") (pin "23") (pinfunction "L2_23") (pintype "passive"))
    )
    (net (code "415") (name "Net-(U35-L3)") (class "Default")
      (node (ref "L13") (pin "1") (pinfunction "1_1") (pintype "passive"))
      (node (ref "U35") (pin "31") (pinfunction "L3_31") (pintype "passive"))
    )
    (net (code "416") (name "Net-(X2-FO)") (class "Default")
      (node (ref "R35") (pin "2") (pinfunction "2_2") (pintype "passive"))
      (node (ref "X2") (pin "3") (pinfunction "FO_3") (pintype "output"))
    )
    (net (code "417") (name "OV_RXD$12") (class "Default")
      (node (ref "J6") (pin "3") (pinfunction "3_3") (pintype "bidirectional"))
      (node (ref "U11") (pin "7") (pinfunction "B1_7") (pintype "output"))
    )
    (net (code "418") (name "OV_RXD$32") (class "Default")
      (node (ref "J11") (pin "3") (pinfunction "3_3") (pintype "bidirectional"))
      (node (ref "U27") (pin "7") (pinfunction "B1_7") (pintype "output"))
    )
    (net (code "419") (name "OV_SCL$1") (class "Default")
      (node (ref "J1") (pin "3") (pinfunction "3_3") (pintype "bidirectional"))
      (node (ref "U1") (pin "7") (pinfunction "B1_7") (pintype "output"))
    )
    (net (code "420") (name "OV_SCL$27") (class "Default")
      (node (ref "J8") (pin "3") (pinfunction "3_3") (pintype "bidirectional"))
      (node (ref "U21") (pin "7") (pinfunction "B1_7") (pintype "output"))
    )
    (net (code "421") (name "OV_SDA$1") (class "Default")
      (node (ref "J1") (pin "1") (pinfunction "1_1") (pintype "bidirectional"))
      (node (ref "U1") (pin "6") (pinfunction "B2_6") (pintype "output"))
    )
    (net (code "422") (name "OV_SDA$27") (class "Default")
      (node (ref "J8") (pin "1") (pinfunction "1_1") (pintype "bidirectional"))
      (node (ref "U21") (pin "6") (pinfunction "B2_6") (pintype "output"))
    )
    (net (code "423") (name "OV_TXD$12") (class "Default")
      (node (ref "J6") (pin "1") (pinfunction "1_1") (pintype "bidirectional"))
      (node (ref "U11") (pin "6") (pinfunction "B2_6") (pintype "output"))
    )
    (net (code "424") (name "OV_TXD$32") (class "Default")
      (node (ref "J11") (pin "1") (pinfunction "1_1") (pintype "bidirectional"))
      (node (ref "U27") (pin "6") (pinfunction "B2_6") (pintype "output"))
    )
    (net (code "425") (name "P1$37") (class "Default")
      (node (ref "J13") (pin "1") (pinfunction "1_1") (pintype "passive"))
      (node (ref "RP7") (pin "9") (pinfunction "9_9") (pintype "passive"))
      (node (ref "U29") (pin "20") (pinfunction "B1_20") (pintype "bidirectional"))
    )
    (net (code "426") (name "P2$37") (class "Default")
      (node (ref "J13") (pin "2") (pinfunction "2_2") (pintype "passive"))
      (node (ref "RP7") (pin "10") (pinfunction "10_10") (pintype "passive"))
      (node (ref "U29") (pin "18") (pinfunction "B2_18") (pintype "bidirectional"))
    )
    (net (code "427") (name "P3$37") (class "Default")
      (node (ref "J13") (pin "3") (pinfunction "3_3") (pintype "passive"))
      (node (ref "RP7") (pin "11") (pinfunction "11_11") (pintype "passive"))
      (node (ref "U29") (pin "17") (pinfunction "B3_17") (pintype "bidirectional"))
    )
    (net (code "428") (name "P4$37") (class "Default")
      (node (ref "J13") (pin "4") (pinfunction "4_4") (pintype "passive"))
      (node (ref "RP7") (pin "12") (pinfunction "12_12") (pintype "passive"))
      (node (ref "U29") (pin "16") (pinfunction "B4_16") (pintype "bidirectional"))
    )
    (net (code "429") (name "P5$37") (class "Default")
      (node (ref "J13") (pin "5") (pinfunction "5_5") (pintype "passive"))
      (node (ref "RP7") (pin "13") (pinfunction "13_13") (pintype "passive"))
      (node (ref "U29") (pin "15") (pinfunction "B5_15") (pintype "bidirectional"))
    )
    (net (code "430") (name "P6$37") (class "Default")
      (node (ref "J13") (pin "6") (pinfunction "6_6") (pintype "passive"))
      (node (ref "RP7") (pin "14") (pinfunction "14_14") (pintype "passive"))
      (node (ref "U29") (pin "14") (pinfunction "B6_14") (pintype "bidirectional"))
    )
    (net (code "431") (name "P7$37") (class "Default")
      (node (ref "J13") (pin "7") (pinfunction "7_7") (pintype "passive"))
      (node (ref "RP7") (pin "15") (pinfunction "15_15") (pintype "passive"))
      (node (ref "U29") (pin "13") (pinfunction "B7_13") (pintype "bidirectional"))
    )
    (net (code "432") (name "P8$37") (class "Default")
      (node (ref "J13") (pin "8") (pinfunction "8_8") (pintype "passive"))
      (node (ref "RP7") (pin "16") (pinfunction "16_16") (pintype "passive"))
      (node (ref "U29") (pin "12") (pinfunction "B8_12") (pintype "bidirectional"))
    )
    (net (code "433") (name "PD0$44") (class "Default")
      (node (ref "IC4") (pin "63") (pinfunction "PD0_63") (pintype "bidirectional"))
      (node (ref "R113") (pin "2") (pinfunction "2_2") (pintype "passive"))
    )
    (net (code "434") (name "PD1$44") (class "Default")
      (node (ref "IC4") (pin "62") (pinfunction "PD1_62") (pintype "bidirectional"))
      (node (ref "RP8") (pin "1") (pinfunction "1_1") (pintype "passive"))
    )
    (net (code "435") (name "PD2$44") (class "Default")
      (node (ref "IC4") (pin "61") (pinfunction "PD2_61") (pintype "bidirectional"))
      (node (ref "RP8") (pin "2") (pinfunction "2_2") (pintype "passive"))
    )
    (net (code "436") (name "PD3$44") (class "Default")
      (node (ref "IC4") (pin "60") (pinfunction "PD3_60") (pintype "bidirectional"))
      (node (ref "RP8") (pin "3") (pinfunction "3_3") (pintype "passive"))
    )
    (net (code "437") (name "PD4$44") (class "Default")
      (node (ref "IC4") (pin "59") (pinfunction "PD4_59") (pintype "bidirectional"))
      (node (ref "RP8") (pin "4") (pinfunction "4_4") (pintype "passive"))
    )
    (net (code "438") (name "PD5$44") (class "Default")
      (node (ref "IC4") (pin "58") (pinfunction "PD5_58") (pintype "bidirectional"))
      (node (ref "RP8") (pin "5") (pinfunction "5_5") (pintype "passive"))
    )
    (net (code "439") (name "PD6$44") (class "Default")
      (node (ref "IC4") (pin "55") (pinfunction "PD6_55") (pintype "bidirectional"))
      (node (ref "RP8") (pin "7") (pinfunction "7_7") (pintype "passive"))
    )
    (net (code "440") (name "PD7$44") (class "Default")
      (node (ref "IC4") (pin "54") (pinfunction "PD7_54") (pintype "bidirectional"))
      (node (ref "RP8") (pin "8") (pinfunction "8_8") (pintype "passive"))
    )
    (net (code "441") (name "PD8$44") (class "Default")
      (node (ref "IC4") (pin "53") (pinfunction "PD8_53") (pintype "bidirectional"))
      (node (ref "RP9") (pin "1") (pinfunction "1_1") (pintype "passive"))
    )
    (net (code "442") (name "PD9$44") (class "Default")
      (node (ref "IC4") (pin "52") (pinfunction "PD9_52") (pintype "bidirectional"))
      (node (ref "RP9") (pin "2") (pinfunction "2_2") (pintype "passive"))
    )
    (net (code "443") (name "PD10$44") (class "Default")
      (node (ref "IC4") (pin "51") (pinfunction "PD10_51") (pintype "bidirectional"))
      (node (ref "RP9") (pin "3") (pinfunction "3_3") (pintype "passive"))
    )
    (net (code "444") (name "PD11$44") (class "Default")
      (node (ref "IC4") (pin "50") (pinfunction "PD11_50") (pintype "bidirectional"))
      (node (ref "RP9") (pin "4") (pinfunction "4_4") (pintype "passive"))
    )
    (net (code "445") (name "PD12$44") (class "Default")
      (node (ref "IC4") (pin "47") (pinfunction "PD12_47") (pintype "bidirectional"))
      (node (ref "RP9") (pin "5") (pinfunction "5_5") (pintype "passive"))
    )
    (net (code "446") (name "PD13$44") (class "Default")
      (node (ref "IC4") (pin "46") (pinfunction "PD13_46") (pintype "bidirectional"))
      (node (ref "RP9") (pin "6") (pinfunction "6_6") (pintype "passive"))
    )
    (net (code "447") (name "PD14$44") (class "Default")
      (node (ref "IC4") (pin "45") (pinfunction "PD14_45") (pintype "bidirectional"))
      (node (ref "RP9") (pin "7") (pinfunction "7_7") (pintype "passive"))
    )
    (net (code "448") (name "PD15$44") (class "Default")
      (node (ref "IC4") (pin "44") (pinfunction "PD15_44") (pintype "bidirectional"))
      (node (ref "RP9") (pin "8") (pinfunction "8_8") (pintype "passive"))
    )
    (net (code "449") (name "PD16$44") (class "Default")
      (node (ref "IC4") (pin "43") (pinfunction "PD16_43") (pintype "bidirectional"))
      (node (ref "RP10") (pin "1") (pinfunction "1_1") (pintype "passive"))
    )
    (net (code "450") (name "PD17$44") (class "Default")
      (node (ref "IC4") (pin "42") (pinfunction "PD17_42") (pintype "bidirectional"))
      (node (ref "RP10") (pin "2") (pinfunction "2_2") (pintype "passive"))
    )
    (net (code "451") (name "PD18$44") (class "Default")
      (node (ref "IC4") (pin "41") (pinfunction "PD18_41") (pintype "bidirectional"))
      (node (ref "RP10") (pin "3") (pinfunction "3_3") (pintype "passive"))
    )
    (net (code "452") (name "PD19$44") (class "Default")
      (node (ref "IC4") (pin "40") (pinfunction "PD19_40") (pintype "bidirectional"))
      (node (ref "RP10") (pin "4") (pinfunction "4_4") (pintype "passive"))
    )
    (net (code "453") (name "PD20$44") (class "Default")
      (node (ref "IC4") (pin "39") (pinfunction "PD20_39") (pintype "bidirectional"))
      (node (ref "RP10") (pin "5") (pinfunction "5_5") (pintype "passive"))
    )
    (net (code "454") (name "PD21$44") (class "Default")
      (node (ref "IC4") (pin "38") (pinfunction "PD21_38") (pintype "bidirectional"))
      (node (ref "RP10") (pin "6") (pinfunction "6_6") (pintype "passive"))
    )
    (net (code "455") (name "PD22$44") (class "Default")
      (node (ref "IC4") (pin "37") (pinfunction "PD22_37") (pintype "bidirectional"))
      (node (ref "RP10") (pin "7") (pinfunction "7_7") (pintype "passive"))
    )
    (net (code "456") (name "PD23$44") (class "Default")
      (node (ref "IC4") (pin "36") (pinfunction "PD23_36") (pintype "bidirectional"))
      (node (ref "RP10") (pin "8") (pinfunction "8_8") (pintype "passive"))
    )
    (net (code "457") (name "PG_3.3$18") (class "Default")
      (node (ref "IC2") (pin "13") (pinfunction "PG_13") (pintype "output"))
      (node (ref "R38") (pin "1") (pinfunction "1_1") (pintype "passive"))
    )
    (net (code "458") (name "PMIC_INT$45") (class "Default")
      (node (ref "R119") (pin "1") (pinfunction "1_1") (pintype "passive"))
      (node (ref "R125") (pin "1") (pinfunction "1_1") (pintype "passive"))
      (node (ref "U35") (pin "45") (pinfunction "~{INT}_45") (pintype "open_collector"))
    )
    (net (code "459") (name "PMIC_PWR_EN$45") (class "Default")
      (node (ref "U$72") (pin "C6") (pinfunction "PMIC_POWER_EN_C6") (pintype "output"))
      (node (ref "U35") (pin "9") (pinfunction "PWR_EN_9") (pintype "input"))
    )
    (net (code "460") (name "PMIC_WAKEUP$45") (class "Default")
      (node (ref "R124") (pin "1") (pinfunction "1_1") (pintype "passive"))
      (node (ref "U$72") (pin "C5") (pinfunction "EXT_WAKEUP_C5") (pintype "input"))
      (node (ref "U35") (pin "13") (pinfunction "~{WAKEUP}_13") (pintype "open_collector"))
    )
    (net (code "461") (name "PVDD$44") (class "Default")
      (node (ref "C153") (pin "1") (pinfunction "1_1") (pintype "passive"))
      (node (ref "C159") (pin "1") (pinfunction "1_1") (pintype "passive"))
      (node (ref "FB8") (pin "2") (pinfunction "2_2") (pintype "passive"))
      (node (ref "IC4") (pin "18") (pinfunction "VDD_18") (pintype "power_in"))
    )
    (net (code "462") (name "PWM_1_5V$2") (class "Default")
      (node (ref "J2") (pin "B3") (pinfunction "B3_B3") (pintype "bidirectional"))
      (node (ref "U2") (pin "7") (pinfunction "B1_7") (pintype "output"))
    )
    (net (code "463") (name "PWM_1_5V$28") (class "Default")
      (node (ref "J9") (pin "B3") (pinfunction "B3_B3") (pintype "bidirectional"))
      (node (ref "U22") (pin "7") (pinfunction "B1_7") (pintype "output"))
    )
    (net (code "464") (name "PWM_2_5V$2") (class "Default")
      (node (ref "J2") (pin "A3") (pinfunction "A3_A3") (pintype "bidirectional"))
      (node (ref "U2") (pin "6") (pinfunction "B2_6") (pintype "output"))
    )
    (net (code "465") (name "PWM_2_5V$28") (class "Default")
      (node (ref "J9") (pin "A3") (pinfunction "A3_A3") (pintype "bidirectional"))
      (node (ref "U22") (pin "6") (pinfunction "B2_6") (pintype "output"))
    )
    (net (code "466") (name "RED0$43") (class "Default")
      (node (ref "U$68") (pin "26") (pinfunction "2A7_26") (pintype "bidirectional"))
      (node (ref "U$70") (pin "5") (pinfunction "R0_5") (pintype "output"))
    )
    (net (code "467") (name "RED1$43") (class "Default")
      (node (ref "U$68") (pin "27") (pinfunction "2A6_27") (pintype "bidirectional"))
      (node (ref "U$70") (pin "6") (pinfunction "R1_6") (pintype "output"))
    )
    (net (code "468") (name "RED2$43") (class "Default")
      (node (ref "U$68") (pin "29") (pinfunction "2A5_29") (pintype "bidirectional"))
      (node (ref "U$70") (pin "7") (pinfunction "R2_7") (pintype "output"))
    )
    (net (code "469") (name "RED3$43") (class "Default")
      (node (ref "U$68") (pin "30") (pinfunction "2A4_30") (pintype "bidirectional"))
      (node (ref "U$70") (pin "8") (pinfunction "R3_8") (pintype "output"))
    )
    (net (code "470") (name "RED4$43") (class "Default")
      (node (ref "U$68") (pin "32") (pinfunction "2A3_32") (pintype "bidirectional"))
      (node (ref "U$70") (pin "9") (pinfunction "R4_9") (pintype "output"))
    )
    (net (code "471") (name "RED5$43") (class "Default")
      (node (ref "U$68") (pin "33") (pinfunction "2A2_33") (pintype "bidirectional"))
      (node (ref "U$70") (pin "10") (pinfunction "R5_10") (pintype "output"))
    )
    (net (code "472") (name "RED6$43") (class "Default")
      (node (ref "U$68") (pin "35") (pinfunction "2A1_35") (pintype "bidirectional"))
      (node (ref "U$70") (pin "11") (pinfunction "R6_11") (pintype "output"))
    )
    (net (code "473") (name "RED7$43") (class "Default")
      (node (ref "U$68") (pin "36") (pinfunction "2A0_36") (pintype "bidirectional"))
      (node (ref "U$70") (pin "12") (pinfunction "R7_12") (pintype "output"))
    )
    (net (code "474") (name "RTC_XTAL_IN$45") (class "Default")
      (node (ref "C170") (pin "1") (pinfunction "1_1") (pintype "passive"))
      (node (ref "U$72") (pin "A6") (pinfunction "RTC_XTALIN_A6") (pintype "input"))
      (node (ref "Y4") (pin "2") (pinfunction "2_2") (pintype "passive"))
    )
    (net (code "475") (name "RTC_XTAL_OUT$45") (class "Default")
      (node (ref "C171") (pin "1") (pinfunction "1_1") (pintype "passive"))
      (node (ref "R118") (pin "2") (pinfunction "2_2") (pintype "passive"))
      (node (ref "U$72") (pin "A4") (pinfunction "RTC_XTALOUT_A4") (pintype "output"))
    )
    (net (code "476") (name "SDIO2_CLK$33") (class "Default")
      (node (ref "RP6") (pin "7") (pinfunction "7_7") (pintype "passive"))
      (node (ref "U28") (pin "8") (pinfunction "WL_SDIO_CLK_8") (pintype "bidirectional"))
    )
    (net (code "477") (name "SDIO2_CMD$33") (class "Default")
      (node (ref "RP6") (pin "8") (pinfunction "8_8") (pintype "passive"))
      (node (ref "U28") (pin "6") (pinfunction "WL_SDIO_CMD_6") (pintype "bidirectional"))
    )
    (net (code "478") (name "SDIO2_DAT0$33") (class "Default")
      (node (ref "RP6") (pin "5") (pinfunction "5_5") (pintype "passive"))
      (node (ref "U28") (pin "10") (pinfunction "WL_SDIO_D0_10") (pintype "bidirectional"))
    )
    (net (code "479") (name "SDIO2_DAT1$33") (class "Default")
      (node (ref "RP6") (pin "4") (pinfunction "4_4") (pintype "passive"))
      (node (ref "U28") (pin "11") (pinfunction "WL_SDIO_D1_11") (pintype "bidirectional"))
    )
    (net (code "480") (name "SDIO2_DAT2$33") (class "Default")
      (node (ref "RP6") (pin "2") (pinfunction "2_2") (pintype "passive"))
      (node (ref "U28") (pin "12") (pinfunction "WL_SDIO_D2_12") (pintype "bidirectional"))
    )
    (net (code "481") (name "SDIO2_DAT3$33") (class "Default")
      (node (ref "RP6") (pin "1") (pinfunction "1_1") (pintype "passive"))
      (node (ref "U28") (pin "13") (pinfunction "WL_SDIO_D3_13") (pintype "bidirectional"))
    )
    (net (code "482") (name "SQW$5") (class "Default")
      (node (ref "R3") (pin "1") (pinfunction "1_1") (pintype "passive"))
      (node (ref "U3") (pin "7") (pinfunction "SQW_7") (pintype "output"))
    )
    (net (code "483") (name "SW_3.3$18") (class "Default")
      (node (ref "IC2") (pin "14") (pinfunction "SW_14") (pintype "input"))
      (node (ref "IC2") (pin "15") (pinfunction "SW_15") (pintype "input"))
      (node (ref "L1") (pin "1") (pinfunction "1_1") (pintype "passive"))
    )
    (net (code "484") (name "TCK$39") (class "Default")
      (node (ref "IC3") (pin "76") (pinfunction "PA14_76") (pintype "bidirectional"))
      (node (ref "JTAG") (pin "4") (pinfunction "S_4") (pintype "passive"))
      (node (ref "R111") (pin "1") (pinfunction "1_1") (pintype "passive"))
    )
    (net (code "485") (name "TDI$39") (class "Default")
      (node (ref "IC3") (pin "77") (pinfunction "PA15_77") (pintype "bidirectional"))
      (node (ref "JTAG") (pin "8") (pinfunction "S_8") (pintype "passive"))
      (node (ref "R137") (pin "1") (pinfunction "1_1") (pintype "passive"))
    )
    (net (code "486") (name "TDO$39") (class "Default")
      (node (ref "IC3") (pin "89") (pinfunction "PB3_89") (pintype "bidirectional"))
      (node (ref "JTAG") (pin "6") (pinfunction "S_6") (pintype "passive"))
      (node (ref "R136") (pin "1") (pinfunction "1_1") (pintype "passive"))
    )
    (net (code "487") (name "TFADJ$44") (class "Default")
      (node (ref "IC4") (pin "19") (pinfunction "TFADJ_19") (pintype "bidirectional"))
      (node (ref "R102") (pin "1") (pinfunction "1_1") (pintype "passive"))
    )
    (net (code "488") (name "TMS$39") (class "Default")
      (node (ref "IC3") (pin "72") (pinfunction "PA13_72") (pintype "bidirectional"))
      (node (ref "JTAG") (pin "2") (pinfunction "S_2") (pintype "passive"))
      (node (ref "R63") (pin "1") (pinfunction "1_1") (pintype "passive"))
    )
    (net (code "489") (name "TSMX$43") (class "Default")
      (node (ref "U$66") (pin "8") (pinfunction "X-_8") (pintype "bidirectional"))
      (node (ref "U$70") (pin "39") (pinfunction "XL_39") (pintype "output"))
    )
    (net (code "490") (name "TSMY$43") (class "Default")
      (node (ref "U$66") (pin "9") (pinfunction "Y-_9") (pintype "bidirectional"))
      (node (ref "U$70") (pin "38") (pinfunction "YD_38") (pintype "output"))
    )
    (net (code "491") (name "TSPX$43") (class "Default")
      (node (ref "U$66") (pin "6") (pinfunction "X+_6") (pintype "bidirectional"))
      (node (ref "U$70") (pin "37") (pinfunction "XR_37") (pintype "output"))
    )
    (net (code "492") (name "TSPY$43") (class "Default")
      (node (ref "U$66") (pin "7") (pinfunction "Y+_7") (pintype "bidirectional"))
      (node (ref "U$70") (pin "40") (pinfunction "YU_40") (pintype "output"))
    )
    (net (code "493") (name "TVDD$44") (class "Default")
      (node (ref "C154") (pin "1") (pinfunction "1_1") (pintype "passive"))
      (node (ref "C160") (pin "1") (pinfunction "1_1") (pintype "passive"))
      (node (ref "C163") (pin "1") (pinfunction "1_1") (pintype "passive"))
      (node (ref "FB7") (pin "2") (pinfunction "2_2") (pintype "passive"))
      (node (ref "IC4") (pin "23") (pinfunction "VDD_23") (pintype "power_in"))
      (node (ref "IC4") (pin "29") (pinfunction "VDD_29") (pintype "power_in"))
      (node (ref "R102") (pin "2") (pinfunction "2_2") (pintype "passive"))
    )
    (net (code "494") (name "TXC+$44") (class "Default")
      (node (ref "IC4") (pin "22") (pinfunction "TXC+_22") (pintype "bidirectional"))
      (node (ref "L10") (pin "1") (pinfunction "1_1") (pintype "passive"))
    )
    (net (code "495") (name "TXC-$44") (class "Default")
      (node (ref "IC4") (pin "21") (pinfunction "TXC-_21") (pintype "bidirectional"))
      (node (ref "L10") (pin "4") (pinfunction "4_4") (pintype "passive"))
    )
    (net (code "496") (name "TXD0+$44") (class "Default")
      (node (ref "IC4") (pin "25") (pinfunction "TXD0+_25") (pintype "bidirectional"))
      (node (ref "L9") (pin "1") (pinfunction "1_1") (pintype "passive"))
    )
    (net (code "497") (name "TXD0-$44") (class "Default")
      (node (ref "IC4") (pin "24") (pinfunction "TXD0-_24") (pintype "bidirectional"))
      (node (ref "L9") (pin "4") (pinfunction "4_4") (pintype "passive"))
    )
    (net (code "498") (name "TXD1+$44") (class "Default")
      (node (ref "IC4") (pin "28") (pinfunction "TXD1+_28") (pintype "bidirectional"))
      (node (ref "L8") (pin "1") (pinfunction "1_1") (pintype "passive"))
    )
    (net (code "499") (name "TXD1-$44") (class "Default")
      (node (ref "IC4") (pin "27") (pinfunction "TXD1-_27") (pintype "bidirectional"))
      (node (ref "L8") (pin "4") (pinfunction "4_4") (pintype "passive"))
    )
    (net (code "500") (name "TXD2+$44") (class "Default")
      (node (ref "IC4") (pin "31") (pinfunction "TXD2+_31") (pintype "bidirectional"))
      (node (ref "L7") (pin "1") (pinfunction "1_1") (pintype "passive"))
    )
    (net (code "501") (name "TXD2-$44") (class "Default")
      (node (ref "IC4") (pin "30") (pinfunction "TXD2-_30") (pintype "bidirectional"))
      (node (ref "L7") (pin "4") (pinfunction "4_4") (pintype "passive"))
    )
    (net (code "502") (name "USB_CRFILT$20") (class "Default")
      (node (ref "C70") (pin "1") (pinfunction "1_1") (pintype "passive"))
      (node (ref "C71") (pin "1") (pinfunction "1_1") (pintype "passive"))
      (node (ref "U18") (pin "14") (pinfunction "CRFILT_14") (pintype "passive"))
    )
    (net (code "503") (name "USB_HS_IND$20") (class "Default")
      (node (ref "R48") (pin "2") (pinfunction "2_2") (pintype "passive"))
      (node (ref "U18") (pin "25") (pinfunction "HS_IND/CFG_SEL1_25") (pintype "passive"))
    )
    (net (code "504") (name "USB_NRESET$20") (class "Default")
      (node (ref "C74") (pin "1") (pinfunction "1_1") (pintype "passive"))
      (node (ref "R45") (pin "1") (pinfunction "1_1") (pintype "passive"))
      (node (ref "U18") (pin "26") (pinfunction "RESET_N_26") (pintype "passive"))
    )
    (net (code "505") (name "USB_PLLFILT$20") (class "Default")
      (node (ref "C72") (pin "1") (pinfunction "1_1") (pintype "passive"))
      (node (ref "C73") (pin "1") (pinfunction "1_1") (pintype "passive"))
      (node (ref "U18") (pin "34") (pinfunction "PLLFILT_34") (pintype "passive"))
    )
    (net (code "506") (name "USB_RBIAS$20") (class "Default")
      (node (ref "R46") (pin "2") (pinfunction "2_2") (pintype "passive"))
      (node (ref "U18") (pin "35") (pinfunction "RBIAS_35") (pintype "passive"))
    )
    (net (code "507") (name "USB_SCL$20") (class "Default")
      (node (ref "R47") (pin "2") (pinfunction "2_2") (pintype "passive"))
      (node (ref "U18") (pin "24") (pinfunction "SCL/CFG_SEL0_24") (pintype "passive"))
    )
    (net (code "508") (name "USB_SDA$20") (class "Default")
      (node (ref "R50") (pin "2") (pinfunction "2_2") (pintype "passive"))
      (node (ref "U18") (pin "22") (pinfunction "SDA/NON_REM1_22") (pintype "passive"))
    )
    (net (code "509") (name "USB_SUSP_IND$20") (class "Default")
      (node (ref "R49") (pin "2") (pinfunction "2_2") (pintype "passive"))
      (node (ref "U18") (pin "28") (pinfunction "SUSP_IND/NON_REM0_28") (pintype "passive"))
    )
    (net (code "510") (name "USB_XTAL1$20") (class "Default")
      (node (ref "C84") (pin "1") (pinfunction "1_1") (pintype "passive"))
      (node (ref "R51") (pin "2") (pinfunction "2_2") (pintype "passive"))
      (node (ref "U18") (pin "33") (pinfunction "XTALIN_33") (pintype "passive"))
      (node (ref "Y1") (pin "3") (pinfunction "3_3") (pintype "passive"))
    )
    (net (code "511") (name "USB_XTAL2$20") (class "Default")
      (node (ref "C83") (pin "1") (pinfunction "1_1") (pintype "passive"))
      (node (ref "R51") (pin "1") (pinfunction "1_1") (pintype "passive"))
      (node (ref "U18") (pin "32") (pinfunction "XTALOUT_32") (pintype "passive"))
      (node (ref "Y1") (pin "1") (pinfunction "1_1") (pintype "passive"))
    )
    (net (code "512") (name "VBACKUP$5") (class "Default")
      (node (ref "J3") (pin "+1") (pinfunction "+1_+1") (pintype "passive"))
      (node (ref "J3") (pin "+2") (pinfunction "+2_+2") (pintype "passive"))
      (node (ref "U3") (pin "3") (pinfunction "VBAT_3") (pintype "power_in"))
    )
    (net (code "513") (name "VBAT$39") (class "Default")
      (node (ref "IC3") (pin "6") (pinfunction "VBAT_6") (pintype "power_in"))
      (node (ref "R90") (pin "2") (pinfunction "2_2") (pintype "passive"))
    )
    (net (code "514") (name "VCC_5.0$38") (class "Default")
      (node (ref "C120") (pin "1") (pinfunction "1_1") (pintype "passive"))
      (node (ref "D19") (pin "P2") (pinfunction "P2_P2") (pintype "passive"))
      (node (ref "J14") (pin "P1") (pinfunction "VBUS_P1") (pintype "bidirectional"))
      (node (ref "R82") (pin "2") (pinfunction "2_2") (pintype "passive"))
    )
    (net (code "515") (name "VDDA$39") (class "Default")
      (node (ref "C133") (pin "1") (pinfunction "1_1") (pintype "passive"))
      (node (ref "C134") (pin "1") (pinfunction "1_1") (pintype "passive"))
      (node (ref "FB9") (pin "1") (pinfunction "1_1") (pintype "passive"))
      (node (ref "IC3") (pin "22") (pinfunction "VDDA_22") (pintype "power_in"))
      (node (ref "R84") (pin "2") (pinfunction "2_2") (pintype "passive"))
    )
    (net (code "516") (name "VDDS_DDR$45") (class "Default")
      (node (ref "C198") (pin "1") (pinfunction "1_1") (pintype "passive"))
      (node (ref "C207") (pin "1") (pinfunction "1_1") (pintype "passive"))
      (node (ref "C208") (pin "1") (pinfunction "1_1") (pintype "passive"))
      (node (ref "C209") (pin "1") (pinfunction "1_1") (pintype "passive"))
      (node (ref "C210") (pin "1") (pinfunction "1_1") (pintype "passive"))
      (node (ref "C211") (pin "1") (pinfunction "1_1") (pintype "passive"))
      (node (ref "C212") (pin "1") (pinfunction "1_1") (pintype "passive"))
      (node (ref "C228") (pin "1") (pinfunction "1_1") (pintype "passive"))
      (node (ref "C252") (pin "1") (pinfunction "1_1") (pintype "passive"))
      (node (ref "C253") (pin "1") (pinfunction "1_1") (pintype "passive"))
      (node (ref "C254") (pin "1") (pinfunction "1_1") (pintype "passive"))
      (node (ref "C255") (pin "1") (pinfunction "1_1") (pintype "passive"))
      (node (ref "C258") (pin "1") (pinfunction "1_1") (pintype "passive"))
      (node (ref "C259") (pin "1") (pinfunction "1_1") (pintype "passive"))
      (node (ref "C260") (pin "1") (pinfunction "1_1") (pintype "passive"))
      (node (ref "C261") (pin "1") (pinfunction "1_1") (pintype "passive"))
      (node (ref "C262") (pin "1") (pinfunction "1_1") (pintype "passive"))
      (node (ref "L11") (pin "2") (pinfunction "2_2") (pintype "passive"))
      (node (ref "R131") (pin "1") (pinfunction "1_1") (pintype "passive"))
      (node (ref "R134") (pin "1") (pinfunction "1_1") (pintype "passive"))
      (node (ref "U$101") (pin "A1") (pinfunction "VDDQ_A1") (pintype "power_in"))
      (node (ref "U$101") (pin "A8") (pinfunction "VDDQ_A8") (pintype "power_in"))
      (node (ref "U$101") (pin "B2") (pinfunction "VDD_B2") (pintype "power_in"))
      (node (ref "U$101") (pin "C1") (pinfunction "VDDQ_C1") (pintype "power_in"))
      (node (ref "U$101") (pin "C9") (pinfunction "VDDQ_C9") (pintype "power_in"))
      (node (ref "U$101") (pin "D2") (pinfunction "VDDQ_D2") (pintype "power_in"))
      (node (ref "U$101") (pin "D9") (pinfunction "VDD_D9") (pintype "power_in"))
      (node (ref "U$101") (pin "E9") (pinfunction "VDDQ_E9") (pintype "power_in"))
      (node (ref "U$101") (pin "F1") (pinfunction "VDDQ_F1") (pintype "power_in"))
      (node (ref "U$101") (pin "G7") (pinfunction "VDD_G7") (pintype "power_in"))
      (node (ref "U$101") (pin "H2") (pinfunction "VDDQ_H2") (pintype "power_in"))
      (node (ref "U$101") (pin "H9") (pinfunction "VDDQ_H9") (pintype "power_in"))
      (node (ref "U$101") (pin "K2") (pinfunction "VDD_K2") (pintype "power_in"))
      (node (ref "U$101") (pin "K8") (pinfunction "VDD_K8") (pintype "power_in"))
      (node (ref "U$101") (pin "N1") (pinfunction "VDD_N1") (pintype "power_in"))
      (node (ref "U$101") (pin "N9") (pinfunction "VDD_N9") (pintype "power_in"))
      (node (ref "U$101") (pin "R1") (pinfunction "VDD_R1") (pintype "power_in"))
      (node (ref "U$101") (pin "R9") (pinfunction "VDD_R9") (pintype "power_in"))
      (node (ref "U$72") (pin "E5") (pinfunction "VDDS_DDR_E5") (pintype "power_in"))
      (node (ref "U$72") (pin "F5") (pinfunction "VDDS_DDR_F5") (pintype "power_in"))
      (node (ref "U$72") (pin "G5") (pinfunction "VDDS_DDR_G5") (pintype "power_in"))
      (node (ref "U$72") (pin "H5") (pinfunction "VDDS_DDR_H5") (pintype "power_in"))
      (node (ref "U$72") (pin "J5") (pinfunction "VDDS_DDR_J5") (pintype "power_in"))
      (node (ref "U$72") (pin "K5") (pinfunction "VDDS_DDR_K5") (pintype "power_in"))
      (node (ref "U$72") (pin "L5") (pinfunction "VDDS_DDR_L5") (pintype "power_in"))
      (node (ref "U35") (pin "19") (pinfunction "VDCDC1_19") (pintype "input"))
    )
    (net (code "517") (name "VDD_1V8$45") (class "Default")
      (node (ref "C172") (pin "1") (pinfunction "1_1") (pintype "passive"))
      (node (ref "C176") (pin "1") (pinfunction "1_1") (pintype "passive"))
      (node (ref "C177") (pin "1") (pinfunction "1_1") (pintype "passive"))
      (node (ref "C178") (pin "1") (pinfunction "1_1") (pintype "passive"))
      (node (ref "C179") (pin "1") (pinfunction "1_1") (pintype "passive"))
      (node (ref "C180") (pin "1") (pinfunction "1_1") (pintype "passive"))
      (node (ref "C181") (pin "1") (pinfunction "1_1") (pintype "passive"))
      (node (ref "C182") (pin "1") (pinfunction "1_1") (pintype "passive"))
      (node (ref "C183") (pin "1") (pinfunction "1_1") (pintype "passive"))
      (node (ref "C184") (pin "1") (pinfunction "1_1") (pintype "passive"))
      (node (ref "C185") (pin "1") (pinfunction "1_1") (pintype "passive"))
      (node (ref "C186") (pin "1") (pinfunction "1_1") (pintype "passive"))
      (node (ref "C187") (pin "1") (pinfunction "1_1") (pintype "passive"))
      (node (ref "C188") (pin "1") (pinfunction "1_1") (pintype "passive"))
      (node (ref "C189") (pin "1") (pinfunction "1_1") (pintype "passive"))
      (node (ref "C190") (pin "1") (pinfunction "1_1") (pintype "passive"))
      (node (ref "C191") (pin "1") (pinfunction "1_1") (pintype "passive"))
      (node (ref "C192") (pin "1") (pinfunction "1_1") (pintype "passive"))
      (node (ref "C193") (pin "1") (pinfunction "1_1") (pintype "passive"))
      (node (ref "C196") (pin "1") (pinfunction "1_1") (pintype "passive"))
      (node (ref "C197") (pin "1") (pinfunction "1_1") (pintype "passive"))
      (node (ref "C201") (pin "1") (pinfunction "1_1") (pintype "passive"))
      (node (ref "C202") (pin "1") (pinfunction "1_1") (pintype "passive"))
      (node (ref "C203") (pin "1") (pinfunction "1_1") (pintype "passive"))
      (node (ref "C204") (pin "1") (pinfunction "1_1") (pintype "passive"))
      (node (ref "C205") (pin "1") (pinfunction "1_1") (pintype "passive"))
      (node (ref "C213") (pin "1") (pinfunction "1_1") (pintype "passive"))
      (node (ref "C214") (pin "1") (pinfunction "1_1") (pintype "passive"))
      (node (ref "C215") (pin "1") (pinfunction "1_1") (pintype "passive"))
      (node (ref "C216") (pin "1") (pinfunction "1_1") (pintype "passive"))
      (node (ref "C217") (pin "1") (pinfunction "1_1") (pintype "passive"))
      (node (ref "C218") (pin "1") (pinfunction "1_1") (pintype "passive"))
      (node (ref "C220") (pin "1") (pinfunction "1_1") (pintype "passive"))
      (node (ref "C232") (pin "1") (pinfunction "1_1") (pintype "passive"))
      (node (ref "FB12") (pin "1") (pinfunction "1_1") (pintype "passive"))
      (node (ref "R122") (pin "2") (pinfunction "2_2") (pintype "passive"))
      (node (ref "R123") (pin "2") (pinfunction "2_2") (pintype "passive"))
      (node (ref "R126") (pin "2") (pinfunction "2_2") (pintype "passive"))
      (node (ref "R127") (pin "2") (pinfunction "2_2") (pintype "passive"))
      (node (ref "R128") (pin "2") (pinfunction "2_2") (pintype "passive"))
      (node (ref "R130") (pin "2") (pinfunction "2_2") (pintype "passive"))
      (node (ref "U$72") (pin "D10") (pinfunction "VDDS_SRAM_MPU_BB_D10") (pintype "power_in"))
      (node (ref "U$72") (pin "E10") (pinfunction "VDDSHV6_E10") (pintype "power_in"))
      (node (ref "U$72") (pin "E11") (pinfunction "VDDSHV6_E11") (pintype "power_in"))
      (node (ref "U$72") (pin "E12") (pinfunction "VDDSHV6_E12") (pintype "power_in"))
      (node (ref "U$72") (pin "E13") (pinfunction "VDDSHV6_E13") (pintype "power_in"))
      (node (ref "U$72") (pin "E14") (pinfunction "VDDS_E14") (pintype "power_in"))
      (node (ref "U$72") (pin "E6") (pinfunction "VDDS_E6") (pintype "power_in"))
      (node (ref "U$72") (pin "E7") (pinfunction "VDDS_PLL_DDR_E7") (pintype "power_in"))
      (node (ref "U$72") (pin "E9") (pinfunction "VDDS_SRAM_CORE_BG_E9") (pintype "power_in"))
      (node (ref "U$72") (pin "F14") (pinfunction "VDDSHV6_F14") (pintype "power_in"))
      (node (ref "U$72") (pin "F9") (pinfunction "VDDS_F9") (pintype "power_in"))
      (node (ref "U$72") (pin "G14") (pinfunction "VDDSHV6_G14") (pintype "power_in"))
      (node (ref "U$72") (pin "H15") (pinfunction "VDDS_PLL_MPU_H15") (pintype "power_in"))
      (node (ref "U$72") (pin "K13") (pinfunction "VDDS_K13") (pintype "power_in"))
      (node (ref "U$72") (pin "K14") (pinfunction "VDDSHV5_K14") (pintype "power_in"))
      (node (ref "U$72") (pin "L14") (pinfunction "VDDSHV5_L14") (pintype "power_in"))
      (node (ref "U$72") (pin "N16") (pinfunction "VDDA1P8V_USB0_N16") (pintype "power_in"))
      (node (ref "U$72") (pin "N5") (pinfunction "VDDSHV6_N5") (pintype "power_in"))
      (node (ref "U$72") (pin "N6") (pinfunction "VDDS_N6") (pintype "power_in"))
      (node (ref "U$72") (pin "P10") (pinfunction "VDDSHV2_P10") (pintype "power_in"))
      (node (ref "U$72") (pin "P11") (pinfunction "VDDSHV2_P11") (pintype "power_in"))
      (node (ref "U$72") (pin "P12") (pinfunction "VDDSHV3_P12") (pintype "power_in"))
      (node (ref "U$72") (pin "P13") (pinfunction "VDDSHV3_P13") (pintype "power_in"))
      (node (ref "U$72") (pin "P14") (pinfunction "VDDS_P14") (pintype "power_in"))
      (node (ref "U$72") (pin "P5") (pinfunction "VDDSHV6_P5") (pintype "power_in"))
      (node (ref "U$72") (pin "P6") (pinfunction "VDDSHV6_P6") (pintype "power_in"))
      (node (ref "U$72") (pin "P7") (pinfunction "VDDSHV1_P7") (pintype "power_in"))
      (node (ref "U$72") (pin "P8") (pinfunction "VDDSHV1_P8") (pintype "power_in"))
      (node (ref "U$72") (pin "P9") (pinfunction "VDDS_P9") (pintype "power_in"))
      (node (ref "U$72") (pin "R10") (pinfunction "VDDS_PLL_CORE_LCD_R10") (pintype "power_in"))
      (node (ref "U$72") (pin "R11") (pinfunction "VDDS_OSC_R11") (pintype "power_in"))
      (node (ref "U$72") (pin "R16") (pinfunction "VDDA1P8V_USB1_R16") (pintype "power_in"))
      (node (ref "U$79") (pin "P1") (pinfunction "P$1_P1") (pintype "bidirectional"))
      (node (ref "U$79") (pin "P2") (pinfunction "P$2_P2") (pintype "bidirectional"))
      (node (ref "U$79") (pin "P3") (pinfunction "P$3_P3") (pintype "bidirectional"))
      (node (ref "U$80") (pin "P1") (pinfunction "P$1_P1") (pintype "bidirectional"))
      (node (ref "U$80") (pin "P2") (pinfunction "P$2_P2") (pintype "bidirectional"))
      (node (ref "U$80") (pin "P3") (pinfunction "P$3_P3") (pintype "bidirectional"))
      (node (ref "U$81") (pin "P1") (pinfunction "P$1_P1") (pintype "bidirectional"))
      (node (ref "U$82") (pin "P3") (pinfunction "P$3_P3") (pintype "bidirectional"))
      (node (ref "U34") (pin "8") (pinfunction "VCC_8") (pintype "power_in"))
      (node (ref "U35") (pin "40") (pinfunction "LS1_OUT_40") (pintype "output"))
    )
    (net (code "518") (name "VDD_3V3$45") (class "Default")
      (node (ref "C173") (pin "1") (pinfunction "1_1") (pintype "passive"))
      (node (ref "C194") (pin "1") (pinfunction "1_1") (pintype "passive"))
      (node (ref "C195") (pin "1") (pinfunction "1_1") (pintype "passive"))
      (node (ref "C199") (pin "1") (pinfunction "1_1") (pintype "passive"))
      (node (ref "C200") (pin "1") (pinfunction "1_1") (pintype "passive"))
      (node (ref "C206") (pin "1") (pinfunction "1_1") (pintype "passive"))
      (node (ref "C233") (pin "1") (pinfunction "1_1") (pintype "passive"))
      (node (ref "U$72") (pin "H14") (pinfunction "VDDSHV4_H14") (pintype "power_in"))
      (node (ref "U$72") (pin "J14") (pinfunction "VDDSHV4_J14") (pintype "power_in"))
      (node (ref "U$72") (pin "N15") (pinfunction "VDDA3P3V_USB0_N15") (pintype "power_in"))
      (node (ref "U$72") (pin "R15") (pinfunction "VDDA3P3V_USB1_R15") (pintype "power_in"))
      (node (ref "U35") (pin "43") (pinfunction "LS2_OUT_43") (pintype "output"))
    )
    (net (code "519") (name "VDD_CORE$45") (class "Default")
      (node (ref "C230") (pin "1") (pinfunction "1_1") (pintype "passive"))
      (node (ref "C238") (pin "1") (pinfunction "1_1") (pintype "passive"))
      (node (ref "C239") (pin "1") (pinfunction "1_1") (pintype "passive"))
      (node (ref "C240") (pin "1") (pinfunction "1_1") (pintype "passive"))
      (node (ref "C241") (pin "1") (pinfunction "1_1") (pintype "passive"))
      (node (ref "C242") (pin "1") (pinfunction "1_1") (pintype "passive"))
      (node (ref "C243") (pin "1") (pinfunction "1_1") (pintype "passive"))
      (node (ref "C244") (pin "1") (pinfunction "1_1") (pintype "passive"))
      (node (ref "C245") (pin "1") (pinfunction "1_1") (pintype "passive"))
      (node (ref "L13") (pin "2") (pinfunction "2_2") (pintype "passive"))
      (node (ref "U$72") (pin "F6") (pinfunction "VDD_CORE_F6") (pintype "power_in"))
      (node (ref "U$72") (pin "F7") (pinfunction "VDD_CORE_F7") (pintype "power_in"))
      (node (ref "U$72") (pin "G10") (pinfunction "VDD_CORE_G10") (pintype "power_in"))
      (node (ref "U$72") (pin "G6") (pinfunction "VDD_CORE_G6") (pintype "power_in"))
      (node (ref "U$72") (pin "G7") (pinfunction "VDD_CORE_G7") (pintype "power_in"))
      (node (ref "U$72") (pin "H11") (pinfunction "VDD_CORE_H11") (pintype "power_in"))
      (node (ref "U$72") (pin "J12") (pinfunction "VDD_CORE_J12") (pintype "power_in"))
      (node (ref "U$72") (pin "K12") (pinfunction "VDD_CORE_K12") (pintype "power_in"))
      (node (ref "U$72") (pin "K6") (pinfunction "VDD_CORE_K6") (pintype "power_in"))
      (node (ref "U$72") (pin "K8") (pinfunction "VDD_CORE_K8") (pintype "power_in"))
      (node (ref "U$72") (pin "L6") (pinfunction "VDD_CORE_L6") (pintype "power_in"))
      (node (ref "U$72") (pin "L7") (pinfunction "VDD_CORE_L7") (pintype "power_in"))
      (node (ref "U$72") (pin "L8") (pinfunction "VDD_CORE_L8") (pintype "power_in"))
      (node (ref "U$72") (pin "L9") (pinfunction "VDD_CORE_L9") (pintype "power_in"))
      (node (ref "U$72") (pin "M11") (pinfunction "VDD_CORE_M11") (pintype "power_in"))
      (node (ref "U$72") (pin "M13") (pinfunction "VDD_CORE_M13") (pintype "power_in"))
      (node (ref "U$72") (pin "N12") (pinfunction "VDD_CORE_N12") (pintype "power_in"))
      (node (ref "U$72") (pin "N13") (pinfunction "VDD_CORE_N13") (pintype "power_in"))
      (node (ref "U$72") (pin "N8") (pinfunction "VDD_CORE_N8") (pintype "power_in"))
      (node (ref "U$72") (pin "N9") (pinfunction "VDD_CORE_N9") (pintype "power_in"))
      (node (ref "U35") (pin "29") (pinfunction "VDCDC3_29") (pintype "input"))
    )
    (net (code "520") (name "VDD_MPU$45") (class "Default")
      (node (ref "C231") (pin "1") (pinfunction "1_1") (pintype "passive"))
      (node (ref "C246") (pin "1") (pinfunction "1_1") (pintype "passive"))
      (node (ref "C247") (pin "1") (pinfunction "1_1") (pintype "passive"))
      (node (ref "C248") (pin "1") (pinfunction "1_1") (pintype "passive"))
      (node (ref "C249") (pin "1") (pinfunction "1_1") (pintype "passive"))
      (node (ref "C250") (pin "1") (pinfunction "1_1") (pintype "passive"))
      (node (ref "L12") (pin "2") (pinfunction "2_2") (pintype "passive"))
      (node (ref "U$72") (pin "F10") (pinfunction "VDD_MPU_F10") (pintype "power_in"))
      (node (ref "U$72") (pin "F11") (pinfunction "VDD_MPU_F11") (pintype "power_in"))
      (node (ref "U$72") (pin "F12") (pinfunction "VDD_MPU_F12") (pintype "power_in"))
      (node (ref "U$72") (pin "F13") (pinfunction "VDD_MPU_F13") (pintype "power_in"))
      (node (ref "U$72") (pin "G13") (pinfunction "VDD_MPU_G13") (pintype "power_in"))
      (node (ref "U$72") (pin "H13") (pinfunction "VDD_MPU_H13") (pintype "power_in"))
      (node (ref "U$72") (pin "J13") (pinfunction "VDD_MPU_J13") (pintype "power_in"))
      (node (ref "U35") (pin "24") (pinfunction "VDCDC2_24") (pintype "input"))
    )
    (net (code "521") (name "VLDO2$45") (class "Default")
      (node (ref "C236") (pin "1") (pinfunction "1_1") (pintype "passive"))
      (node (ref "U35") (pin "1") (pinfunction "VLDO2_1") (pintype "output"))
    )
    (net (code "522") (name "VPP") (class "Default")
      (node (ref "U$72") (pin "M5") (pinfunction "VPP_M5") (pintype "power_in"))
    )
    (net (code "523") (name "VREF$43") (class "Default")
      (node (ref "C145") (pin "1") (pinfunction "1_1") (pintype "passive"))
      (node (ref "U$66") (pin "13") (pinfunction "VREF_13") (pintype "bidirectional"))
    )
    (net (code "524") (name "VREFP$39") (class "Default")
      (node (ref "C131") (pin "1") (pinfunction "1_1") (pintype "passive"))
      (node (ref "C132") (pin "1") (pinfunction "1_1") (pintype "passive"))
      (node (ref "IC3") (pin "21") (pinfunction "VREF+_21") (pintype "input"))
      (node (ref "R84") (pin "1") (pinfunction "1_1") (pintype "passive"))
    )
    (net (code "525") (name "VRTC$45") (class "Default")
      (node (ref "C219") (pin "1") (pinfunction "1_1") (pintype "passive"))
      (node (ref "C237") (pin "1") (pinfunction "1_1") (pintype "passive"))
      (node (ref "R124") (pin "2") (pinfunction "2_2") (pintype "passive"))
      (node (ref "R125") (pin "2") (pinfunction "2_2") (pintype "passive"))
      (node (ref "U$72") (pin "D7") (pinfunction "VDDS_RTC_D7") (pintype "power_in"))
      (node (ref "U35") (pin "18") (pinfunction "VIO_18") (pintype "input"))
      (node (ref "U35") (pin "3") (pinfunction "VLDO1_3") (pintype "output"))
    )
    (net (code "526") (name "VSS_OSC$45") (class "Default")
      (node (ref "C168") (pin "2") (pinfunction "2_2") (pintype "passive"))
      (node (ref "C169") (pin "2") (pinfunction "2_2") (pintype "passive"))
      (node (ref "U$72") (pin "V11") (pinfunction "VSS_OSC_V11") (pintype "power_in"))
      (node (ref "Y3") (pin "2") (pinfunction "2_2") (pintype "passive"))
      (node (ref "Y3") (pin "4") (pinfunction "4_4") (pintype "passive"))
    )
    (net (code "527") (name "VSS_RTC$45") (class "Default")
      (node (ref "C170") (pin "2") (pinfunction "2_2") (pintype "passive"))
      (node (ref "C171") (pin "2") (pinfunction "2_2") (pintype "passive"))
      (node (ref "U$72") (pin "A5") (pinfunction "VSS_RTC_A5") (pintype "power_in"))
    )
    (net (code "528") (name "VSYNC$44") (class "Default")
      (node (ref "IC4") (pin "5") (pinfunction "VSYNC_5") (pintype "bidirectional"))
      (node (ref "R116") (pin "2") (pinfunction "2_2") (pintype "passive"))
    )
    (net (code "529") (name "V_POWER$") (class "Default")
      (node (ref "C105") (pin "1") (pinfunction "1_1") (pintype "passive"))
      (node (ref "C263") (pin "1") (pinfunction "1_1") (pintype "passive"))
      (node (ref "R140") (pin "2") (pinfunction "2_2") (pintype "passive"))
      (node (ref "U$19") (pin "7") (pinfunction "VIN_7") (pintype "bidirectional"))
    )
    (net (code "530") (name "V_POWER$21") (class "Default")
      (node (ref "C86") (pin "1") (pinfunction "1_1") (pintype "passive"))
      (node (ref "C87") (pin "1") (pinfunction "1_1") (pintype "passive"))
      (node (ref "R52") (pin "2") (pinfunction "2_2") (pintype "passive"))
      (node (ref "U$27") (pin "7") (pinfunction "VIN_7") (pintype "bidirectional"))
    )
    (net (code "531") (name "V_SYS$45") (class "Default")
      (node (ref "C222") (pin "1") (pinfunction "1_1") (pintype "passive"))
      (node (ref "C226") (pin "1") (pinfunction "1_1") (pintype "passive"))
      (node (ref "C227") (pin "1") (pinfunction "1_1") (pintype "passive"))
      (node (ref "C229") (pin "1") (pinfunction "1_1") (pintype "passive"))
      (node (ref "C235") (pin "1") (pinfunction "1_1") (pintype "passive"))
      (node (ref "L14") (pin "1") (pinfunction "1_1") (pintype "passive"))
      (node (ref "U35") (pin "2") (pinfunction "VINLDO_2") (pintype "input"))
      (node (ref "U35") (pin "21") (pinfunction "VIN_DCDC1_21") (pintype "input"))
      (node (ref "U35") (pin "22") (pinfunction "VIN_DCDC2_22") (pintype "input"))
      (node (ref "U35") (pin "32") (pinfunction "VIN_DCDC3_32") (pintype "input"))
      (node (ref "U35") (pin "39") (pinfunction "LS1_IN_39") (pintype "input"))
      (node (ref "U35") (pin "42") (pinfunction "LS2_IN_42") (pintype "input"))
      (node (ref "U35") (pin "7") (pinfunction "SYS1_7") (pintype "output"))
      (node (ref "U35") (pin "8") (pinfunction "SYS2_8") (pintype "output"))
    )
    (net (code "532") (name "WLAN_VBAT_IN$33") (class "Default")
      (node (ref "C142") (pin "1") (pinfunction "1_1") (pintype "passive"))
      (node (ref "C143") (pin "1") (pinfunction "1_1") (pintype "passive"))
      (node (ref "FB5") (pin "2") (pinfunction "2_2") (pintype "passive"))
      (node (ref "U28") (pin "46") (pinfunction "VBAT_46") (pintype "bidirectional"))
      (node (ref "U28") (pin "47") (pinfunction "VBAT_47") (pintype "bidirectional"))
    )
    (net (code "533") (name "WLAN_VIO_IN$33") (class "Default")
      (node (ref "C115") (pin "1") (pinfunction "1_1") (pintype "passive"))
      (node (ref "C174") (pin "1") (pinfunction "1_1") (pintype "passive"))
      (node (ref "C175") (pin "1") (pinfunction "1_1") (pintype "passive"))
      (node (ref "FB6") (pin "2") (pinfunction "2_2") (pintype "passive"))
      (node (ref "Q5") (pin "1") (pinfunction "OE_1") (pintype "input"))
      (node (ref "Q5") (pin "4") (pinfunction "VCC_4") (pintype "power_in"))
      (node (ref "U28") (pin "38") (pinfunction "VIO_38") (pintype "bidirectional"))
    )
    (net (code "534") (name "WLDB$33") (class "Default")
      (node (ref "U28") (pin "42") (pinfunction "WL_UART_DBG_42") (pintype "bidirectional"))
      (node (ref "WLDB") (pin "1") (pinfunction "TP_1") (pintype "bidirectional"))
    )
    (net (code "535") (name "WLRX$33") (class "Default")
      (node (ref "U28") (pin "26") (pinfunction "GPIO_2_26") (pintype "bidirectional"))
      (node (ref "WLRX") (pin "1") (pinfunction "TP_1") (pintype "bidirectional"))
    )
    (net (code "536") (name "WLTX$33") (class "Default")
      (node (ref "U28") (pin "27") (pinfunction "GPIO_1_27") (pintype "bidirectional"))
      (node (ref "WLTX") (pin "1") (pinfunction "TP_1") (pintype "bidirectional"))
    )
    (net (code "537") (name "X1$5") (class "Default")
      (node (ref "U3") (pin "1") (pinfunction "X1_1") (pintype "input"))
      (node (ref "X1") (pin "2") (pinfunction "2_2") (pintype "passive"))
    )
    (net (code "538") (name "X2$5") (class "Default")
      (node (ref "U3") (pin "2") (pinfunction "X2_2") (pintype "input"))
      (node (ref "X1") (pin "1") (pinfunction "1_1") (pintype "passive"))
    )
    (net (code "539") (name "XTAL_IN$45") (class "Default")
      (node (ref "C168") (pin "1") (pinfunction "1_1") (pintype "passive"))
      (node (ref "U$72") (pin "V10") (pinfunction "XTALIN_V10") (pintype "input"))
      (node (ref "Y3") (pin "1") (pinfunction "1_1") (pintype "passive"))
    )
    (net (code "540") (name "XTAL_OUT$45") (class "Default")
      (node (ref "C169") (pin "1") (pinfunction "1_1") (pintype "passive"))
      (node (ref "U$72") (pin "U11") (pinfunction "XTALOUT_U11") (pintype "output"))
      (node (ref "Y3") (pin "3") (pinfunction "3_3") (pintype "passive"))
    )
    (net (code "541") (name "ZQ$45") (class "Default")
      (node (ref "R133") (pin "1") (pinfunction "1_1") (pintype "passive"))
      (node (ref "U$101") (pin "L8") (pinfunction "ZQ_L8") (pintype "power_in"))
    )
    (net (code "542") (name "unconnected-(IC1-NC-Pad1)") (class "Default")
      (node (ref "IC1") (pin "1") (pinfunction "NC_1") (pintype "no_connect"))
    )
    (net (code "543") (name "unconnected-(IC1-NC-Pad3)") (class "Default")
      (node (ref "IC1") (pin "3") (pinfunction "NC_3") (pintype "no_connect"))
    )
    (net (code "544") (name "unconnected-(IC1-NC-Pad9)") (class "Default")
      (node (ref "IC1") (pin "9") (pinfunction "NC_9") (pintype "no_connect"))
    )
    (net (code "545") (name "unconnected-(IC1-NC-Pad15)") (class "Default")
      (node (ref "IC1") (pin "15") (pinfunction "NC_15") (pintype "no_connect"))
    )
    (net (code "546") (name "unconnected-(IC1-NC-Pad16)") (class "Default")
      (node (ref "IC1") (pin "16") (pinfunction "NC_16") (pintype "no_connect"))
    )
    (net (code "547") (name "unconnected-(IC1-VFB-Pad4)") (class "Default")
      (node (ref "IC1") (pin "4") (pinfunction "VFB_4") (pintype "passive"))
    )
    (net (code "548") (name "unconnected-(IC3K-PE8-Pad39)") (class "Default")
      (node (ref "IC3") (pin "39") (pinfunction "PE8_39") (pintype "bidirectional"))
    )
    (net (code "549") (name "unconnected-(IC3L-PE7-Pad38)") (class "Default")
      (node (ref "IC3") (pin "38") (pinfunction "PE7_38") (pintype "bidirectional"))
    )
    (net (code "550") (name "unconnected-(IC4-DK1-Pad8)") (class "Default")
      (node (ref "IC4") (pin "8") (pinfunction "DK1_8") (pintype "bidirectional"))
    )
    (net (code "551") (name "unconnected-(IC4-DK2-Pad7)") (class "Default")
      (node (ref "IC4") (pin "7") (pinfunction "DK2_7") (pintype "bidirectional"))
    )
    (net (code "552") (name "unconnected-(IC4-DK3-Pad6)") (class "Default")
      (node (ref "IC4") (pin "6") (pinfunction "DK3_6") (pintype "bidirectional"))
    )
    (net (code "553") (name "unconnected-(IC4-NC-Pad49)") (class "Default")
      (node (ref "IC4") (pin "49") (pinfunction "NC_49") (pintype "bidirectional"))
    )
    (net (code "554") (name "unconnected-(J10-ID-PadP4)") (class "Default")
      (node (ref "J10") (pin "P4") (pinfunction "ID_P4") (pintype "bidirectional"))
    )
    (net (code "555") (name "unconnected-(J14-ID-PadP4)") (class "Default")
      (node (ref "J14") (pin "P4") (pinfunction "ID_P4") (pintype "bidirectional"))
    )
    (net (code "556") (name "unconnected-(J15-13-Pad15)") (class "Default")
      (node (ref "J15") (pin "15") (pinfunction "13_15") (pintype "passive"))
    )
    (net (code "557") (name "unconnected-(J15-14-Pad2)") (class "Default")
      (node (ref "J15") (pin "2") (pinfunction "14_2") (pintype "passive"))
    )
    (net (code "558") (name "unconnected-(J15-19-Pad1)") (class "Default")
      (node (ref "J15") (pin "1") (pinfunction "19_1") (pintype "passive"))
    )
    (net (code "559") (name "unconnected-(JTAGH-S-Pad7)") (class "Default")
      (node (ref "JTAG") (pin "7") (pinfunction "S_7") (pintype "passive"))
    )
    (net (code "560") (name "unconnected-(RP1-Pad3)") (class "Default")
      (node (ref "RP1") (pin "3") (pinfunction "3_3") (pintype "passive"))
    )
    (net (code "561") (name "unconnected-(RP1-Pad4)") (class "Default")
      (node (ref "RP1") (pin "4") (pinfunction "4_4") (pintype "passive"))
    )
    (net (code "562") (name "unconnected-(RP1-Pad13)") (class "Default")
      (node (ref "RP1") (pin "13") (pinfunction "13_13") (pintype "passive"))
    )
    (net (code "563") (name "unconnected-(RP1-Pad14)") (class "Default")
      (node (ref "RP1") (pin "14") (pinfunction "14_14") (pintype "passive"))
    )
    (net (code "564") (name "unconnected-(RP2-Pad9)") (class "Default")
      (node (ref "RP2") (pin "9") (pinfunction "9_9") (pintype "passive"))
    )
    (net (code "565") (name "unconnected-(RP2-Pad10)") (class "Default")
      (node (ref "RP2") (pin "10") (pinfunction "10_10") (pintype "passive"))
    )
    (net (code "566") (name "unconnected-(RP4-Pad4)") (class "Default")
      (node (ref "RP4") (pin "4") (pinfunction "4_4") (pintype "passive"))
    )
    (net (code "567") (name "unconnected-(RP4-Pad7)") (class "Default")
      (node (ref "RP4") (pin "7") (pinfunction "7_7") (pintype "passive"))
    )
    (net (code "568") (name "unconnected-(RP4-Pad8)") (class "Default")
      (node (ref "RP4") (pin "8") (pinfunction "8_8") (pintype "passive"))
    )
    (net (code "569") (name "unconnected-(RP4-Pad9)") (class "Default")
      (node (ref "RP4") (pin "9") (pinfunction "9_9") (pintype "passive"))
    )
    (net (code "570") (name "unconnected-(RP4-Pad10)") (class "Default")
      (node (ref "RP4") (pin "10") (pinfunction "10_10") (pintype "passive"))
    )
    (net (code "571") (name "unconnected-(RP4-Pad13)") (class "Default")
      (node (ref "RP4") (pin "13") (pinfunction "13_13") (pintype "passive"))
    )
    (net (code "572") (name "unconnected-(RP5-Pad3)") (class "Default")
      (node (ref "RP5") (pin "3") (pinfunction "3_3") (pintype "passive"))
    )
    (net (code "573") (name "unconnected-(RP5-Pad6)") (class "Default")
      (node (ref "RP5") (pin "6") (pinfunction "6_6") (pintype "passive"))
    )
    (net (code "574") (name "unconnected-(RP6-Pad3)") (class "Default")
      (node (ref "RP6") (pin "3") (pinfunction "3_3") (pintype "passive"))
    )
    (net (code "575") (name "unconnected-(RP6-Pad6)") (class "Default")
      (node (ref "RP6") (pin "6") (pinfunction "6_6") (pintype "passive"))
    )
    (net (code "576") (name "unconnected-(RP6-Pad11)") (class "Default")
      (node (ref "RP6") (pin "11") (pinfunction "11_11") (pintype "passive"))
    )
    (net (code "577") (name "unconnected-(RP6-Pad14)") (class "Default")
      (node (ref "RP6") (pin "14") (pinfunction "14_14") (pintype "passive"))
    )
    (net (code "578") (name "unconnected-(S1-A'-PadA@2)") (class "Default")
      (node (ref "S1") (pin "A@2") (pinfunction "A'_A@2") (pintype "passive"))
    )
    (net (code "579") (name "unconnected-(S1-B-PadB@1)") (class "Default")
      (node (ref "S1") (pin "B@1") (pinfunction "B_B@1") (pintype "passive"))
    )
    (net (code "580") (name "unconnected-(S2-A'-PadA@2)") (class "Default")
      (node (ref "S2") (pin "A@2") (pinfunction "A'_A@2") (pintype "passive"))
    )
    (net (code "581") (name "unconnected-(S2-B-PadB@1)") (class "Default")
      (node (ref "S2") (pin "B@1") (pinfunction "B_B@1") (pintype "passive"))
    )
    (net (code "582") (name "unconnected-(U$19-ENA-Pad5)") (class "Default")
      (node (ref "U$19") (pin "5") (pinfunction "ENA_5") (pintype "bidirectional"))
    )
    (net (code "583") (name "unconnected-(U$19-NC1-Pad2)") (class "Default")
      (node (ref "U$19") (pin "2") (pinfunction "NC1_2") (pintype "bidirectional"))
    )
    (net (code "584") (name "unconnected-(U$19-NC2-Pad3)") (class "Default")
      (node (ref "U$19") (pin "3") (pinfunction "NC2_3") (pintype "bidirectional"))
    )
    (net (code "585") (name "unconnected-(U$27-NC1-Pad2)") (class "Default")
      (node (ref "U$27") (pin "2") (pinfunction "NC1_2") (pintype "bidirectional"))
    )
    (net (code "586") (name "unconnected-(U$27-NC2-Pad3)") (class "Default")
      (node (ref "U$27") (pin "3") (pinfunction "NC2_3") (pintype "bidirectional"))
    )
    (net (code "587") (name "unconnected-(U$30-SHIELD1-PadCD1)") (class "Default")
      (node (ref "U$30") (pin "CD1") (pinfunction "SHIELD1_CD1") (pintype "bidirectional"))
    )
    (net (code "588") (name "unconnected-(U$30-SHIELD2-PadCD2)") (class "Default")
      (node (ref "U$30") (pin "CD2") (pinfunction "SHIELD2_CD2") (pintype "bidirectional"))
    )
    (net (code "589") (name "unconnected-(U$66-AUX-Pad12)") (class "Default")
      (node (ref "U$66") (pin "12") (pinfunction "AUX_12") (pintype "bidirectional"))
    )
    (net (code "590") (name "unconnected-(U$66-VBAT-Pad11)") (class "Default")
      (node (ref "U$66") (pin "11") (pinfunction "VBAT_11") (pintype "bidirectional"))
    )
    (net (code "591") (name "unconnected-(U$69C-1A0-Pad47)") (class "Default")
      (node (ref "U$69") (pin "47") (pinfunction "1A0_47") (pintype "bidirectional"))
    )
    (net (code "592") (name "unconnected-(U$69C-1A1-Pad46)") (class "Default")
      (node (ref "U$69") (pin "46") (pinfunction "1A1_46") (pintype "bidirectional"))
    )
    (net (code "593") (name "unconnected-(U$69C-1A2-Pad44)") (class "Default")
      (node (ref "U$69") (pin "44") (pinfunction "1A2_44") (pintype "bidirectional"))
    )
    (net (code "594") (name "unconnected-(U$69C-1A3-Pad43)") (class "Default")
      (node (ref "U$69") (pin "43") (pinfunction "1A3_43") (pintype "bidirectional"))
    )
    (net (code "595") (name "unconnected-(U$69C-1A5-Pad40)") (class "Default")
      (node (ref "U$69") (pin "40") (pinfunction "1A5_40") (pintype "bidirectional"))
    )
    (net (code "596") (name "unconnected-(U$69C-1A7-Pad37)") (class "Default")
      (node (ref "U$69") (pin "37") (pinfunction "1A7_37") (pintype "bidirectional"))
    )
    (net (code "597") (name "unconnected-(U$69C-1B0-Pad2)") (class "Default")
      (node (ref "U$69") (pin "2") (pinfunction "1B0_2") (pintype "bidirectional"))
    )
    (net (code "598") (name "unconnected-(U$69C-1B1-Pad3)") (class "Default")
      (node (ref "U$69") (pin "3") (pinfunction "1B1_3") (pintype "bidirectional"))
    )
    (net (code "599") (name "unconnected-(U$69C-1B2-Pad5)") (class "Default")
      (node (ref "U$69") (pin "5") (pinfunction "1B2_5") (pintype "bidirectional"))
    )
    (net (code "600") (name "unconnected-(U$69C-1B3-Pad6)") (class "Default")
      (node (ref "U$69") (pin "6") (pinfunction "1B3_6") (pintype "bidirectional"))
    )
    (net (code "601") (name "unconnected-(U$69C-1B5-Pad9)") (class "Default")
      (node (ref "U$69") (pin "9") (pinfunction "1B5_9") (pintype "bidirectional"))
    )
    (net (code "602") (name "unconnected-(U$69C-1B7-Pad12)") (class "Default")
      (node (ref "U$69") (pin "12") (pinfunction "1B7_12") (pintype "bidirectional"))
    )
    (net (code "603") (name "unconnected-(U$69C-2A0-Pad36)") (class "Default")
      (node (ref "U$69") (pin "36") (pinfunction "2A0_36") (pintype "bidirectional"))
    )
    (net (code "604") (name "unconnected-(U$69C-2A1-Pad35)") (class "Default")
      (node (ref "U$69") (pin "35") (pinfunction "2A1_35") (pintype "bidirectional"))
    )
    (net (code "605") (name "unconnected-(U$69C-2A2-Pad33)") (class "Default")
      (node (ref "U$69") (pin "33") (pinfunction "2A2_33") (pintype "bidirectional"))
    )
    (net (code "606") (name "unconnected-(U$69C-2A3-Pad32)") (class "Default")
      (node (ref "U$69") (pin "32") (pinfunction "2A3_32") (pintype "bidirectional"))
    )
    (net (code "607") (name "unconnected-(U$69C-2A4-Pad30)") (class "Default")
      (node (ref "U$69") (pin "30") (pinfunction "2A4_30") (pintype "bidirectional"))
    )
    (net (code "608") (name "unconnected-(U$69C-2A5-Pad29)") (class "Default")
      (node (ref "U$69") (pin "29") (pinfunction "2A5_29") (pintype "bidirectional"))
    )
    (net (code "609") (name "unconnected-(U$69C-2A6-Pad27)") (class "Default")
      (node (ref "U$69") (pin "27") (pinfunction "2A6_27") (pintype "bidirectional"))
    )
    (net (code "610") (name "unconnected-(U$69C-2A7-Pad26)") (class "Default")
      (node (ref "U$69") (pin "26") (pinfunction "2A7_26") (pintype "bidirectional"))
    )
    (net (code "611") (name "unconnected-(U$69C-2B0-Pad13)") (class "Default")
      (node (ref "U$69") (pin "13") (pinfunction "2B0_13") (pintype "bidirectional"))
    )
    (net (code "612") (name "unconnected-(U$69C-2B1-Pad14)") (class "Default")
      (node (ref "U$69") (pin "14") (pinfunction "2B1_14") (pintype "bidirectional"))
    )
    (net (code "613") (name "unconnected-(U$69C-2B2-Pad16)") (class "Default")
      (node (ref "U$69") (pin "16") (pinfunction "2B2_16") (pintype "bidirectional"))
    )
    (net (code "614") (name "unconnected-(U$69C-2B3-Pad17)") (class "Default")
      (node (ref "U$69") (pin "17") (pinfunction "2B3_17") (pintype "bidirectional"))
    )
    (net (code "615") (name "unconnected-(U$69C-2B4-Pad19)") (class "Default")
      (node (ref "U$69") (pin "19") (pinfunction "2B4_19") (pintype "bidirectional"))
    )
    (net (code "616") (name "unconnected-(U$69C-2B5-Pad20)") (class "Default")
      (node (ref "U$69") (pin "20") (pinfunction "2B5_20") (pintype "bidirectional"))
    )
    (net (code "617") (name "unconnected-(U$69C-2B6-Pad22)") (class "Default")
      (node (ref "U$69") (pin "22") (pinfunction "2B6_22") (pintype "bidirectional"))
    )
    (net (code "618") (name "unconnected-(U$69C-2B7-Pad23)") (class "Default")
      (node (ref "U$69") (pin "23") (pinfunction "2B7_23") (pintype "bidirectional"))
    )
    (net (code "619") (name "unconnected-(U$70-AVDD-Pad35)") (class "Default")
      (node (ref "U$70") (pin "35") (pinfunction "AVDD_35") (pintype "no_connect"))
    )
    (net (code "620") (name "unconnected-(U$72A-VDD_MPU_MON-PadA2)") (class "Default")
      (node (ref "U$72") (pin "A2") (pinfunction "VDD_MPU_MON_A2") (pintype "bidirectional"))
    )
    (net (code "621") (name "unconnected-(U$72A-WARMRSTN-PadA10)") (class "Default")
      (node (ref "U$72") (pin "A10") (pinfunction "WARMRSTN_A10") (pintype "bidirectional"))
    )
    (net (code "622") (name "unconnected-(U$72A-XDMA_EVENT_INTR1|TCLKIN|CLKOUT2|TIMER7|PR1_PRU0_PRU_R31_16|EMU3|GPIO0_20-PadD14)") (class "Default")
      (node (ref "U$72") (pin "D14") (pinfunction "XDMA_EVENT_INTR1|TCLKIN|CLKOUT2|TIMER7|PR1_PRU0_PRU_R31_16|EMU3|GPIO0_20_D14") (pintype "input"))
    )
    (net (code "623") (name "unconnected-(U$72B-AIN0-PadB6)") (class "Default")
      (node (ref "U$72") (pin "B6") (pinfunction "AIN0_B6") (pintype "bidirectional"))
    )
    (net (code "624") (name "unconnected-(U$72B-AIN1-PadC7)") (class "Default")
      (node (ref "U$72") (pin "C7") (pinfunction "AIN1_C7") (pintype "bidirectional"))
    )
    (net (code "625") (name "unconnected-(U$72B-AIN2-PadB7)") (class "Default")
      (node (ref "U$72") (pin "B7") (pinfunction "AIN2_B7") (pintype "bidirectional"))
    )
    (net (code "626") (name "unconnected-(U$72B-AIN3-PadA7)") (class "Default")
      (node (ref "U$72") (pin "A7") (pinfunction "AIN3_A7") (pintype "bidirectional"))
    )
    (net (code "627") (name "unconnected-(U$72B-AIN4-PadC8)") (class "Default")
      (node (ref "U$72") (pin "C8") (pinfunction "AIN4_C8") (pintype "bidirectional"))
    )
    (net (code "628") (name "unconnected-(U$72B-AIN5-PadB8)") (class "Default")
      (node (ref "U$72") (pin "B8") (pinfunction "AIN5_B8") (pintype "bidirectional"))
    )
    (net (code "629") (name "unconnected-(U$72B-AIN6-PadA8)") (class "Default")
      (node (ref "U$72") (pin "A8") (pinfunction "AIN6_A8") (pintype "bidirectional"))
    )
    (net (code "630") (name "unconnected-(U$72B-GPMC_A7|GMII2_RXCLK|RGMII2_RCLK|MMC2_DAT5|GPMC_A23|PR1_MII1_RXD1|EQEP1_STROBE|GPIO1_23-PadT15)") (class "Default")
      (node (ref "U$72") (pin "T15") (pinfunction "GPMC_A7|GMII2_RXCLK|RGMII2_RCLK|MMC2_DAT5|GPMC_A23|PR1_MII1_RXD1|EQEP1_STROBE|GPIO1_23_T15") (pintype "output"))
    )
    (net (code "631") (name "unconnected-(U$72B-GPMC_A8|GMII2_RXD3|RGMII2_RD3|MMC2_DAT6|GPMC_A24|PR1_MII1_RXD0|MCASP0_ACLKX|GPIO1_24-PadV16)") (class "Default")
      (node (ref "U$72") (pin "V16") (pinfunction "GPMC_A8|GMII2_RXD3|RGMII2_RD3|MMC2_DAT6|GPMC_A24|PR1_MII1_RXD0|MCASP0_ACLKX|GPIO1_24_V16") (pintype "output"))
    )
    (net (code "632") (name "unconnected-(U$72B-GPMC_A9|GMII2_RXD2|RGMII2_RD2|MMC2_DAT7|GPMC_A25|PR1_MII_MR1_CLK|MCASP0_FSX|GPIO1_25-PadU16)") (class "Default")
      (node (ref "U$72") (pin "U16") (pinfunction "GPMC_A9|GMII2_RXD2|RGMII2_RD2|MMC2_DAT7|GPMC_A25|PR1_MII_MR1_CLK|MCASP0_FSX|GPIO1_25_U16") (pintype "output"))
    )
    (net (code "633") (name "unconnected-(U$72B-GPMC_A10|GMII2_RXD1|RGMII2_RD1|RMII2_RXD1|GPMC_A26|PR1_MII1_CRS|MCASP0_AXR0|GPIO1_26-PadT16)") (class "Default")
      (node (ref "U$72") (pin "T16") (pinfunction "GPMC_A10|GMII2_RXD1|RGMII2_RD1|RMII2_RXD1|GPMC_A26|PR1_MII1_CRS|MCASP0_AXR0|GPIO1_26_T16") (pintype "output"))
    )
    (net (code "634") (name "unconnected-(U$72B-GPMC_AD0|MMC1_DAT0||||||GPIO1_0-PadU7)") (class "Default")
      (node (ref "U$72") (pin "U7") (pinfunction "GPMC_AD0|MMC1_DAT0||||||GPIO1_0_U7") (pintype "bidirectional"))
    )
    (net (code "635") (name "unconnected-(U$72B-GPMC_AD6|MMC1_DAT6||||||GPIO1_6-PadR9)") (class "Default")
      (node (ref "U$72") (pin "R9") (pinfunction "GPMC_AD6|MMC1_DAT6||||||GPIO1_6_R9") (pintype "bidirectional"))
    )
    (net (code "636") (name "unconnected-(U$72B-GPMC_AD7|MMC1_DAT7||||||GPIO1_7-PadT9)") (class "Default")
      (node (ref "U$72") (pin "T9") (pinfunction "GPMC_AD7|MMC1_DAT7||||||GPIO1_7_T9") (pintype "bidirectional"))
    )
    (net (code "637") (name "unconnected-(U$72B-GPMC_ADVN_ALE|TIMER4|GPIO2_2-PadR7)") (class "Default")
      (node (ref "U$72") (pin "R7") (pinfunction "GPMC_ADVN_ALE|TIMER4|GPIO2_2_R7") (pintype "output"))
    )
    (net (code "638") (name "unconnected-(U$72B-GPMC_BE0N_CLE|TIMER5|GPIO2_5-PadT6)") (class "Default")
      (node (ref "U$72") (pin "T6") (pinfunction "GPMC_BE0N_CLE|TIMER5|GPIO2_5_T6") (pintype "output"))
    )
    (net (code "639") (name "unconnected-(U$72B-GPMC_OEN_REN|TIMER7|EMU4|GPIO2_3-PadT7)") (class "Default")
      (node (ref "U$72") (pin "T7") (pinfunction "GPMC_OEN_REN|TIMER7|EMU4|GPIO2_3_T7") (pintype "output"))
    )
    (net (code "640") (name "unconnected-(U$72B-GPMC_WAIT0|GM112_CRS|GPMC_CSN4|RMII2_CRS_DV|MMC1_SDCD|PR1_MII1_RXDV|UART4_RXD|GPIO0_30-PadT17)") (class "Default")
      (node (ref "U$72") (pin "T17") (pinfunction "GPMC_WAIT0|GM112_CRS|GPMC_CSN4|RMII2_CRS_DV|MMC1_SDCD|PR1_MII1_RXDV|UART4_RXD|GPIO0_30_T17") (pintype "input"))
    )
    (net (code "641") (name "unconnected-(U$72B-GPMC_WEN|TIMER6|GPIO2_4-PadU6)") (class "Default")
      (node (ref "U$72") (pin "U6") (pinfunction "GPMC_WEN|TIMER6|GPIO2_4_U6") (pintype "output"))
    )
    (net (code "642") (name "unconnected-(U$72B-GPMC_WPN|GMII2_RXERR|GPMC_CSN5|RMII2_RXERR|MMC2_SDCD|PR1_MDIO_MDCLK|UART4_TXD|GPIO0_31-PadU17)") (class "Default")
      (node (ref "U$72") (pin "U17") (pinfunction "GPMC_WPN|GMII2_RXERR|GPMC_CSN5|RMII2_RXERR|MMC2_SDCD|PR1_MDIO_MDCLK|UART4_TXD|GPIO0_31_U17") (pintype "output"))
    )
    (net (code "643") (name "unconnected-(U$72C-GMII1_RXD0|RMII1_RXD0|RGMII1_RD0|MCASP1_AHCLKX|MCASP1_AHCLKR|MCASP1_ACLKR|MCASP0_AXR3|GPIO2_21-PadM16)") (class "Default")
      (node (ref "U$72") (pin "M16") (pinfunction "GMII1_RXD0|RMII1_RXD0|RGMII1_RD0|MCASP1_AHCLKX|MCASP1_AHCLKR|MCASP1_ACLKR|MCASP0_AXR3|GPIO2_21_M16") (pintype "input"))
    )
    (net (code "644") (name "unconnected-(U$72C-GMII1_RXD1|RMII1_RXD1|RGMII1_RD1|MCASP1_AXR3|MCASP1_FSR|EQEP0_STROBE|MMC2_CLK|GPIO2_20-PadL15)") (class "Default")
      (node (ref "U$72") (pin "L15") (pinfunction "GMII1_RXD1|RMII1_RXD1|RGMII1_RD1|MCASP1_AXR3|MCASP1_FSR|EQEP0_STROBE|MMC2_CLK|GPIO2_20_L15") (pintype "input"))
    )
    (net (code "645") (name "unconnected-(U$72C-GMII1_RXD2|UART3_TXD|RGMII1_RD2|MMC0_DAT4|MMC1_DAT3|UART1_RIN|MCASP0_AXR1|GPIO2_19-PadL16)") (class "Default")
      (node (ref "U$72") (pin "L16") (pinfunction "GMII1_RXD2|UART3_TXD|RGMII1_RD2|MMC0_DAT4|MMC1_DAT3|UART1_RIN|MCASP0_AXR1|GPIO2_19_L16") (pintype "input"))
    )
    (net (code "646") (name "unconnected-(U$72C-GMII1_TXD0|RMII1_TXD0|RGMII1_TD0|MCASP1_AXR2|MCASP1_ACLKR|EQEP0B_IN|MMC1_CLK|GPIO0_28-PadK17)") (class "Default")
      (node (ref "U$72") (pin "K17") (pinfunction "GMII1_TXD0|RMII1_TXD0|RGMII1_TD0|MCASP1_AXR2|MCASP1_ACLKR|EQEP0B_IN|MMC1_CLK|GPIO0_28_K17") (pintype "output"))
    )
    (net (code "647") (name "unconnected-(U$72C-GMII1_TXD1|RMII1_TXD1|RGMII1_TD1|MCASP1_FSR|MCASP1_AXR1|EQEP0A_IN|MMC1_CMD|GPIO0_21-PadK16)") (class "Default")
      (node (ref "U$72") (pin "K16") (pinfunction "GMII1_TXD1|RMII1_TXD1|RGMII1_TD1|MCASP1_FSR|MCASP1_AXR1|EQEP0A_IN|MMC1_CMD|GPIO0_21_K16") (pintype "output"))
    )
    (net (code "648") (name "unconnected-(U$72C-GMII1_TXD2|DCAN0_RX|RGMII1_TD2|UART4_TXD|MCASP1_AXR0|MMC2_DAT2|MCASP0_AHCLKX|GPIO0_17-PadK15)") (class "Default")
      (node (ref "U$72") (pin "K15") (pinfunction "GMII1_TXD2|DCAN0_RX|RGMII1_TD2|UART4_TXD|MCASP1_AXR0|MMC2_DAT2|MCASP0_AHCLKX|GPIO0_17_K15") (pintype "output"))
    )
    (net (code "649") (name "unconnected-(U$72C-GMII1_TXD3|DCAN0_TX|RGMII1_TD3|UART4_RXD|MCASP1_FSX|MMC2_DAT1|MCASP0_FSR|GPIO0_16-PadJ18)") (class "Default")
      (node (ref "U$72") (pin "J18") (pinfunction "GMII1_TXD3|DCAN0_TX|RGMII1_TD3|UART4_RXD|MCASP1_FSX|MMC2_DAT1|MCASP0_FSR|GPIO0_16_J18") (pintype "output"))
    )
    (net (code "650") (name "unconnected-(U$72C-GMII1_TXEN|RMII1_TXEN|RGMII1_TCTL|TIMER4|MCASP1_AXR0|EQEP0_INDEX|MMC2_CMD|GPIO3_3-PadJ16)") (class "Default")
      (node (ref "U$72") (pin "J16") (pinfunction "GMII1_TXEN|RMII1_TXEN|RGMII1_TCTL|TIMER4|MCASP1_AXR0|EQEP0_INDEX|MMC2_CMD|GPIO3_3_J16") (pintype "input"))
    )
    (net (code "651") (name "unconnected-(U$72C-MCASP0_FSR|EQEP0B_IN|MCASP0_AXR3|MCASP1_FSX|EMU2|PR1_PRU0_PRU_R30_5|PR1_PRU0_PRU_R31_5|GPIO3_19-PadC13)") (class "Default")
      (node (ref "U$72") (pin "C13") (pinfunction "MCASP0_FSR|EQEP0B_IN|MCASP0_AXR3|MCASP1_FSX|EMU2|PR1_PRU0_PRU_R30_5|PR1_PRU0_PRU_R31_5|GPIO3_19_C13") (pintype "bidirectional"))
    )
    (net (code "652") (name "unconnected-(U$72C-MDIO_CLK|TIMER5|UART5_TXD|UART3_RTSN|MMC0_SDWP|MMC1_CLK|MMC2_CLK|GPIO0_1-PadM18)") (class "Default")
      (node (ref "U$72") (pin "M18") (pinfunction "MDIO_CLK|TIMER5|UART5_TXD|UART3_RTSN|MMC0_SDWP|MMC1_CLK|MMC2_CLK|GPIO0_1_M18") (pintype "bidirectional"))
    )
    (net (code "653") (name "unconnected-(U$72C-MDIO_DATA|TIMER6|UART5_RXD|UART3_CTSN|MMC0_SDCD|MMC1_CMD|MMC2_CMD|GPIO0_0-PadM17)") (class "Default")
      (node (ref "U$72") (pin "M17") (pinfunction "MDIO_DATA|TIMER6|UART5_RXD|UART3_CTSN|MMC0_SDCD|MMC1_CMD|MMC2_CMD|GPIO0_0_M17") (pintype "bidirectional"))
    )
    (net (code "654") (name "unconnected-(U$72C-RESERVED-PadA3)") (class "Default")
      (node (ref "U$72") (pin "A3") (pinfunction "RESERVED_A3") (pintype "output"))
    )
    (net (code "655") (name "unconnected-(U$72C-RMII1_REFCLK|XDMA_EVENT_INTR2|SPI1_CS0|UART5_TXD|MCASP1_AXR3|MMC0_POW|MCASP1_AHCLKX|GPIO0_29-PadH18)") (class "Default")
      (node (ref "U$72") (pin "H18") (pinfunction "RMII1_REFCLK|XDMA_EVENT_INTR2|SPI1_CS0|UART5_TXD|MCASP1_AXR3|MMC0_POW|MCASP1_AHCLKX|GPIO0_29_H18") (pintype "bidirectional"))
    )
    (net (code "656") (name "unconnected-(U$72C-RTC_KALDO_ENN-PadB4)") (class "Default")
      (node (ref "U$72") (pin "B4") (pinfunction "RTC_KALDO_ENN_B4") (pintype "input"))
    )
    (net (code "657") (name "unconnected-(U$72C-SPI0_CS1|UART3_RXD|ECAP1_IN_PWM1_OUT|MMC0_POW|XDMA_EVENT_INTR2|MMC0_SDCD|EMU4|GPIO0_6-PadC15)") (class "Default")
      (node (ref "U$72") (pin "C15") (pinfunction "SPI0_CS1|UART3_RXD|ECAP1_IN_PWM1_OUT|MMC0_POW|XDMA_EVENT_INTR2|MMC0_SDCD|EMU4|GPIO0_6_C15") (pintype "bidirectional"))
    )
    (net (code "658") (name "unconnected-(U$72C-TCK-PadA12)") (class "Default")
      (node (ref "U$72") (pin "A12") (pinfunction "TCK_A12") (pintype "input"))
    )
    (net (code "659") (name "unconnected-(U$72C-TDI-PadB11)") (class "Default")
      (node (ref "U$72") (pin "B11") (pinfunction "TDI_B11") (pintype "input"))
    )
    (net (code "660") (name "unconnected-(U$72C-TDO-PadA11)") (class "Default")
      (node (ref "U$72") (pin "A11") (pinfunction "TDO_A11") (pintype "output"))
    )
    (net (code "661") (name "unconnected-(U$72C-TMS-PadC11)") (class "Default")
      (node (ref "U$72") (pin "C11") (pinfunction "TMS_C11") (pintype "input"))
    )
    (net (code "662") (name "unconnected-(U$72C-TRSTN-PadB10)") (class "Default")
      (node (ref "U$72") (pin "B10") (pinfunction "TRSTN_B10") (pintype "input"))
    )
    (net (code "663") (name "unconnected-(U$72C-USB0_CE-PadM15)") (class "Default")
      (node (ref "U$72") (pin "M15") (pinfunction "USB0_CE_M15") (pintype "bidirectional"))
    )
    (net (code "664") (name "unconnected-(U$72C-USB0_DRVVBUS-PadF16)") (class "Default")
      (node (ref "U$72") (pin "F16") (pinfunction "USB0_DRVVBUS_F16") (pintype "output"))
    )
    (net (code "665") (name "unconnected-(U$72C-USB0_ID-PadP16)") (class "Default")
      (node (ref "U$72") (pin "P16") (pinfunction "USB0_ID_P16") (pintype "bidirectional"))
    )
    (net (code "666") (name "unconnected-(U$72C-USB1_CE-PadP18)") (class "Default")
      (node (ref "U$72") (pin "P18") (pinfunction "USB1_CE_P18") (pintype "bidirectional"))
    )
    (net (code "667") (name "unconnected-(U8-A1-Pad1)") (class "Default")
      (node (ref "U8") (pin "1") (pinfunction "A1_1") (pintype "bidirectional"))
    )
    (net (code "668") (name "unconnected-(U8-A8-Pad9)") (class "Default")
      (node (ref "U8") (pin "9") (pinfunction "A8_9") (pintype "bidirectional"))
    )
    (net (code "669") (name "unconnected-(U8-B1-Pad20)") (class "Default")
      (node (ref "U8") (pin "20") (pinfunction "B1_20") (pintype "bidirectional"))
    )
    (net (code "670") (name "unconnected-(U8-B8-Pad12)") (class "Default")
      (node (ref "U8") (pin "12") (pinfunction "B8_12") (pintype "bidirectional"))
    )
    (net (code "671") (name "unconnected-(U9-Pad1)") (class "Default")
      (node (ref "U9") (pin "1") (pinfunction "1_1") (pintype "passive"))
    )
    (net (code "672") (name "unconnected-(U15-GPIO1-Pad35)") (class "Default")
      (node (ref "U15") (pin "35") (pinfunction "GPIO1_35") (pintype "bidirectional"))
    )
    (net (code "673") (name "unconnected-(U15-GPIO2-Pad34)") (class "Default")
      (node (ref "U15") (pin "34") (pinfunction "GPIO2_34") (pintype "bidirectional"))
    )
    (net (code "674") (name "unconnected-(U15-HPLCOM-Pad19)") (class "Default")
      (node (ref "U15") (pin "19") (pinfunction "HPLCOM_19") (pintype "bidirectional"))
    )
    (net (code "675") (name "unconnected-(U15-HPRCOM-Pad22)") (class "Default")
      (node (ref "U15") (pin "22") (pinfunction "HPRCOM_22") (pintype "bidirectional"))
    )
    (net (code "676") (name "unconnected-(U15-HPROUT-Pad23)") (class "Default")
      (node (ref "U15") (pin "23") (pinfunction "HPROUT_23") (pintype "bidirectional"))
    )
    (net (code "677") (name "unconnected-(U15-LEFT_LOM-Pad30)") (class "Default")
      (node (ref "U15") (pin "30") (pinfunction "LEFT_LOM_30") (pintype "bidirectional"))
    )
    (net (code "678") (name "unconnected-(U15-LEFT_LOP-Pad29)") (class "Default")
      (node (ref "U15") (pin "29") (pinfunction "LEFT_LOP_29") (pintype "bidirectional"))
    )
    (net (code "679") (name "unconnected-(U15-LINE1LP-Pad3)") (class "Default")
      (node (ref "U15") (pin "3") (pinfunction "LINE1LP_3") (pintype "bidirectional"))
    )
    (net (code "680") (name "unconnected-(U15-LINE1RP-Pad5)") (class "Default")
      (node (ref "U15") (pin "5") (pinfunction "LINE1RP_5") (pintype "bidirectional"))
    )
    (net (code "681") (name "unconnected-(U15-LINE2LM-Pad8)") (class "Default")
      (node (ref "U15") (pin "8") (pinfunction "LINE2LM_8") (pintype "bidirectional"))
    )
    (net (code "682") (name "unconnected-(U15-LINE2LP-Pad7)") (class "Default")
      (node (ref "U15") (pin "7") (pinfunction "LINE2LP_7") (pintype "bidirectional"))
    )
    (net (code "683") (name "unconnected-(U15-LINE2RM-Pad10)") (class "Default")
      (node (ref "U15") (pin "10") (pinfunction "LINE2RM_10") (pintype "bidirectional"))
    )
    (net (code "684") (name "unconnected-(U15-LINE2RP-Pad9)") (class "Default")
      (node (ref "U15") (pin "9") (pinfunction "LINE2RP_9") (pintype "bidirectional"))
    )
    (net (code "685") (name "unconnected-(U15-MFP2-Pad47)") (class "Default")
      (node (ref "U15") (pin "47") (pinfunction "MFP2_47") (pintype "bidirectional"))
    )
    (net (code "686") (name "unconnected-(U15-MFP3-Pad48)") (class "Default")
      (node (ref "U15") (pin "48") (pinfunction "MFP3_48") (pintype "bidirectional"))
    )
    (net (code "687") (name "unconnected-(U15-MIC3R-Pad14)") (class "Default")
      (node (ref "U15") (pin "14") (pinfunction "MIC3R_14") (pintype "bidirectional"))
    )
    (net (code "688") (name "unconnected-(U15-MONO_LOM-Pad28)") (class "Default")
      (node (ref "U15") (pin "28") (pinfunction "MONO_LOM_28") (pintype "bidirectional"))
    )
    (net (code "689") (name "unconnected-(U15-MONO_LOP-Pad27)") (class "Default")
      (node (ref "U15") (pin "27") (pinfunction "MONO_LOP_27") (pintype "bidirectional"))
    )
    (net (code "690") (name "unconnected-(U15-RIGHT_LOM-Pad32)") (class "Default")
      (node (ref "U15") (pin "32") (pinfunction "RIGHT_LOM_32") (pintype "bidirectional"))
    )
    (net (code "691") (name "unconnected-(U15-RIGHT_LOP-Pad31)") (class "Default")
      (node (ref "U15") (pin "31") (pinfunction "RIGHT_LOP_31") (pintype "bidirectional"))
    )
    (net (code "692") (name "unconnected-(U18-NC-Pad8)") (class "Default")
      (node (ref "U18") (pin "8") (pinfunction "NC_8") (pintype "no_connect"))
    )
    (net (code "693") (name "unconnected-(U18-NC-Pad9)") (class "Default")
      (node (ref "U18") (pin "9") (pinfunction "NC_9") (pintype "no_connect"))
    )
    (net (code "694") (name "unconnected-(U18-NC-Pad20)") (class "Default")
      (node (ref "U18") (pin "20") (pinfunction "NC_20") (pintype "no_connect"))
    )
    (net (code "695") (name "unconnected-(U18-NC-Pad21)") (class "Default")
      (node (ref "U18") (pin "21") (pinfunction "NC_21") (pintype "no_connect"))
    )
    (net (code "696") (name "unconnected-(U18-OCS_N3-Pad19)") (class "Default")
      (node (ref "U18") (pin "19") (pinfunction "OCS_N3_19") (pintype "bidirectional"))
    )
    (net (code "697") (name "unconnected-(U18-PRTPWR3-Pad18)") (class "Default")
      (node (ref "U18") (pin "18") (pinfunction "PRTPWR3_18") (pintype "bidirectional"))
    )
    (net (code "698") (name "unconnected-(U18-TEST_NC-Pad11)") (class "Default")
      (node (ref "U18") (pin "11") (pinfunction "TEST_NC_11") (pintype "no_connect"))
    )
    (net (code "699") (name "unconnected-(U18-USBDM_DN3-Pad6)") (class "Default")
      (node (ref "U18") (pin "6") (pinfunction "USBDM_DN3_6") (pintype "bidirectional"))
    )
    (net (code "700") (name "unconnected-(U18-USBDP_DN3-Pad7)") (class "Default")
      (node (ref "U18") (pin "7") (pinfunction "USBDP_DN3_7") (pintype "bidirectional"))
    )
    (net (code "701") (name "unconnected-(U20-A1-Pad1)") (class "Default")
      (node (ref "U20") (pin "1") (pinfunction "A1_1") (pintype "bidirectional"))
    )
    (net (code "702") (name "unconnected-(U20-A5-Pad6)") (class "Default")
      (node (ref "U20") (pin "6") (pinfunction "A5_6") (pintype "bidirectional"))
    )
    (net (code "703") (name "unconnected-(U20-A8-Pad9)") (class "Default")
      (node (ref "U20") (pin "9") (pinfunction "A8_9") (pintype "bidirectional"))
    )
    (net (code "704") (name "unconnected-(U20-B1-Pad20)") (class "Default")
      (node (ref "U20") (pin "20") (pinfunction "B1_20") (pintype "bidirectional"))
    )
    (net (code "705") (name "unconnected-(U20-B5-Pad15)") (class "Default")
      (node (ref "U20") (pin "15") (pinfunction "B5_15") (pintype "bidirectional"))
    )
    (net (code "706") (name "unconnected-(U20-B8-Pad12)") (class "Default")
      (node (ref "U20") (pin "12") (pinfunction "B8_12") (pintype "bidirectional"))
    )
    (net (code "707") (name "unconnected-(U28-2G4_ANT2_W-Pad18)") (class "Default")
      (node (ref "U28") (pin "18") (pinfunction "2G4_ANT2_W_18") (pintype "bidirectional"))
    )
    (net (code "708") (name "unconnected-(U28-GPIO9-Pad3)") (class "Default")
      (node (ref "U28") (pin "3") (pinfunction "GPIO9_3") (pintype "bidirectional"))
    )
    (net (code "709") (name "unconnected-(U28-GPIO10-Pad4)") (class "Default")
      (node (ref "U28") (pin "4") (pinfunction "GPIO10_4") (pintype "bidirectional"))
    )
    (net (code "710") (name "unconnected-(U28-GPIO11-Pad2)") (class "Default")
      (node (ref "U28") (pin "2") (pinfunction "GPIO11_2") (pintype "bidirectional"))
    )
    (net (code "711") (name "unconnected-(U28-GPIO12-Pad5)") (class "Default")
      (node (ref "U28") (pin "5") (pinfunction "GPIO12_5") (pintype "bidirectional"))
    )
    (net (code "712") (name "unconnected-(U28-GPIO_4-Pad25)") (class "Default")
      (node (ref "U28") (pin "25") (pinfunction "GPIO_4_25") (pintype "bidirectional"))
    )
    (net (code "713") (name "unconnected-(U28-RESERVED1-Pad21)") (class "Default")
      (node (ref "U28") (pin "21") (pinfunction "RESERVED1_21") (pintype "bidirectional"))
    )
    (net (code "714") (name "unconnected-(U28-RESERVED2-Pad22)") (class "Default")
      (node (ref "U28") (pin "22") (pinfunction "RESERVED2_22") (pintype "bidirectional"))
    )
    (net (code "715") (name "unconnected-(U28-RESERVED3-Pad62)") (class "Default")
      (node (ref "U28") (pin "62") (pinfunction "RESERVED3_62") (pintype "bidirectional"))
    )
    (net (code "716") (name "unconnected-(U35-MUX_IN-Pad14)") (class "Default")
      (node (ref "U35") (pin "14") (pinfunction "MUX_IN_14") (pintype "input"))
    )
    (net (code "717") (name "unconnected-(U35-NC-Pad15)") (class "Default")
      (node (ref "U35") (pin "15") (pinfunction "NC_15") (pintype "no_connect"))
    )
    (net (code "718") (name "unconnected-(U35-NC1-Pad17)") (class "Default")
      (node (ref "U35") (pin "17") (pinfunction "NC1_17") (pintype "no_connect"))
    )
    (net (code "719") (name "unconnected-(U35-TS-Pad11)") (class "Default")
      (node (ref "U35") (pin "11") (pinfunction "TS_11") (pintype "input"))
    )
    (net (code "720") (name "unconnected-(U35-USB-Pad12)") (class "Default")
      (node (ref "U35") (pin "12") (pinfunction "USB_12") (pintype "input"))
    )
    (net (code "721") (name "unconnected-(U35-~{PB_IN}-Pad25)") (class "Default")
      (node (ref "U35") (pin "25") (pinfunction "~{PB_IN}_25") (pintype "input"))
    )
    (net (code "722") (name "unconnected-(U35-~{RESET}-Pad44)") (class "Default")
      (node (ref "U35") (pin "44") (pinfunction "~{RESET}_44") (pintype "input"))
    )
    (net (code "723") (name "unconnected-(U36-INT-PadP7)") (class "Default")
      (node (ref "U36") (pin "P7") (pinfunction "INT_P7") (pintype "bidirectional"))
    )
    (net (code "724") (name "~{3V_SPI_TS_CS$43}") (class "Default")
      (node (ref "U$66") (pin "3") (pinfunction "~{CS}_3") (pintype "bidirectional"))
      (node (ref "U$67") (pin "46") (pinfunction "1A1_46") (pintype "bidirectional"))
    )
    (net (code "725") (name "~{DDR3_RESET$45}") (class "Default")
      (node (ref "R134") (pin "2") (pinfunction "2_2") (pintype "passive"))
      (node (ref "U$101") (pin "T2") (pinfunction "~{RESET}_T2") (pintype "power_in"))
      (node (ref "U$72") (pin "G2") (pinfunction "DDR_RESETN_G2") (pintype "output"))
    )
    (net (code "726") (name "~{PD$44}") (class "Default")
      (node (ref "IC4") (pin "10") (pinfunction "~{PD}_10") (pintype "bidirectional"))
      (node (ref "R103") (pin "2") (pinfunction "2_2") (pintype "passive"))
      (node (ref "R143") (pin "2") (pinfunction "2_2") (pintype "passive"))
    )
  )
)
